# icyradio-main.net
KiCad netlist of a schematic drawn in EAGLE
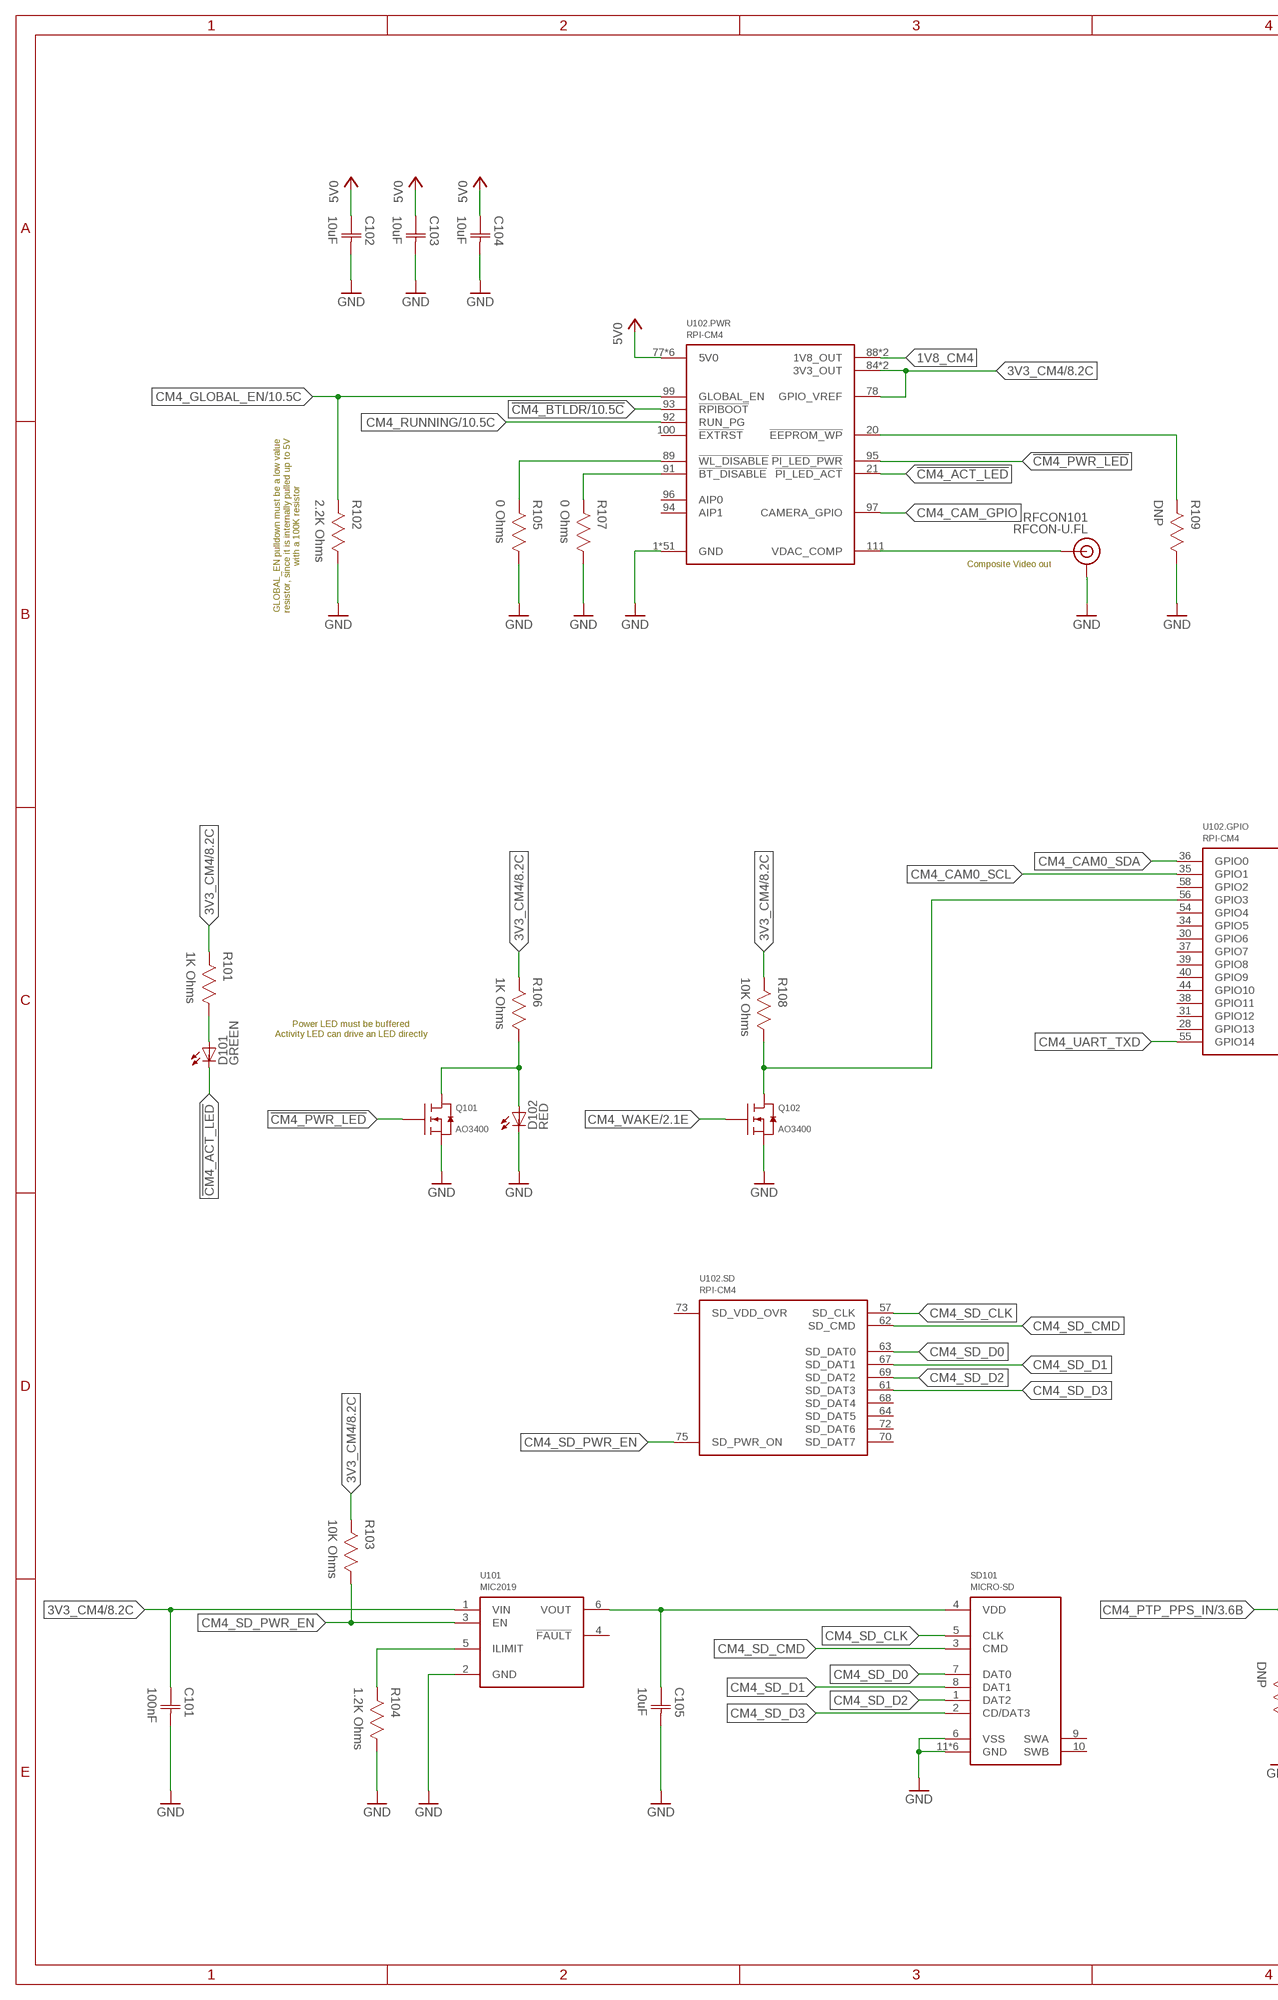
[diagram p0: schematic, sheet 1, part 1 of 2]
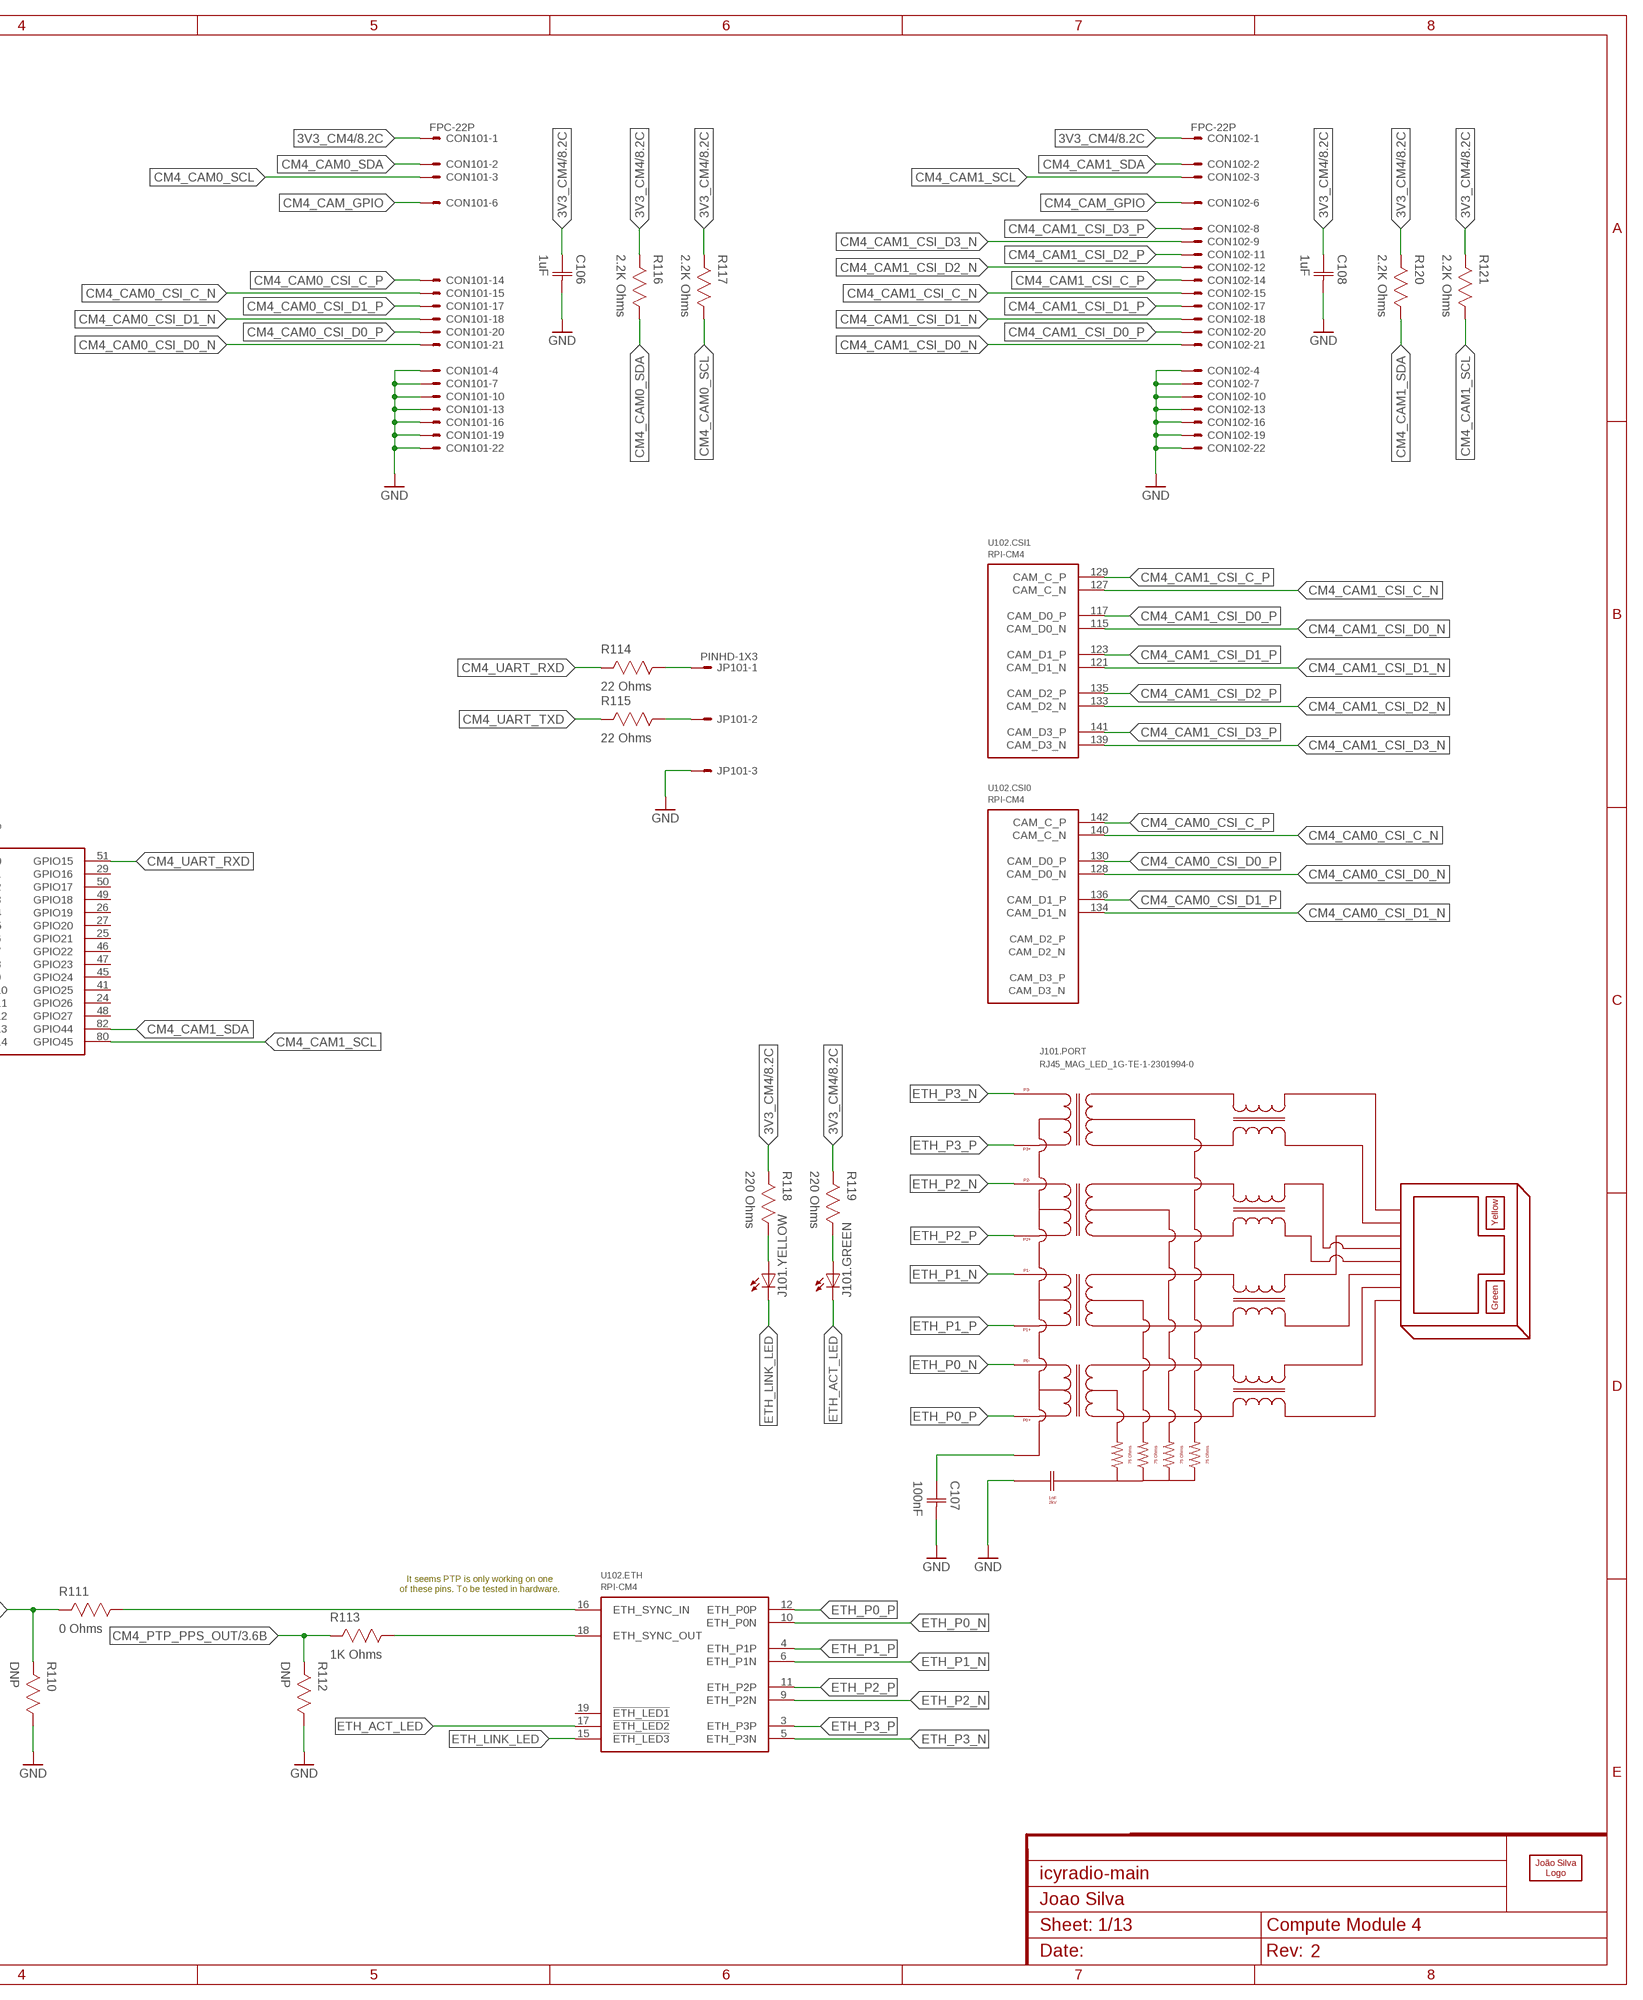
[diagram p1: schematic, sheet 1, part 2 of 2]
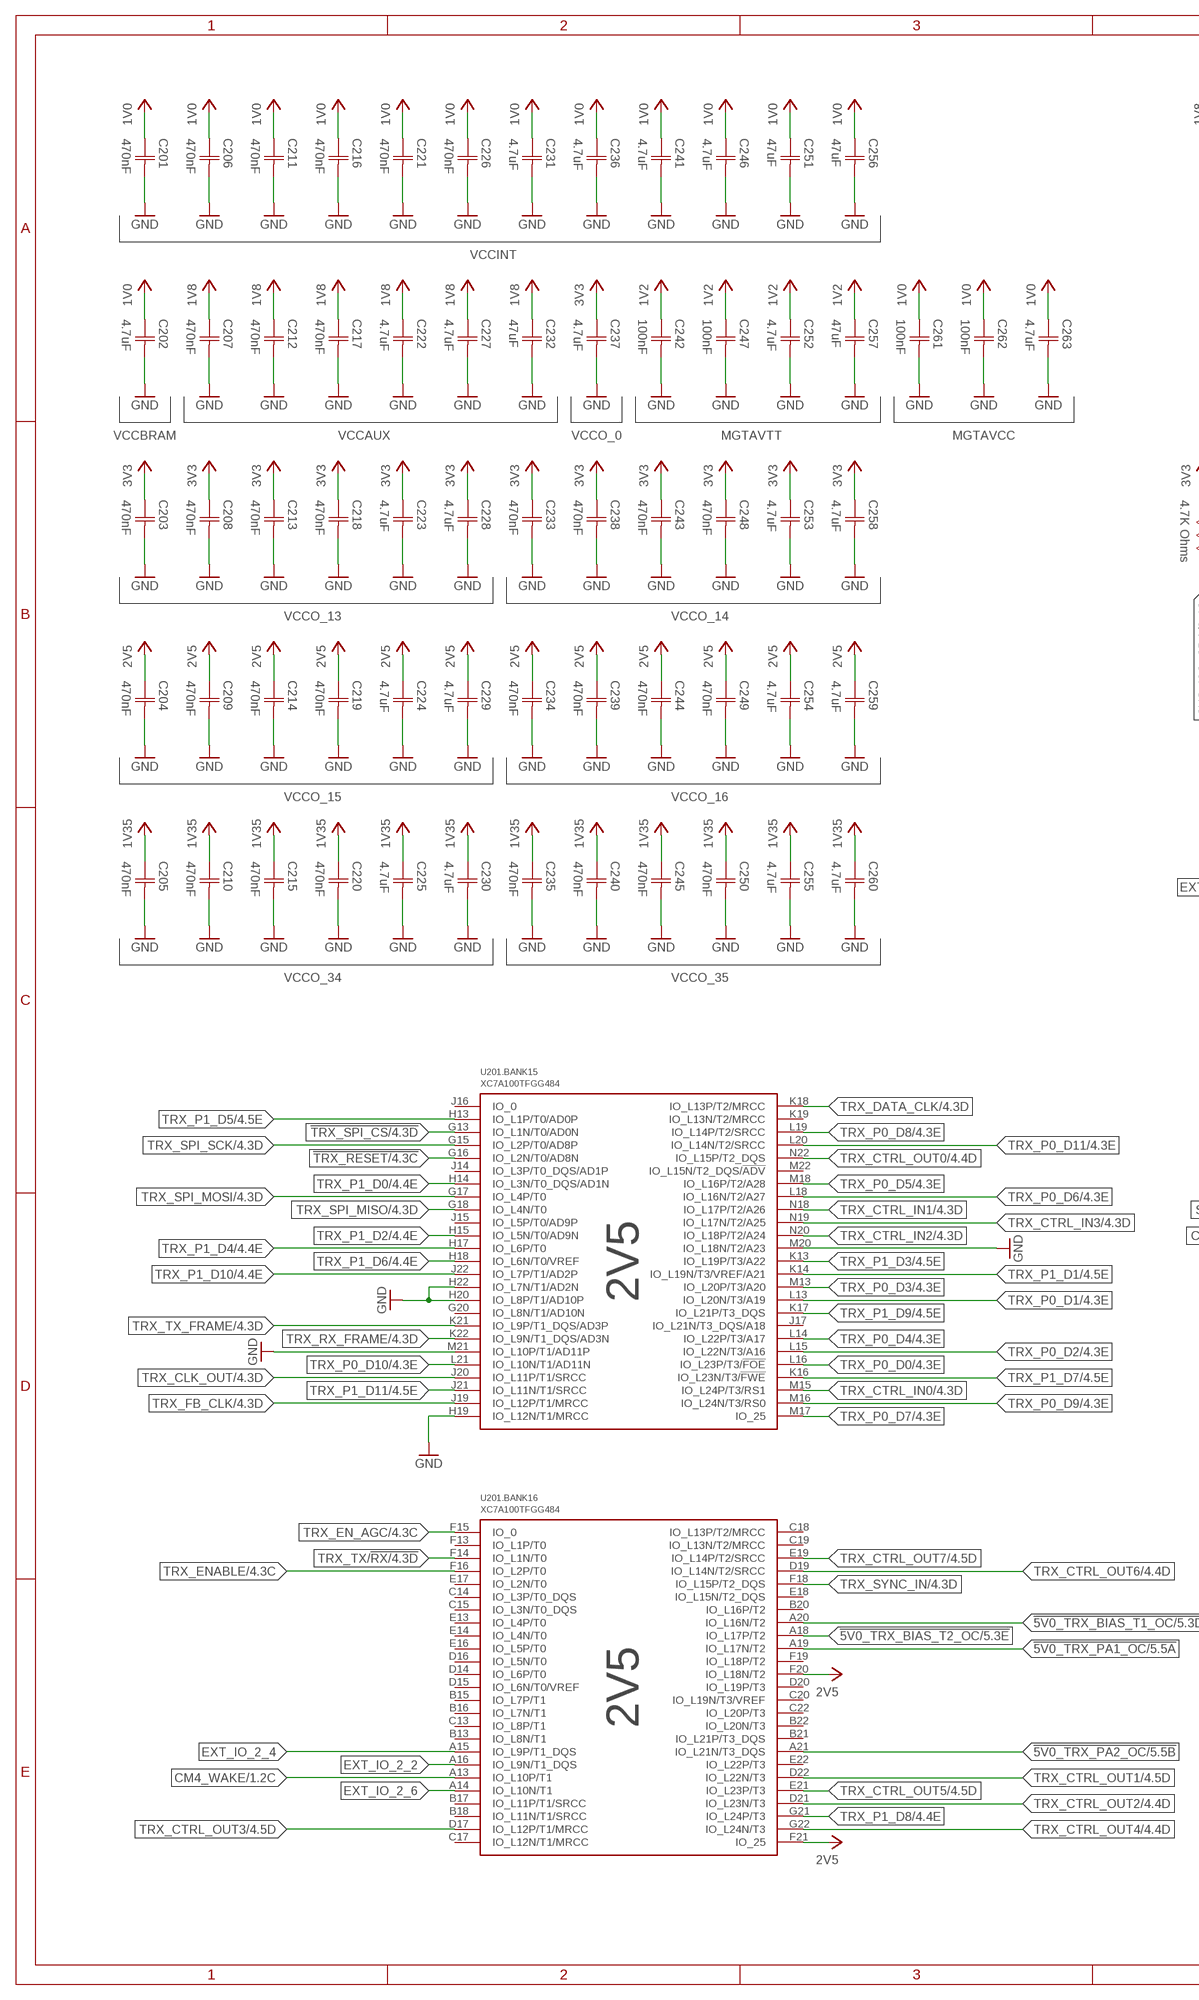
[diagram p2: schematic, sheet 2, part 1 of 2]
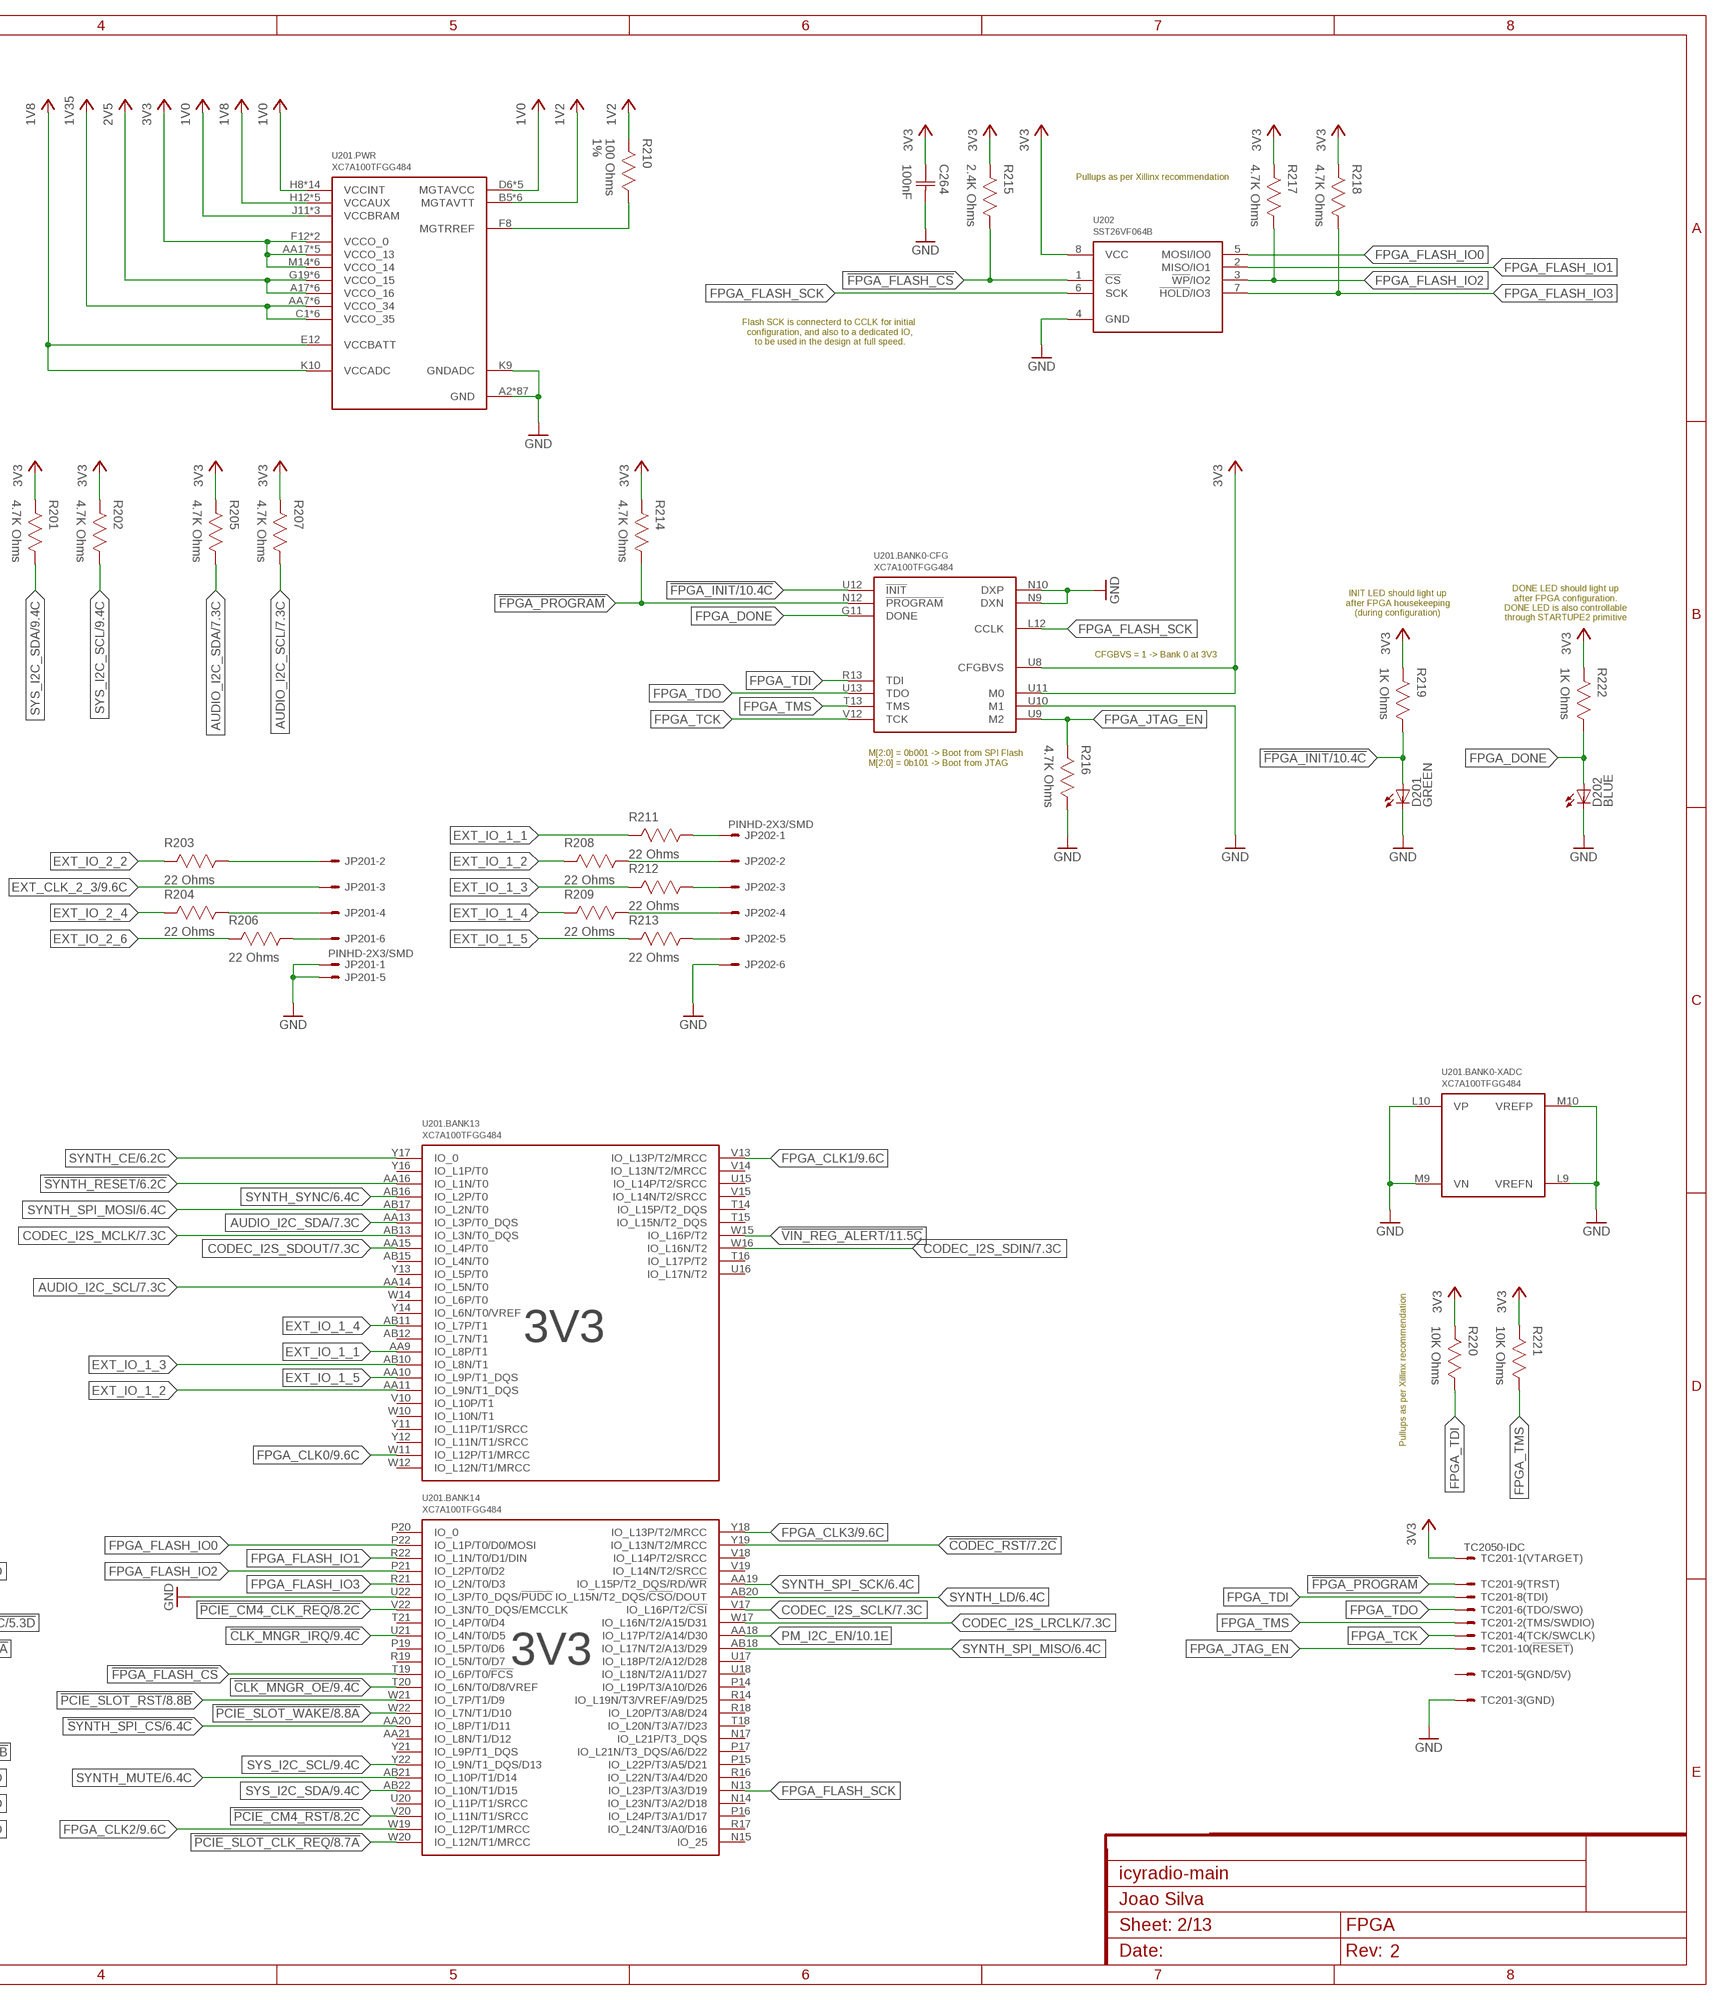
[diagram p3: schematic, sheet 2, part 2 of 2]
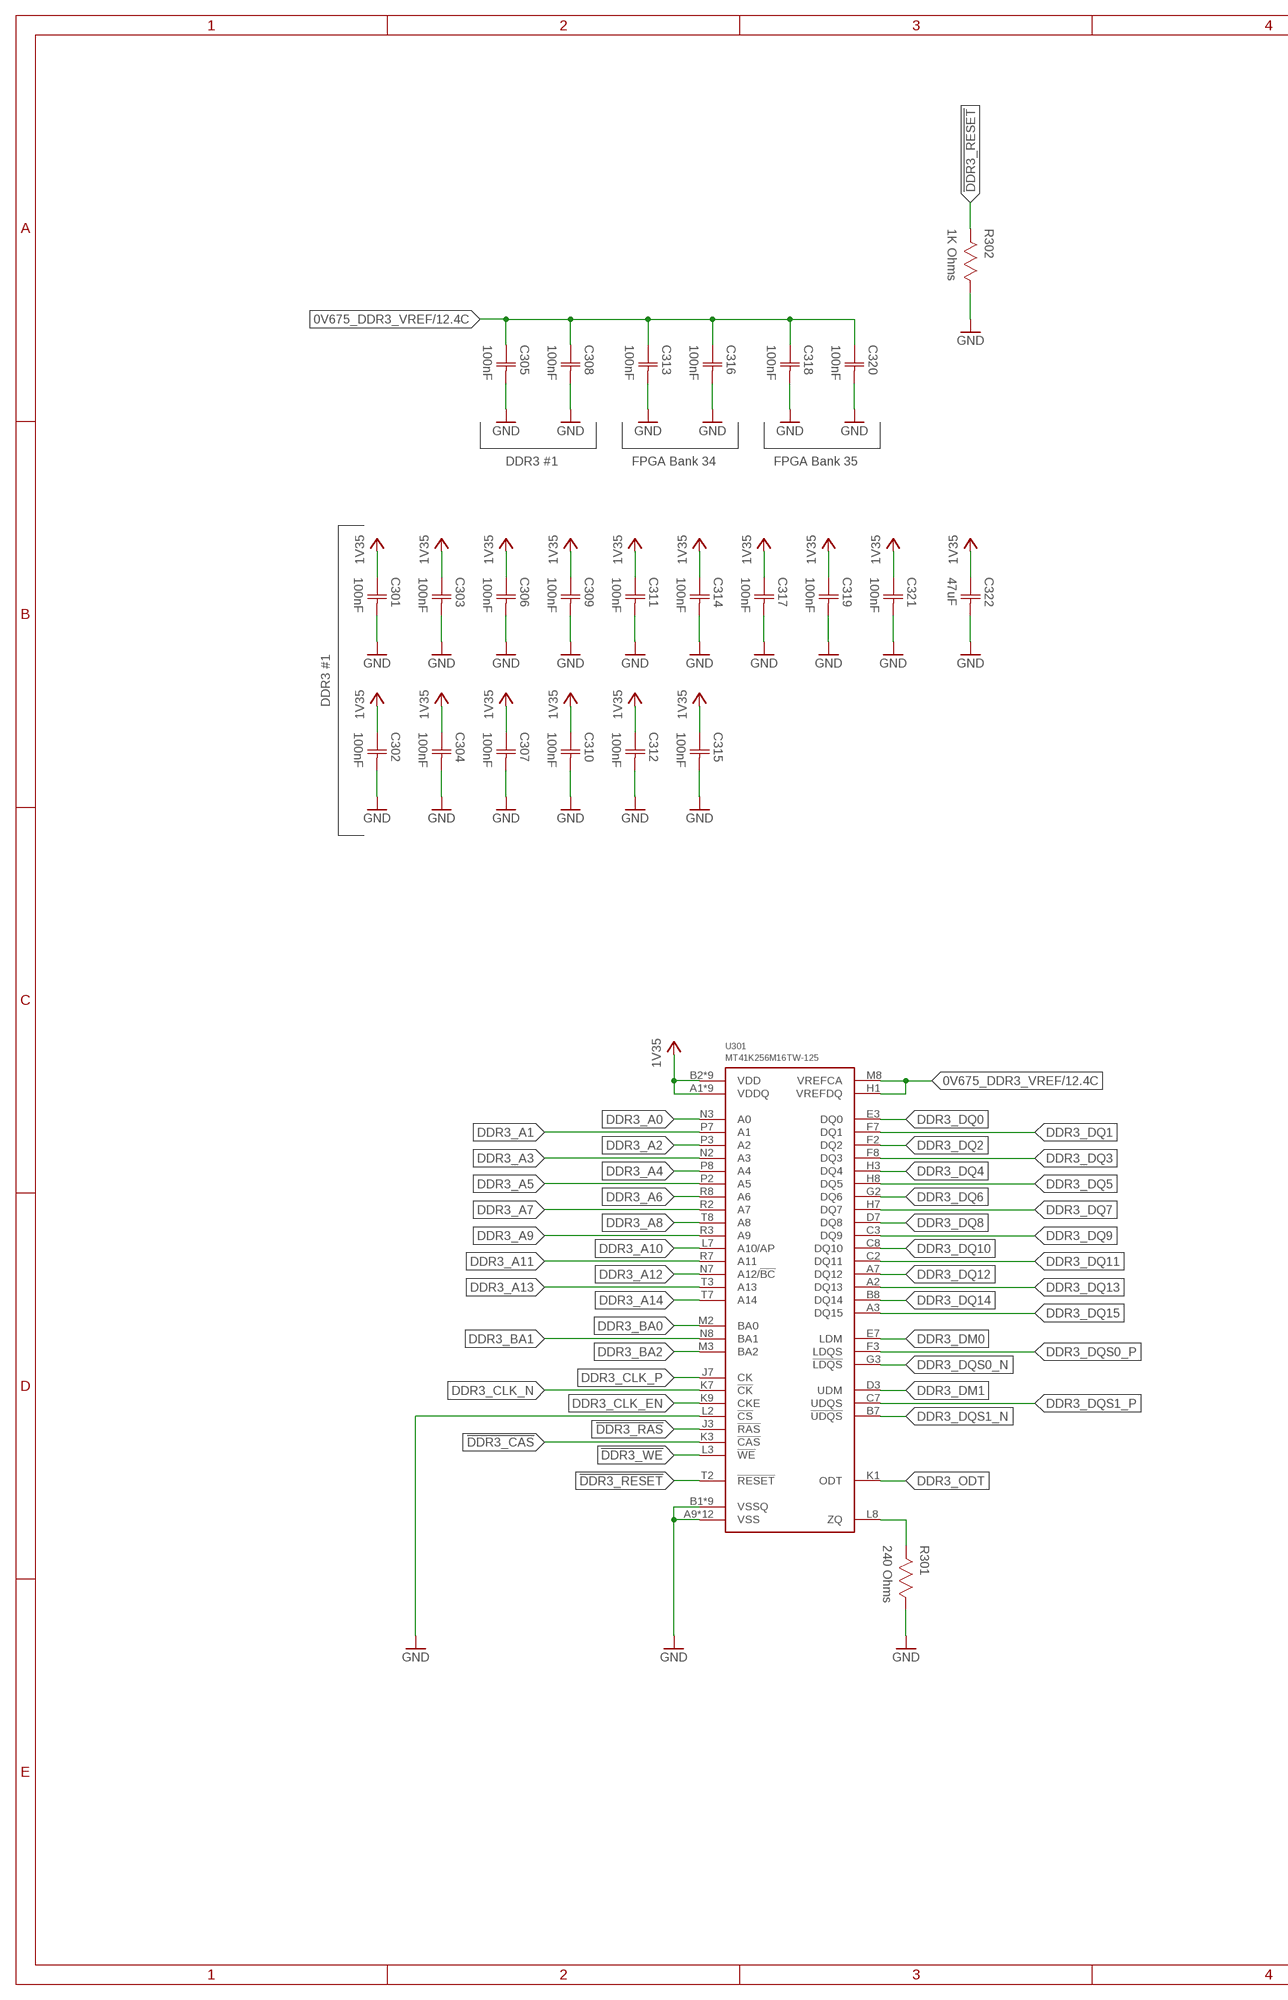
[diagram p4: schematic, sheet 3, part 1 of 2]
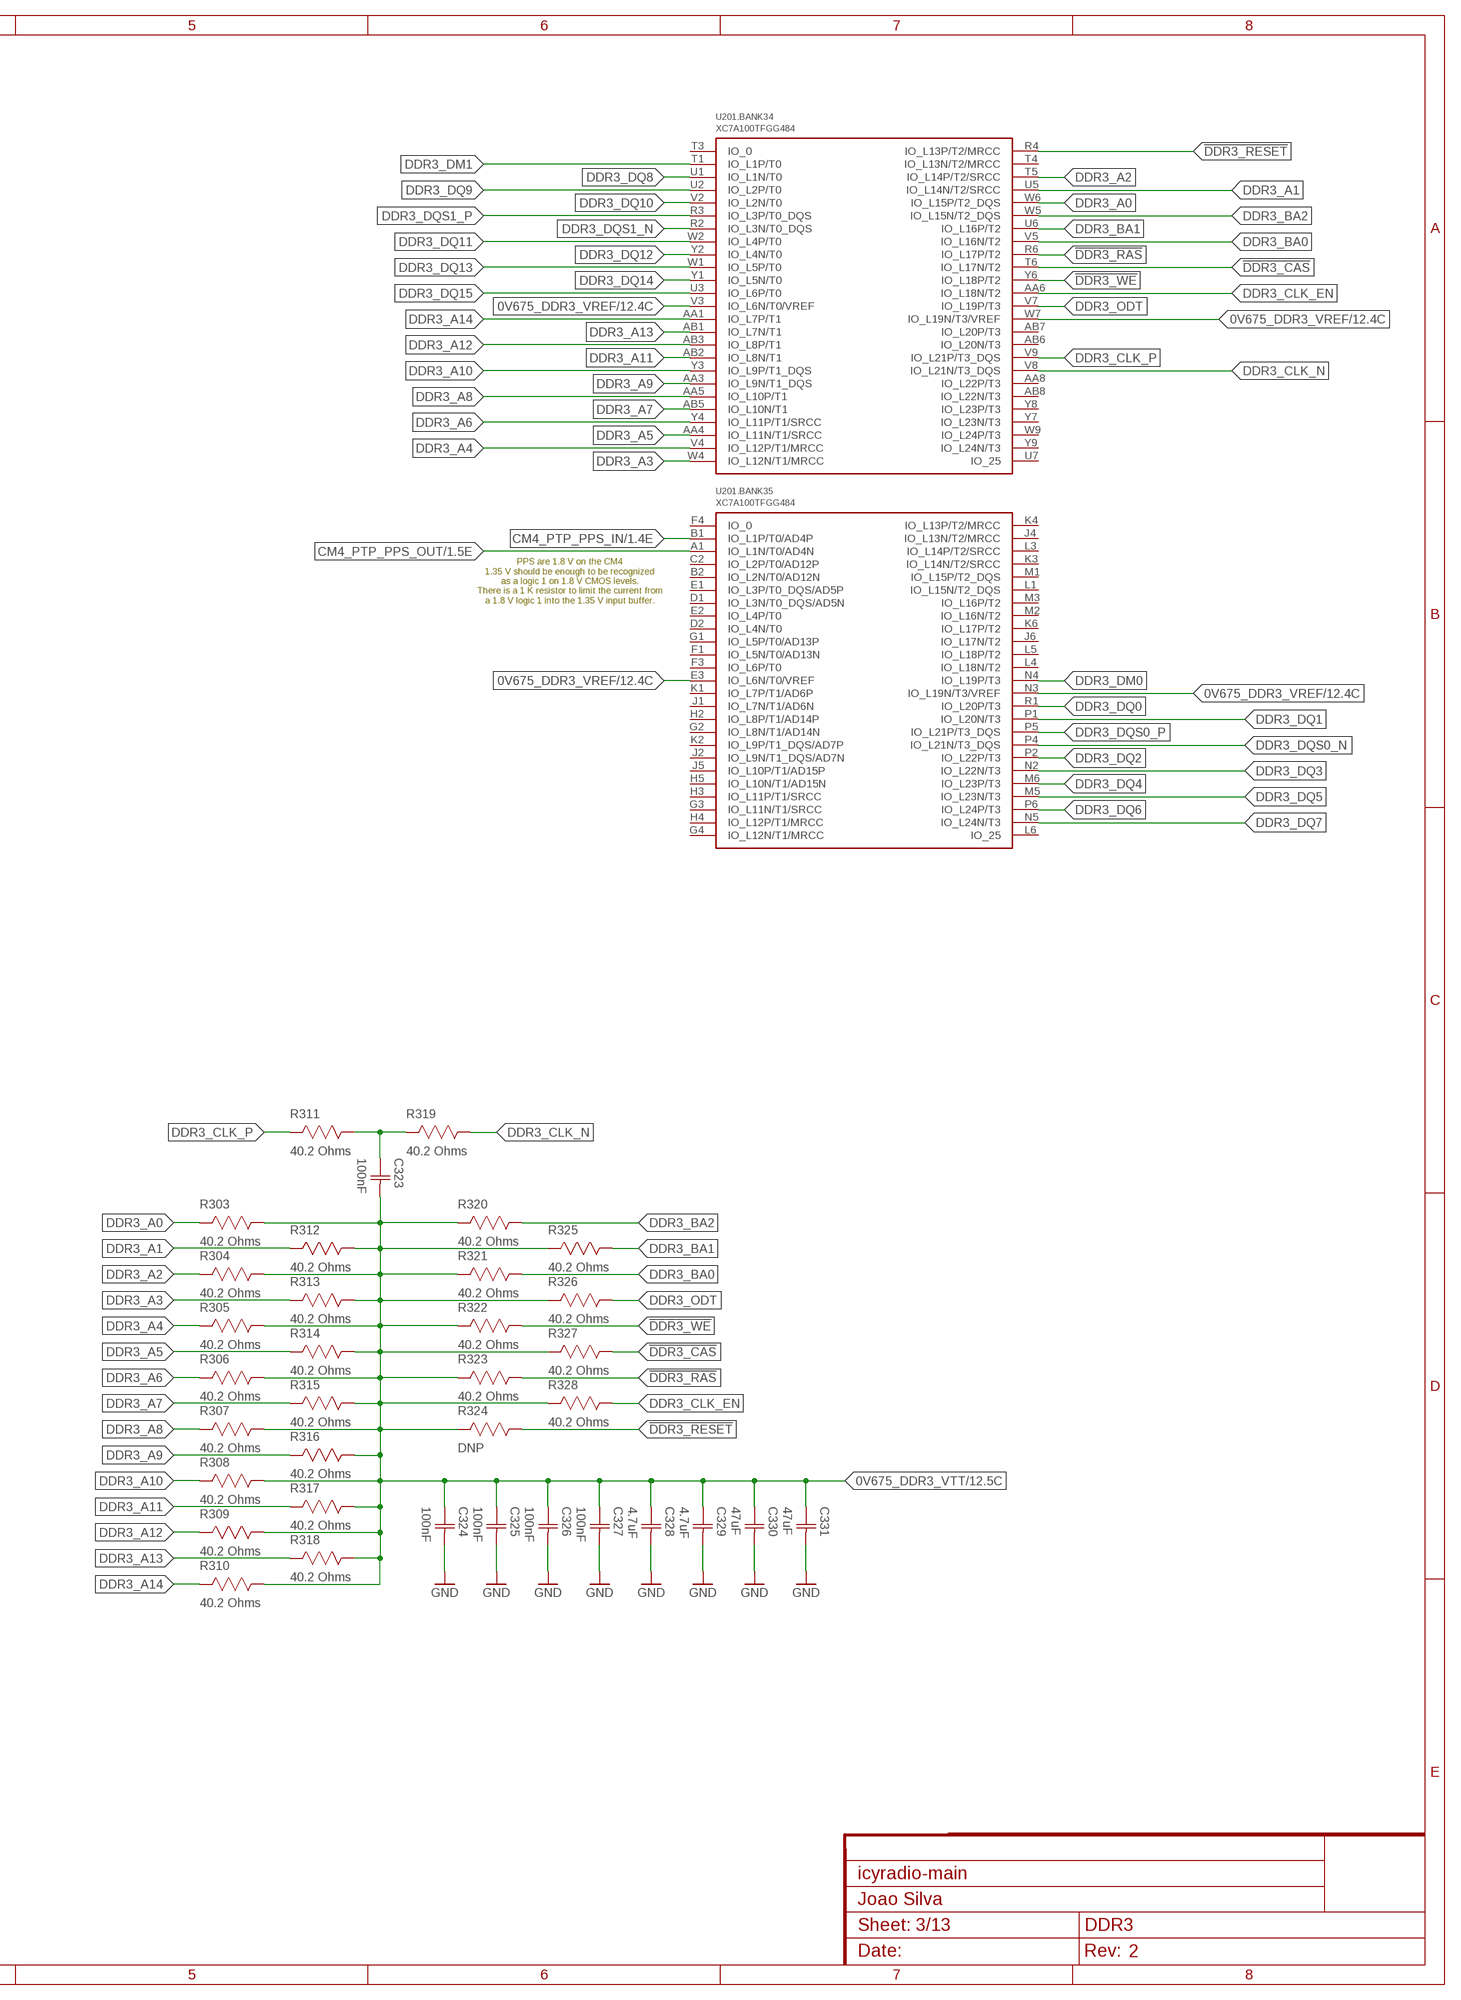
[diagram p5: schematic, sheet 3, part 2 of 2]
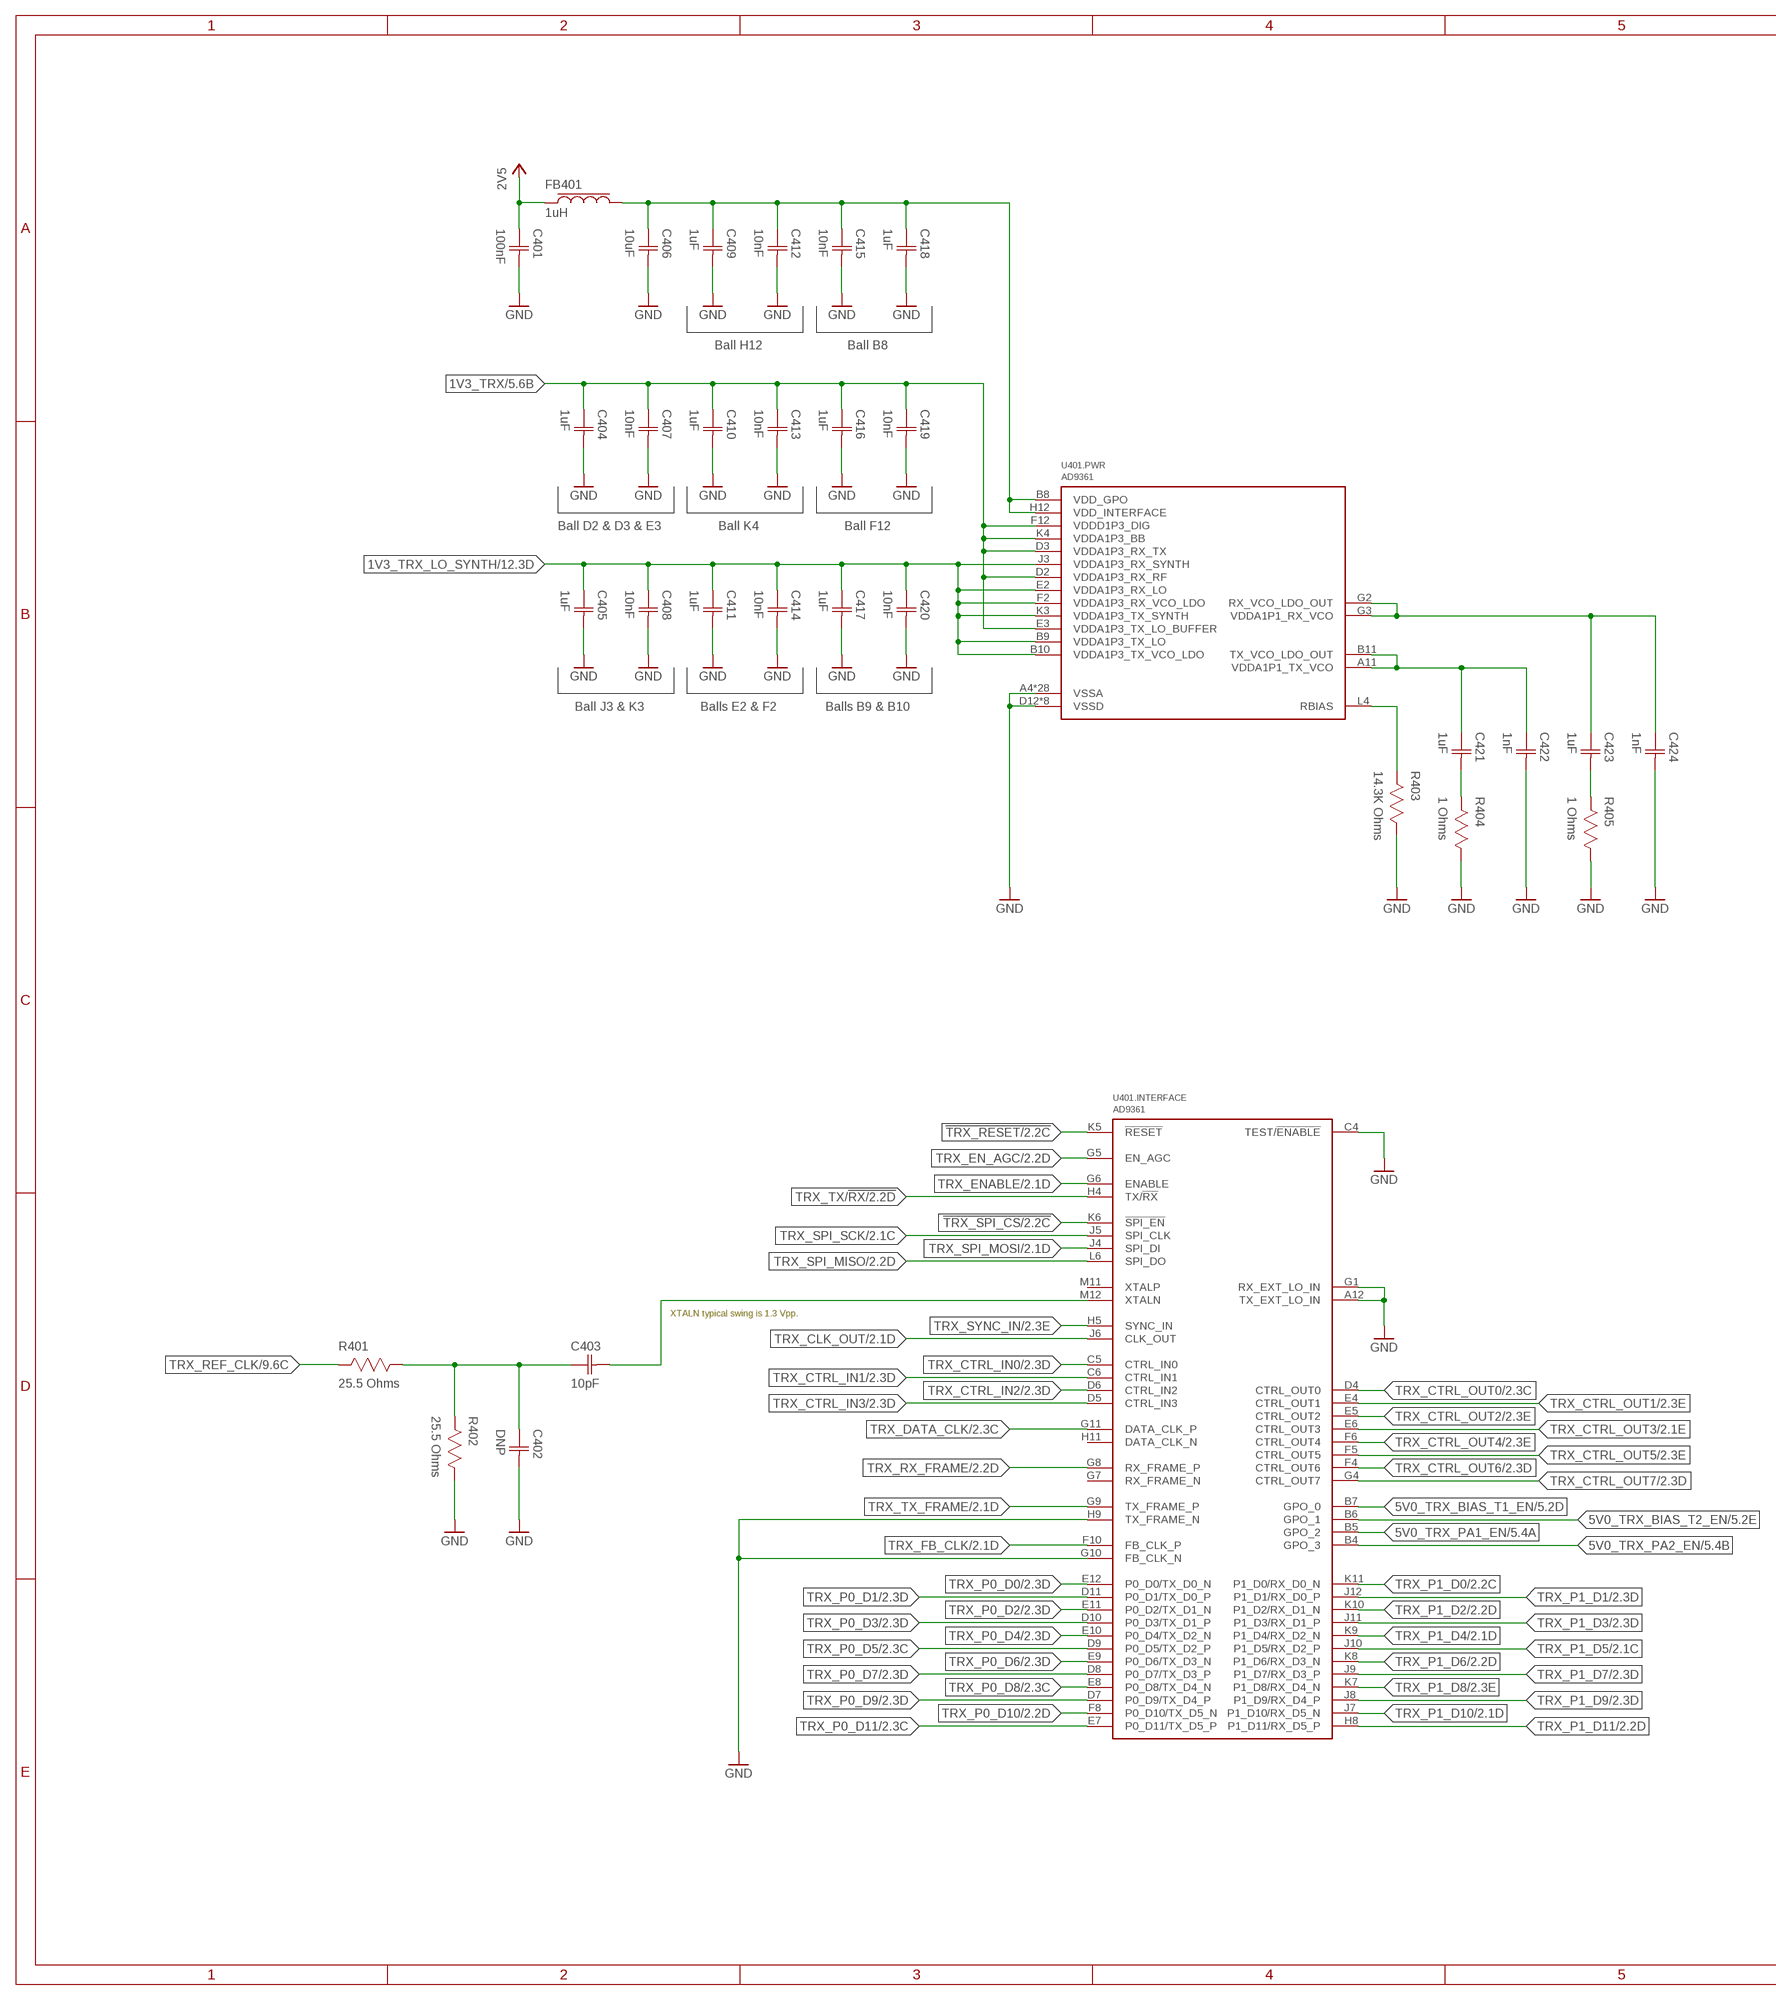
[diagram p6: schematic, sheet 4, part 1 of 2]
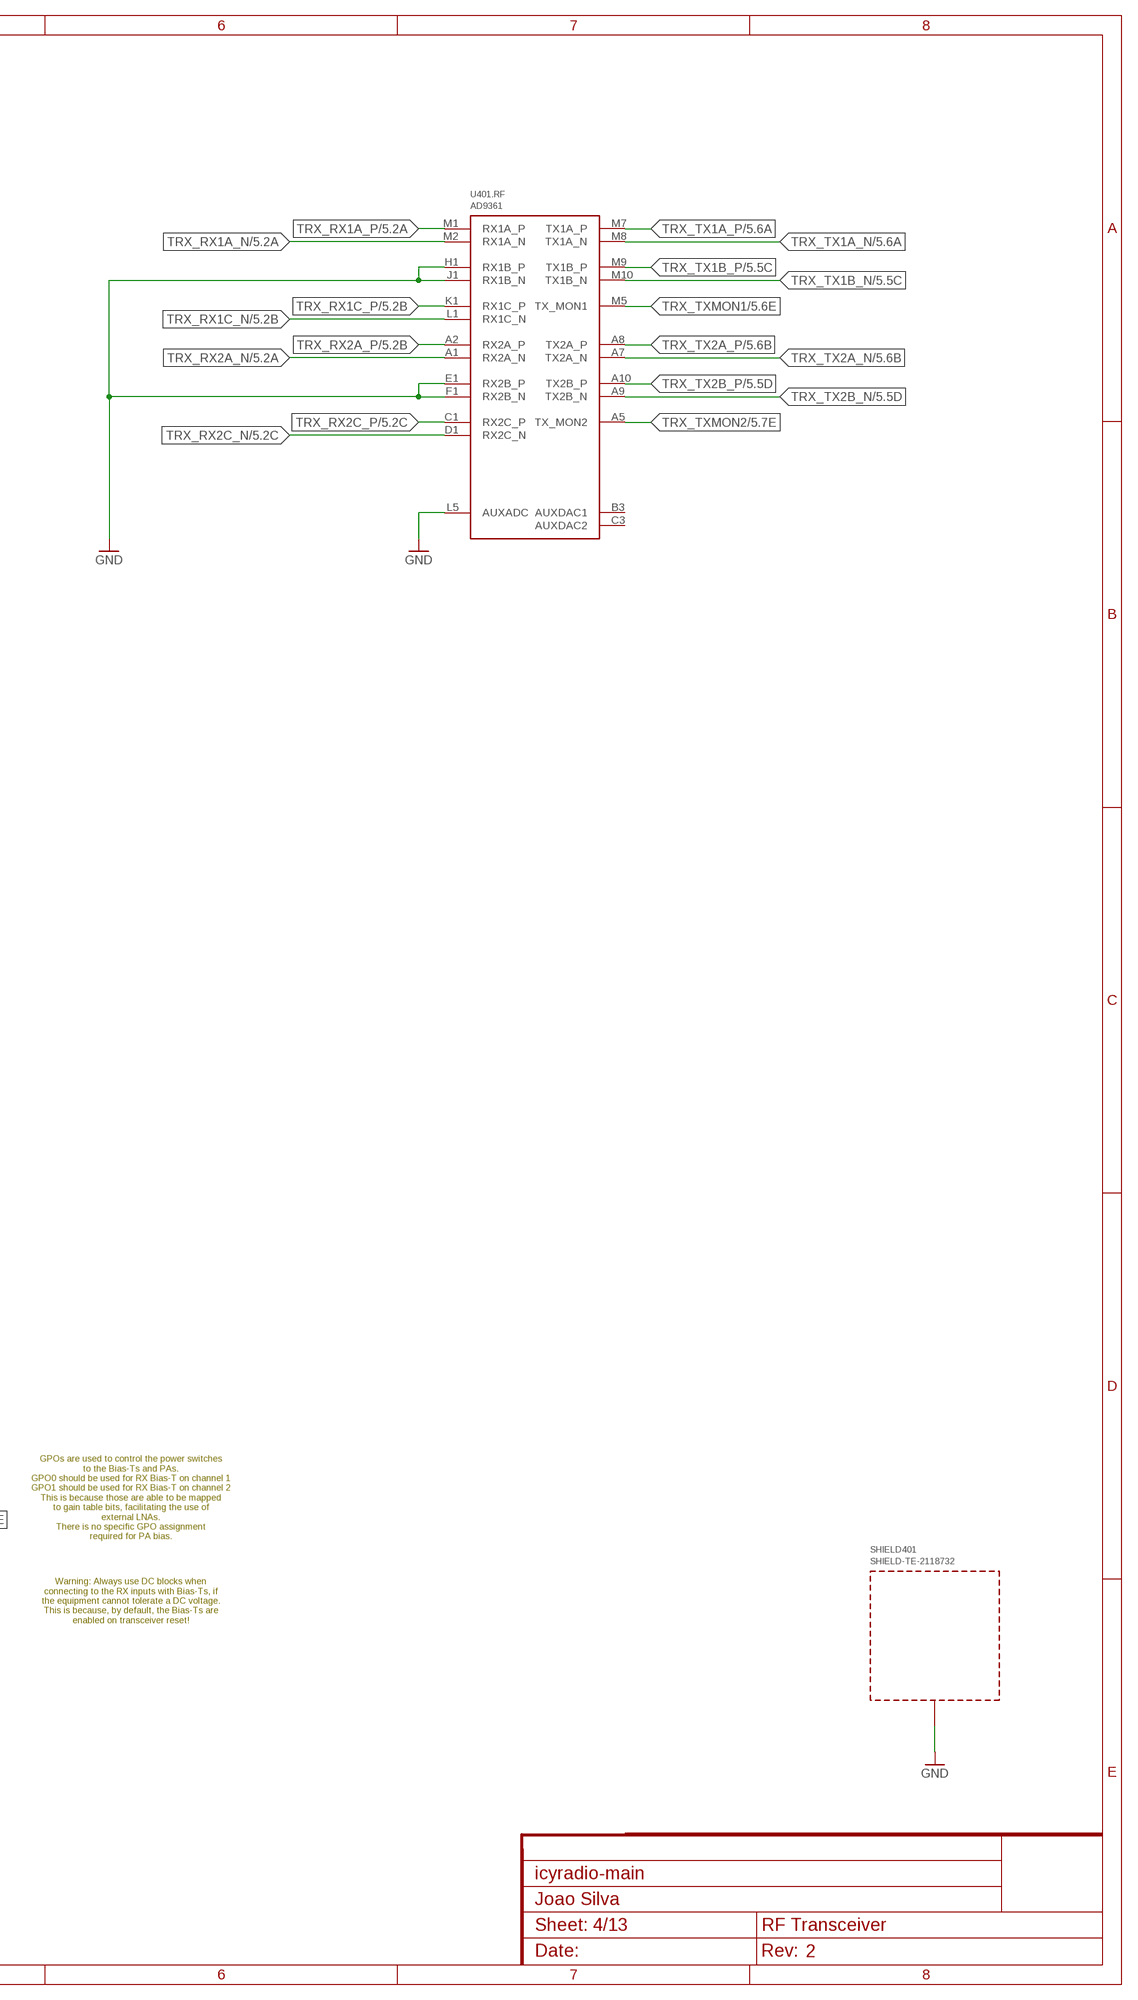
[diagram p7: schematic, sheet 4, part 2 of 2]
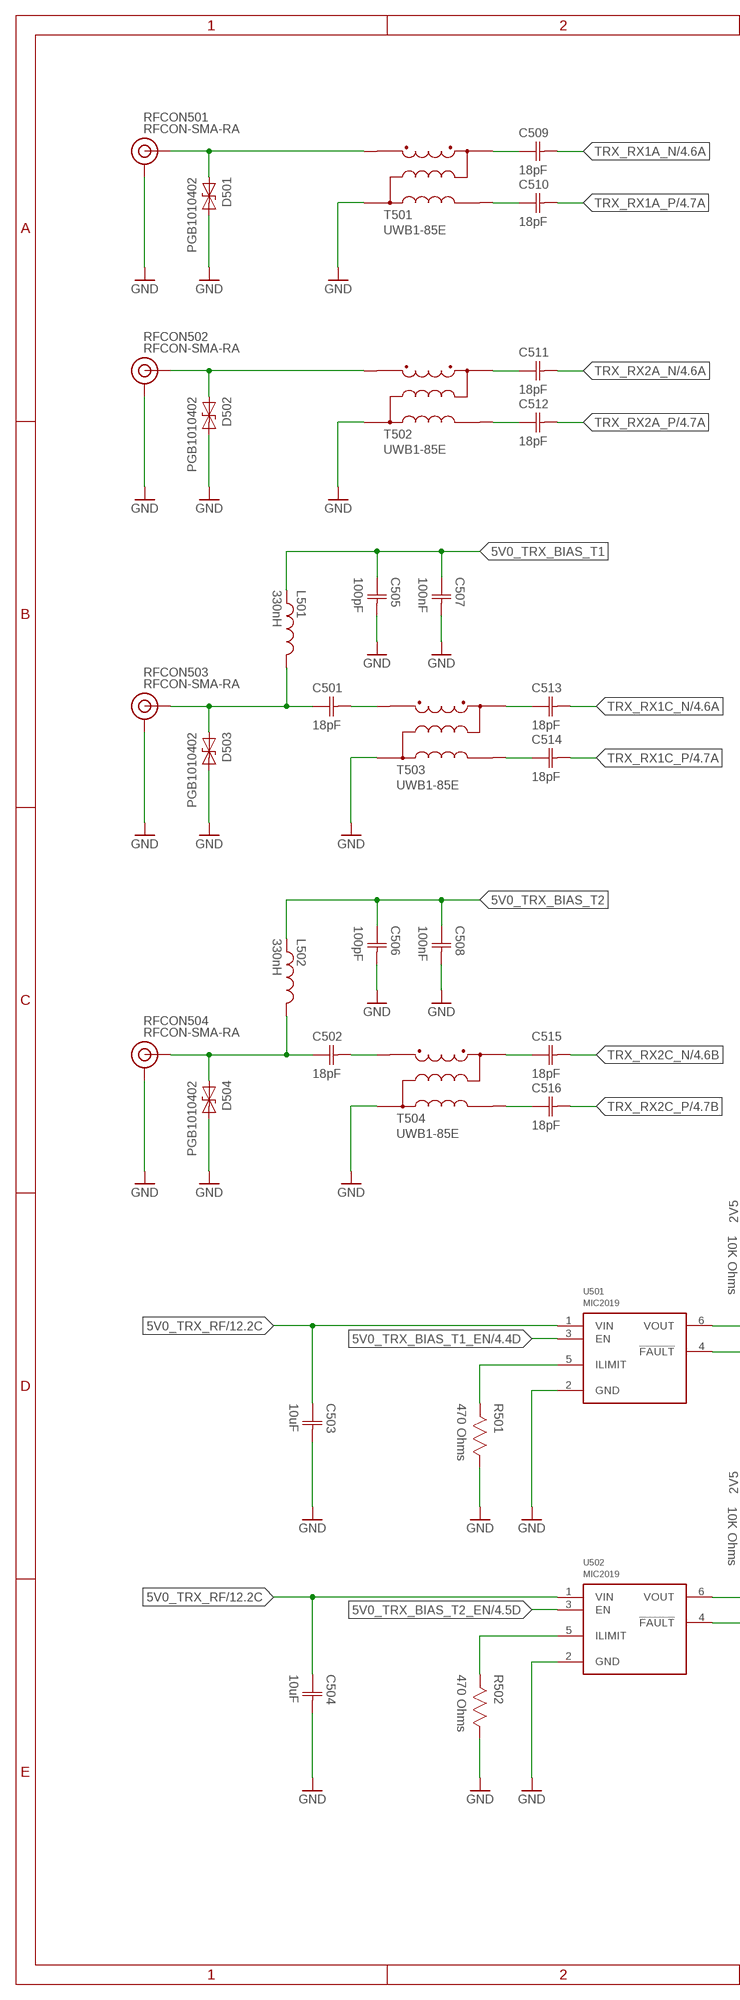
[diagram p8: schematic, sheet 5, part 1 of 2]
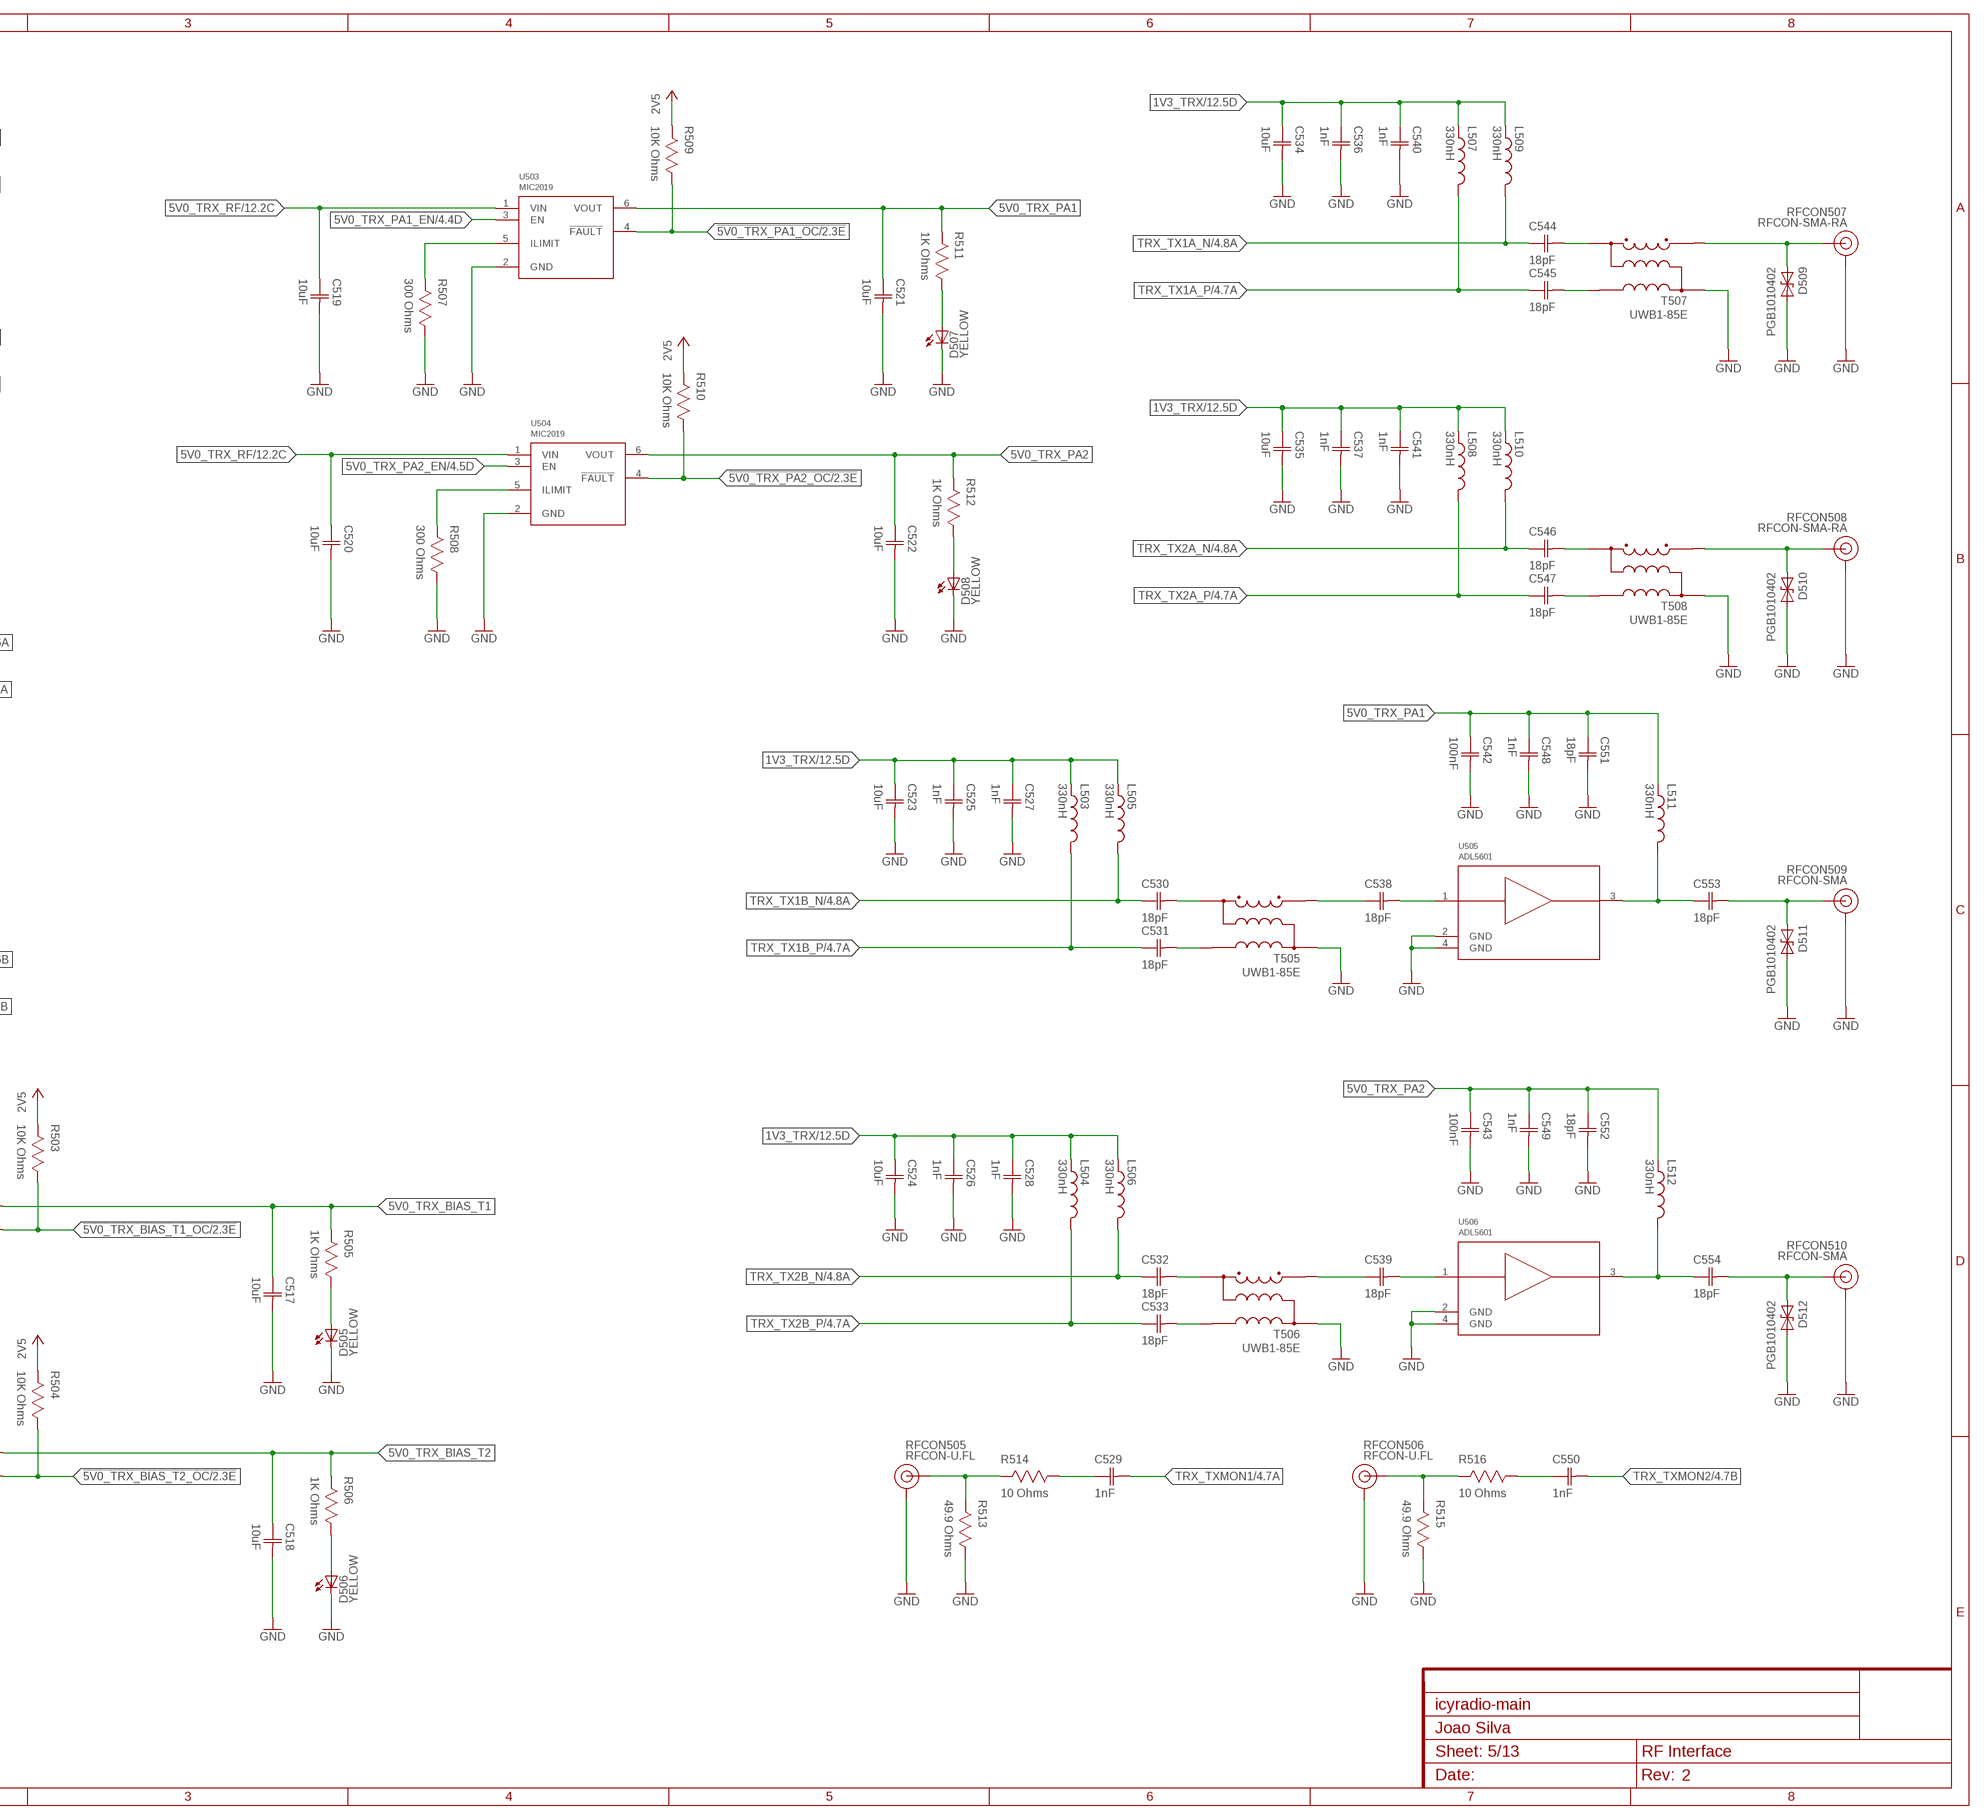
[diagram p9: schematic, sheet 5, part 2 of 2]
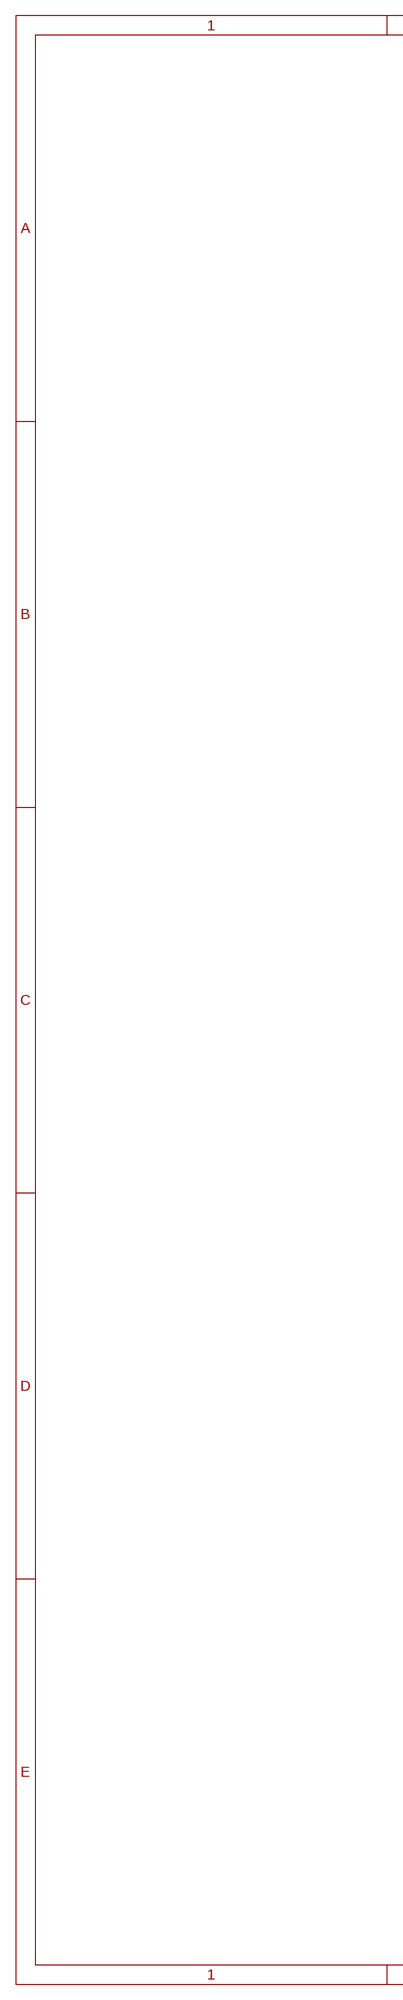
[diagram p10: schematic, sheet 6, part 1 of 2]
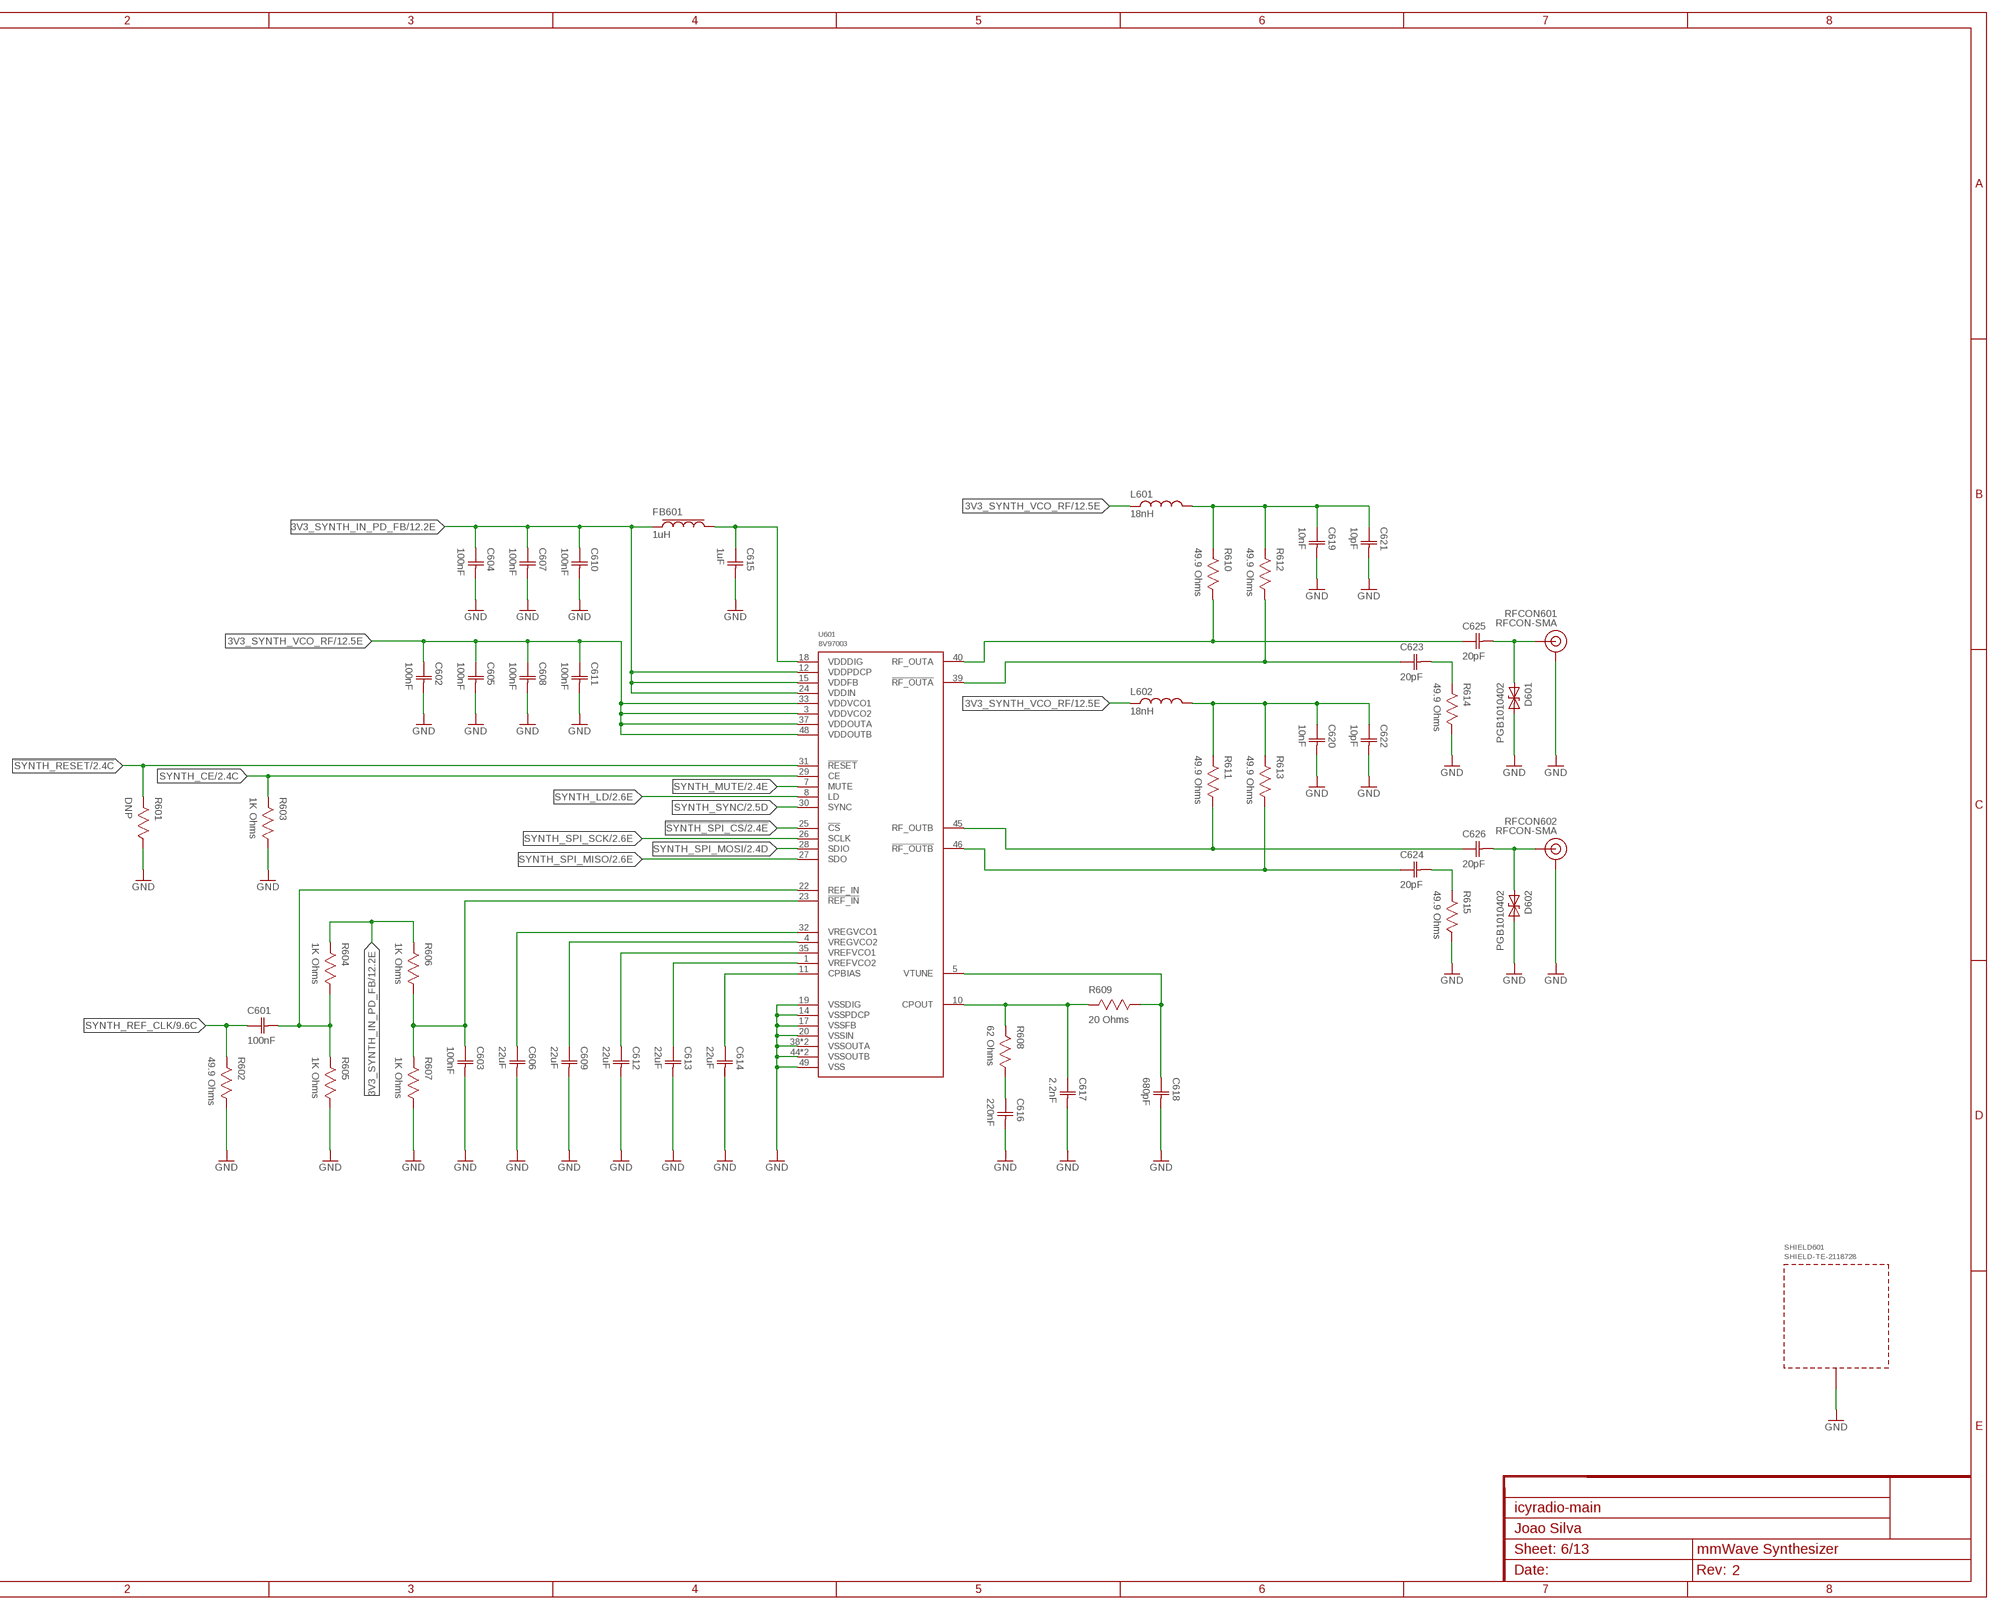
[diagram p11: schematic, sheet 6, part 2 of 2]
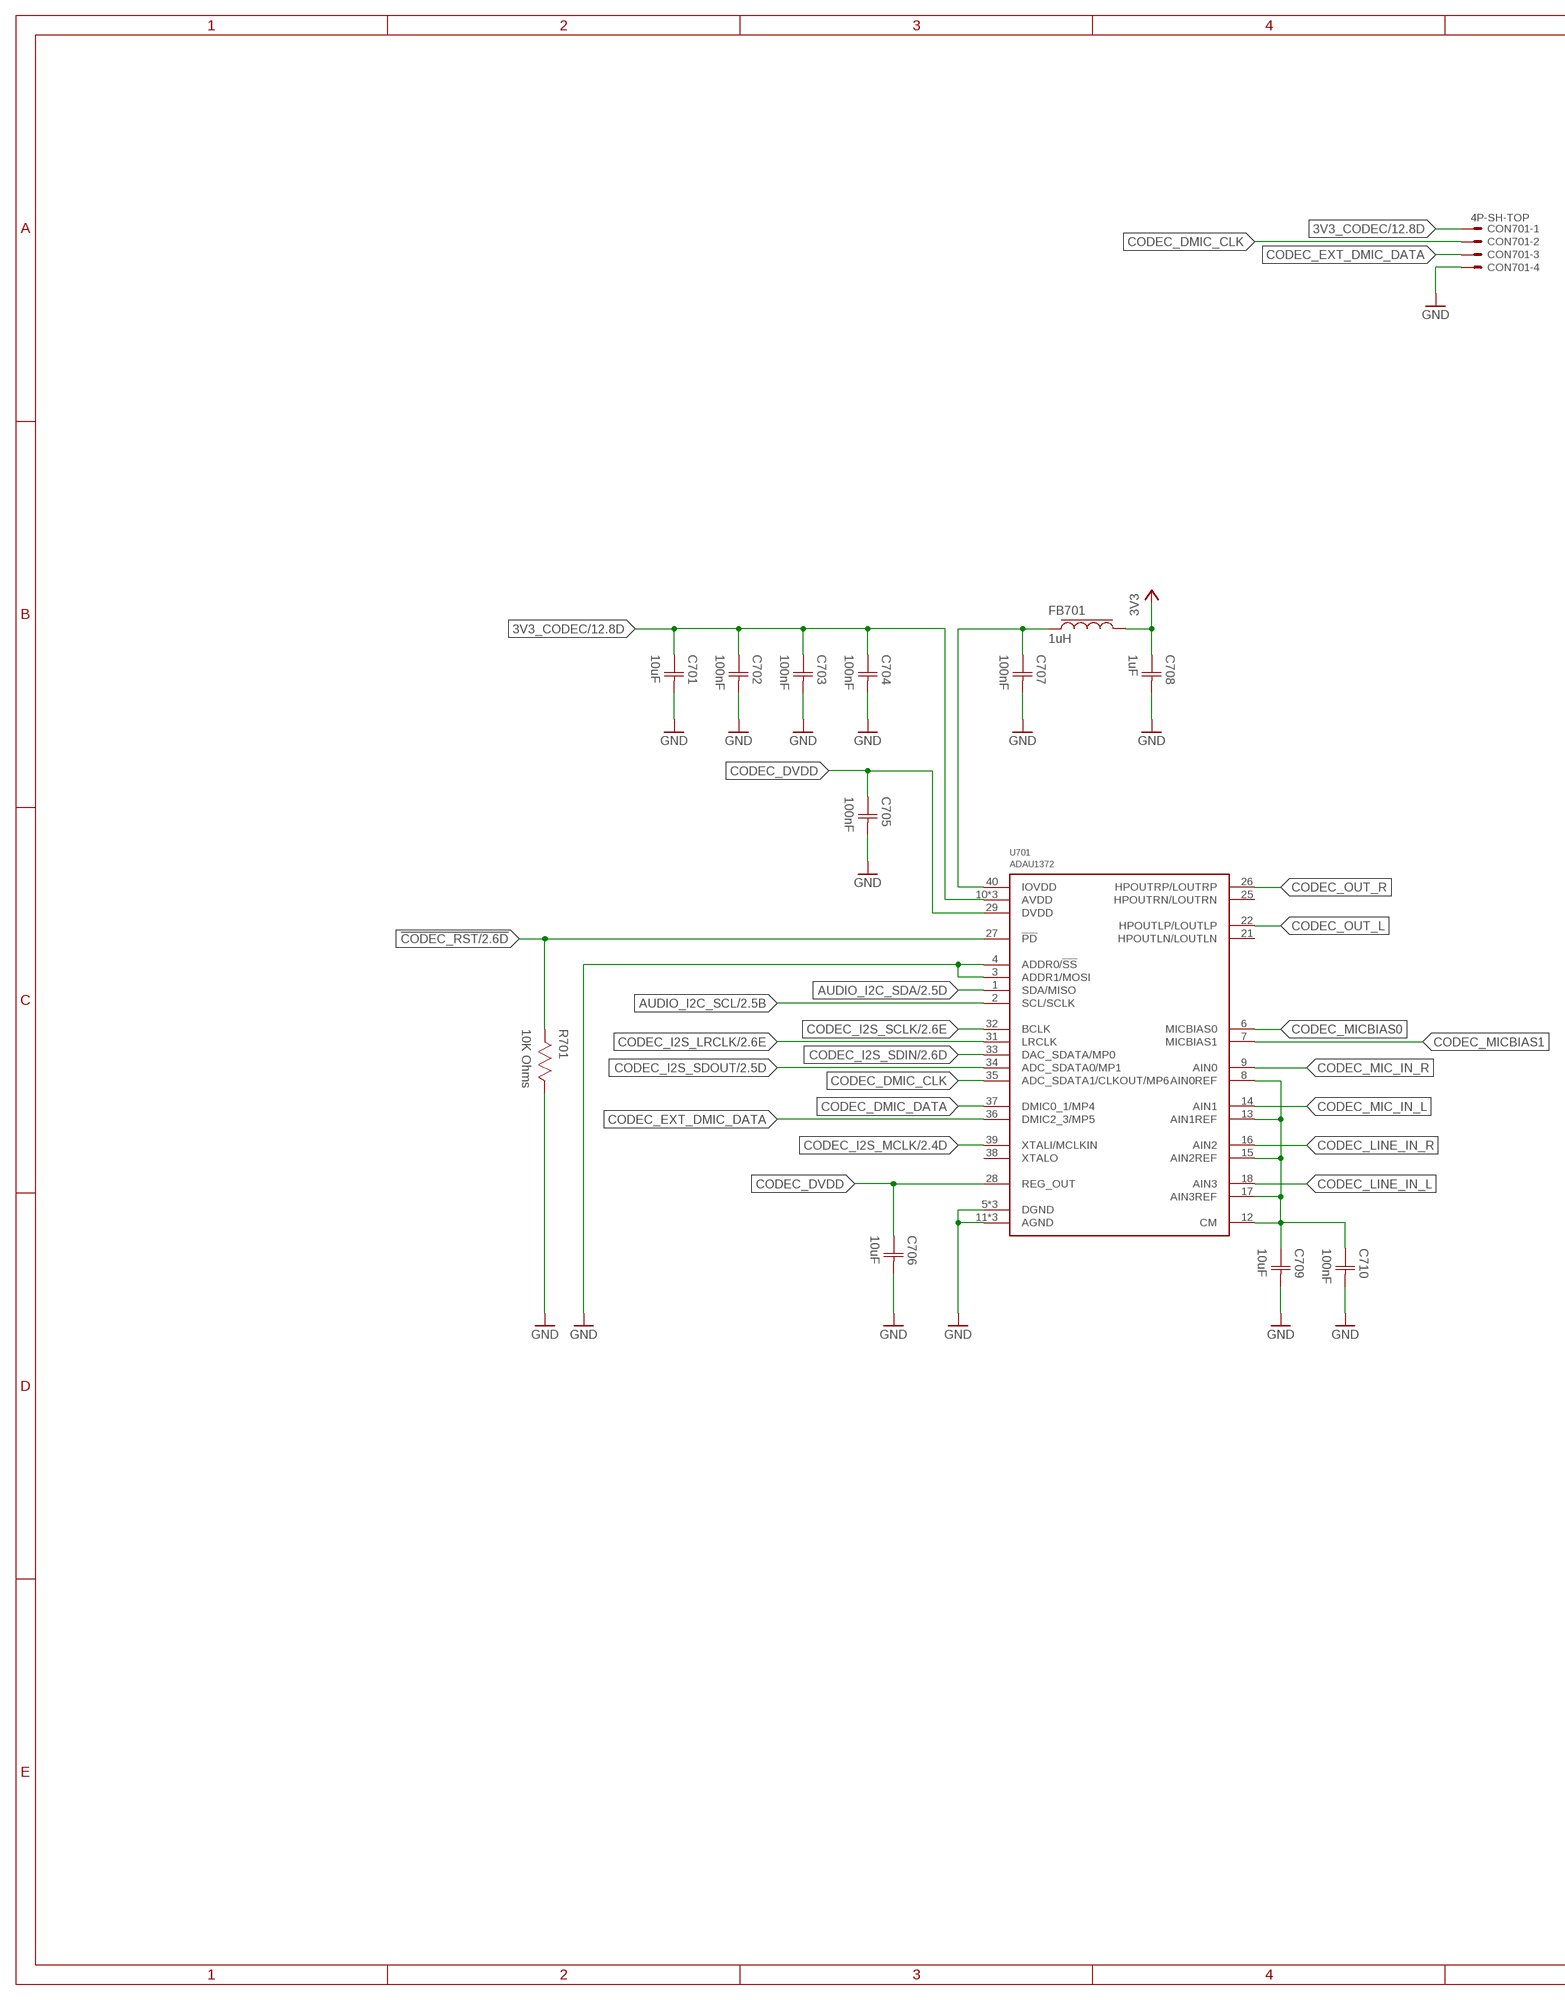
[diagram p12: schematic, sheet 7, part 1 of 2]
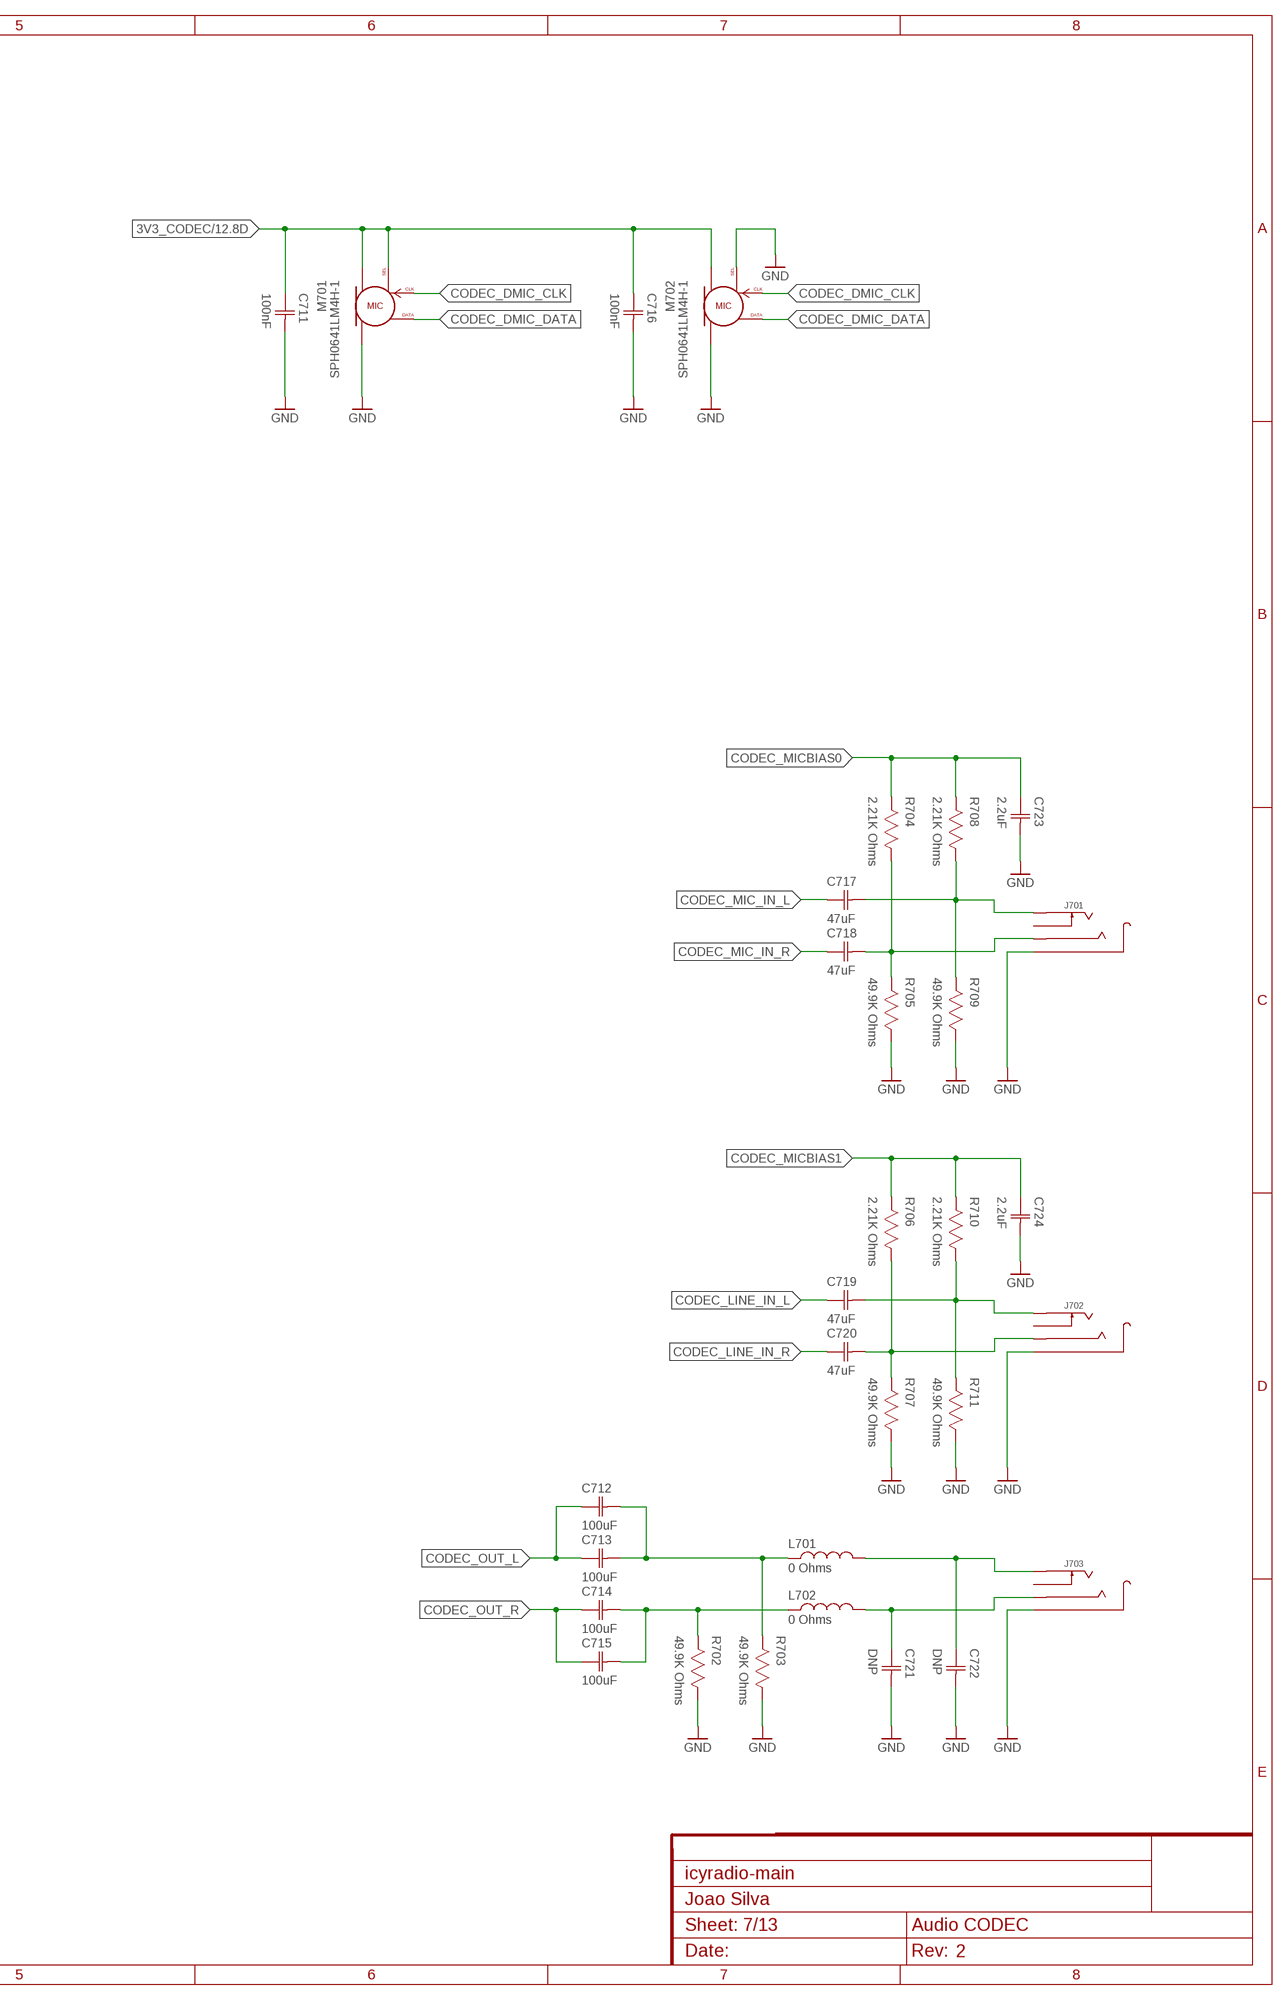
[diagram p13: schematic, sheet 7, part 2 of 2]
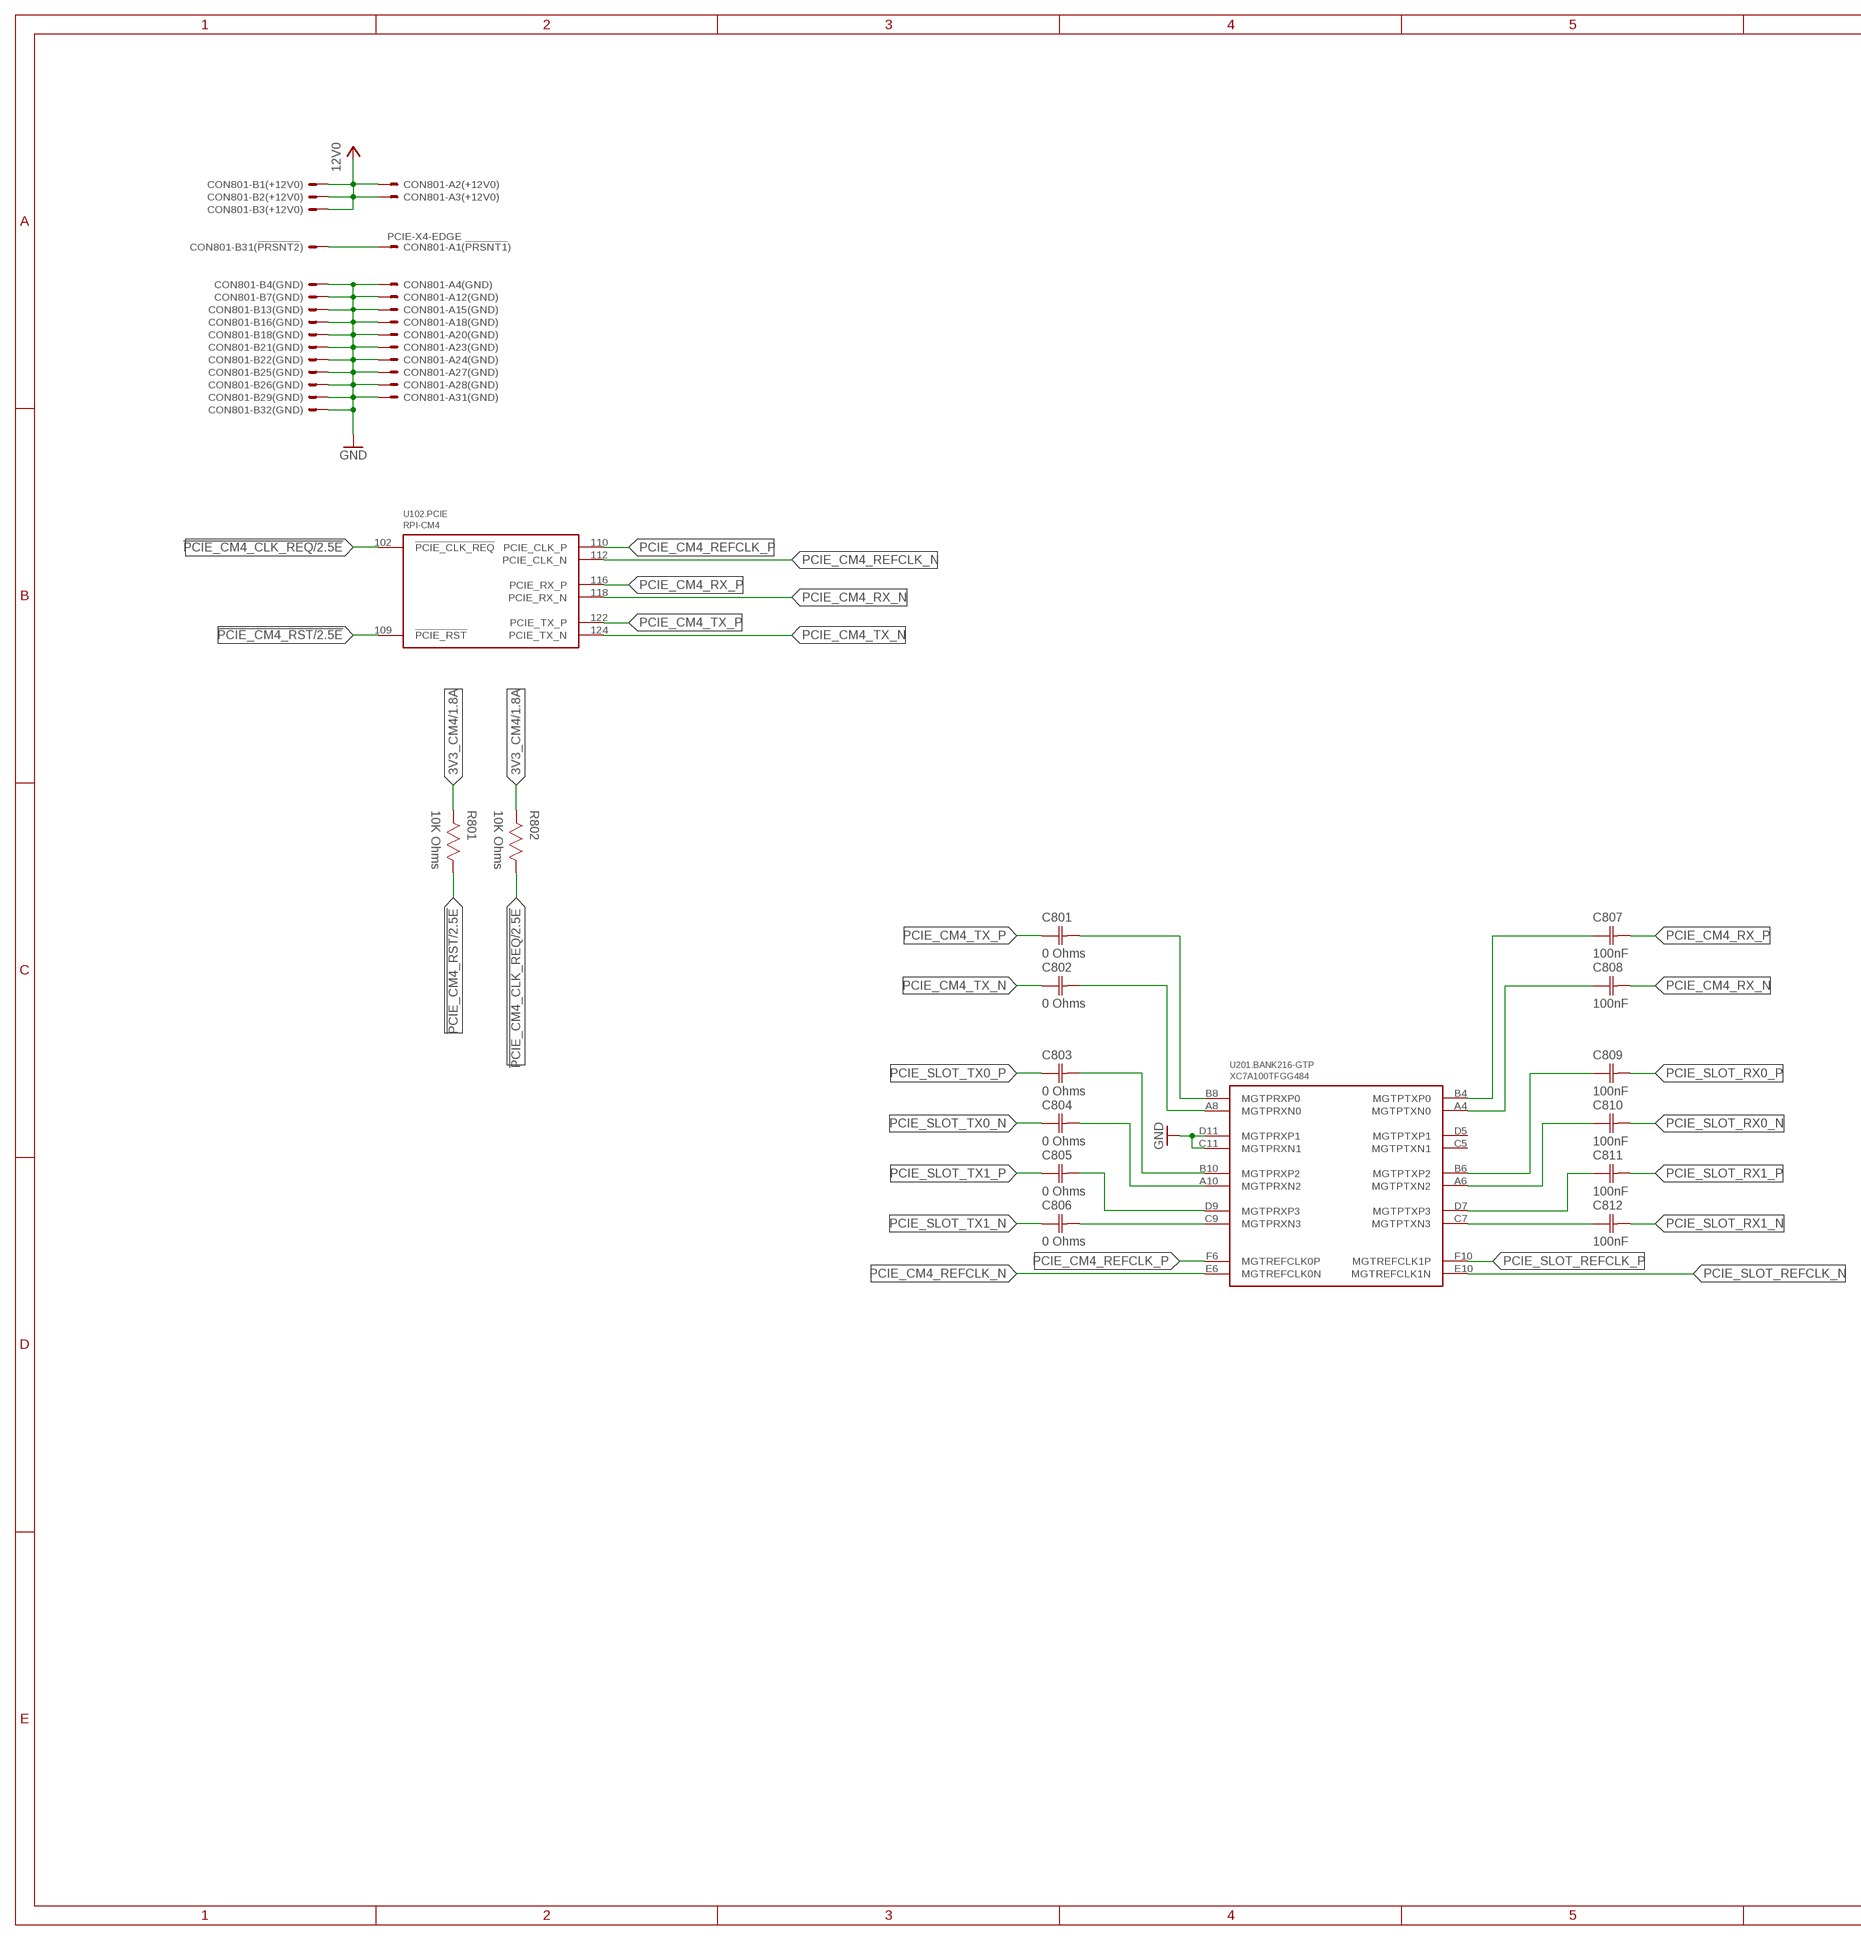
[diagram p14: schematic, sheet 8, part 1 of 2]
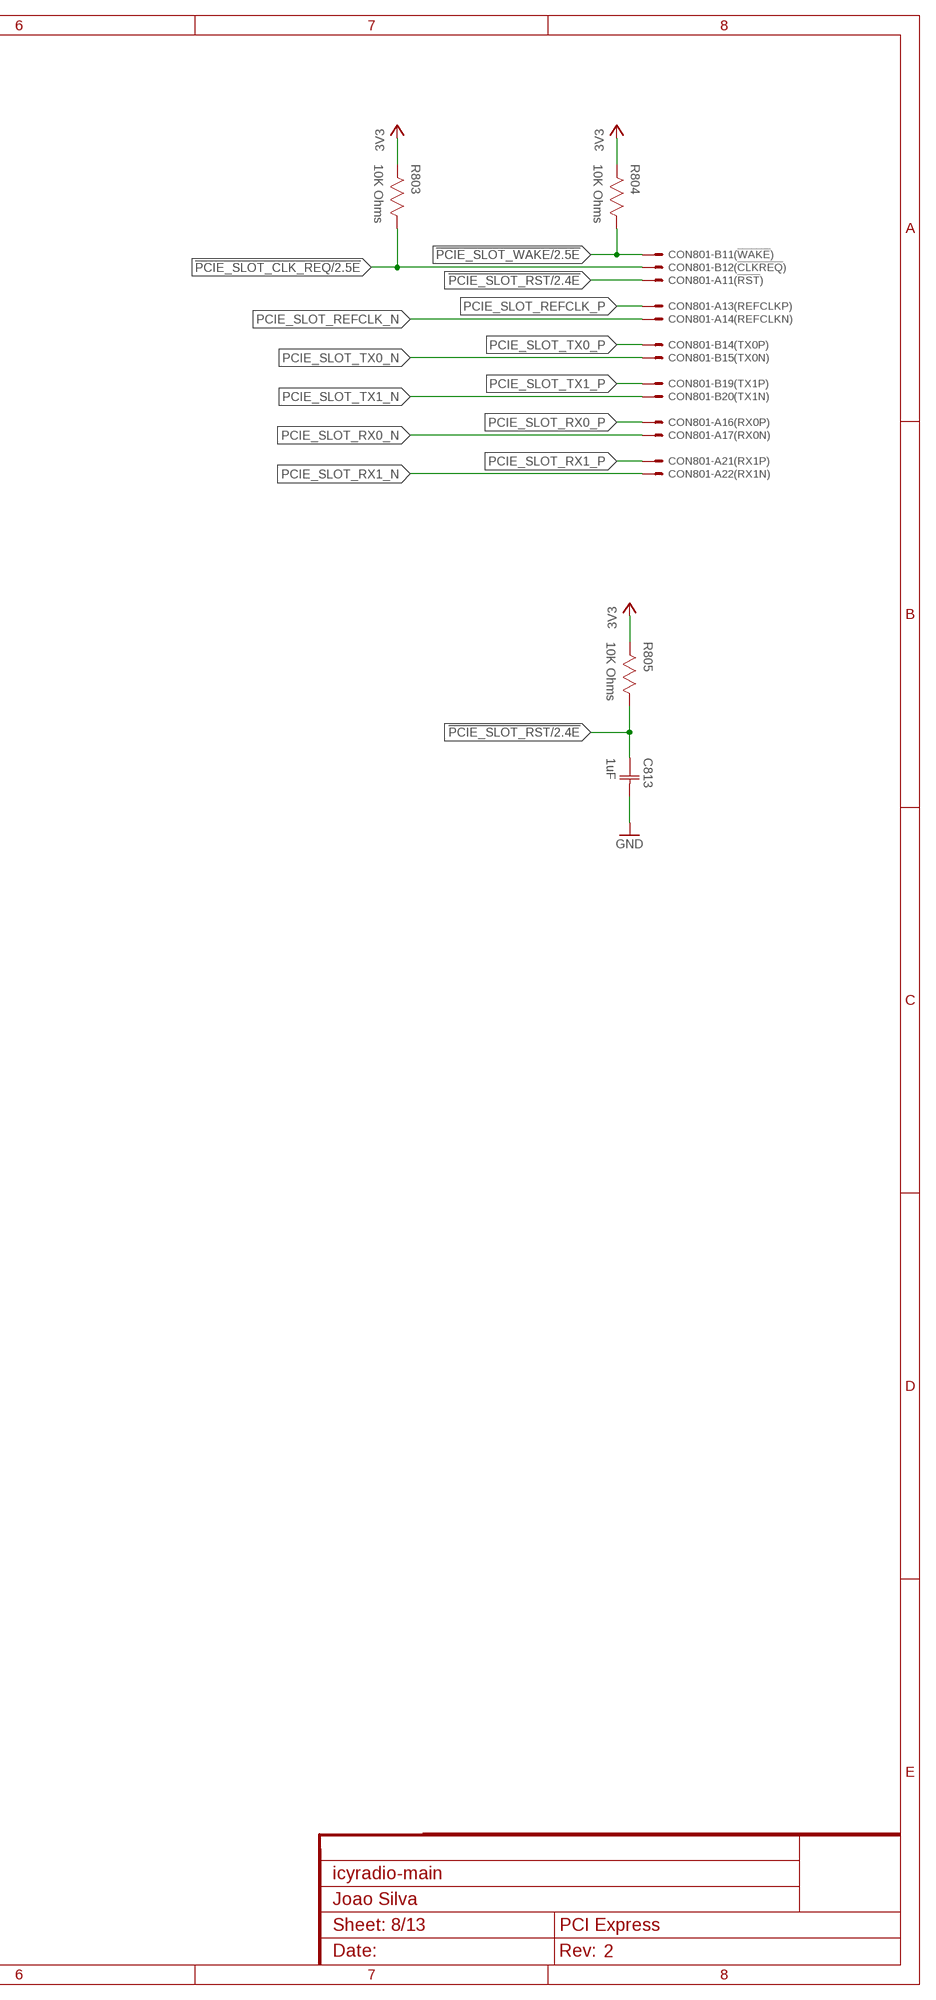
[diagram p15: schematic, sheet 8, part 2 of 2]
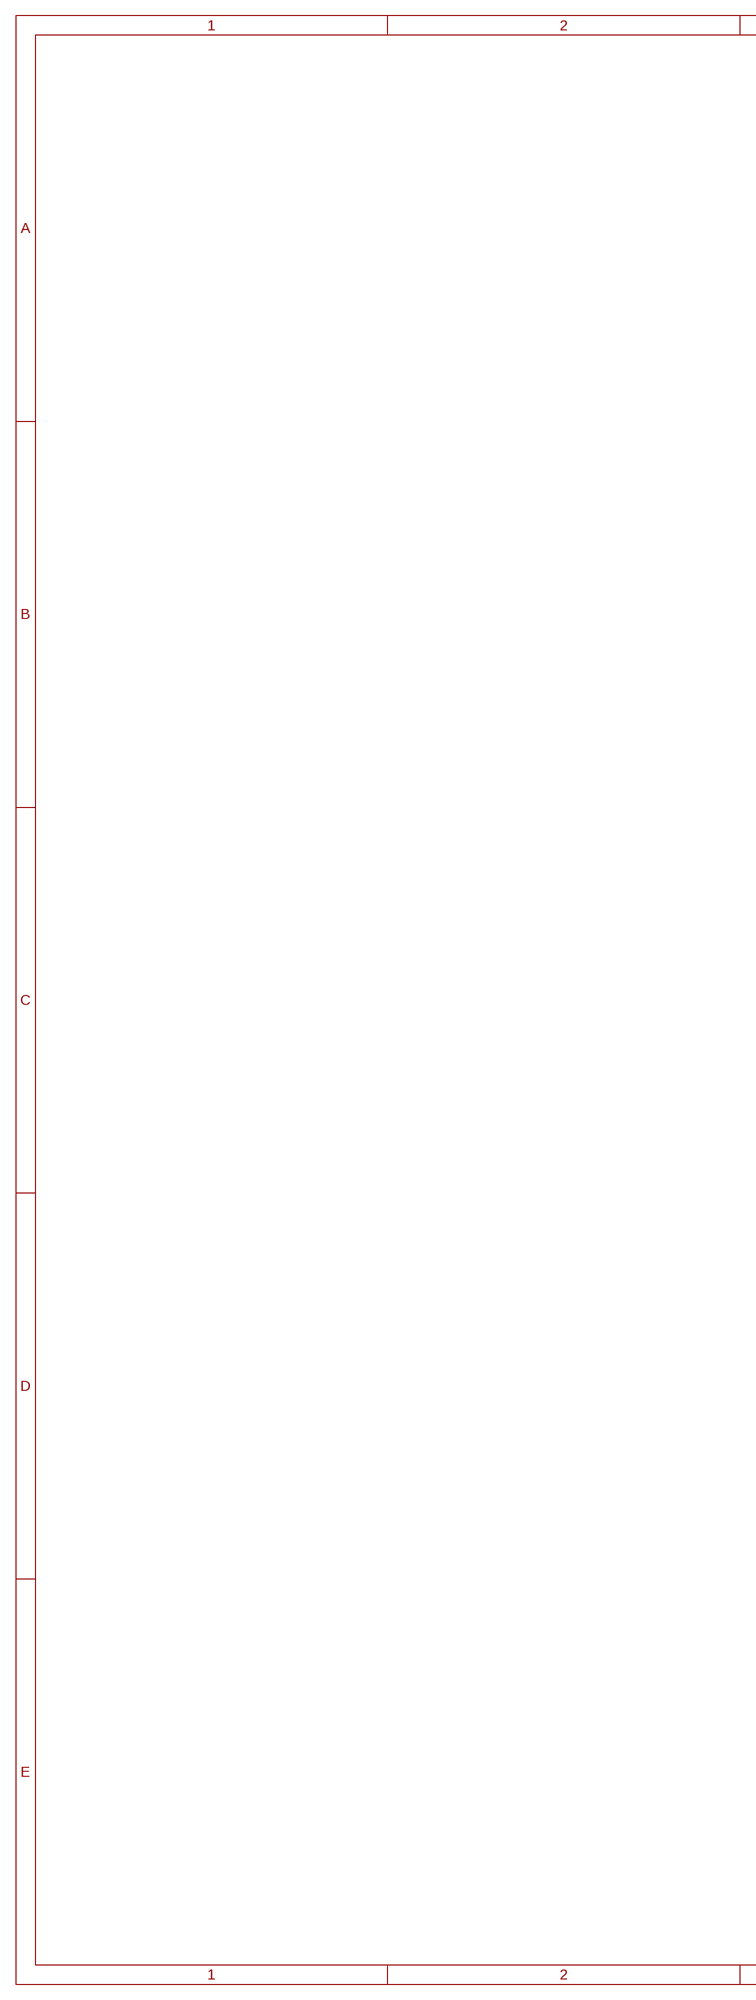
[diagram p16: schematic, sheet 9, part 1 of 2]
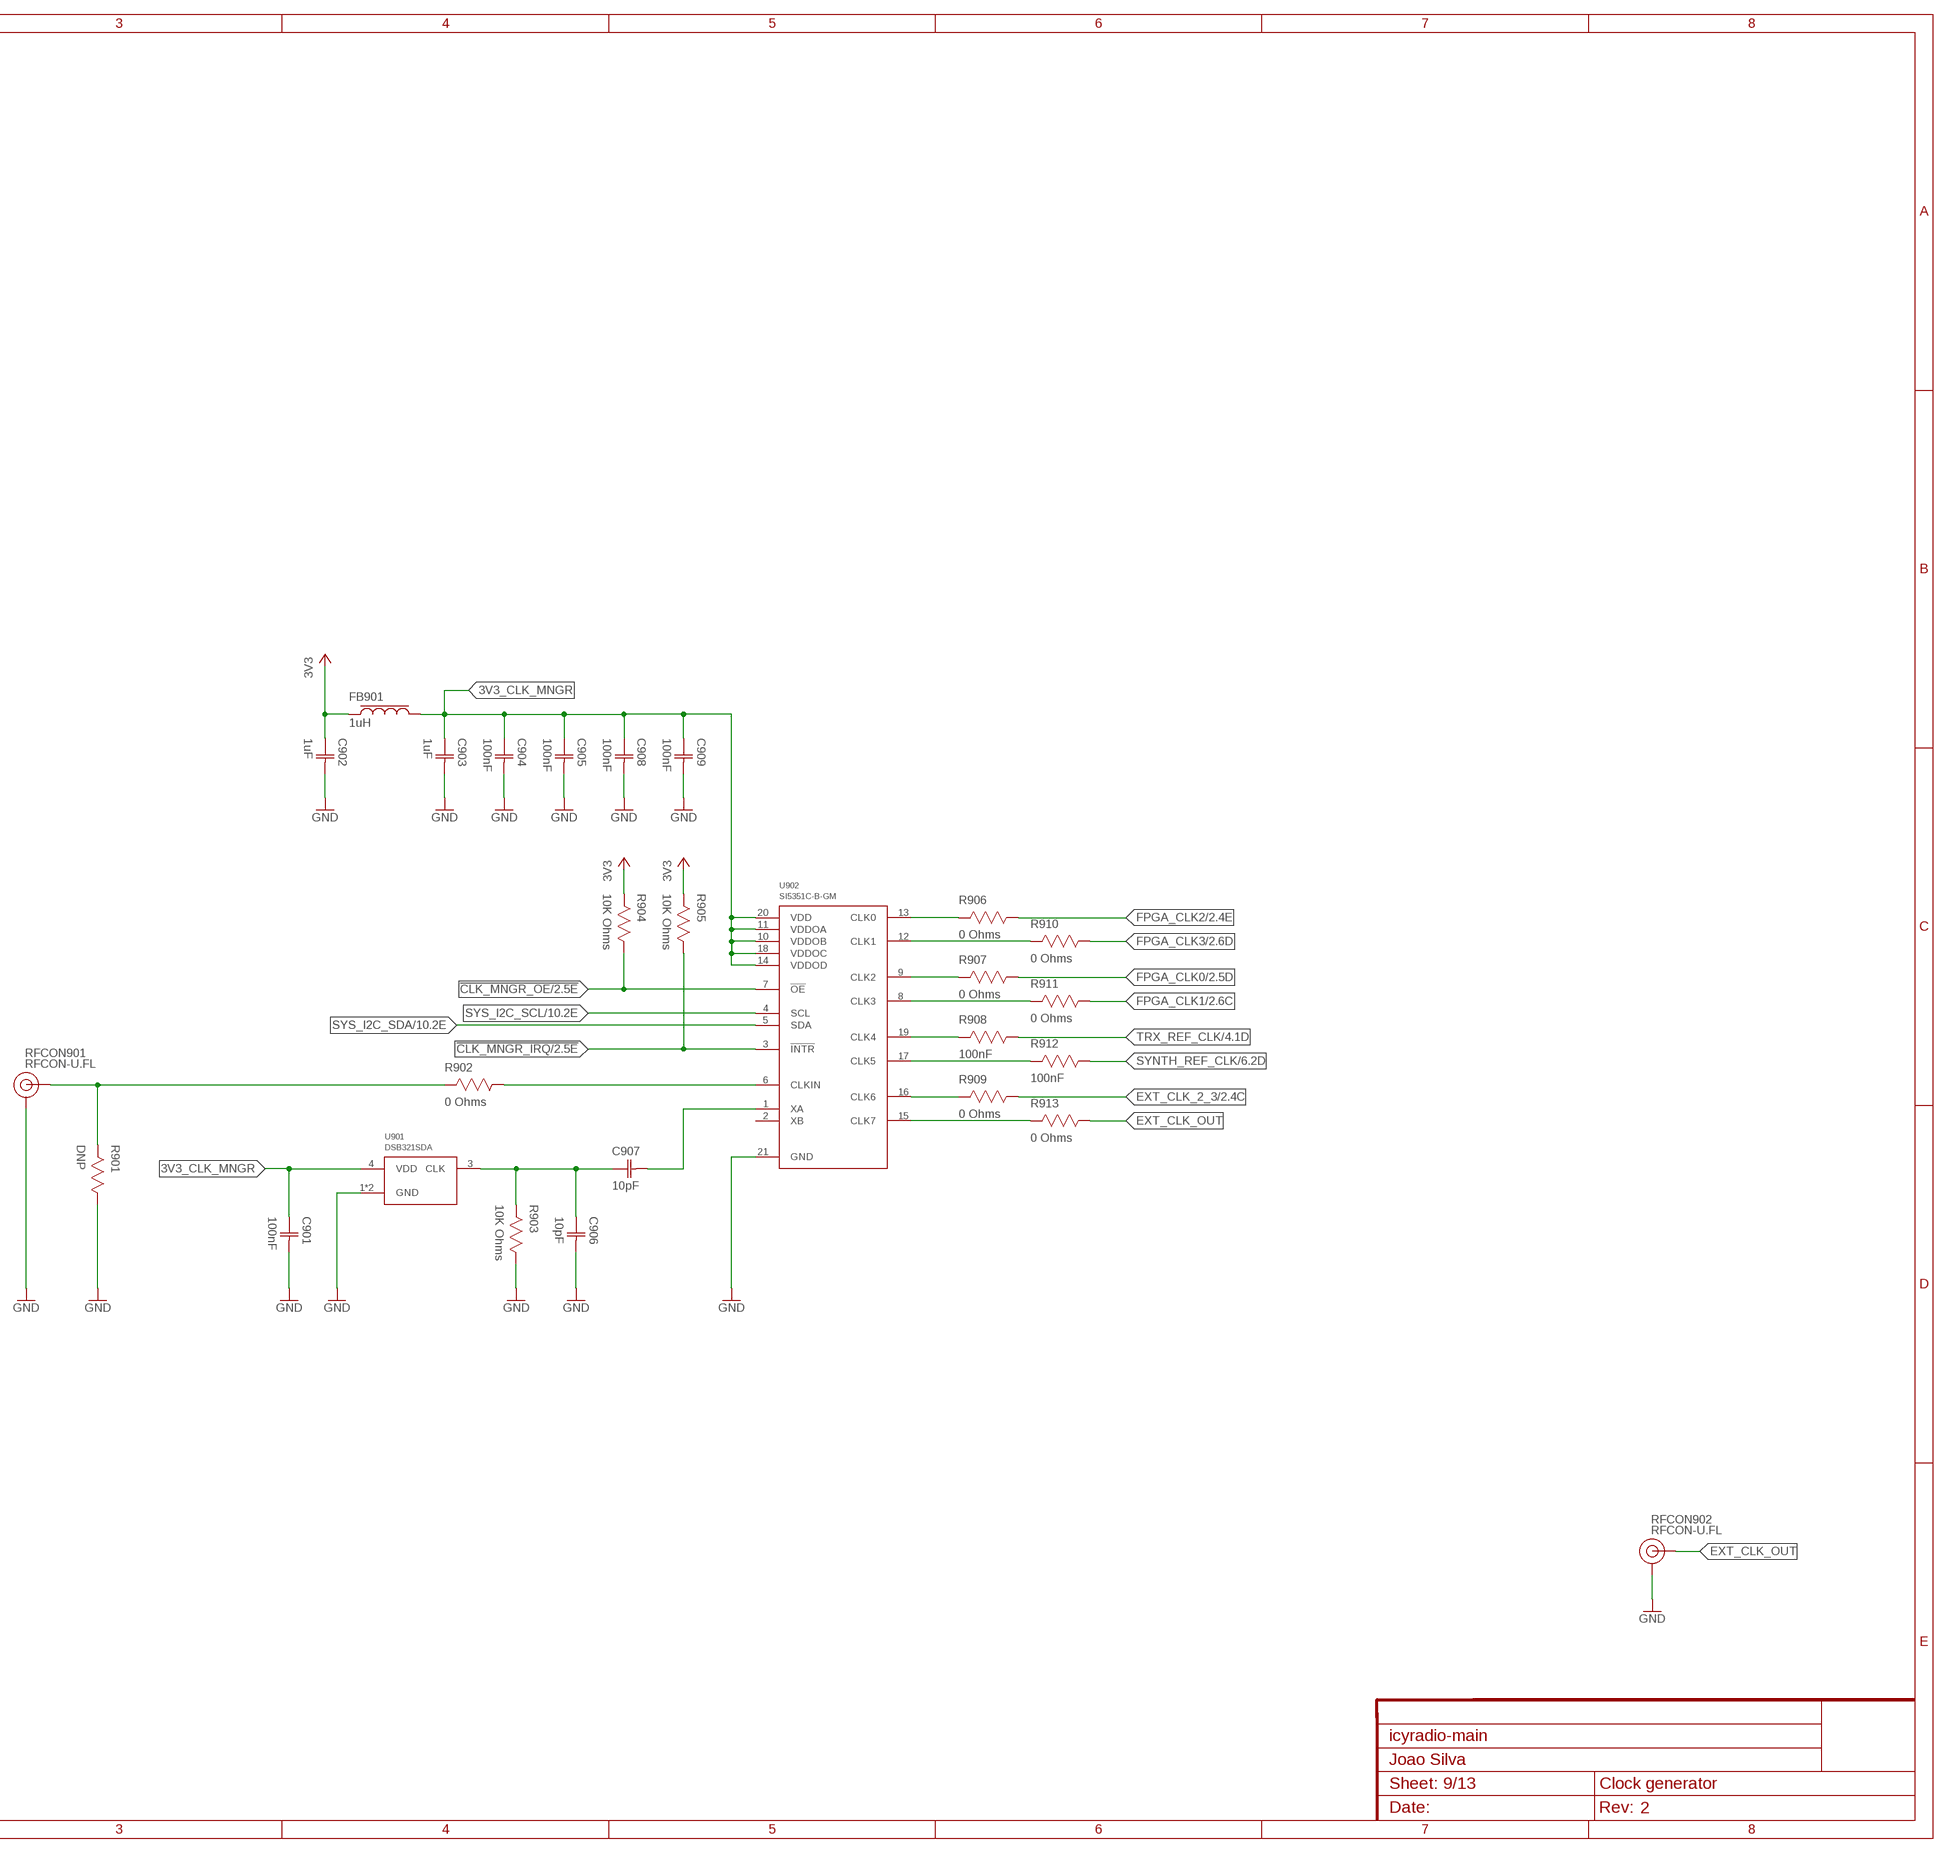
[diagram p17: schematic, sheet 9, part 2 of 2]
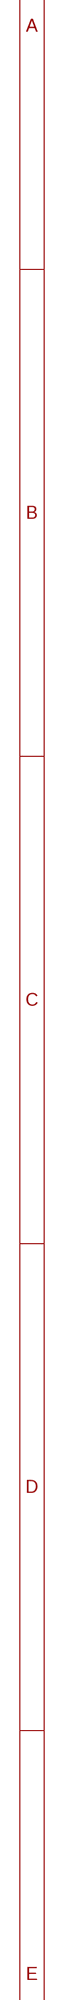
[diagram p18: schematic, sheet 10, part 1 of 2]
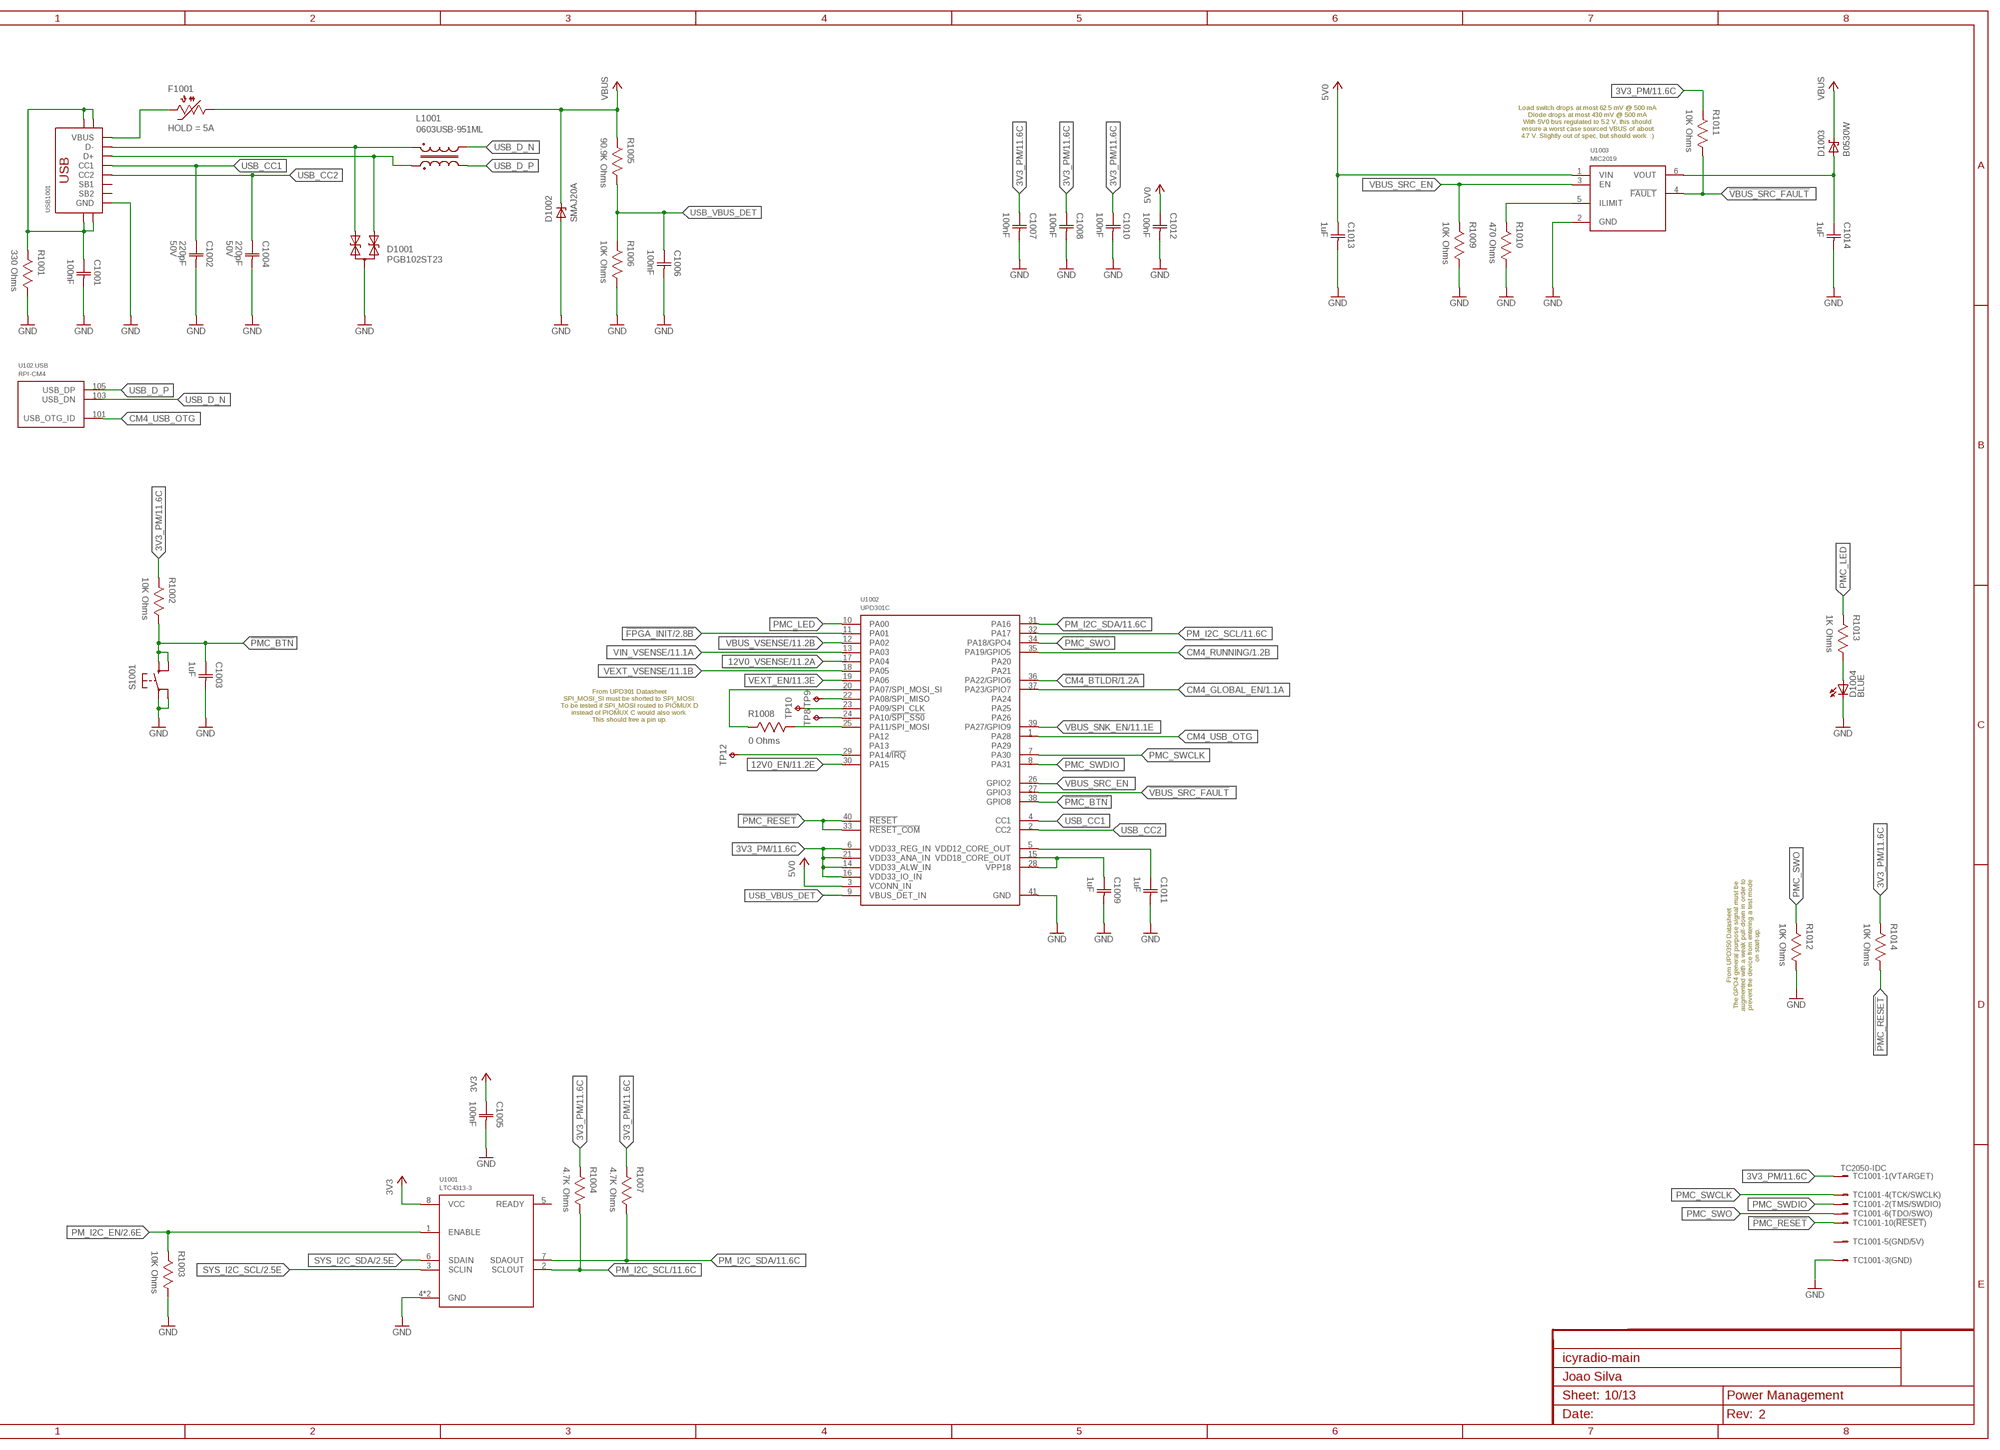
[diagram p19: schematic, sheet 10, part 2 of 2]
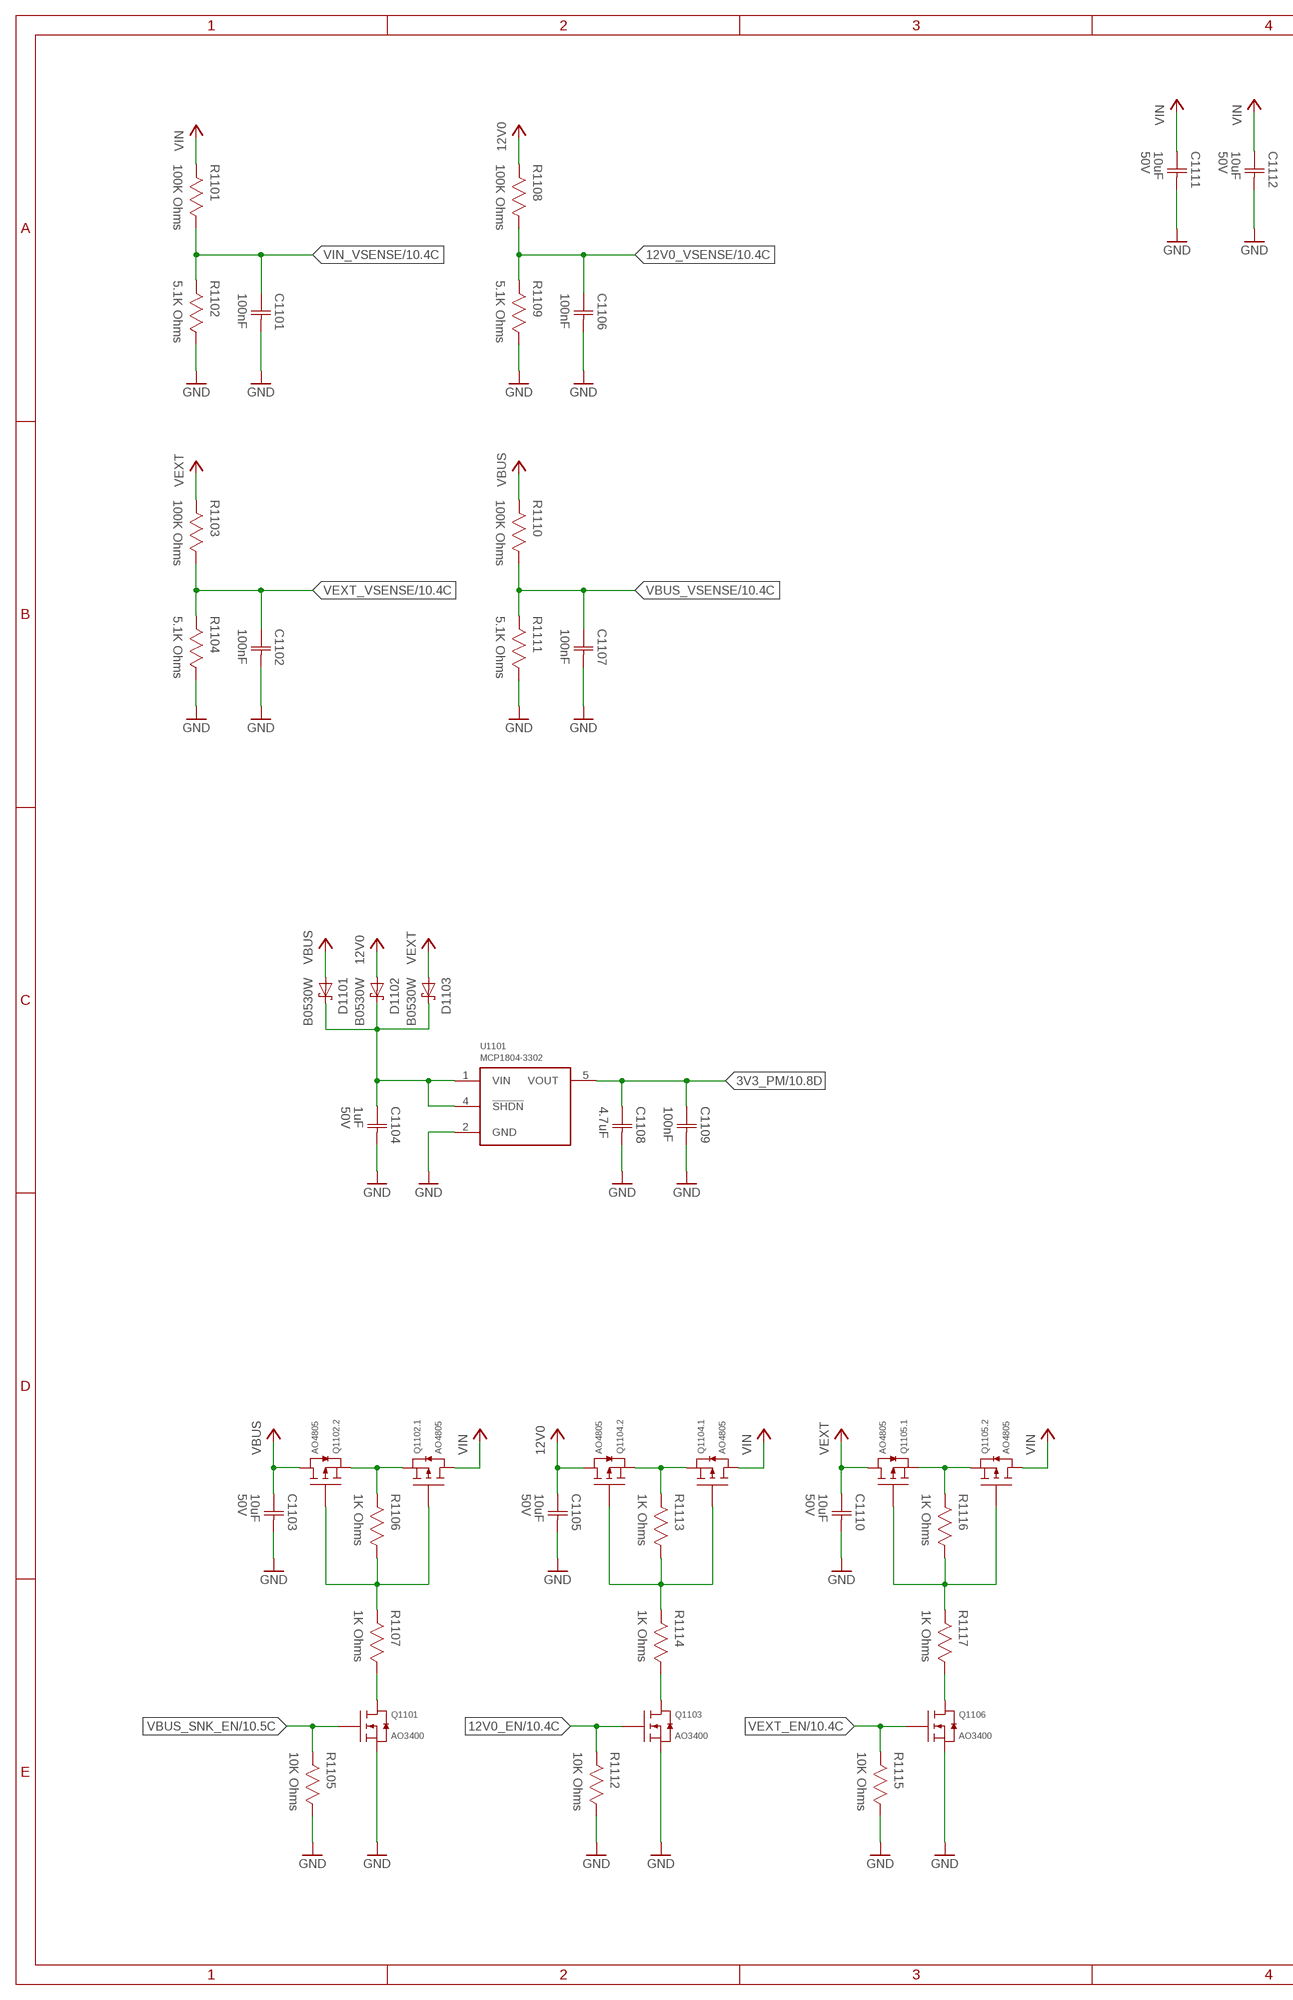
[diagram p20: schematic, sheet 11, part 1 of 2]
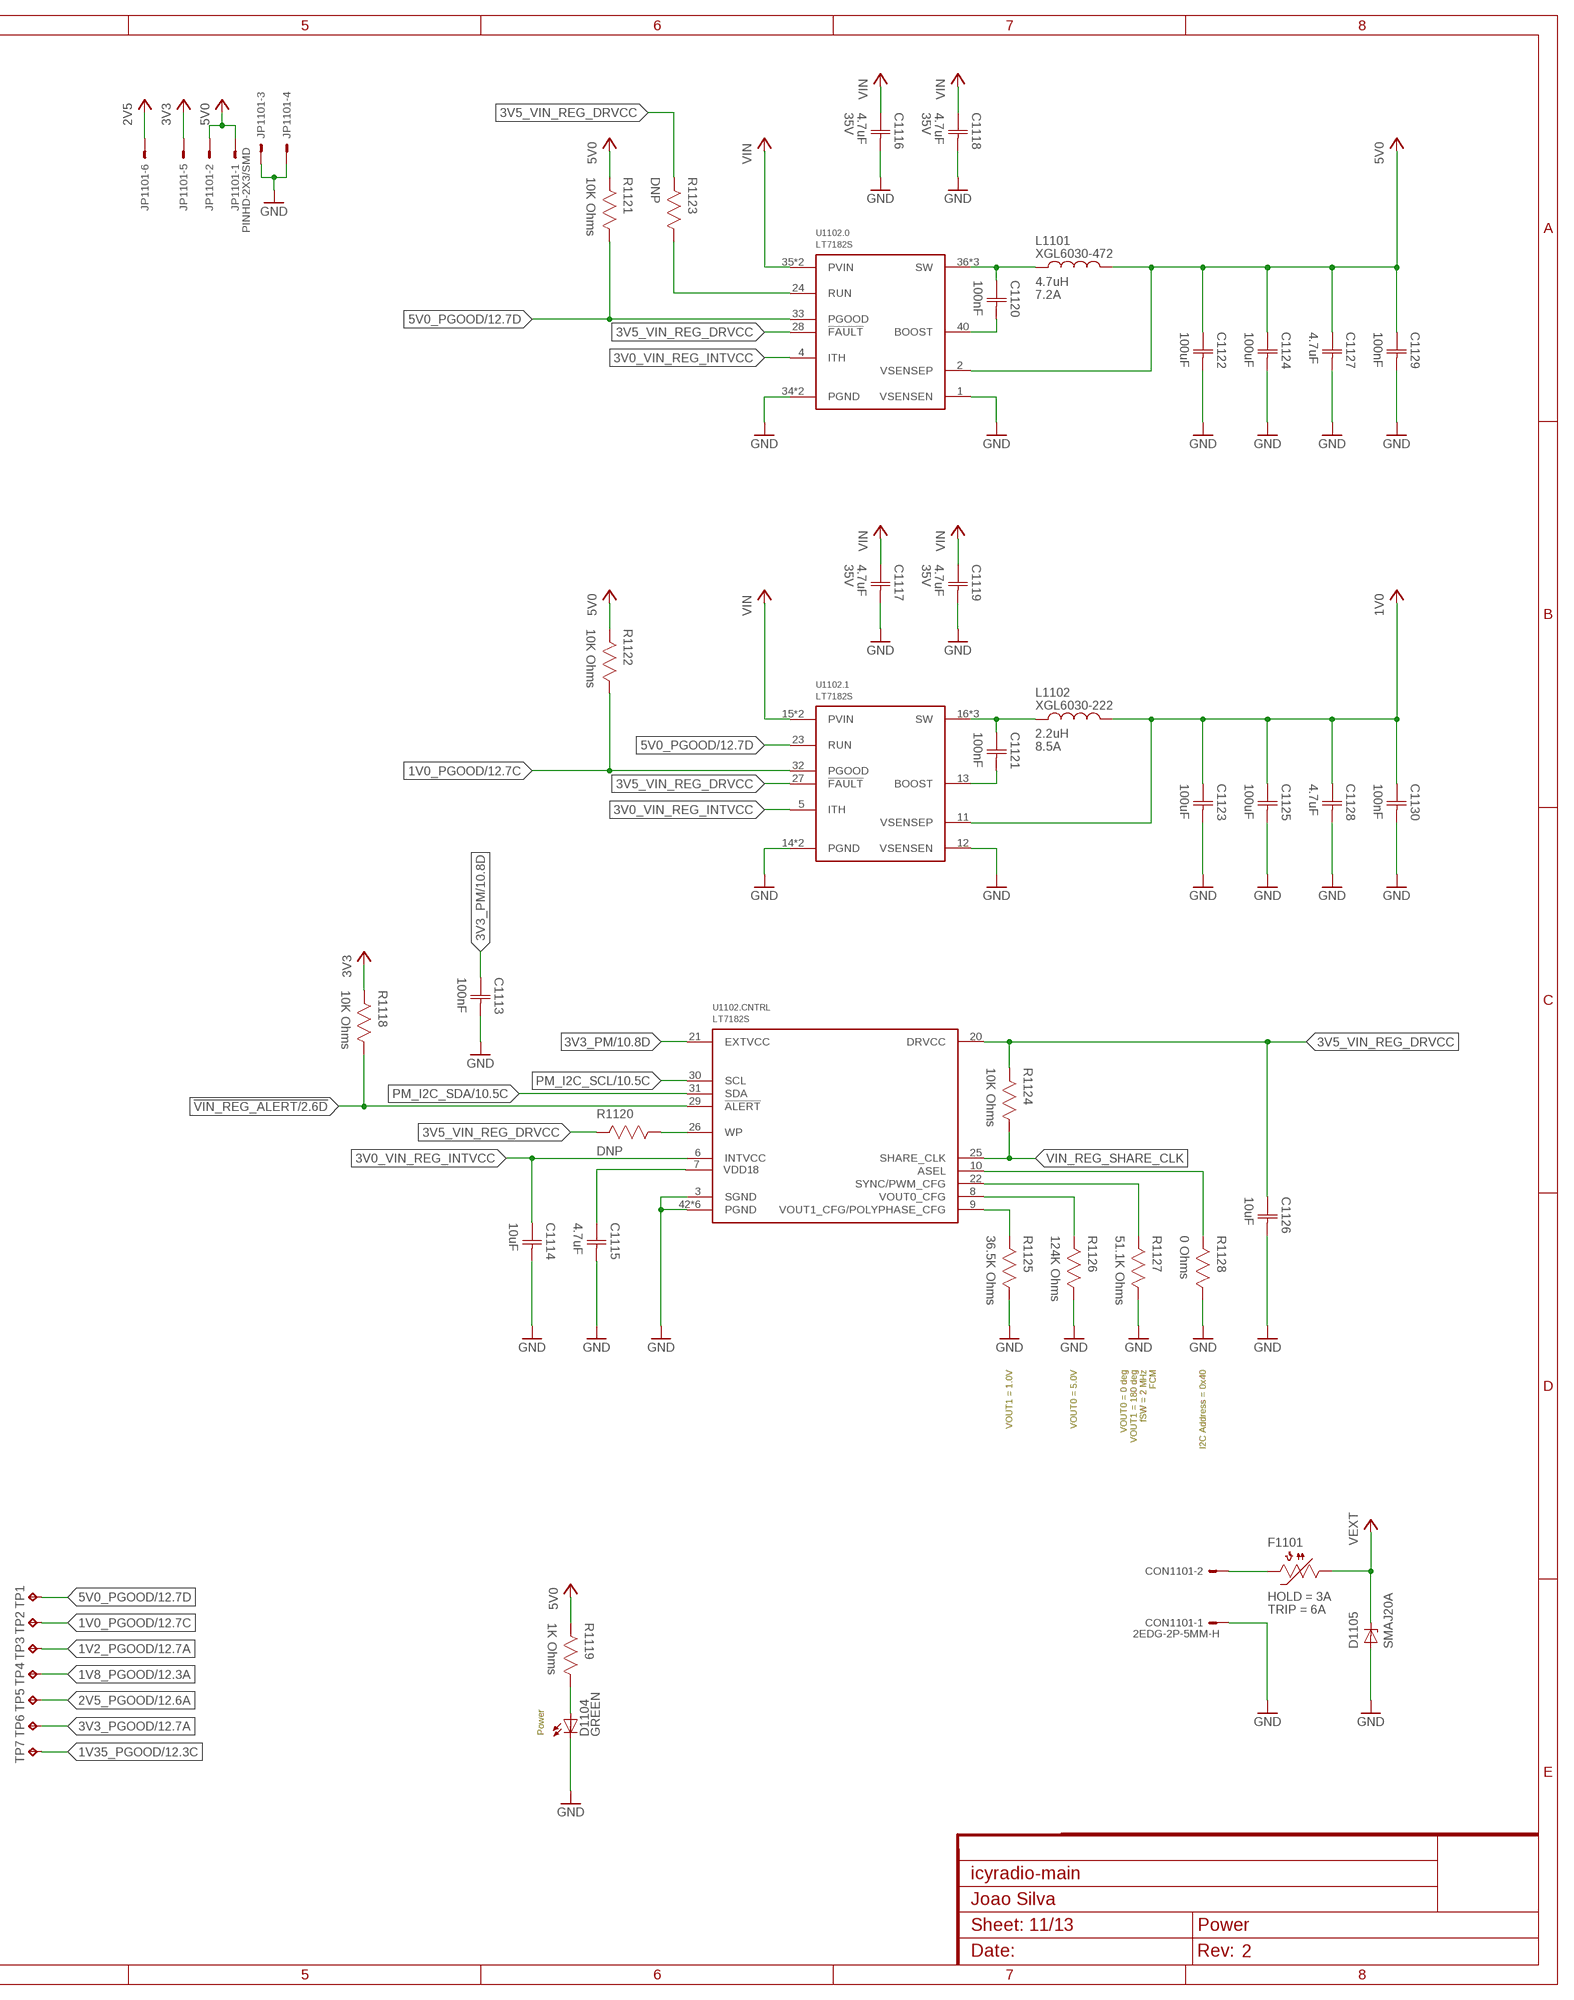
[diagram p21: schematic, sheet 11, part 2 of 2]
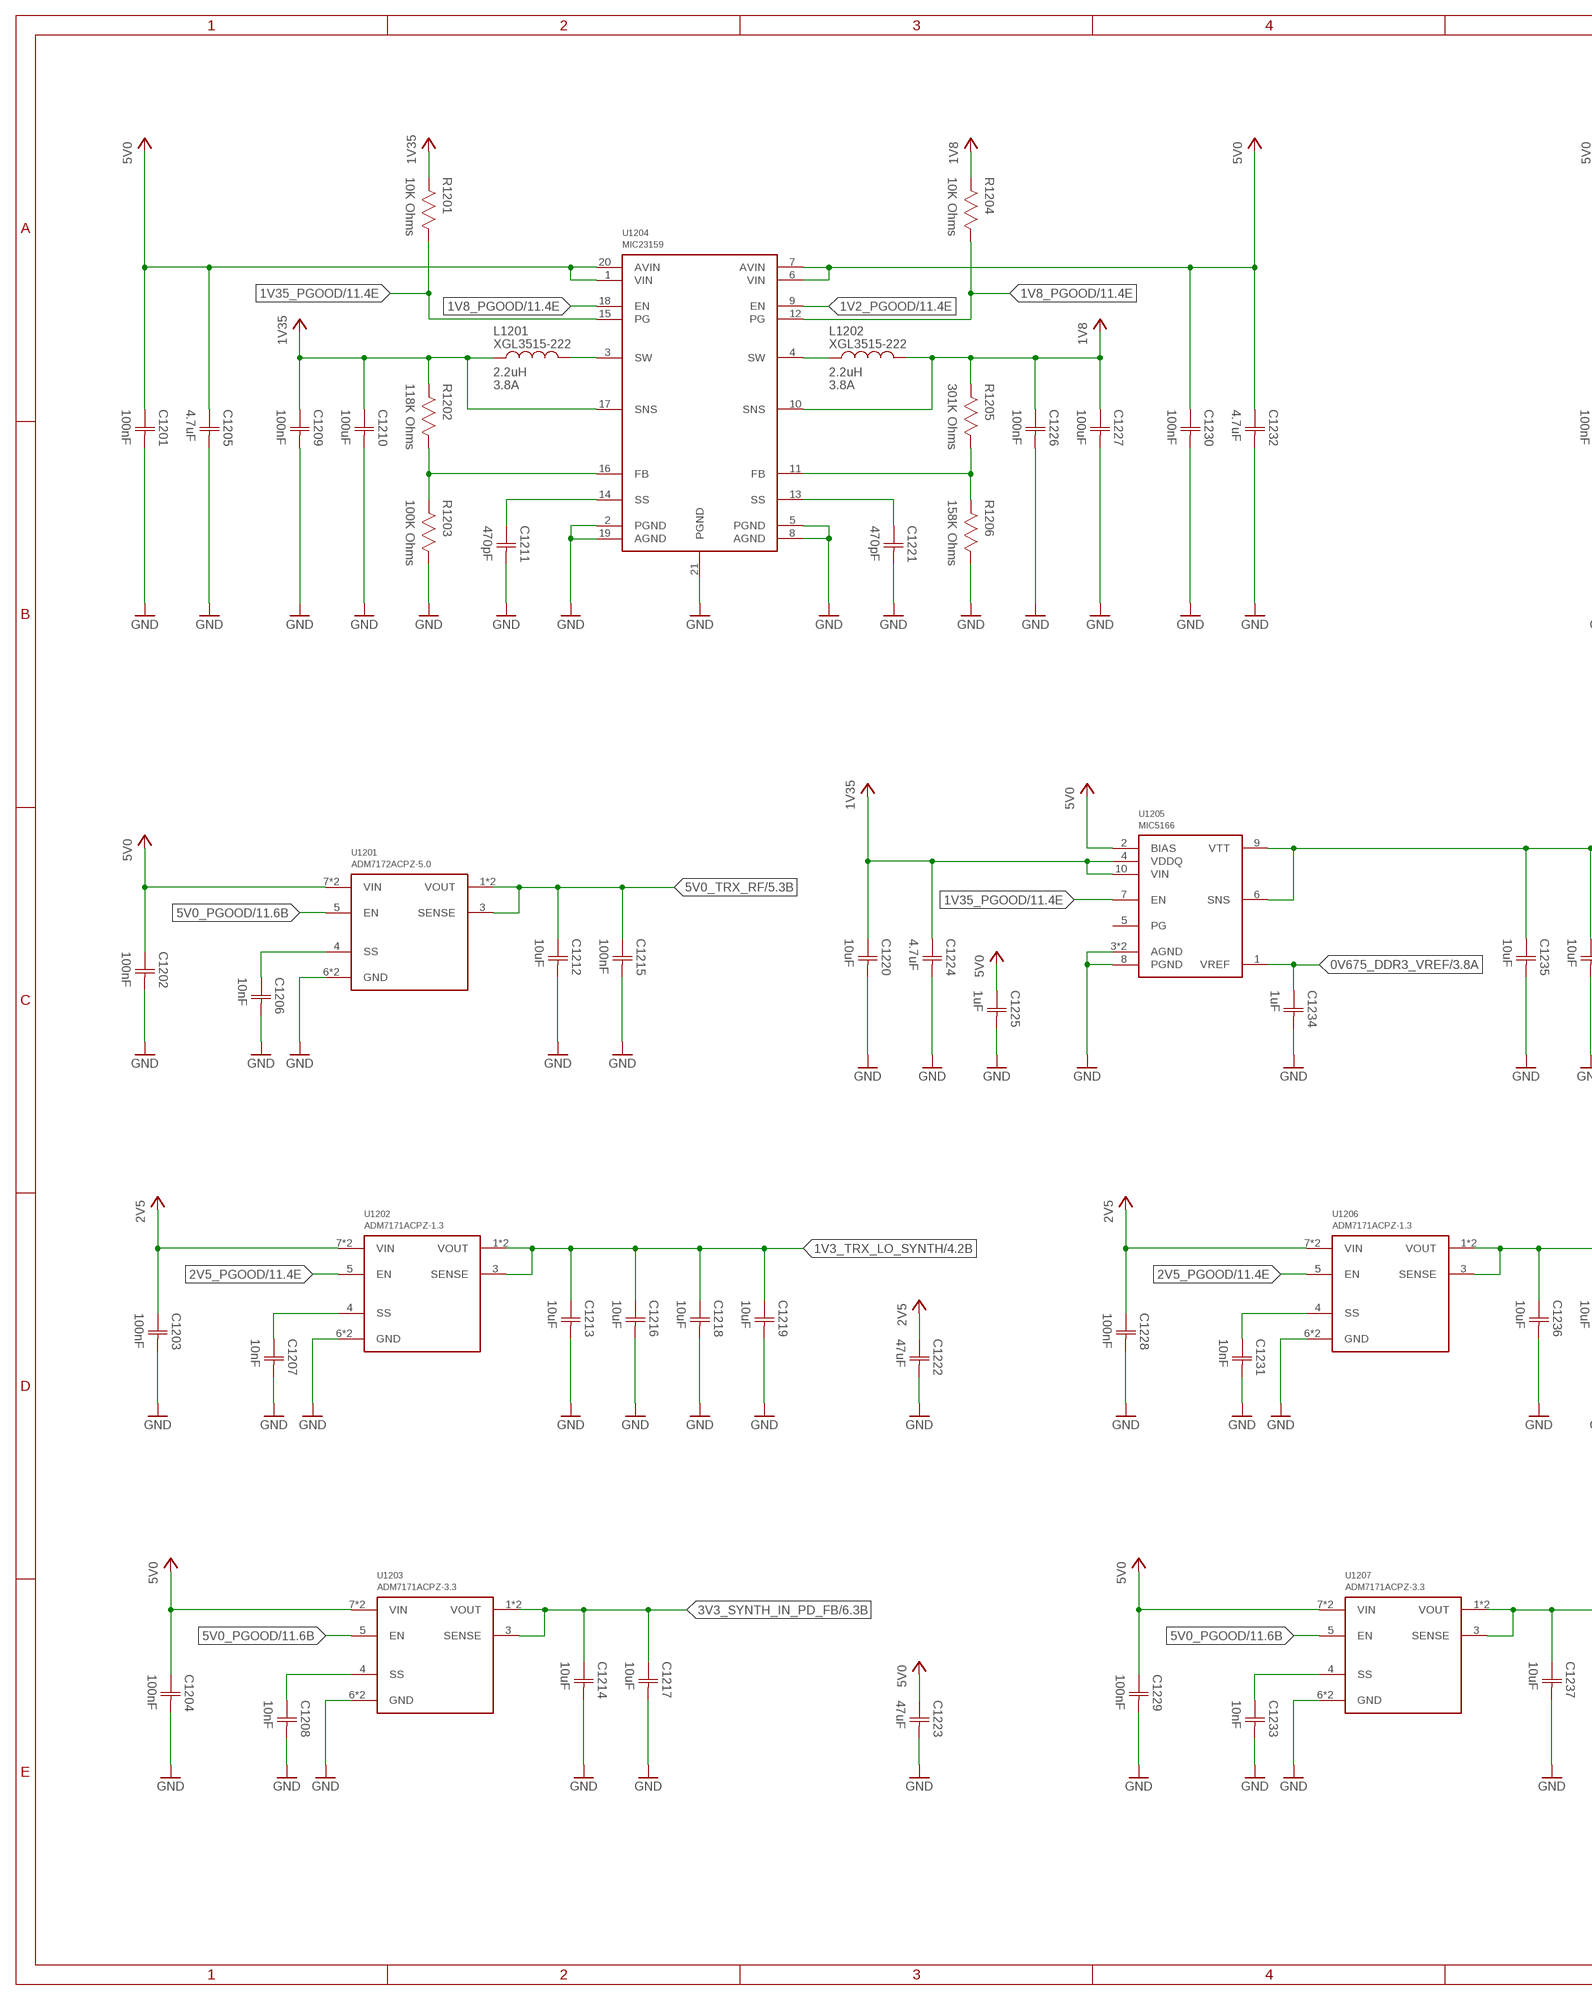
[diagram p22: schematic, sheet 12, part 1 of 2]
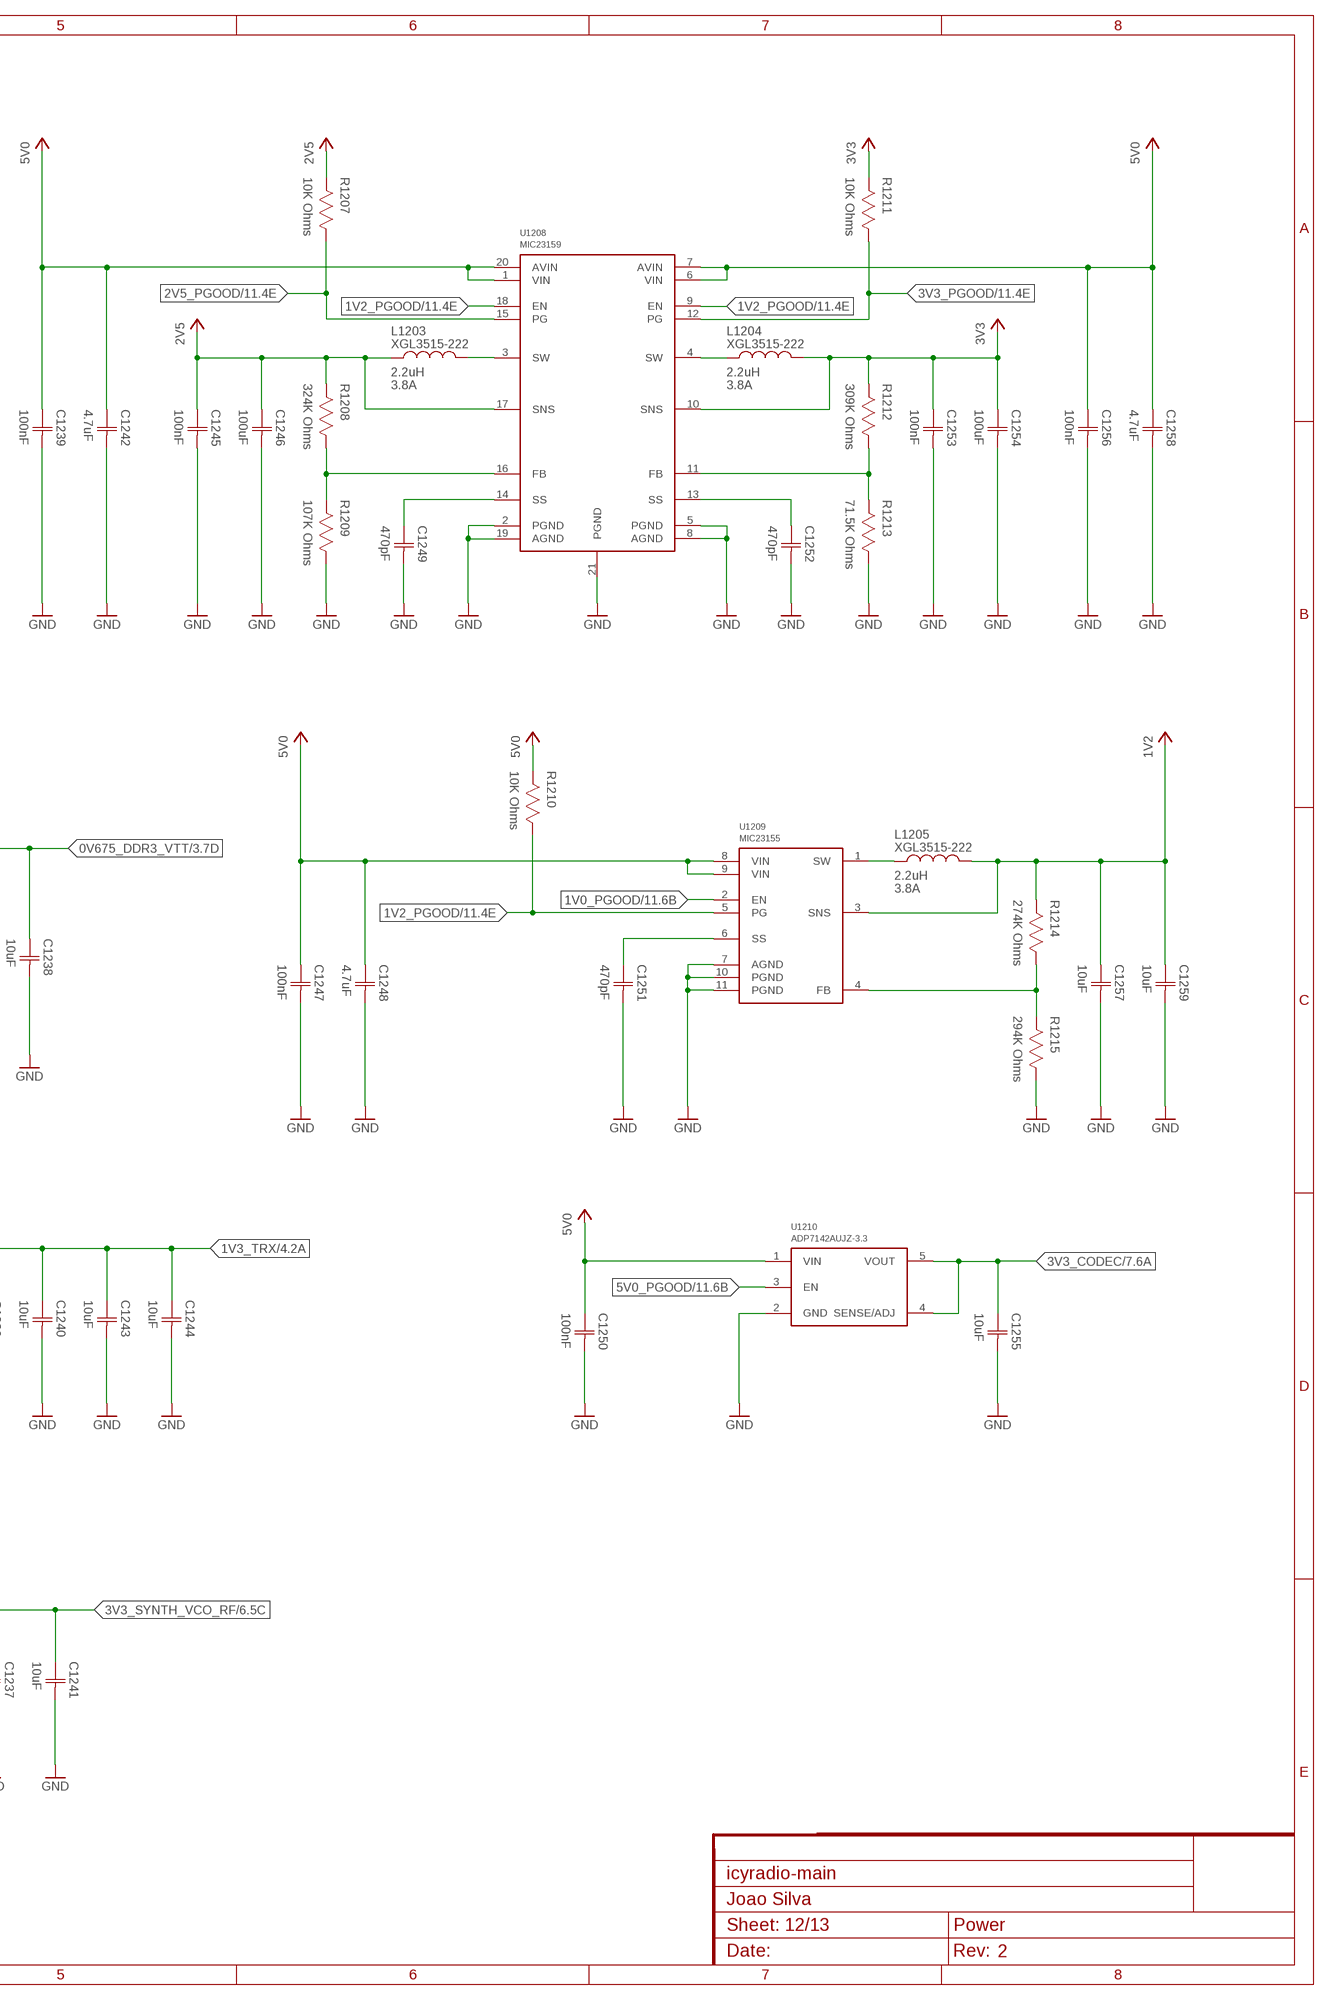
[diagram p23: schematic, sheet 12, part 2 of 2]
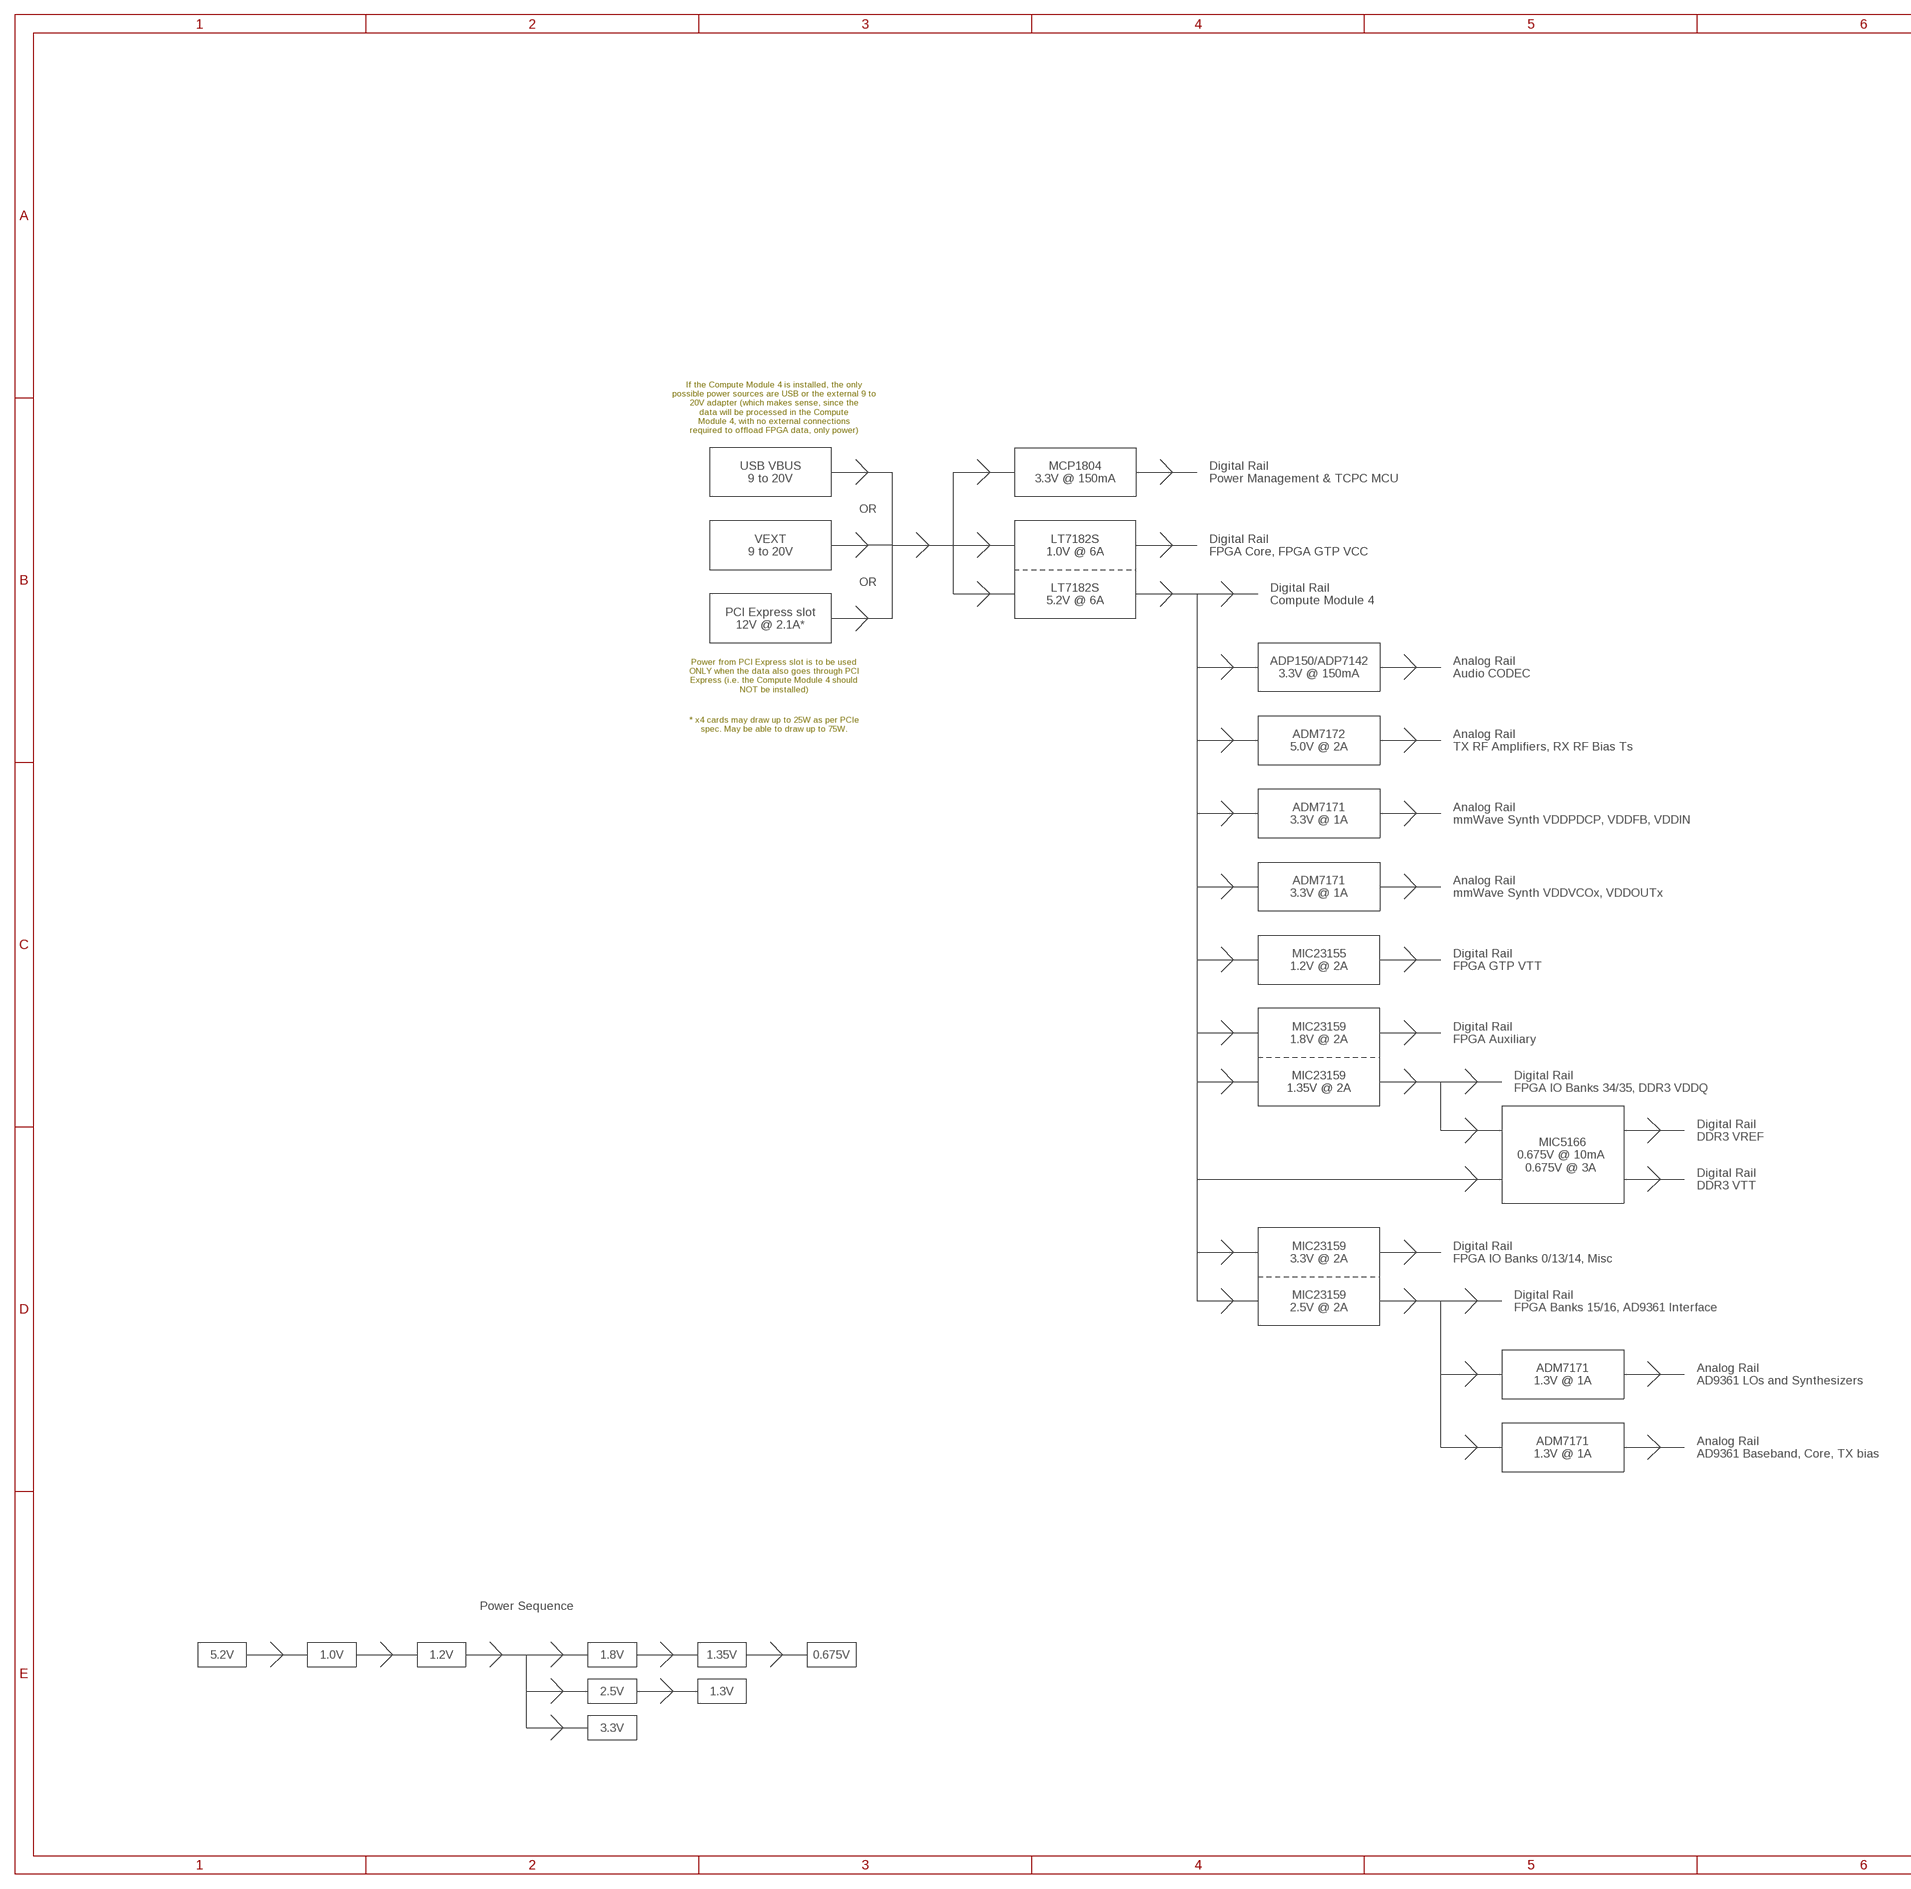
[diagram p24: schematic, sheet 13, part 1 of 2]
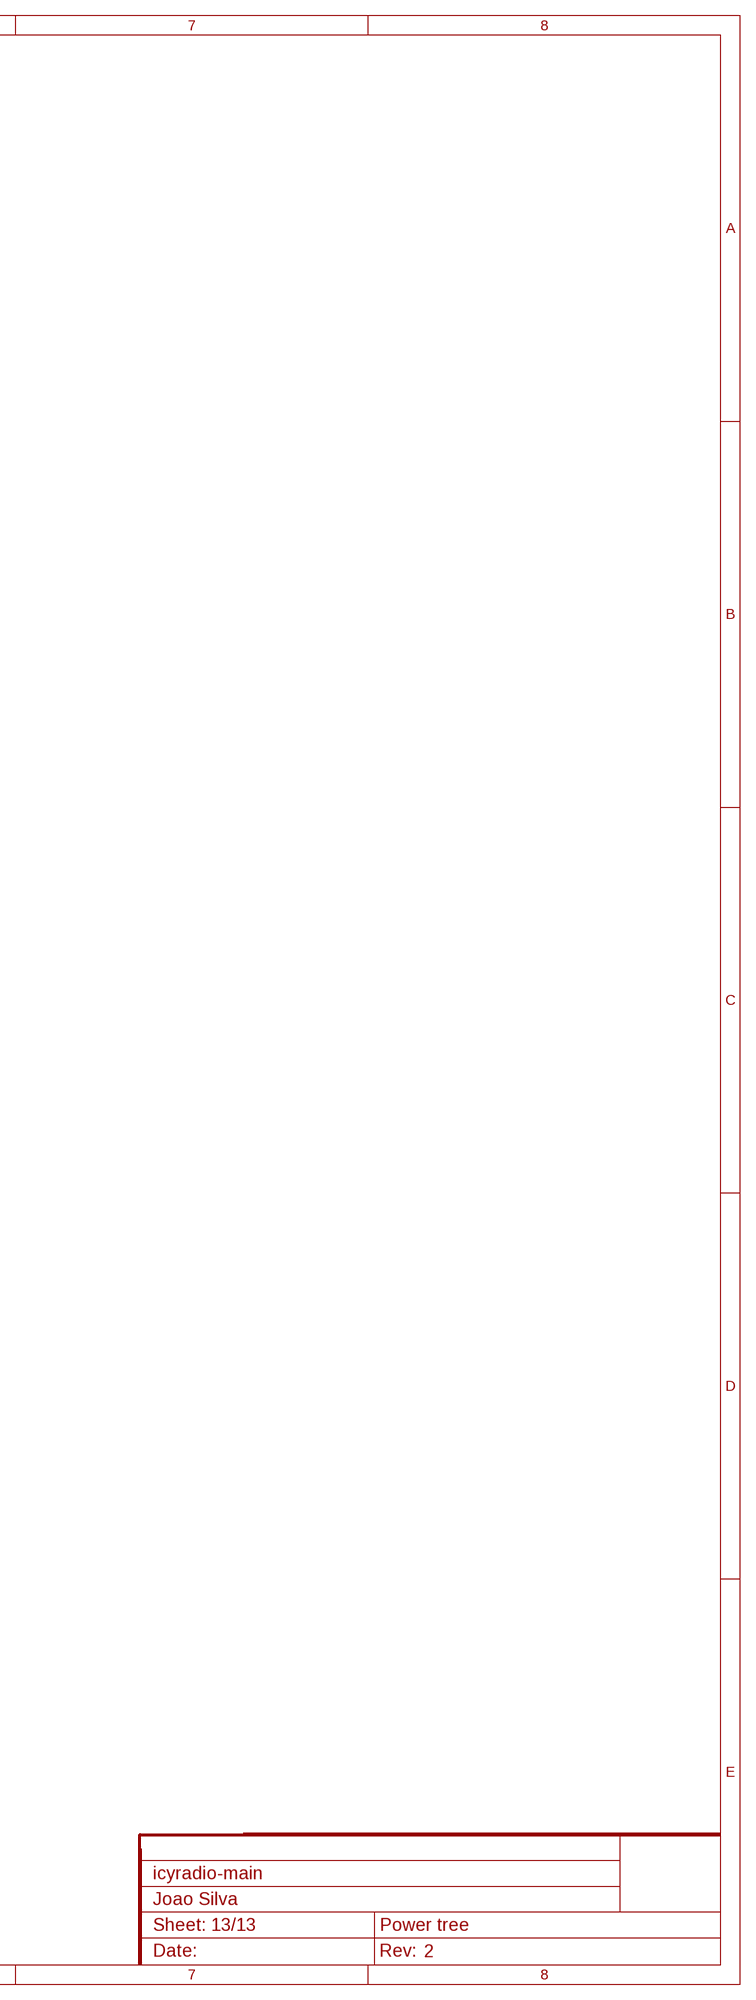
[diagram p25: schematic, sheet 13, part 2 of 2]

(export (version "E")
  (design (tool "Eeschema 10.0.6"))
  (components
    (comp (ref "C401")
      (value "100nF")
      (footprint "eagle-import:CAP0402")
      (libsource (lib "eagle-import") (part "CAPACITOR-0402"))
    )
    (comp (ref "C402")
      (value "DNP")
      (footprint "eagle-import:CAP0402")
      (libsource (lib "eagle-import") (part "CAPACITOR-0402"))
    )
    (comp (ref "C403")
      (value "10pF")
      (footprint "eagle-import:CAP0402")
      (libsource (lib "eagle-import") (part "CAPACITOR-0402"))
    )
    (comp (ref "C404")
      (value "1uF")
      (footprint "eagle-import:CAP0402")
      (libsource (lib "eagle-import") (part "CAPACITOR-0402"))
    )
    (comp (ref "C405")
      (value "1uF")
      (footprint "eagle-import:CAP0402")
      (libsource (lib "eagle-import") (part "CAPACITOR-0402"))
    )
    (comp (ref "C406")
      (value "10uF")
      (footprint "eagle-import:CAP0402")
      (libsource (lib "eagle-import") (part "CAPACITOR-0402"))
    )
    (comp (ref "C407")
      (value "10nF")
      (footprint "eagle-import:CAP0402")
      (libsource (lib "eagle-import") (part "CAPACITOR-0402"))
    )
    (comp (ref "C408")
      (value "10nF")
      (footprint "eagle-import:CAP0402")
      (libsource (lib "eagle-import") (part "CAPACITOR-0402"))
    )
    (comp (ref "C409")
      (value "1uF")
      (footprint "eagle-import:CAP0402")
      (libsource (lib "eagle-import") (part "CAPACITOR-0402"))
    )
    (comp (ref "C410")
      (value "1uF")
      (footprint "eagle-import:CAP0402")
      (libsource (lib "eagle-import") (part "CAPACITOR-0402"))
    )
    (comp (ref "C411")
      (value "1uF")
      (footprint "eagle-import:CAP0402")
      (libsource (lib "eagle-import") (part "CAPACITOR-0402"))
    )
    (comp (ref "C412")
      (value "10nF")
      (footprint "eagle-import:CAP0402")
      (libsource (lib "eagle-import") (part "CAPACITOR-0402"))
    )
    (comp (ref "C413")
      (value "10nF")
      (footprint "eagle-import:CAP0402")
      (libsource (lib "eagle-import") (part "CAPACITOR-0402"))
    )
    (comp (ref "C414")
      (value "10nF")
      (footprint "eagle-import:CAP0402")
      (libsource (lib "eagle-import") (part "CAPACITOR-0402"))
    )
    (comp (ref "C415")
      (value "10nF")
      (footprint "eagle-import:CAP0402")
      (libsource (lib "eagle-import") (part "CAPACITOR-0402"))
    )
    (comp (ref "C416")
      (value "1uF")
      (footprint "eagle-import:CAP0402")
      (libsource (lib "eagle-import") (part "CAPACITOR-0402"))
    )
    (comp (ref "C417")
      (value "1uF")
      (footprint "eagle-import:CAP0402")
      (libsource (lib "eagle-import") (part "CAPACITOR-0402"))
    )
    (comp (ref "C418")
      (value "1uF")
      (footprint "eagle-import:CAP0402")
      (libsource (lib "eagle-import") (part "CAPACITOR-0402"))
    )
    (comp (ref "C419")
      (value "10nF")
      (footprint "eagle-import:CAP0402")
      (libsource (lib "eagle-import") (part "CAPACITOR-0402"))
    )
    (comp (ref "C420")
      (value "10nF")
      (footprint "eagle-import:CAP0402")
      (libsource (lib "eagle-import") (part "CAPACITOR-0402"))
    )
    (comp (ref "C421")
      (value "1uF")
      (footprint "eagle-import:CAP0402")
      (libsource (lib "eagle-import") (part "CAPACITOR-0402"))
    )
    (comp (ref "C422")
      (value "1nF")
      (footprint "eagle-import:CAP0402")
      (libsource (lib "eagle-import") (part "CAPACITOR-0402"))
    )
    (comp (ref "C423")
      (value "1uF")
      (footprint "eagle-import:CAP0402")
      (libsource (lib "eagle-import") (part "CAPACITOR-0402"))
    )
    (comp (ref "C424")
      (value "1nF")
      (footprint "eagle-import:CAP0402")
      (libsource (lib "eagle-import") (part "CAPACITOR-0402"))
    )
    (comp (ref "FB401")
      (value "1uH")
      (footprint "eagle-import:IND0603")
      (libsource (lib "eagle-import") (part "FERRITE-0603"))
    )
    (comp (ref "R401")
      (value "25.5 Ohms")
      (footprint "eagle-import:RES0402")
      (libsource (lib "eagle-import") (part "RESISTOR-0402"))
    )
    (comp (ref "R402")
      (value "25.5 Ohms")
      (footprint "eagle-import:RES0402")
      (libsource (lib "eagle-import") (part "RESISTOR-0402"))
    )
    (comp (ref "R403")
      (value "14.3K Ohms")
      (footprint "eagle-import:RES0402")
      (libsource (lib "eagle-import") (part "RESISTOR-0402"))
    )
    (comp (ref "R404")
      (value "1 Ohms")
      (footprint "eagle-import:RES0402")
      (libsource (lib "eagle-import") (part "RESISTOR-0402"))
    )
    (comp (ref "R405")
      (value "1 Ohms")
      (footprint "eagle-import:RES0402")
      (libsource (lib "eagle-import") (part "RESISTOR-0402"))
    )
    (comp (ref "SHIELD401")
      (value "SHIELD-TE-2118732")
      (footprint "eagle-import:2118732")
      (libsource (lib "eagle-import") (part "SHIELD-TE-2118732"))
    )
    (comp (ref "U401")
      (value "AD9361")
      (footprint "eagle-import:BGA144")
      (libsource (lib "eagle-import") (part "AD9361"))
    )
    (comp (ref "C1001")
      (value "100nF")
      (footprint "eagle-import:CAP0402")
      (libsource (lib "eagle-import") (part "CAPACITOR-0402"))
    )
    (comp (ref "C1002")
      (value "220pF")
      (footprint "eagle-import:CAP0402")
      (fields (field (name "VOLTAGE") "50V"))
      (libsource (lib "eagle-import") (part "CAPACITOR-0402"))
    )
    (comp (ref "C1003")
      (value "1uF")
      (footprint "eagle-import:CAP0402")
      (libsource (lib "eagle-import") (part "CAPACITOR-0402"))
    )
    (comp (ref "C1004")
      (value "220pF")
      (footprint "eagle-import:CAP0402")
      (fields (field (name "VOLTAGE") "50V"))
      (libsource (lib "eagle-import") (part "CAPACITOR-0402"))
    )
    (comp (ref "C1005")
      (value "100nF")
      (footprint "eagle-import:CAP0402")
      (libsource (lib "eagle-import") (part "CAPACITOR-0402"))
    )
    (comp (ref "C1006")
      (value "100nF")
      (footprint "eagle-import:CAP0402")
      (libsource (lib "eagle-import") (part "CAPACITOR-0402"))
    )
    (comp (ref "C1007")
      (value "100nF")
      (footprint "eagle-import:CAP0402")
      (libsource (lib "eagle-import") (part "CAPACITOR-0402"))
    )
    (comp (ref "C1008")
      (value "100nF")
      (footprint "eagle-import:CAP0402")
      (libsource (lib "eagle-import") (part "CAPACITOR-0402"))
    )
    (comp (ref "C1009")
      (value "1uF")
      (footprint "eagle-import:CAP0402")
      (libsource (lib "eagle-import") (part "CAPACITOR-0402"))
    )
    (comp (ref "C1010")
      (value "100nF")
      (footprint "eagle-import:CAP0402")
      (libsource (lib "eagle-import") (part "CAPACITOR-0402"))
    )
    (comp (ref "C1011")
      (value "1uF")
      (footprint "eagle-import:CAP0402")
      (libsource (lib "eagle-import") (part "CAPACITOR-0402"))
    )
    (comp (ref "C1012")
      (value "100nF")
      (footprint "eagle-import:CAP0402")
      (libsource (lib "eagle-import") (part "CAPACITOR-0402"))
    )
    (comp (ref "C1013")
      (value "1uF")
      (footprint "eagle-import:CAP0402")
      (libsource (lib "eagle-import") (part "CAPACITOR-0402"))
    )
    (comp (ref "C1014")
      (value "1uF")
      (footprint "eagle-import:CAP0402")
      (libsource (lib "eagle-import") (part "CAPACITOR-0402"))
    )
    (comp (ref "D1001")
      (value "PGB102ST23")
      (footprint "eagle-import:SOT23")
      (libsource (lib "eagle-import") (part "PGB102ST23"))
    )
    (comp (ref "D1002")
      (value "SMAJ20A")
      (footprint "eagle-import:DO214AC")
      (fields (field (name "MF") "Littelfuse"))
      (libsource (lib "eagle-import") (part "SMAJA20"))
    )
    (comp (ref "D1003")
      (value "B0530W")
      (footprint "eagle-import:SOD-123")
      (libsource (lib "eagle-import") (part "B0530W"))
    )
    (comp (ref "D1004")
      (value "LED0603")
      (footprint "eagle-import:0603")
      (fields (field (name "COLOR") "BLUE"))
      (libsource (lib "eagle-import") (part "LED0603"))
    )
    (comp (ref "F1001")
      (value "PTC1206")
      (footprint "eagle-import:1206")
      (fields (field (name "HOLD") "5A") (field (name "TRIP") "6A"))
      (libsource (lib "eagle-import") (part "PTC Fuses_PTC1206"))
    )
    (comp (ref "L1001")
      (value "0603USB-951ML")
      (footprint "eagle-import:0603USB")
      (libsource (lib "eagle-import") (part "0603USB-951ML"))
    )
    (comp (ref "R1001")
      (value "330 Ohms")
      (footprint "eagle-import:RES0402")
      (libsource (lib "eagle-import") (part "RESISTOR-0402"))
    )
    (comp (ref "R1002")
      (value "10K Ohms")
      (footprint "eagle-import:RES0402")
      (libsource (lib "eagle-import") (part "RESISTOR-0402"))
    )
    (comp (ref "R1003")
      (value "10K Ohms")
      (footprint "eagle-import:RES0402")
      (libsource (lib "eagle-import") (part "RESISTOR-0402"))
    )
    (comp (ref "R1004")
      (value "4.7K Ohms")
      (footprint "eagle-import:RES0402")
      (libsource (lib "eagle-import") (part "RESISTOR-0402"))
    )
    (comp (ref "R1005")
      (value "90.9K Ohms")
      (footprint "eagle-import:RES0402")
      (libsource (lib "eagle-import") (part "RESISTOR-0402"))
    )
    (comp (ref "R1006")
      (value "10K Ohms")
      (footprint "eagle-import:RES0402")
      (libsource (lib "eagle-import") (part "RESISTOR-0402"))
    )
    (comp (ref "R1007")
      (value "4.7K Ohms")
      (footprint "eagle-import:RES0402")
      (libsource (lib "eagle-import") (part "RESISTOR-0402"))
    )
    (comp (ref "R1008")
      (value "0 Ohms")
      (footprint "eagle-import:RES0402")
      (libsource (lib "eagle-import") (part "RESISTOR-0402"))
    )
    (comp (ref "R1009")
      (value "10K Ohms")
      (footprint "eagle-import:RES0402")
      (libsource (lib "eagle-import") (part "RESISTOR-0402"))
    )
    (comp (ref "R1010")
      (value "470 Ohms")
      (footprint "eagle-import:RES0402")
      (libsource (lib "eagle-import") (part "RESISTOR-0402"))
    )
    (comp (ref "R1011")
      (value "10K Ohms")
      (footprint "eagle-import:RES0402")
      (libsource (lib "eagle-import") (part "RESISTOR-0402"))
    )
    (comp (ref "R1012")
      (value "10K Ohms")
      (footprint "eagle-import:RES0402")
      (libsource (lib "eagle-import") (part "RESISTOR-0402"))
    )
    (comp (ref "R1013")
      (value "1K Ohms")
      (footprint "eagle-import:RES0402")
      (libsource (lib "eagle-import") (part "RESISTOR-0402"))
    )
    (comp (ref "R1014")
      (value "10K Ohms")
      (footprint "eagle-import:RES0402")
      (libsource (lib "eagle-import") (part "RESISTOR-0402"))
    )
    (comp (ref "S1001")
      (value "TAC_SWITCHSMD_4.5X4.5")
      (footprint "eagle-import:TAC_SW_SMD_4.5X4.5")
      (libsource (lib "eagle-import") (part "TAC_SWITCHSMD_4.5X4.5"))
    )
    (comp (ref "TC1001")
      (value "TC2050-IDC")
      (footprint "eagle-import:TC2050-IDC")
      (libsource (lib "eagle-import") (part "TC2050-IDC"))
    )
    (comp (ref "TP8")
      (value "TESTPOINT-0.7MM")
      (footprint "eagle-import:PAD0.7MM")
      (libsource (lib "eagle-import") (part "TESTPOINT-0.7MM"))
    )
    (comp (ref "TP9")
      (value "TESTPOINT-0.7MM")
      (footprint "eagle-import:PAD0.7MM")
      (libsource (lib "eagle-import") (part "TESTPOINT-0.7MM"))
    )
    (comp (ref "TP10")
      (value "TESTPOINT-0.7MM")
      (footprint "eagle-import:PAD0.7MM")
      (libsource (lib "eagle-import") (part "TESTPOINT-0.7MM"))
    )
    (comp (ref "TP12")
      (value "TESTPOINT-0.7MM")
      (footprint "eagle-import:PAD0.7MM")
      (libsource (lib "eagle-import") (part "TESTPOINT-0.7MM"))
    )
    (comp (ref "U102")
      (value "RPI-CM4")
      (footprint "eagle-import:RPI-CM4")
      (libsource (lib "eagle-import") (part "RPI-CM4"))
    )
    (comp (ref "U1001")
      (value "LTC4313-3")
      (footprint "eagle-import:DFN8")
      (libsource (lib "eagle-import") (part "LTC4313-3"))
    )
    (comp (ref "U1002")
      (value "UPD301C")
      (footprint "eagle-import:VQFN40")
      (libsource (lib "eagle-import") (part "UPD301C"))
    )
    (comp (ref "U1003")
      (value "MIC2019")
      (footprint "eagle-import:SOT23-6")
      (libsource (lib "eagle-import") (part "MIC2091"))
    )
    (comp (ref "USB1001")
      (value "USB-C-16P-SMD-FLAT-SIDE-TYPE-2")
      (footprint "eagle-import:USB-C-16P-SMD-FLAT-SIDE-TYPE-2")
      (libsource (lib "eagle-import") (part "USB-C-16P-SMD-FLAT-SIDE-TYPE-2"))
    )
    (comp (ref "C801")
      (value "0 Ohms")
      (footprint "eagle-import:CAP0402")
      (libsource (lib "eagle-import") (part "CAPACITOR-0402"))
    )
    (comp (ref "C802")
      (value "0 Ohms")
      (footprint "eagle-import:CAP0402")
      (libsource (lib "eagle-import") (part "CAPACITOR-0402"))
    )
    (comp (ref "C803")
      (value "0 Ohms")
      (footprint "eagle-import:CAP0402")
      (libsource (lib "eagle-import") (part "CAPACITOR-0402"))
    )
    (comp (ref "C804")
      (value "0 Ohms")
      (footprint "eagle-import:CAP0402")
      (libsource (lib "eagle-import") (part "CAPACITOR-0402"))
    )
    (comp (ref "C805")
      (value "0 Ohms")
      (footprint "eagle-import:CAP0402")
      (libsource (lib "eagle-import") (part "CAPACITOR-0402"))
    )
    (comp (ref "C806")
      (value "0 Ohms")
      (footprint "eagle-import:CAP0402")
      (libsource (lib "eagle-import") (part "CAPACITOR-0402"))
    )
    (comp (ref "C807")
      (value "100nF")
      (footprint "eagle-import:CAP0402")
      (libsource (lib "eagle-import") (part "CAPACITOR-0402"))
    )
    (comp (ref "C808")
      (value "100nF")
      (footprint "eagle-import:CAP0402")
      (libsource (lib "eagle-import") (part "CAPACITOR-0402"))
    )
    (comp (ref "C809")
      (value "100nF")
      (footprint "eagle-import:CAP0402")
      (libsource (lib "eagle-import") (part "CAPACITOR-0402"))
    )
    (comp (ref "C810")
      (value "100nF")
      (footprint "eagle-import:CAP0402")
      (libsource (lib "eagle-import") (part "CAPACITOR-0402"))
    )
    (comp (ref "C811")
      (value "100nF")
      (footprint "eagle-import:CAP0402")
      (libsource (lib "eagle-import") (part "CAPACITOR-0402"))
    )
    (comp (ref "C812")
      (value "100nF")
      (footprint "eagle-import:CAP0402")
      (libsource (lib "eagle-import") (part "CAPACITOR-0402"))
    )
    (comp (ref "C813")
      (value "1uF")
      (footprint "eagle-import:CAP0402")
      (libsource (lib "eagle-import") (part "CAPACITOR-0402"))
    )
    (comp (ref "CON801")
      (value "PCIE-X4-EDGE")
      (footprint "eagle-import:PCIE-X4-EDGE")
      (libsource (lib "eagle-import") (part "PCIE-X4-EDGE"))
    )
    (comp (ref "R801")
      (value "10K Ohms")
      (footprint "eagle-import:RES0402")
      (libsource (lib "eagle-import") (part "RESISTOR-0402"))
    )
    (comp (ref "R802")
      (value "10K Ohms")
      (footprint "eagle-import:RES0402")
      (libsource (lib "eagle-import") (part "RESISTOR-0402"))
    )
    (comp (ref "R803")
      (value "10K Ohms")
      (footprint "eagle-import:RES0402")
      (libsource (lib "eagle-import") (part "RESISTOR-0402"))
    )
    (comp (ref "R804")
      (value "10K Ohms")
      (footprint "eagle-import:RES0402")
      (libsource (lib "eagle-import") (part "RESISTOR-0402"))
    )
    (comp (ref "R805")
      (value "10K Ohms")
      (footprint "eagle-import:RES0402")
      (libsource (lib "eagle-import") (part "RESISTOR-0402"))
    )
    (comp (ref "U201")
      (value "XC7A100TFGG484")
      (footprint "eagle-import:FGG484")
      (libsource (lib "eagle-import") (part "XC7A100TFGG484"))
    )
    (comp (ref "C701")
      (value "10uF")
      (footprint "eagle-import:CAP0402")
      (libsource (lib "eagle-import") (part "CAPACITOR-0402"))
    )
    (comp (ref "C702")
      (value "100nF")
      (footprint "eagle-import:CAP0402")
      (libsource (lib "eagle-import") (part "CAPACITOR-0402"))
    )
    (comp (ref "C703")
      (value "100nF")
      (footprint "eagle-import:CAP0402")
      (libsource (lib "eagle-import") (part "CAPACITOR-0402"))
    )
    (comp (ref "C704")
      (value "100nF")
      (footprint "eagle-import:CAP0402")
      (libsource (lib "eagle-import") (part "CAPACITOR-0402"))
    )
    (comp (ref "C705")
      (value "100nF")
      (footprint "eagle-import:CAP0402")
      (libsource (lib "eagle-import") (part "CAPACITOR-0402"))
    )
    (comp (ref "C706")
      (value "10uF")
      (footprint "eagle-import:CAP0402")
      (libsource (lib "eagle-import") (part "CAPACITOR-0402"))
    )
    (comp (ref "C707")
      (value "100nF")
      (footprint "eagle-import:CAP0402")
      (libsource (lib "eagle-import") (part "CAPACITOR-0402"))
    )
    (comp (ref "C708")
      (value "1uF")
      (footprint "eagle-import:CAP0402")
      (libsource (lib "eagle-import") (part "CAPACITOR-0402"))
    )
    (comp (ref "C709")
      (value "10uF")
      (footprint "eagle-import:CAP0402")
      (libsource (lib "eagle-import") (part "CAPACITOR-0402"))
    )
    (comp (ref "C710")
      (value "100nF")
      (footprint "eagle-import:CAP0402")
      (libsource (lib "eagle-import") (part "CAPACITOR-0402"))
    )
    (comp (ref "C711")
      (value "100nF")
      (footprint "eagle-import:CAP0402")
      (libsource (lib "eagle-import") (part "CAPACITOR-0402"))
    )
    (comp (ref "C712")
      (value "100uF")
      (footprint "eagle-import:CAP0805")
      (libsource (lib "eagle-import") (part "CAPACITOR-0805"))
    )
    (comp (ref "C713")
      (value "100uF")
      (footprint "eagle-import:CAP0805")
      (libsource (lib "eagle-import") (part "CAPACITOR-0805"))
    )
    (comp (ref "C714")
      (value "100uF")
      (footprint "eagle-import:CAP0805")
      (libsource (lib "eagle-import") (part "CAPACITOR-0805"))
    )
    (comp (ref "C715")
      (value "100uF")
      (footprint "eagle-import:CAP0805")
      (libsource (lib "eagle-import") (part "CAPACITOR-0805"))
    )
    (comp (ref "C716")
      (value "100nF")
      (footprint "eagle-import:CAP0402")
      (libsource (lib "eagle-import") (part "CAPACITOR-0402"))
    )
    (comp (ref "C717")
      (value "47uF")
      (footprint "eagle-import:CAP0603")
      (libsource (lib "eagle-import") (part "CAPACITOR-0603"))
    )
    (comp (ref "C718")
      (value "47uF")
      (footprint "eagle-import:CAP0603")
      (libsource (lib "eagle-import") (part "CAPACITOR-0603"))
    )
    (comp (ref "C719")
      (value "47uF")
      (footprint "eagle-import:CAP0603")
      (libsource (lib "eagle-import") (part "CAPACITOR-0603"))
    )
    (comp (ref "C720")
      (value "47uF")
      (footprint "eagle-import:CAP0603")
      (libsource (lib "eagle-import") (part "CAPACITOR-0603"))
    )
    (comp (ref "C721")
      (value "DNP")
      (footprint "eagle-import:CAP0402")
      (libsource (lib "eagle-import") (part "CAPACITOR-0402"))
    )
    (comp (ref "C722")
      (value "DNP")
      (footprint "eagle-import:CAP0402")
      (libsource (lib "eagle-import") (part "CAPACITOR-0402"))
    )
    (comp (ref "C723")
      (value "2.2uF")
      (footprint "eagle-import:CAP0402")
      (libsource (lib "eagle-import") (part "CAPACITOR-0402"))
    )
    (comp (ref "C724")
      (value "2.2uF")
      (footprint "eagle-import:CAP0402")
      (libsource (lib "eagle-import") (part "CAPACITOR-0402"))
    )
    (comp (ref "CON701")
      (value "4P-SH-TOP")
      (footprint "eagle-import:SH-04-TOP")
      (libsource (lib "eagle-import") (part "4P-SH-TOP"))
    )
    (comp (ref "FB701")
      (value "1uH")
      (footprint "eagle-import:IND0603")
      (libsource (lib "eagle-import") (part "FERRITE-0603"))
    )
    (comp (ref "J701")
      (value "TRSJACK")
      (footprint "eagle-import:3.5TRSJACK")
      (libsource (lib "eagle-import") (part "TRSJACK"))
    )
    (comp (ref "J702")
      (value "TRSJACK")
      (footprint "eagle-import:3.5TRSJACK")
      (libsource (lib "eagle-import") (part "TRSJACK"))
    )
    (comp (ref "J703")
      (value "TRSJACK")
      (footprint "eagle-import:3.5TRSJACK")
      (libsource (lib "eagle-import") (part "TRSJACK"))
    )
    (comp (ref "L701")
      (value "0 Ohms")
      (footprint "eagle-import:IND0603")
      (libsource (lib "eagle-import") (part "INDUCTOR-0603"))
    )
    (comp (ref "L702")
      (value "0 Ohms")
      (footprint "eagle-import:IND0603")
      (libsource (lib "eagle-import") (part "INDUCTOR-0603"))
    )
    (comp (ref "M701")
      (value "SPH0641LM4H-1")
      (footprint "eagle-import:SPH0641LM4H-1")
      (libsource (lib "eagle-import") (part "SPH0641LM4H-1"))
    )
    (comp (ref "M702")
      (value "SPH0641LM4H-1")
      (footprint "eagle-import:SPH0641LM4H-1")
      (libsource (lib "eagle-import") (part "SPH0641LM4H-1"))
    )
    (comp (ref "R701")
      (value "10K Ohms")
      (footprint "eagle-import:RES0402")
      (libsource (lib "eagle-import") (part "RESISTOR-0402"))
    )
    (comp (ref "R702")
      (value "49.9K Ohms")
      (footprint "eagle-import:RES0402")
      (libsource (lib "eagle-import") (part "RESISTOR-0402"))
    )
    (comp (ref "R703")
      (value "49.9K Ohms")
      (footprint "eagle-import:RES0402")
      (libsource (lib "eagle-import") (part "RESISTOR-0402"))
    )
    (comp (ref "R704")
      (value "2.21K Ohms")
      (footprint "eagle-import:RES0402")
      (libsource (lib "eagle-import") (part "RESISTOR-0402"))
    )
    (comp (ref "R705")
      (value "49.9K Ohms")
      (footprint "eagle-import:RES0402")
      (libsource (lib "eagle-import") (part "RESISTOR-0402"))
    )
    (comp (ref "R706")
      (value "2.21K Ohms")
      (footprint "eagle-import:RES0402")
      (libsource (lib "eagle-import") (part "RESISTOR-0402"))
    )
    (comp (ref "R707")
      (value "49.9K Ohms")
      (footprint "eagle-import:RES0402")
      (libsource (lib "eagle-import") (part "RESISTOR-0402"))
    )
    (comp (ref "R708")
      (value "2.21K Ohms")
      (footprint "eagle-import:RES0402")
      (libsource (lib "eagle-import") (part "RESISTOR-0402"))
    )
    (comp (ref "R709")
      (value "49.9K Ohms")
      (footprint "eagle-import:RES0402")
      (libsource (lib "eagle-import") (part "RESISTOR-0402"))
    )
    (comp (ref "R710")
      (value "2.21K Ohms")
      (footprint "eagle-import:RES0402")
      (libsource (lib "eagle-import") (part "RESISTOR-0402"))
    )
    (comp (ref "R711")
      (value "49.9K Ohms")
      (footprint "eagle-import:RES0402")
      (libsource (lib "eagle-import") (part "RESISTOR-0402"))
    )
    (comp (ref "U701")
      (value "ADAU1372")
      (footprint "eagle-import:QFN40")
      (libsource (lib "eagle-import") (part "ADAU1372"))
    )
    (comp (ref "C901")
      (value "100nF")
      (footprint "eagle-import:CAP0402")
      (libsource (lib "eagle-import") (part "CAPACITOR-0402"))
    )
    (comp (ref "C902")
      (value "1uF")
      (footprint "eagle-import:CAP0402")
      (libsource (lib "eagle-import") (part "CAPACITOR-0402"))
    )
    (comp (ref "C903")
      (value "1uF")
      (footprint "eagle-import:CAP0402")
      (libsource (lib "eagle-import") (part "CAPACITOR-0402"))
    )
    (comp (ref "C904")
      (value "100nF")
      (footprint "eagle-import:CAP0402")
      (libsource (lib "eagle-import") (part "CAPACITOR-0402"))
    )
    (comp (ref "C905")
      (value "100nF")
      (footprint "eagle-import:CAP0402")
      (libsource (lib "eagle-import") (part "CAPACITOR-0402"))
    )
    (comp (ref "C906")
      (value "10pF")
      (footprint "eagle-import:CAP0402")
      (libsource (lib "eagle-import") (part "CAPACITOR-0402"))
    )
    (comp (ref "C907")
      (value "10pF")
      (footprint "eagle-import:CAP0402")
      (libsource (lib "eagle-import") (part "CAPACITOR-0402"))
    )
    (comp (ref "C908")
      (value "100nF")
      (footprint "eagle-import:CAP0402")
      (libsource (lib "eagle-import") (part "CAPACITOR-0402"))
    )
    (comp (ref "C909")
      (value "100nF")
      (footprint "eagle-import:CAP0402")
      (libsource (lib "eagle-import") (part "CAPACITOR-0402"))
    )
    (comp (ref "FB901")
      (value "1uH")
      (footprint "eagle-import:IND0603")
      (libsource (lib "eagle-import") (part "FERRITE-0603"))
    )
    (comp (ref "R901")
      (value "DNP")
      (footprint "eagle-import:RES0402")
      (libsource (lib "eagle-import") (part "RESISTOR-0402"))
    )
    (comp (ref "R902")
      (value "0 Ohms")
      (footprint "eagle-import:RES0402")
      (libsource (lib "eagle-import") (part "RESISTOR-0402"))
    )
    (comp (ref "R903")
      (value "10K Ohms")
      (footprint "eagle-import:RES0402")
      (libsource (lib "eagle-import") (part "RESISTOR-0402"))
    )
    (comp (ref "R904")
      (value "10K Ohms")
      (footprint "eagle-import:RES0402")
      (libsource (lib "eagle-import") (part "RESISTOR-0402"))
    )
    (comp (ref "R905")
      (value "10K Ohms")
      (footprint "eagle-import:RES0402")
      (libsource (lib "eagle-import") (part "RESISTOR-0402"))
    )
    (comp (ref "R906")
      (value "0 Ohms")
      (footprint "eagle-import:RES0402")
      (libsource (lib "eagle-import") (part "RESISTOR-0402"))
    )
    (comp (ref "R907")
      (value "0 Ohms")
      (footprint "eagle-import:RES0402")
      (libsource (lib "eagle-import") (part "RESISTOR-0402"))
    )
    (comp (ref "R908")
      (value "100nF")
      (footprint "eagle-import:RES0402")
      (libsource (lib "eagle-import") (part "RESISTOR-0402"))
    )
    (comp (ref "R909")
      (value "0 Ohms")
      (footprint "eagle-import:RES0402")
      (libsource (lib "eagle-import") (part "RESISTOR-0402"))
    )
    (comp (ref "R910")
      (value "0 Ohms")
      (footprint "eagle-import:RES0402")
      (libsource (lib "eagle-import") (part "RESISTOR-0402"))
    )
    (comp (ref "R911")
      (value "0 Ohms")
      (footprint "eagle-import:RES0402")
      (libsource (lib "eagle-import") (part "RESISTOR-0402"))
    )
    (comp (ref "R912")
      (value "100nF")
      (footprint "eagle-import:RES0402")
      (libsource (lib "eagle-import") (part "RESISTOR-0402"))
    )
    (comp (ref "R913")
      (value "0 Ohms")
      (footprint "eagle-import:RES0402")
      (libsource (lib "eagle-import") (part "RESISTOR-0402"))
    )
    (comp (ref "RFCON901")
      (value "RFCON-U.FL")
      (footprint "eagle-import:U.FL")
      (libsource (lib "eagle-import") (part "RFCON-U.FL"))
    )
    (comp (ref "RFCON902")
      (value "RFCON-U.FL")
      (footprint "eagle-import:U.FL")
      (libsource (lib "eagle-import") (part "RFCON-U.FL"))
    )
    (comp (ref "U901")
      (value "DSB321SDA")
      (footprint "eagle-import:TCXO-3225")
      (libsource (lib "eagle-import") (part "DSB321SDA"))
    )
    (comp (ref "U902")
      (value "SI5351C-B-GM")
      (footprint "eagle-import:QFN20")
      (libsource (lib "eagle-import") (part "SI5351C-B-GM"))
    )
    (comp (ref "C1101")
      (value "100nF")
      (footprint "eagle-import:CAP0402")
      (libsource (lib "eagle-import") (part "CAPACITOR-0402"))
    )
    (comp (ref "C1102")
      (value "100nF")
      (footprint "eagle-import:CAP0402")
      (libsource (lib "eagle-import") (part "CAPACITOR-0402"))
    )
    (comp (ref "C1103")
      (value "10uF")
      (footprint "eagle-import:CAP1206")
      (fields (field (name "VOLTAGE") "50V"))
      (libsource (lib "eagle-import") (part "CAPACITOR-1206"))
    )
    (comp (ref "C1104")
      (value "1uF")
      (footprint "eagle-import:CAP0603")
      (fields (field (name "VOLTAGE") "50V"))
      (libsource (lib "eagle-import") (part "CAPACITOR-0603"))
    )
    (comp (ref "C1105")
      (value "10uF")
      (footprint "eagle-import:CAP1206")
      (fields (field (name "VOLTAGE") "50V"))
      (libsource (lib "eagle-import") (part "CAPACITOR-1206"))
    )
    (comp (ref "C1106")
      (value "100nF")
      (footprint "eagle-import:CAP0402")
      (libsource (lib "eagle-import") (part "CAPACITOR-0402"))
    )
    (comp (ref "C1107")
      (value "100nF")
      (footprint "eagle-import:CAP0402")
      (libsource (lib "eagle-import") (part "CAPACITOR-0402"))
    )
    (comp (ref "C1108")
      (value "4.7uF")
      (footprint "eagle-import:CAP0402")
      (libsource (lib "eagle-import") (part "CAPACITOR-0402"))
    )
    (comp (ref "C1109")
      (value "100nF")
      (footprint "eagle-import:CAP0402")
      (libsource (lib "eagle-import") (part "CAPACITOR-0402"))
    )
    (comp (ref "C1110")
      (value "10uF")
      (footprint "eagle-import:CAP1206")
      (fields (field (name "VOLTAGE") "50V"))
      (libsource (lib "eagle-import") (part "CAPACITOR-1206"))
    )
    (comp (ref "C1111")
      (value "10uF")
      (footprint "eagle-import:CAP1206")
      (fields (field (name "VOLTAGE") "50V"))
      (libsource (lib "eagle-import") (part "CAPACITOR-1206"))
    )
    (comp (ref "C1112")
      (value "10uF")
      (footprint "eagle-import:CAP1206")
      (fields (field (name "VOLTAGE") "50V"))
      (libsource (lib "eagle-import") (part "CAPACITOR-1206"))
    )
    (comp (ref "C1113")
      (value "100nF")
      (footprint "eagle-import:CAP0402")
      (libsource (lib "eagle-import") (part "CAPACITOR-0402"))
    )
    (comp (ref "C1114")
      (value "10uF")
      (footprint "eagle-import:CAP0402")
      (libsource (lib "eagle-import") (part "CAPACITOR-0402"))
    )
    (comp (ref "C1115")
      (value "4.7uF")
      (footprint "eagle-import:CAP0402")
      (libsource (lib "eagle-import") (part "CAPACITOR-0402"))
    )
    (comp (ref "C1116")
      (value "4.7uF")
      (footprint "eagle-import:CAP0603")
      (fields (field (name "VOLTAGE") "35V"))
      (libsource (lib "eagle-import") (part "CAPACITOR-0603"))
    )
    (comp (ref "C1117")
      (value "4.7uF")
      (footprint "eagle-import:CAP0603")
      (fields (field (name "VOLTAGE") "35V"))
      (libsource (lib "eagle-import") (part "CAPACITOR-0603"))
    )
    (comp (ref "C1118")
      (value "4.7uF")
      (footprint "eagle-import:CAP0603")
      (fields (field (name "VOLTAGE") "35V"))
      (libsource (lib "eagle-import") (part "CAPACITOR-0603"))
    )
    (comp (ref "C1119")
      (value "4.7uF")
      (footprint "eagle-import:CAP0603")
      (fields (field (name "VOLTAGE") "35V"))
      (libsource (lib "eagle-import") (part "CAPACITOR-0603"))
    )
    (comp (ref "C1120")
      (value "100nF")
      (footprint "eagle-import:CAP0402")
      (libsource (lib "eagle-import") (part "CAPACITOR-0402"))
    )
    (comp (ref "C1121")
      (value "100nF")
      (footprint "eagle-import:CAP0402")
      (libsource (lib "eagle-import") (part "CAPACITOR-0402"))
    )
    (comp (ref "C1122")
      (value "100uF")
      (footprint "eagle-import:CAP1206")
      (libsource (lib "eagle-import") (part "CAPACITOR-1206"))
    )
    (comp (ref "C1123")
      (value "100uF")
      (footprint "eagle-import:CAP1206")
      (libsource (lib "eagle-import") (part "CAPACITOR-1206"))
    )
    (comp (ref "C1124")
      (value "100uF")
      (footprint "eagle-import:CAP1206")
      (libsource (lib "eagle-import") (part "CAPACITOR-1206"))
    )
    (comp (ref "C1125")
      (value "100uF")
      (footprint "eagle-import:CAP1206")
      (libsource (lib "eagle-import") (part "CAPACITOR-1206"))
    )
    (comp (ref "C1126")
      (value "10uF")
      (footprint "eagle-import:CAP0402")
      (libsource (lib "eagle-import") (part "CAPACITOR-0402"))
    )
    (comp (ref "C1127")
      (value "4.7uF")
      (footprint "eagle-import:CAP0603")
      (libsource (lib "eagle-import") (part "CAPACITOR-0603"))
    )
    (comp (ref "C1128")
      (value "4.7uF")
      (footprint "eagle-import:CAP0402")
      (libsource (lib "eagle-import") (part "CAPACITOR-0402"))
    )
    (comp (ref "C1129")
      (value "100nF")
      (footprint "eagle-import:CAP0402")
      (libsource (lib "eagle-import") (part "CAPACITOR-0402"))
    )
    (comp (ref "C1130")
      (value "100nF")
      (footprint "eagle-import:CAP0402")
      (libsource (lib "eagle-import") (part "CAPACITOR-0402"))
    )
    (comp (ref "CON1101")
      (value "2EDG-2P-5MM-H")
      (footprint "eagle-import:2EDG-2P-5MM-H")
      (libsource (lib "eagle-import") (part "2EDG-2P-5MM-H"))
    )
    (comp (ref "D1101")
      (value "B0530W")
      (footprint "eagle-import:SOD-123")
      (libsource (lib "eagle-import") (part "B0530W"))
    )
    (comp (ref "D1102")
      (value "B0530W")
      (footprint "eagle-import:SOD-123")
      (libsource (lib "eagle-import") (part "B0530W"))
    )
    (comp (ref "D1103")
      (value "B0530W")
      (footprint "eagle-import:SOD-123")
      (libsource (lib "eagle-import") (part "B0530W"))
    )
    (comp (ref "D1104")
      (value "LED0603")
      (footprint "eagle-import:0603")
      (fields (field (name "COLOR") "GREEN"))
      (libsource (lib "eagle-import") (part "LED0603"))
    )
    (comp (ref "D1105")
      (value "SMAJ20A")
      (footprint "eagle-import:DO214AC")
      (fields (field (name "MF") "Littelfuse"))
      (libsource (lib "eagle-import") (part "SMAJA20"))
    )
    (comp (ref "F1101")
      (value "2.6A Hold")
      (footprint "eagle-import:1206")
      (fields (field (name "HOLD") "3A") (field (name "TRIP") "6A"))
      (libsource (lib "eagle-import") (part "PTC1206"))
    )
    (comp (ref "JP1101")
      (value "PINHD-2X3/SMD")
      (footprint "eagle-import:2X03_SMD")
      (fields (field (name "OCLCSC") "C5160777"))
      (libsource (lib "eagle-import") (part "PINHD-2X3/SMD"))
    )
    (comp (ref "L1101")
      (value "4.7uH")
      (footprint "eagle-import:XGL6030")
      (fields (field (name "CURRENT") "7.2A") (field (name "REF") "XGL6030-472"))
      (libsource (lib "eagle-import") (part "XGL6030-472"))
    )
    (comp (ref "L1102")
      (value "2.2uH")
      (footprint "eagle-import:XGL6030")
      (fields (field (name "CURRENT") "8.5A") (field (name "REF") "XGL6030-222"))
      (libsource (lib "eagle-import") (part "XGL6030-222"))
    )
    (comp (ref "Q1101")
      (value "AO3400")
      (footprint "eagle-import:SOT23")
      (libsource (lib "eagle-import") (part "AO3400"))
    )
    (comp (ref "Q1102")
      (value "AO4805")
      (footprint "eagle-import:SOIC8")
      (libsource (lib "eagle-import") (part "AO4805"))
    )
    (comp (ref "Q1103")
      (value "AO3400")
      (footprint "eagle-import:SOT23")
      (libsource (lib "eagle-import") (part "AO3400"))
    )
    (comp (ref "Q1104")
      (value "AO4805")
      (footprint "eagle-import:SOIC8")
      (libsource (lib "eagle-import") (part "AO4805"))
    )
    (comp (ref "Q1105")
      (value "AO4805")
      (footprint "eagle-import:SOIC8")
      (libsource (lib "eagle-import") (part "AO4805"))
    )
    (comp (ref "Q1106")
      (value "AO3400")
      (footprint "eagle-import:SOT23")
      (libsource (lib "eagle-import") (part "AO3400"))
    )
    (comp (ref "R1101")
      (value "100K Ohms")
      (footprint "eagle-import:RES0402")
      (libsource (lib "eagle-import") (part "RESISTOR-0402"))
    )
    (comp (ref "R1102")
      (value "5.1K Ohms")
      (footprint "eagle-import:RES0402")
      (libsource (lib "eagle-import") (part "RESISTOR-0402"))
    )
    (comp (ref "R1103")
      (value "100K Ohms")
      (footprint "eagle-import:RES0402")
      (libsource (lib "eagle-import") (part "RESISTOR-0402"))
    )
    (comp (ref "R1104")
      (value "5.1K Ohms")
      (footprint "eagle-import:RES0402")
      (libsource (lib "eagle-import") (part "RESISTOR-0402"))
    )
    (comp (ref "R1105")
      (value "10K Ohms")
      (footprint "eagle-import:RES0402")
      (libsource (lib "eagle-import") (part "RESISTOR-0402"))
    )
    (comp (ref "R1106")
      (value "1K Ohms")
      (footprint "eagle-import:RES0402")
      (libsource (lib "eagle-import") (part "RESISTOR-0402"))
    )
    (comp (ref "R1107")
      (value "1K Ohms")
      (footprint "eagle-import:RES0402")
      (libsource (lib "eagle-import") (part "RESISTOR-0402"))
    )
    (comp (ref "R1108")
      (value "100K Ohms")
      (footprint "eagle-import:RES0402")
      (libsource (lib "eagle-import") (part "RESISTOR-0402"))
    )
    (comp (ref "R1109")
      (value "5.1K Ohms")
      (footprint "eagle-import:RES0402")
      (libsource (lib "eagle-import") (part "RESISTOR-0402"))
    )
    (comp (ref "R1110")
      (value "100K Ohms")
      (footprint "eagle-import:RES0402")
      (libsource (lib "eagle-import") (part "RESISTOR-0402"))
    )
    (comp (ref "R1111")
      (value "5.1K Ohms")
      (footprint "eagle-import:RES0402")
      (libsource (lib "eagle-import") (part "RESISTOR-0402"))
    )
    (comp (ref "R1112")
      (value "10K Ohms")
      (footprint "eagle-import:RES0402")
      (libsource (lib "eagle-import") (part "RESISTOR-0402"))
    )
    (comp (ref "R1113")
      (value "1K Ohms")
      (footprint "eagle-import:RES0402")
      (libsource (lib "eagle-import") (part "RESISTOR-0402"))
    )
    (comp (ref "R1114")
      (value "1K Ohms")
      (footprint "eagle-import:RES0402")
      (libsource (lib "eagle-import") (part "RESISTOR-0402"))
    )
    (comp (ref "R1115")
      (value "10K Ohms")
      (footprint "eagle-import:RES0402")
      (libsource (lib "eagle-import") (part "RESISTOR-0402"))
    )
    (comp (ref "R1116")
      (value "1K Ohms")
      (footprint "eagle-import:RES0402")
      (libsource (lib "eagle-import") (part "RESISTOR-0402"))
    )
    (comp (ref "R1117")
      (value "1K Ohms")
      (footprint "eagle-import:RES0402")
      (libsource (lib "eagle-import") (part "RESISTOR-0402"))
    )
    (comp (ref "R1118")
      (value "10K Ohms")
      (footprint "eagle-import:RES0402")
      (libsource (lib "eagle-import") (part "RESISTOR-0402"))
    )
    (comp (ref "R1119")
      (value "1K Ohms")
      (footprint "eagle-import:RES0402")
      (libsource (lib "eagle-import") (part "RESISTOR-0402"))
    )
    (comp (ref "R1120")
      (value "DNP")
      (footprint "eagle-import:RES0402")
      (libsource (lib "eagle-import") (part "RESISTOR-0402"))
    )
    (comp (ref "R1121")
      (value "10K Ohms")
      (footprint "eagle-import:RES0402")
      (libsource (lib "eagle-import") (part "RESISTOR-0402"))
    )
    (comp (ref "R1122")
      (value "10K Ohms")
      (footprint "eagle-import:RES0402")
      (libsource (lib "eagle-import") (part "RESISTOR-0402"))
    )
    (comp (ref "R1123")
      (value "DNP")
      (footprint "eagle-import:RES0402")
      (libsource (lib "eagle-import") (part "RESISTOR-0402"))
    )
    (comp (ref "R1124")
      (value "10K Ohms")
      (footprint "eagle-import:RES0402")
      (libsource (lib "eagle-import") (part "RESISTOR-0402"))
    )
    (comp (ref "R1125")
      (value "36.5K Ohms")
      (footprint "eagle-import:RES0402")
      (libsource (lib "eagle-import") (part "RESISTOR-0402"))
    )
    (comp (ref "R1126")
      (value "124K Ohms")
      (footprint "eagle-import:RES0402")
      (libsource (lib "eagle-import") (part "RESISTOR-0402"))
    )
    (comp (ref "R1127")
      (value "51.1K Ohms")
      (footprint "eagle-import:RES0402")
      (libsource (lib "eagle-import") (part "RESISTOR-0402"))
    )
    (comp (ref "R1128")
      (value "0 Ohms")
      (footprint "eagle-import:RES0402")
      (libsource (lib "eagle-import") (part "RESISTOR-0402"))
    )
    (comp (ref "TP1")
      (value "TESTPOINT-0.7MM")
      (footprint "eagle-import:PAD0.7MM")
      (libsource (lib "eagle-import") (part "TESTPOINT-0.7MM"))
    )
    (comp (ref "TP2")
      (value "TESTPOINT-0.7MM")
      (footprint "eagle-import:PAD0.7MM")
      (libsource (lib "eagle-import") (part "TESTPOINT-0.7MM"))
    )
    (comp (ref "TP3")
      (value "TESTPOINT-0.7MM")
      (footprint "eagle-import:PAD0.7MM")
      (libsource (lib "eagle-import") (part "TESTPOINT-0.7MM"))
    )
    (comp (ref "TP4")
      (value "TESTPOINT-0.7MM")
      (footprint "eagle-import:PAD0.7MM")
      (libsource (lib "eagle-import") (part "TESTPOINT-0.7MM"))
    )
    (comp (ref "TP5")
      (value "TESTPOINT-0.7MM")
      (footprint "eagle-import:PAD0.7MM")
      (libsource (lib "eagle-import") (part "TESTPOINT-0.7MM"))
    )
    (comp (ref "TP6")
      (value "TESTPOINT-0.7MM")
      (footprint "eagle-import:PAD0.7MM")
      (libsource (lib "eagle-import") (part "TESTPOINT-0.7MM"))
    )
    (comp (ref "TP7")
      (value "TESTPOINT-0.7MM")
      (footprint "eagle-import:PAD0.7MM")
      (libsource (lib "eagle-import") (part "TESTPOINT-0.7MM"))
    )
    (comp (ref "U1101")
      (value "MCP1804-3302")
      (footprint "eagle-import:SOT23-5")
      (libsource (lib "eagle-import") (part "MCP1804-3302"))
    )
    (comp (ref "U1102")
      (value "LT7182S")
      (footprint "eagle-import:LQFN40_ASYM_CORNER")
      (libsource (lib "eagle-import") (part "LT7182S"))
    )
    (comp (ref "C301")
      (value "100nF")
      (footprint "eagle-import:CAP0402")
      (libsource (lib "eagle-import") (part "CAPACITOR-0402"))
    )
    (comp (ref "C302")
      (value "100nF")
      (footprint "eagle-import:CAP0402")
      (libsource (lib "eagle-import") (part "CAPACITOR-0402"))
    )
    (comp (ref "C303")
      (value "100nF")
      (footprint "eagle-import:CAP0402")
      (libsource (lib "eagle-import") (part "CAPACITOR-0402"))
    )
    (comp (ref "C304")
      (value "100nF")
      (footprint "eagle-import:CAP0402")
      (libsource (lib "eagle-import") (part "CAPACITOR-0402"))
    )
    (comp (ref "C305")
      (value "100nF")
      (footprint "eagle-import:CAP0402")
      (libsource (lib "eagle-import") (part "CAPACITOR-0402"))
    )
    (comp (ref "C306")
      (value "100nF")
      (footprint "eagle-import:CAP0402")
      (libsource (lib "eagle-import") (part "CAPACITOR-0402"))
    )
    (comp (ref "C307")
      (value "100nF")
      (footprint "eagle-import:CAP0402")
      (libsource (lib "eagle-import") (part "CAPACITOR-0402"))
    )
    (comp (ref "C308")
      (value "100nF")
      (footprint "eagle-import:CAP0402")
      (libsource (lib "eagle-import") (part "CAPACITOR-0402"))
    )
    (comp (ref "C309")
      (value "100nF")
      (footprint "eagle-import:CAP0402")
      (libsource (lib "eagle-import") (part "CAPACITOR-0402"))
    )
    (comp (ref "C310")
      (value "100nF")
      (footprint "eagle-import:CAP0402")
      (libsource (lib "eagle-import") (part "CAPACITOR-0402"))
    )
    (comp (ref "C311")
      (value "100nF")
      (footprint "eagle-import:CAP0402")
      (libsource (lib "eagle-import") (part "CAPACITOR-0402"))
    )
    (comp (ref "C312")
      (value "100nF")
      (footprint "eagle-import:CAP0402")
      (libsource (lib "eagle-import") (part "CAPACITOR-0402"))
    )
    (comp (ref "C313")
      (value "100nF")
      (footprint "eagle-import:CAP0402")
      (libsource (lib "eagle-import") (part "CAPACITOR-0402"))
    )
    (comp (ref "C314")
      (value "100nF")
      (footprint "eagle-import:CAP0402")
      (libsource (lib "eagle-import") (part "CAPACITOR-0402"))
    )
    (comp (ref "C315")
      (value "100nF")
      (footprint "eagle-import:CAP0402")
      (libsource (lib "eagle-import") (part "CAPACITOR-0402"))
    )
    (comp (ref "C316")
      (value "100nF")
      (footprint "eagle-import:CAP0402")
      (libsource (lib "eagle-import") (part "CAPACITOR-0402"))
    )
    (comp (ref "C317")
      (value "100nF")
      (footprint "eagle-import:CAP0402")
      (libsource (lib "eagle-import") (part "CAPACITOR-0402"))
    )
    (comp (ref "C318")
      (value "100nF")
      (footprint "eagle-import:CAP0402")
      (libsource (lib "eagle-import") (part "CAPACITOR-0402"))
    )
    (comp (ref "C319")
      (value "100nF")
      (footprint "eagle-import:CAP0402")
      (libsource (lib "eagle-import") (part "CAPACITOR-0402"))
    )
    (comp (ref "C320")
      (value "100nF")
      (footprint "eagle-import:CAP0402")
      (libsource (lib "eagle-import") (part "CAPACITOR-0402"))
    )
    (comp (ref "C321")
      (value "100nF")
      (footprint "eagle-import:CAP0402")
      (libsource (lib "eagle-import") (part "CAPACITOR-0402"))
    )
    (comp (ref "C322")
      (value "47uF")
      (footprint "eagle-import:CAP0603")
      (libsource (lib "eagle-import") (part "CAPACITOR-0603"))
    )
    (comp (ref "C323")
      (value "100nF")
      (footprint "eagle-import:CAP0402")
      (libsource (lib "eagle-import") (part "CAPACITOR-0402"))
    )
    (comp (ref "C324")
      (value "100nF")
      (footprint "eagle-import:CAP0402")
      (libsource (lib "eagle-import") (part "CAPACITOR-0402"))
    )
    (comp (ref "C325")
      (value "100nF")
      (footprint "eagle-import:CAP0402")
      (libsource (lib "eagle-import") (part "CAPACITOR-0402"))
    )
    (comp (ref "C326")
      (value "100nF")
      (footprint "eagle-import:CAP0402")
      (libsource (lib "eagle-import") (part "CAPACITOR-0402"))
    )
    (comp (ref "C327")
      (value "100nF")
      (footprint "eagle-import:CAP0402")
      (libsource (lib "eagle-import") (part "CAPACITOR-0402"))
    )
    (comp (ref "C328")
      (value "4.7uF")
      (footprint "eagle-import:CAP0402")
      (libsource (lib "eagle-import") (part "CAPACITOR-0402"))
    )
    (comp (ref "C329")
      (value "4.7uF")
      (footprint "eagle-import:CAP0402")
      (libsource (lib "eagle-import") (part "CAPACITOR-0402"))
    )
    (comp (ref "C330")
      (value "47uF")
      (footprint "eagle-import:CAP0603")
      (libsource (lib "eagle-import") (part "CAPACITOR-0603"))
    )
    (comp (ref "C331")
      (value "47uF")
      (footprint "eagle-import:CAP0603")
      (libsource (lib "eagle-import") (part "CAPACITOR-0603"))
    )
    (comp (ref "R301")
      (value "240 Ohms")
      (footprint "eagle-import:RES0402")
      (libsource (lib "eagle-import") (part "RESISTOR-0402"))
    )
    (comp (ref "R302")
      (value "1K Ohms")
      (footprint "eagle-import:RES0402")
      (libsource (lib "eagle-import") (part "RESISTOR-0402"))
    )
    (comp (ref "R303")
      (value "40.2 Ohms")
      (footprint "eagle-import:RES0402")
      (libsource (lib "eagle-import") (part "RESISTOR-0402"))
    )
    (comp (ref "R304")
      (value "40.2 Ohms")
      (footprint "eagle-import:RES0402")
      (libsource (lib "eagle-import") (part "RESISTOR-0402"))
    )
    (comp (ref "R305")
      (value "40.2 Ohms")
      (footprint "eagle-import:RES0402")
      (libsource (lib "eagle-import") (part "RESISTOR-0402"))
    )
    (comp (ref "R306")
      (value "40.2 Ohms")
      (footprint "eagle-import:RES0402")
      (libsource (lib "eagle-import") (part "RESISTOR-0402"))
    )
    (comp (ref "R307")
      (value "40.2 Ohms")
      (footprint "eagle-import:RES0402")
      (libsource (lib "eagle-import") (part "RESISTOR-0402"))
    )
    (comp (ref "R308")
      (value "40.2 Ohms")
      (footprint "eagle-import:RES0402")
      (libsource (lib "eagle-import") (part "RESISTOR-0402"))
    )
    (comp (ref "R309")
      (value "40.2 Ohms")
      (footprint "eagle-import:RES0402")
      (libsource (lib "eagle-import") (part "RESISTOR-0402"))
    )
    (comp (ref "R310")
      (value "40.2 Ohms")
      (footprint "eagle-import:RES0402")
      (libsource (lib "eagle-import") (part "RESISTOR-0402"))
    )
    (comp (ref "R311")
      (value "40.2 Ohms")
      (footprint "eagle-import:RES0402")
      (libsource (lib "eagle-import") (part "RESISTOR-0402"))
    )
    (comp (ref "R312")
      (value "40.2 Ohms")
      (footprint "eagle-import:RES0402")
      (libsource (lib "eagle-import") (part "RESISTOR-0402"))
    )
    (comp (ref "R313")
      (value "40.2 Ohms")
      (footprint "eagle-import:RES0402")
      (libsource (lib "eagle-import") (part "RESISTOR-0402"))
    )
    (comp (ref "R314")
      (value "40.2 Ohms")
      (footprint "eagle-import:RES0402")
      (libsource (lib "eagle-import") (part "RESISTOR-0402"))
    )
    (comp (ref "R315")
      (value "40.2 Ohms")
      (footprint "eagle-import:RES0402")
      (libsource (lib "eagle-import") (part "RESISTOR-0402"))
    )
    (comp (ref "R316")
      (value "40.2 Ohms")
      (footprint "eagle-import:RES0402")
      (libsource (lib "eagle-import") (part "RESISTOR-0402"))
    )
    (comp (ref "R317")
      (value "40.2 Ohms")
      (footprint "eagle-import:RES0402")
      (libsource (lib "eagle-import") (part "RESISTOR-0402"))
    )
    (comp (ref "R318")
      (value "40.2 Ohms")
      (footprint "eagle-import:RES0402")
      (libsource (lib "eagle-import") (part "RESISTOR-0402"))
    )
    (comp (ref "R319")
      (value "40.2 Ohms")
      (footprint "eagle-import:RES0402")
      (libsource (lib "eagle-import") (part "RESISTOR-0402"))
    )
    (comp (ref "R320")
      (value "40.2 Ohms")
      (footprint "eagle-import:RES0402")
      (libsource (lib "eagle-import") (part "RESISTOR-0402"))
    )
    (comp (ref "R321")
      (value "40.2 Ohms")
      (footprint "eagle-import:RES0402")
      (libsource (lib "eagle-import") (part "RESISTOR-0402"))
    )
    (comp (ref "R322")
      (value "40.2 Ohms")
      (footprint "eagle-import:RES0402")
      (libsource (lib "eagle-import") (part "RESISTOR-0402"))
    )
    (comp (ref "R323")
      (value "40.2 Ohms")
      (footprint "eagle-import:RES0402")
      (libsource (lib "eagle-import") (part "RESISTOR-0402"))
    )
    (comp (ref "R324")
      (value "DNP")
      (footprint "eagle-import:RES0402")
      (libsource (lib "eagle-import") (part "RESISTOR-0402"))
    )
    (comp (ref "R325")
      (value "40.2 Ohms")
      (footprint "eagle-import:RES0402")
      (libsource (lib "eagle-import") (part "RESISTOR-0402"))
    )
    (comp (ref "R326")
      (value "40.2 Ohms")
      (footprint "eagle-import:RES0402")
      (libsource (lib "eagle-import") (part "RESISTOR-0402"))
    )
    (comp (ref "R327")
      (value "40.2 Ohms")
      (footprint "eagle-import:RES0402")
      (libsource (lib "eagle-import") (part "RESISTOR-0402"))
    )
    (comp (ref "R328")
      (value "40.2 Ohms")
      (footprint "eagle-import:RES0402")
      (libsource (lib "eagle-import") (part "RESISTOR-0402"))
    )
    (comp (ref "U301")
      (value "MT41K256M16TW-125")
      (footprint "eagle-import:FBGA96_14X8")
      (libsource (lib "eagle-import") (part "MT41K256M16?TW-125"))
    )
    (comp (ref "C201")
      (value "470nF")
      (footprint "eagle-import:CAP0402")
      (libsource (lib "eagle-import") (part "CAPACITOR-0402"))
    )
    (comp (ref "C202")
      (value "4.7uF")
      (footprint "eagle-import:CAP0402")
      (libsource (lib "eagle-import") (part "CAPACITOR-0402"))
    )
    (comp (ref "C203")
      (value "470nF")
      (footprint "eagle-import:CAP0402")
      (libsource (lib "eagle-import") (part "CAPACITOR-0402"))
    )
    (comp (ref "C204")
      (value "470nF")
      (footprint "eagle-import:CAP0402")
      (libsource (lib "eagle-import") (part "CAPACITOR-0402"))
    )
    (comp (ref "C205")
      (value "470nF")
      (footprint "eagle-import:CAP0402")
      (libsource (lib "eagle-import") (part "CAPACITOR-0402"))
    )
    (comp (ref "C206")
      (value "470nF")
      (footprint "eagle-import:CAP0402")
      (libsource (lib "eagle-import") (part "CAPACITOR-0402"))
    )
    (comp (ref "C207")
      (value "470nF")
      (footprint "eagle-import:CAP0402")
      (libsource (lib "eagle-import") (part "CAPACITOR-0402"))
    )
    (comp (ref "C208")
      (value "470nF")
      (footprint "eagle-import:CAP0402")
      (libsource (lib "eagle-import") (part "CAPACITOR-0402"))
    )
    (comp (ref "C209")
      (value "470nF")
      (footprint "eagle-import:CAP0402")
      (libsource (lib "eagle-import") (part "CAPACITOR-0402"))
    )
    (comp (ref "C210")
      (value "470nF")
      (footprint "eagle-import:CAP0402")
      (libsource (lib "eagle-import") (part "CAPACITOR-0402"))
    )
    (comp (ref "C211")
      (value "470nF")
      (footprint "eagle-import:CAP0402")
      (libsource (lib "eagle-import") (part "CAPACITOR-0402"))
    )
    (comp (ref "C212")
      (value "470nF")
      (footprint "eagle-import:CAP0402")
      (libsource (lib "eagle-import") (part "CAPACITOR-0402"))
    )
    (comp (ref "C213")
      (value "470nF")
      (footprint "eagle-import:CAP0402")
      (libsource (lib "eagle-import") (part "CAPACITOR-0402"))
    )
    (comp (ref "C214")
      (value "470nF")
      (footprint "eagle-import:CAP0402")
      (libsource (lib "eagle-import") (part "CAPACITOR-0402"))
    )
    (comp (ref "C215")
      (value "470nF")
      (footprint "eagle-import:CAP0402")
      (libsource (lib "eagle-import") (part "CAPACITOR-0402"))
    )
    (comp (ref "C216")
      (value "470nF")
      (footprint "eagle-import:CAP0402")
      (libsource (lib "eagle-import") (part "CAPACITOR-0402"))
    )
    (comp (ref "C217")
      (value "470nF")
      (footprint "eagle-import:CAP0402")
      (libsource (lib "eagle-import") (part "CAPACITOR-0402"))
    )
    (comp (ref "C218")
      (value "470nF")
      (footprint "eagle-import:CAP0402")
      (libsource (lib "eagle-import") (part "CAPACITOR-0402"))
    )
    (comp (ref "C219")
      (value "470nF")
      (footprint "eagle-import:CAP0402")
      (libsource (lib "eagle-import") (part "CAPACITOR-0402"))
    )
    (comp (ref "C220")
      (value "470nF")
      (footprint "eagle-import:CAP0402")
      (libsource (lib "eagle-import") (part "CAPACITOR-0402"))
    )
    (comp (ref "C221")
      (value "470nF")
      (footprint "eagle-import:CAP0402")
      (libsource (lib "eagle-import") (part "CAPACITOR-0402"))
    )
    (comp (ref "C222")
      (value "4.7uF")
      (footprint "eagle-import:CAP0402")
      (libsource (lib "eagle-import") (part "CAPACITOR-0402"))
    )
    (comp (ref "C223")
      (value "4.7uF")
      (footprint "eagle-import:CAP0402")
      (libsource (lib "eagle-import") (part "CAPACITOR-0402"))
    )
    (comp (ref "C224")
      (value "4.7uF")
      (footprint "eagle-import:CAP0402")
      (libsource (lib "eagle-import") (part "CAPACITOR-0402"))
    )
    (comp (ref "C225")
      (value "4.7uF")
      (footprint "eagle-import:CAP0402")
      (libsource (lib "eagle-import") (part "CAPACITOR-0402"))
    )
    (comp (ref "C226")
      (value "470nF")
      (footprint "eagle-import:CAP0402")
      (libsource (lib "eagle-import") (part "CAPACITOR-0402"))
    )
    (comp (ref "C227")
      (value "4.7uF")
      (footprint "eagle-import:CAP0402")
      (libsource (lib "eagle-import") (part "CAPACITOR-0402"))
    )
    (comp (ref "C228")
      (value "4.7uF")
      (footprint "eagle-import:CAP0402")
      (libsource (lib "eagle-import") (part "CAPACITOR-0402"))
    )
    (comp (ref "C229")
      (value "4.7uF")
      (footprint "eagle-import:CAP0402")
      (libsource (lib "eagle-import") (part "CAPACITOR-0402"))
    )
    (comp (ref "C230")
      (value "4.7uF")
      (footprint "eagle-import:CAP0402")
      (libsource (lib "eagle-import") (part "CAPACITOR-0402"))
    )
    (comp (ref "C231")
      (value "4.7uF")
      (footprint "eagle-import:CAP0402")
      (libsource (lib "eagle-import") (part "CAPACITOR-0402"))
    )
    (comp (ref "C232")
      (value "47uF")
      (footprint "eagle-import:CAP0603")
      (libsource (lib "eagle-import") (part "CAPACITOR-0603"))
    )
    (comp (ref "C233")
      (value "470nF")
      (footprint "eagle-import:CAP0402")
      (libsource (lib "eagle-import") (part "CAPACITOR-0402"))
    )
    (comp (ref "C234")
      (value "470nF")
      (footprint "eagle-import:CAP0402")
      (libsource (lib "eagle-import") (part "CAPACITOR-0402"))
    )
    (comp (ref "C235")
      (value "470nF")
      (footprint "eagle-import:CAP0402")
      (libsource (lib "eagle-import") (part "CAPACITOR-0402"))
    )
    (comp (ref "C236")
      (value "4.7uF")
      (footprint "eagle-import:CAP0402")
      (libsource (lib "eagle-import") (part "CAPACITOR-0402"))
    )
    (comp (ref "C237")
      (value "4.7uF")
      (footprint "eagle-import:CAP0402")
      (libsource (lib "eagle-import") (part "CAPACITOR-0402"))
    )
    (comp (ref "C238")
      (value "470nF")
      (footprint "eagle-import:CAP0402")
      (libsource (lib "eagle-import") (part "CAPACITOR-0402"))
    )
    (comp (ref "C239")
      (value "470nF")
      (footprint "eagle-import:CAP0402")
      (libsource (lib "eagle-import") (part "CAPACITOR-0402"))
    )
    (comp (ref "C240")
      (value "470nF")
      (footprint "eagle-import:CAP0402")
      (libsource (lib "eagle-import") (part "CAPACITOR-0402"))
    )
    (comp (ref "C241")
      (value "4.7uF")
      (footprint "eagle-import:CAP0402")
      (libsource (lib "eagle-import") (part "CAPACITOR-0402"))
    )
    (comp (ref "C242")
      (value "100nF")
      (footprint "eagle-import:CAP0402")
      (libsource (lib "eagle-import") (part "CAPACITOR-0402"))
    )
    (comp (ref "C243")
      (value "470nF")
      (footprint "eagle-import:CAP0402")
      (libsource (lib "eagle-import") (part "CAPACITOR-0402"))
    )
    (comp (ref "C244")
      (value "470nF")
      (footprint "eagle-import:CAP0402")
      (libsource (lib "eagle-import") (part "CAPACITOR-0402"))
    )
    (comp (ref "C245")
      (value "470nF")
      (footprint "eagle-import:CAP0402")
      (libsource (lib "eagle-import") (part "CAPACITOR-0402"))
    )
    (comp (ref "C246")
      (value "4.7uF")
      (footprint "eagle-import:CAP0402")
      (libsource (lib "eagle-import") (part "CAPACITOR-0402"))
    )
    (comp (ref "C247")
      (value "100nF")
      (footprint "eagle-import:CAP0402")
      (libsource (lib "eagle-import") (part "CAPACITOR-0402"))
    )
    (comp (ref "C248")
      (value "470nF")
      (footprint "eagle-import:CAP0402")
      (libsource (lib "eagle-import") (part "CAPACITOR-0402"))
    )
    (comp (ref "C249")
      (value "470nF")
      (footprint "eagle-import:CAP0402")
      (libsource (lib "eagle-import") (part "CAPACITOR-0402"))
    )
    (comp (ref "C250")
      (value "470nF")
      (footprint "eagle-import:CAP0402")
      (libsource (lib "eagle-import") (part "CAPACITOR-0402"))
    )
    (comp (ref "C251")
      (value "47uF")
      (footprint "eagle-import:CAP0603")
      (libsource (lib "eagle-import") (part "CAPACITOR-0603"))
    )
    (comp (ref "C252")
      (value "4.7uF")
      (footprint "eagle-import:CAP0402")
      (libsource (lib "eagle-import") (part "CAPACITOR-0402"))
    )
    (comp (ref "C253")
      (value "4.7uF")
      (footprint "eagle-import:CAP0402")
      (libsource (lib "eagle-import") (part "CAPACITOR-0402"))
    )
    (comp (ref "C254")
      (value "4.7uF")
      (footprint "eagle-import:CAP0402")
      (libsource (lib "eagle-import") (part "CAPACITOR-0402"))
    )
    (comp (ref "C255")
      (value "4.7uF")
      (footprint "eagle-import:CAP0402")
      (libsource (lib "eagle-import") (part "CAPACITOR-0402"))
    )
    (comp (ref "C256")
      (value "47uF")
      (footprint "eagle-import:CAP0603")
      (libsource (lib "eagle-import") (part "CAPACITOR-0603"))
    )
    (comp (ref "C257")
      (value "47uF")
      (footprint "eagle-import:CAP0603")
      (libsource (lib "eagle-import") (part "CAPACITOR-0603"))
    )
    (comp (ref "C258")
      (value "4.7uF")
      (footprint "eagle-import:CAP0402")
      (libsource (lib "eagle-import") (part "CAPACITOR-0402"))
    )
    (comp (ref "C259")
      (value "4.7uF")
      (footprint "eagle-import:CAP0402")
      (libsource (lib "eagle-import") (part "CAPACITOR-0402"))
    )
    (comp (ref "C260")
      (value "4.7uF")
      (footprint "eagle-import:CAP0402")
      (libsource (lib "eagle-import") (part "CAPACITOR-0402"))
    )
    (comp (ref "C261")
      (value "100nF")
      (footprint "eagle-import:CAP0402")
      (libsource (lib "eagle-import") (part "CAPACITOR-0402"))
    )
    (comp (ref "C262")
      (value "100nF")
      (footprint "eagle-import:CAP0402")
      (libsource (lib "eagle-import") (part "CAPACITOR-0402"))
    )
    (comp (ref "C263")
      (value "4.7uF")
      (footprint "eagle-import:CAP0402")
      (libsource (lib "eagle-import") (part "CAPACITOR-0402"))
    )
    (comp (ref "C264")
      (value "100nF")
      (footprint "eagle-import:CAP0402")
      (libsource (lib "eagle-import") (part "CAPACITOR-0402"))
    )
    (comp (ref "D201")
      (value "LED0603")
      (footprint "eagle-import:0603")
      (fields (field (name "COLOR") "GREEN"))
      (libsource (lib "eagle-import") (part "LED0603"))
    )
    (comp (ref "D202")
      (value "LED0603")
      (footprint "eagle-import:0603")
      (fields (field (name "COLOR") "BLUE"))
      (libsource (lib "eagle-import") (part "LED0603"))
    )
    (comp (ref "JP201")
      (value "PINHD-2X3/SMD")
      (footprint "eagle-import:2X03_SMD")
      (fields (field (name "OCLCSC") "C5160777"))
      (libsource (lib "eagle-import") (part "PINHD-2X3/SMD"))
    )
    (comp (ref "JP202")
      (value "PINHD-2X3/SMD")
      (footprint "eagle-import:2X03_SMD")
      (fields (field (name "OCLCSC") "C5160777"))
      (libsource (lib "eagle-import") (part "PINHD-2X3/SMD"))
    )
    (comp (ref "R201")
      (value "4.7K Ohms")
      (footprint "eagle-import:RES0402")
      (libsource (lib "eagle-import") (part "RESISTOR-0402"))
    )
    (comp (ref "R202")
      (value "4.7K Ohms")
      (footprint "eagle-import:RES0402")
      (libsource (lib "eagle-import") (part "RESISTOR-0402"))
    )
    (comp (ref "R203")
      (value "22 Ohms")
      (footprint "eagle-import:RES0402")
      (libsource (lib "eagle-import") (part "RESISTOR-0402"))
    )
    (comp (ref "R204")
      (value "22 Ohms")
      (footprint "eagle-import:RES0402")
      (libsource (lib "eagle-import") (part "RESISTOR-0402"))
    )
    (comp (ref "R205")
      (value "4.7K Ohms")
      (footprint "eagle-import:RES0402")
      (libsource (lib "eagle-import") (part "RESISTOR-0402"))
    )
    (comp (ref "R206")
      (value "22 Ohms")
      (footprint "eagle-import:RES0402")
      (libsource (lib "eagle-import") (part "RESISTOR-0402"))
    )
    (comp (ref "R207")
      (value "4.7K Ohms")
      (footprint "eagle-import:RES0402")
      (libsource (lib "eagle-import") (part "RESISTOR-0402"))
    )
    (comp (ref "R208")
      (value "22 Ohms")
      (footprint "eagle-import:RES0402")
      (libsource (lib "eagle-import") (part "RESISTOR-0402"))
    )
    (comp (ref "R209")
      (value "22 Ohms")
      (footprint "eagle-import:RES0402")
      (libsource (lib "eagle-import") (part "RESISTOR-0402"))
    )
    (comp (ref "R210")
      (value "100 Ohms")
      (footprint "eagle-import:RES0402")
      (fields (field (name "TOLERANCE") "1%"))
      (libsource (lib "eagle-import") (part "RESISTOR-0402"))
    )
    (comp (ref "R211")
      (value "22 Ohms")
      (footprint "eagle-import:RES0402")
      (libsource (lib "eagle-import") (part "RESISTOR-0402"))
    )
    (comp (ref "R212")
      (value "22 Ohms")
      (footprint "eagle-import:RES0402")
      (libsource (lib "eagle-import") (part "RESISTOR-0402"))
    )
    (comp (ref "R213")
      (value "22 Ohms")
      (footprint "eagle-import:RES0402")
      (libsource (lib "eagle-import") (part "RESISTOR-0402"))
    )
    (comp (ref "R214")
      (value "4.7K Ohms")
      (footprint "eagle-import:RES0402")
      (libsource (lib "eagle-import") (part "RESISTOR-0402"))
    )
    (comp (ref "R215")
      (value "2.4K Ohms")
      (footprint "eagle-import:RES0402")
      (libsource (lib "eagle-import") (part "RESISTOR-0402"))
    )
    (comp (ref "R216")
      (value "4.7K Ohms")
      (footprint "eagle-import:RES0402")
      (libsource (lib "eagle-import") (part "RESISTOR-0402"))
    )
    (comp (ref "R217")
      (value "4.7K Ohms")
      (footprint "eagle-import:RES0402")
      (libsource (lib "eagle-import") (part "RESISTOR-0402"))
    )
    (comp (ref "R218")
      (value "4.7K Ohms")
      (footprint "eagle-import:RES0402")
      (libsource (lib "eagle-import") (part "RESISTOR-0402"))
    )
    (comp (ref "R219")
      (value "1K Ohms")
      (footprint "eagle-import:RES0402")
      (libsource (lib "eagle-import") (part "RESISTOR-0402"))
    )
    (comp (ref "R220")
      (value "10K Ohms")
      (footprint "eagle-import:RES0402")
      (libsource (lib "eagle-import") (part "RESISTOR-0402"))
    )
    (comp (ref "R221")
      (value "10K Ohms")
      (footprint "eagle-import:RES0402")
      (libsource (lib "eagle-import") (part "RESISTOR-0402"))
    )
    (comp (ref "R222")
      (value "1K Ohms")
      (footprint "eagle-import:RES0402")
      (libsource (lib "eagle-import") (part "RESISTOR-0402"))
    )
    (comp (ref "TC201")
      (value "TC2050-IDC")
      (footprint "eagle-import:TC2050-IDC")
      (libsource (lib "eagle-import") (part "TC2050-IDC"))
    )
    (comp (ref "U202")
      (value "SST26VF064B")
      (footprint "eagle-import:WSOIC8")
      (libsource (lib "eagle-import") (part "SST26VF064B"))
    )
    (comp (ref "C1201")
      (value "100nF")
      (footprint "eagle-import:CAP0402")
      (libsource (lib "eagle-import") (part "CAPACITOR-0402"))
    )
    (comp (ref "C1202")
      (value "100nF")
      (footprint "eagle-import:CAP0402")
      (libsource (lib "eagle-import") (part "CAPACITOR-0402"))
    )
    (comp (ref "C1203")
      (value "100nF")
      (footprint "eagle-import:CAP0402")
      (libsource (lib "eagle-import") (part "CAPACITOR-0402"))
    )
    (comp (ref "C1204")
      (value "100nF")
      (footprint "eagle-import:CAP0402")
      (libsource (lib "eagle-import") (part "CAPACITOR-0402"))
    )
    (comp (ref "C1205")
      (value "4.7uF")
      (footprint "eagle-import:CAP0603")
      (libsource (lib "eagle-import") (part "CAPACITOR-0603"))
    )
    (comp (ref "C1206")
      (value "10nF")
      (footprint "eagle-import:CAP0402")
      (libsource (lib "eagle-import") (part "CAPACITOR-0402"))
    )
    (comp (ref "C1207")
      (value "10nF")
      (footprint "eagle-import:CAP0402")
      (libsource (lib "eagle-import") (part "CAPACITOR-0402"))
    )
    (comp (ref "C1208")
      (value "10nF")
      (footprint "eagle-import:CAP0402")
      (libsource (lib "eagle-import") (part "CAPACITOR-0402"))
    )
    (comp (ref "C1209")
      (value "100nF")
      (footprint "eagle-import:CAP0402")
      (libsource (lib "eagle-import") (part "CAPACITOR-0402"))
    )
    (comp (ref "C1210")
      (value "100uF")
      (footprint "eagle-import:CAP1206")
      (libsource (lib "eagle-import") (part "CAPACITOR-1206"))
    )
    (comp (ref "C1211")
      (value "470pF")
      (footprint "eagle-import:CAP0402")
      (libsource (lib "eagle-import") (part "CAPACITOR-0402"))
    )
    (comp (ref "C1212")
      (value "10uF")
      (footprint "eagle-import:CAP0603")
      (libsource (lib "eagle-import") (part "CAPACITOR-0603"))
    )
    (comp (ref "C1213")
      (value "10uF")
      (footprint "eagle-import:CAP0402")
      (libsource (lib "eagle-import") (part "CAPACITOR-0402"))
    )
    (comp (ref "C1214")
      (value "10uF")
      (footprint "eagle-import:CAP0402")
      (libsource (lib "eagle-import") (part "CAPACITOR-0402"))
    )
    (comp (ref "C1215")
      (value "100nF")
      (footprint "eagle-import:CAP0402")
      (libsource (lib "eagle-import") (part "CAPACITOR-0402"))
    )
    (comp (ref "C1216")
      (value "10uF")
      (footprint "eagle-import:CAP0402")
      (libsource (lib "eagle-import") (part "CAPACITOR-0402"))
    )
    (comp (ref "C1217")
      (value "10uF")
      (footprint "eagle-import:CAP0402")
      (libsource (lib "eagle-import") (part "CAPACITOR-0402"))
    )
    (comp (ref "C1218")
      (value "10uF")
      (footprint "eagle-import:CAP0402")
      (libsource (lib "eagle-import") (part "CAPACITOR-0402"))
    )
    (comp (ref "C1219")
      (value "10uF")
      (footprint "eagle-import:CAP0402")
      (libsource (lib "eagle-import") (part "CAPACITOR-0402"))
    )
    (comp (ref "C1220")
      (value "10uF")
      (footprint "eagle-import:CAP0402")
      (libsource (lib "eagle-import") (part "CAPACITOR-0402"))
    )
    (comp (ref "C1221")
      (value "470pF")
      (footprint "eagle-import:CAP0402")
      (libsource (lib "eagle-import") (part "CAPACITOR-0402"))
    )
    (comp (ref "C1222")
      (value "47uF")
      (footprint "eagle-import:CAP0603")
      (libsource (lib "eagle-import") (part "CAPACITOR-0603"))
    )
    (comp (ref "C1223")
      (value "47uF")
      (footprint "eagle-import:CAP0603")
      (libsource (lib "eagle-import") (part "CAPACITOR-0603"))
    )
    (comp (ref "C1224")
      (value "4.7uF")
      (footprint "eagle-import:CAP0402")
      (libsource (lib "eagle-import") (part "CAPACITOR-0402"))
    )
    (comp (ref "C1225")
      (value "1uF")
      (footprint "eagle-import:CAP0402")
      (libsource (lib "eagle-import") (part "CAPACITOR-0402"))
    )
    (comp (ref "C1226")
      (value "100nF")
      (footprint "eagle-import:CAP0402")
      (libsource (lib "eagle-import") (part "CAPACITOR-0402"))
    )
    (comp (ref "C1227")
      (value "100uF")
      (footprint "eagle-import:CAP1206")
      (libsource (lib "eagle-import") (part "CAPACITOR-1206"))
    )
    (comp (ref "C1228")
      (value "100nF")
      (footprint "eagle-import:CAP0402")
      (libsource (lib "eagle-import") (part "CAPACITOR-0402"))
    )
    (comp (ref "C1229")
      (value "100nF")
      (footprint "eagle-import:CAP0402")
      (libsource (lib "eagle-import") (part "CAPACITOR-0402"))
    )
    (comp (ref "C1230")
      (value "100nF")
      (footprint "eagle-import:CAP0402")
      (libsource (lib "eagle-import") (part "CAPACITOR-0402"))
    )
    (comp (ref "C1231")
      (value "10nF")
      (footprint "eagle-import:CAP0402")
      (libsource (lib "eagle-import") (part "CAPACITOR-0402"))
    )
    (comp (ref "C1232")
      (value "4.7uF")
      (footprint "eagle-import:CAP0603")
      (libsource (lib "eagle-import") (part "CAPACITOR-0603"))
    )
    (comp (ref "C1233")
      (value "10nF")
      (footprint "eagle-import:CAP0402")
      (libsource (lib "eagle-import") (part "CAPACITOR-0402"))
    )
    (comp (ref "C1234")
      (value "1uF")
      (footprint "eagle-import:CAP0402")
      (libsource (lib "eagle-import") (part "CAPACITOR-0402"))
    )
    (comp (ref "C1235")
      (value "10uF")
      (footprint "eagle-import:CAP0402")
      (libsource (lib "eagle-import") (part "CAPACITOR-0402"))
    )
    (comp (ref "C1236")
      (value "10uF")
      (footprint "eagle-import:CAP0402")
      (libsource (lib "eagle-import") (part "CAPACITOR-0402"))
    )
    (comp (ref "C1237")
      (value "10uF")
      (footprint "eagle-import:CAP0402")
      (libsource (lib "eagle-import") (part "CAPACITOR-0402"))
    )
    (comp (ref "C1238")
      (value "10uF")
      (footprint "eagle-import:CAP0402")
      (libsource (lib "eagle-import") (part "CAPACITOR-0402"))
    )
    (comp (ref "C1239")
      (value "100nF")
      (footprint "eagle-import:CAP0402")
      (libsource (lib "eagle-import") (part "CAPACITOR-0402"))
    )
    (comp (ref "C1240")
      (value "10uF")
      (footprint "eagle-import:CAP0402")
      (libsource (lib "eagle-import") (part "CAPACITOR-0402"))
    )
    (comp (ref "C1241")
      (value "10uF")
      (footprint "eagle-import:CAP0402")
      (libsource (lib "eagle-import") (part "CAPACITOR-0402"))
    )
    (comp (ref "C1242")
      (value "4.7uF")
      (footprint "eagle-import:CAP0603")
      (libsource (lib "eagle-import") (part "CAPACITOR-0603"))
    )
    (comp (ref "C1243")
      (value "10uF")
      (footprint "eagle-import:CAP0402")
      (libsource (lib "eagle-import") (part "CAPACITOR-0402"))
    )
    (comp (ref "C1244")
      (value "10uF")
      (footprint "eagle-import:CAP0402")
      (libsource (lib "eagle-import") (part "CAPACITOR-0402"))
    )
    (comp (ref "C1245")
      (value "100nF")
      (footprint "eagle-import:CAP0402")
      (libsource (lib "eagle-import") (part "CAPACITOR-0402"))
    )
    (comp (ref "C1246")
      (value "100uF")
      (footprint "eagle-import:CAP1206")
      (libsource (lib "eagle-import") (part "CAPACITOR-1206"))
    )
    (comp (ref "C1247")
      (value "100nF")
      (footprint "eagle-import:CAP0402")
      (libsource (lib "eagle-import") (part "CAPACITOR-0402"))
    )
    (comp (ref "C1248")
      (value "4.7uF")
      (footprint "eagle-import:CAP0603")
      (libsource (lib "eagle-import") (part "CAPACITOR-0603"))
    )
    (comp (ref "C1249")
      (value "470pF")
      (footprint "eagle-import:CAP0402")
      (libsource (lib "eagle-import") (part "CAPACITOR-0402"))
    )
    (comp (ref "C1250")
      (value "100nF")
      (footprint "eagle-import:CAP0402")
      (libsource (lib "eagle-import") (part "CAPACITOR-0402"))
    )
    (comp (ref "C1251")
      (value "470pF")
      (footprint "eagle-import:CAP0402")
      (libsource (lib "eagle-import") (part "CAPACITOR-0402"))
    )
    (comp (ref "C1252")
      (value "470pF")
      (footprint "eagle-import:CAP0402")
      (libsource (lib "eagle-import") (part "CAPACITOR-0402"))
    )
    (comp (ref "C1253")
      (value "100nF")
      (footprint "eagle-import:CAP0402")
      (libsource (lib "eagle-import") (part "CAPACITOR-0402"))
    )
    (comp (ref "C1254")
      (value "100uF")
      (footprint "eagle-import:CAP1206")
      (libsource (lib "eagle-import") (part "CAPACITOR-1206"))
    )
    (comp (ref "C1255")
      (value "10uF")
      (footprint "eagle-import:CAP0402")
      (libsource (lib "eagle-import") (part "CAPACITOR-0402"))
    )
    (comp (ref "C1256")
      (value "100nF")
      (footprint "eagle-import:CAP0402")
      (libsource (lib "eagle-import") (part "CAPACITOR-0402"))
    )
    (comp (ref "C1257")
      (value "10uF")
      (footprint "eagle-import:CAP0402")
      (libsource (lib "eagle-import") (part "CAPACITOR-0402"))
    )
    (comp (ref "C1258")
      (value "4.7uF")
      (footprint "eagle-import:CAP0603")
      (libsource (lib "eagle-import") (part "CAPACITOR-0603"))
    )
    (comp (ref "C1259")
      (value "10uF")
      (footprint "eagle-import:CAP0402")
      (libsource (lib "eagle-import") (part "CAPACITOR-0402"))
    )
    (comp (ref "L1201")
      (value "2.2uH")
      (footprint "eagle-import:XGL351X")
      (fields
        (field (name "CURRENT") "3.8A")
        (field (name "REF") "XGL3515-222")
        (field (name "CURRENT_1") "3.8A")
      )
      (libsource (lib "eagle-import") (part "XGL3515-222"))
    )
    (comp (ref "L1202")
      (value "2.2uH")
      (footprint "eagle-import:XGL351X")
      (fields
        (field (name "CURRENT") "3.8A")
        (field (name "REF") "XGL3515-222")
        (field (name "CURRENT_1") "3.8A")
      )
      (libsource (lib "eagle-import") (part "XGL3515-222"))
    )
    (comp (ref "L1203")
      (value "2.2uH")
      (footprint "eagle-import:XGL351X")
      (fields
        (field (name "CURRENT") "3.8A")
        (field (name "REF") "XGL3515-222")
        (field (name "CURRENT_1") "3.8A")
      )
      (libsource (lib "eagle-import") (part "XGL3515-222"))
    )
    (comp (ref "L1204")
      (value "2.2uH")
      (footprint "eagle-import:XGL351X")
      (fields
        (field (name "CURRENT") "3.8A")
        (field (name "REF") "XGL3515-222")
        (field (name "CURRENT_1") "3.8A")
      )
      (libsource (lib "eagle-import") (part "XGL3515-222"))
    )
    (comp (ref "L1205")
      (value "2.2uH")
      (footprint "eagle-import:XGL351X")
      (fields
        (field (name "CURRENT") "3.8A")
        (field (name "REF") "XGL3515-222")
        (field (name "CURRENT_1") "3.8A")
      )
      (libsource (lib "eagle-import") (part "XGL3515-222"))
    )
    (comp (ref "R1201")
      (value "10K Ohms")
      (footprint "eagle-import:RES0402")
      (libsource (lib "eagle-import") (part "RESISTOR-0402"))
    )
    (comp (ref "R1202")
      (value "118K Ohms")
      (footprint "eagle-import:RES0402")
      (libsource (lib "eagle-import") (part "RESISTOR-0402"))
    )
    (comp (ref "R1203")
      (value "100K Ohms")
      (footprint "eagle-import:RES0402")
      (libsource (lib "eagle-import") (part "RESISTOR-0402"))
    )
    (comp (ref "R1204")
      (value "10K Ohms")
      (footprint "eagle-import:RES0402")
      (libsource (lib "eagle-import") (part "RESISTOR-0402"))
    )
    (comp (ref "R1205")
      (value "301K Ohms")
      (footprint "eagle-import:RES0402")
      (libsource (lib "eagle-import") (part "RESISTOR-0402"))
    )
    (comp (ref "R1206")
      (value "158K Ohms")
      (footprint "eagle-import:RES0402")
      (libsource (lib "eagle-import") (part "RESISTOR-0402"))
    )
    (comp (ref "R1207")
      (value "10K Ohms")
      (footprint "eagle-import:RES0402")
      (libsource (lib "eagle-import") (part "RESISTOR-0402"))
    )
    (comp (ref "R1208")
      (value "324K Ohms")
      (footprint "eagle-import:RES0402")
      (libsource (lib "eagle-import") (part "RESISTOR-0402"))
    )
    (comp (ref "R1209")
      (value "107K Ohms")
      (footprint "eagle-import:RES0402")
      (libsource (lib "eagle-import") (part "RESISTOR-0402"))
    )
    (comp (ref "R1210")
      (value "10K Ohms")
      (footprint "eagle-import:RES0402")
      (libsource (lib "eagle-import") (part "RESISTOR-0402"))
    )
    (comp (ref "R1211")
      (value "10K Ohms")
      (footprint "eagle-import:RES0402")
      (libsource (lib "eagle-import") (part "RESISTOR-0402"))
    )
    (comp (ref "R1212")
      (value "309K Ohms")
      (footprint "eagle-import:RES0402")
      (libsource (lib "eagle-import") (part "RESISTOR-0402"))
    )
    (comp (ref "R1213")
      (value "71.5K Ohms")
      (footprint "eagle-import:RES0402")
      (libsource (lib "eagle-import") (part "RESISTOR-0402"))
    )
    (comp (ref "R1214")
      (value "274K Ohms")
      (footprint "eagle-import:RES0402")
      (libsource (lib "eagle-import") (part "RESISTOR-0402"))
    )
    (comp (ref "R1215")
      (value "294K Ohms")
      (footprint "eagle-import:RES0402")
      (libsource (lib "eagle-import") (part "RESISTOR-0402"))
    )
    (comp (ref "U1201")
      (value "ADM7172ACPZ-5.0")
      (footprint "eagle-import:LFCSP8_3X3")
      (libsource (lib "eagle-import") (part "ADM7172ACPZ-5.0"))
    )
    (comp (ref "U1202")
      (value "ADM7171ACPZ-1.3")
      (footprint "eagle-import:LFCSP8_3X3")
      (libsource (lib "eagle-import") (part "ADM7171ACPZ-1.3"))
    )
    (comp (ref "U1203")
      (value "ADM7171ACPZ-3.3")
      (footprint "eagle-import:LFCSP8_3X3")
      (libsource (lib "eagle-import") (part "ADM7171ACPZ-3.3"))
    )
    (comp (ref "U1204")
      (value "MIC23159")
      (footprint "eagle-import:VQFN20")
      (libsource (lib "eagle-import") (part "MIC23159"))
    )
    (comp (ref "U1205")
      (value "MIC5166")
      (footprint "eagle-import:DFN10")
      (libsource (lib "eagle-import") (part "MIC5166"))
    )
    (comp (ref "U1206")
      (value "ADM7171ACPZ-1.3")
      (footprint "eagle-import:LFCSP8_3X3")
      (libsource (lib "eagle-import") (part "ADM7171ACPZ-1.3"))
    )
    (comp (ref "U1207")
      (value "ADM7171ACPZ-3.3")
      (footprint "eagle-import:LFCSP8_3X3")
      (libsource (lib "eagle-import") (part "ADM7171ACPZ-3.3"))
    )
    (comp (ref "U1208")
      (value "MIC23159")
      (footprint "eagle-import:VQFN20")
      (libsource (lib "eagle-import") (part "MIC23159"))
    )
    (comp (ref "U1209")
      (value "MIC23155")
      (footprint "eagle-import:DFN10_0.65P")
      (libsource (lib "eagle-import") (part "MIC23155"))
    )
    (comp (ref "U1210")
      (value "ADP7142AUJZ-3.3")
      (footprint "eagle-import:SOT23-5")
      (libsource (lib "eagle-import") (part "ADP7142AUJZ-3.3"))
    )
    (comp (ref "C501")
      (value "18pF")
      (footprint "eagle-import:CAP0402")
      (libsource (lib "eagle-import") (part "CAPACITOR-0402"))
    )
    (comp (ref "C502")
      (value "18pF")
      (footprint "eagle-import:CAP0402")
      (libsource (lib "eagle-import") (part "CAPACITOR-0402"))
    )
    (comp (ref "C503")
      (value "10uF")
      (footprint "eagle-import:CAP0603")
      (libsource (lib "eagle-import") (part "CAPACITOR-0603"))
    )
    (comp (ref "C504")
      (value "10uF")
      (footprint "eagle-import:CAP0603")
      (libsource (lib "eagle-import") (part "CAPACITOR-0603"))
    )
    (comp (ref "C505")
      (value "100pF")
      (footprint "eagle-import:CAP0402")
      (libsource (lib "eagle-import") (part "CAPACITOR-0402"))
    )
    (comp (ref "C506")
      (value "100pF")
      (footprint "eagle-import:CAP0402")
      (libsource (lib "eagle-import") (part "CAPACITOR-0402"))
    )
    (comp (ref "C507")
      (value "100nF")
      (footprint "eagle-import:CAP0402")
      (libsource (lib "eagle-import") (part "CAPACITOR-0402"))
    )
    (comp (ref "C508")
      (value "100nF")
      (footprint "eagle-import:CAP0402")
      (libsource (lib "eagle-import") (part "CAPACITOR-0402"))
    )
    (comp (ref "C509")
      (value "18pF")
      (footprint "eagle-import:CAP0402")
      (libsource (lib "eagle-import") (part "CAPACITOR-0402"))
    )
    (comp (ref "C510")
      (value "18pF")
      (footprint "eagle-import:CAP0402")
      (libsource (lib "eagle-import") (part "CAPACITOR-0402"))
    )
    (comp (ref "C511")
      (value "18pF")
      (footprint "eagle-import:CAP0402")
      (libsource (lib "eagle-import") (part "CAPACITOR-0402"))
    )
    (comp (ref "C512")
      (value "18pF")
      (footprint "eagle-import:CAP0402")
      (libsource (lib "eagle-import") (part "CAPACITOR-0402"))
    )
    (comp (ref "C513")
      (value "18pF")
      (footprint "eagle-import:CAP0402")
      (libsource (lib "eagle-import") (part "CAPACITOR-0402"))
    )
    (comp (ref "C514")
      (value "18pF")
      (footprint "eagle-import:CAP0402")
      (libsource (lib "eagle-import") (part "CAPACITOR-0402"))
    )
    (comp (ref "C515")
      (value "18pF")
      (footprint "eagle-import:CAP0402")
      (libsource (lib "eagle-import") (part "CAPACITOR-0402"))
    )
    (comp (ref "C516")
      (value "18pF")
      (footprint "eagle-import:CAP0402")
      (libsource (lib "eagle-import") (part "CAPACITOR-0402"))
    )
    (comp (ref "C517")
      (value "10uF")
      (footprint "eagle-import:CAP0603")
      (libsource (lib "eagle-import") (part "CAPACITOR-0603"))
    )
    (comp (ref "C518")
      (value "10uF")
      (footprint "eagle-import:CAP0603")
      (libsource (lib "eagle-import") (part "CAPACITOR-0603"))
    )
    (comp (ref "C519")
      (value "10uF")
      (footprint "eagle-import:CAP0603")
      (libsource (lib "eagle-import") (part "CAPACITOR-0603"))
    )
    (comp (ref "C520")
      (value "10uF")
      (footprint "eagle-import:CAP0603")
      (libsource (lib "eagle-import") (part "CAPACITOR-0603"))
    )
    (comp (ref "C521")
      (value "10uF")
      (footprint "eagle-import:CAP0603")
      (libsource (lib "eagle-import") (part "CAPACITOR-0603"))
    )
    (comp (ref "C522")
      (value "10uF")
      (footprint "eagle-import:CAP0603")
      (libsource (lib "eagle-import") (part "CAPACITOR-0603"))
    )
    (comp (ref "C523")
      (value "10uF")
      (footprint "eagle-import:CAP0402")
      (libsource (lib "eagle-import") (part "CAPACITOR-0402"))
    )
    (comp (ref "C524")
      (value "10uF")
      (footprint "eagle-import:CAP0402")
      (libsource (lib "eagle-import") (part "CAPACITOR-0402"))
    )
    (comp (ref "C525")
      (value "1nF")
      (footprint "eagle-import:CAP0402")
      (libsource (lib "eagle-import") (part "CAPACITOR-0402"))
    )
    (comp (ref "C526")
      (value "1nF")
      (footprint "eagle-import:CAP0402")
      (libsource (lib "eagle-import") (part "CAPACITOR-0402"))
    )
    (comp (ref "C527")
      (value "1nF")
      (footprint "eagle-import:CAP0402")
      (libsource (lib "eagle-import") (part "CAPACITOR-0402"))
    )
    (comp (ref "C528")
      (value "1nF")
      (footprint "eagle-import:CAP0402")
      (libsource (lib "eagle-import") (part "CAPACITOR-0402"))
    )
    (comp (ref "C529")
      (value "1nF")
      (footprint "eagle-import:CAP0402")
      (libsource (lib "eagle-import") (part "CAPACITOR-0402"))
    )
    (comp (ref "C530")
      (value "18pF")
      (footprint "eagle-import:CAP0402")
      (libsource (lib "eagle-import") (part "CAPACITOR-0402"))
    )
    (comp (ref "C531")
      (value "18pF")
      (footprint "eagle-import:CAP0402")
      (libsource (lib "eagle-import") (part "CAPACITOR-0402"))
    )
    (comp (ref "C532")
      (value "18pF")
      (footprint "eagle-import:CAP0402")
      (libsource (lib "eagle-import") (part "CAPACITOR-0402"))
    )
    (comp (ref "C533")
      (value "18pF")
      (footprint "eagle-import:CAP0402")
      (libsource (lib "eagle-import") (part "CAPACITOR-0402"))
    )
    (comp (ref "C534")
      (value "10uF")
      (footprint "eagle-import:CAP0402")
      (libsource (lib "eagle-import") (part "CAPACITOR-0402"))
    )
    (comp (ref "C535")
      (value "10uF")
      (footprint "eagle-import:CAP0402")
      (libsource (lib "eagle-import") (part "CAPACITOR-0402"))
    )
    (comp (ref "C536")
      (value "1nF")
      (footprint "eagle-import:CAP0402")
      (libsource (lib "eagle-import") (part "CAPACITOR-0402"))
    )
    (comp (ref "C537")
      (value "1nF")
      (footprint "eagle-import:CAP0402")
      (libsource (lib "eagle-import") (part "CAPACITOR-0402"))
    )
    (comp (ref "C538")
      (value "18pF")
      (footprint "eagle-import:CAP0402")
      (libsource (lib "eagle-import") (part "CAPACITOR-0402"))
    )
    (comp (ref "C539")
      (value "18pF")
      (footprint "eagle-import:CAP0402")
      (libsource (lib "eagle-import") (part "CAPACITOR-0402"))
    )
    (comp (ref "C540")
      (value "1nF")
      (footprint "eagle-import:CAP0402")
      (libsource (lib "eagle-import") (part "CAPACITOR-0402"))
    )
    (comp (ref "C541")
      (value "1nF")
      (footprint "eagle-import:CAP0402")
      (libsource (lib "eagle-import") (part "CAPACITOR-0402"))
    )
    (comp (ref "C542")
      (value "100nF")
      (footprint "eagle-import:CAP0402")
      (libsource (lib "eagle-import") (part "CAPACITOR-0402"))
    )
    (comp (ref "C543")
      (value "100nF")
      (footprint "eagle-import:CAP0402")
      (libsource (lib "eagle-import") (part "CAPACITOR-0402"))
    )
    (comp (ref "C544")
      (value "18pF")
      (footprint "eagle-import:CAP0402")
      (libsource (lib "eagle-import") (part "CAPACITOR-0402"))
    )
    (comp (ref "C545")
      (value "18pF")
      (footprint "eagle-import:CAP0402")
      (libsource (lib "eagle-import") (part "CAPACITOR-0402"))
    )
    (comp (ref "C546")
      (value "18pF")
      (footprint "eagle-import:CAP0402")
      (libsource (lib "eagle-import") (part "CAPACITOR-0402"))
    )
    (comp (ref "C547")
      (value "18pF")
      (footprint "eagle-import:CAP0402")
      (libsource (lib "eagle-import") (part "CAPACITOR-0402"))
    )
    (comp (ref "C548")
      (value "1nF")
      (footprint "eagle-import:CAP0402")
      (libsource (lib "eagle-import") (part "CAPACITOR-0402"))
    )
    (comp (ref "C549")
      (value "1nF")
      (footprint "eagle-import:CAP0402")
      (libsource (lib "eagle-import") (part "CAPACITOR-0402"))
    )
    (comp (ref "C550")
      (value "1nF")
      (footprint "eagle-import:CAP0402")
      (libsource (lib "eagle-import") (part "CAPACITOR-0402"))
    )
    (comp (ref "C551")
      (value "18pF")
      (footprint "eagle-import:CAP0402")
      (libsource (lib "eagle-import") (part "CAPACITOR-0402"))
    )
    (comp (ref "C552")
      (value "18pF")
      (footprint "eagle-import:CAP0402")
      (libsource (lib "eagle-import") (part "CAPACITOR-0402"))
    )
    (comp (ref "C553")
      (value "18pF")
      (footprint "eagle-import:CAP0402")
      (libsource (lib "eagle-import") (part "CAPACITOR-0402"))
    )
    (comp (ref "C554")
      (value "18pF")
      (footprint "eagle-import:CAP0402")
      (libsource (lib "eagle-import") (part "CAPACITOR-0402"))
    )
    (comp (ref "D501")
      (value "PGB1010402")
      (footprint "eagle-import:TVS0402")
      (libsource (lib "eagle-import") (part "PGB1010402"))
    )
    (comp (ref "D502")
      (value "PGB1010402")
      (footprint "eagle-import:TVS0402")
      (libsource (lib "eagle-import") (part "PGB1010402"))
    )
    (comp (ref "D503")
      (value "PGB1010402")
      (footprint "eagle-import:TVS0402")
      (libsource (lib "eagle-import") (part "PGB1010402"))
    )
    (comp (ref "D504")
      (value "PGB1010402")
      (footprint "eagle-import:TVS0402")
      (libsource (lib "eagle-import") (part "PGB1010402"))
    )
    (comp (ref "D505")
      (value "LED0603")
      (footprint "eagle-import:0603")
      (fields (field (name "COLOR") "YELLOW"))
      (libsource (lib "eagle-import") (part "LED0603"))
    )
    (comp (ref "D506")
      (value "LED0603")
      (footprint "eagle-import:0603")
      (fields (field (name "COLOR") "YELLOW"))
      (libsource (lib "eagle-import") (part "LED0603"))
    )
    (comp (ref "D507")
      (value "LED0603")
      (footprint "eagle-import:0603")
      (fields (field (name "COLOR") "YELLOW"))
      (libsource (lib "eagle-import") (part "LED0603"))
    )
    (comp (ref "D508")
      (value "LED0603")
      (footprint "eagle-import:0603")
      (fields (field (name "COLOR") "YELLOW"))
      (libsource (lib "eagle-import") (part "LED0603"))
    )
    (comp (ref "D509")
      (value "PGB1010402")
      (footprint "eagle-import:TVS0402")
      (libsource (lib "eagle-import") (part "PGB1010402"))
    )
    (comp (ref "D510")
      (value "PGB1010402")
      (footprint "eagle-import:TVS0402")
      (libsource (lib "eagle-import") (part "PGB1010402"))
    )
    (comp (ref "D511")
      (value "PGB1010402")
      (footprint "eagle-import:TVS0402")
      (libsource (lib "eagle-import") (part "PGB1010402"))
    )
    (comp (ref "D512")
      (value "PGB1010402")
      (footprint "eagle-import:TVS0402")
      (libsource (lib "eagle-import") (part "PGB1010402"))
    )
    (comp (ref "L501")
      (value "330nH")
      (footprint "eagle-import:IND0805")
      (libsource (lib "eagle-import") (part "INDUCTOR-0805"))
    )
    (comp (ref "L502")
      (value "330nH")
      (footprint "eagle-import:IND0805")
      (libsource (lib "eagle-import") (part "INDUCTOR-0805"))
    )
    (comp (ref "L503")
      (value "330nH")
      (footprint "eagle-import:IND0603")
      (libsource (lib "eagle-import") (part "INDUCTOR-0603"))
    )
    (comp (ref "L504")
      (value "330nH")
      (footprint "eagle-import:IND0603")
      (libsource (lib "eagle-import") (part "INDUCTOR-0603"))
    )
    (comp (ref "L505")
      (value "330nH")
      (footprint "eagle-import:IND0603")
      (libsource (lib "eagle-import") (part "INDUCTOR-0603"))
    )
    (comp (ref "L506")
      (value "330nH")
      (footprint "eagle-import:IND0603")
      (libsource (lib "eagle-import") (part "INDUCTOR-0603"))
    )
    (comp (ref "L507")
      (value "330nH")
      (footprint "eagle-import:IND0603")
      (libsource (lib "eagle-import") (part "INDUCTOR-0603"))
    )
    (comp (ref "L508")
      (value "330nH")
      (footprint "eagle-import:IND0603")
      (libsource (lib "eagle-import") (part "INDUCTOR-0603"))
    )
    (comp (ref "L509")
      (value "330nH")
      (footprint "eagle-import:IND0603")
      (libsource (lib "eagle-import") (part "INDUCTOR-0603"))
    )
    (comp (ref "L510")
      (value "330nH")
      (footprint "eagle-import:IND0603")
      (libsource (lib "eagle-import") (part "INDUCTOR-0603"))
    )
    (comp (ref "L511")
      (value "330nH")
      (footprint "eagle-import:IND0603")
      (libsource (lib "eagle-import") (part "INDUCTOR-0603"))
    )
    (comp (ref "L512")
      (value "330nH")
      (footprint "eagle-import:IND0603")
      (libsource (lib "eagle-import") (part "INDUCTOR-0603"))
    )
    (comp (ref "R501")
      (value "470 Ohms")
      (footprint "eagle-import:RES0402")
      (libsource (lib "eagle-import") (part "RESISTOR-0402"))
    )
    (comp (ref "R502")
      (value "470 Ohms")
      (footprint "eagle-import:RES0402")
      (libsource (lib "eagle-import") (part "RESISTOR-0402"))
    )
    (comp (ref "R503")
      (value "10K Ohms")
      (footprint "eagle-import:RES0402")
      (libsource (lib "eagle-import") (part "RESISTOR-0402"))
    )
    (comp (ref "R504")
      (value "10K Ohms")
      (footprint "eagle-import:RES0402")
      (libsource (lib "eagle-import") (part "RESISTOR-0402"))
    )
    (comp (ref "R505")
      (value "1K Ohms")
      (footprint "eagle-import:RES0402")
      (libsource (lib "eagle-import") (part "RESISTOR-0402"))
    )
    (comp (ref "R506")
      (value "1K Ohms")
      (footprint "eagle-import:RES0402")
      (libsource (lib "eagle-import") (part "RESISTOR-0402"))
    )
    (comp (ref "R507")
      (value "300 Ohms")
      (footprint "eagle-import:RES0402")
      (libsource (lib "eagle-import") (part "RESISTOR-0402"))
    )
    (comp (ref "R508")
      (value "300 Ohms")
      (footprint "eagle-import:RES0402")
      (libsource (lib "eagle-import") (part "RESISTOR-0402"))
    )
    (comp (ref "R509")
      (value "10K Ohms")
      (footprint "eagle-import:RES0402")
      (libsource (lib "eagle-import") (part "RESISTOR-0402"))
    )
    (comp (ref "R510")
      (value "10K Ohms")
      (footprint "eagle-import:RES0402")
      (libsource (lib "eagle-import") (part "RESISTOR-0402"))
    )
    (comp (ref "R511")
      (value "1K Ohms")
      (footprint "eagle-import:RES0402")
      (libsource (lib "eagle-import") (part "RESISTOR-0402"))
    )
    (comp (ref "R512")
      (value "1K Ohms")
      (footprint "eagle-import:RES0402")
      (libsource (lib "eagle-import") (part "RESISTOR-0402"))
    )
    (comp (ref "R513")
      (value "49.9 Ohms")
      (footprint "eagle-import:RES0402")
      (libsource (lib "eagle-import") (part "RESISTOR-0402"))
    )
    (comp (ref "R514")
      (value "10 Ohms")
      (footprint "eagle-import:RES0402")
      (libsource (lib "eagle-import") (part "RESISTOR-0402"))
    )
    (comp (ref "R515")
      (value "49.9 Ohms")
      (footprint "eagle-import:RES0402")
      (libsource (lib "eagle-import") (part "RESISTOR-0402"))
    )
    (comp (ref "R516")
      (value "10 Ohms")
      (footprint "eagle-import:RES0402")
      (libsource (lib "eagle-import") (part "RESISTOR-0402"))
    )
    (comp (ref "RFCON501")
      (value "RFCON-SMA-RA")
      (footprint "eagle-import:SMA-RA")
      (libsource (lib "eagle-import") (part "RFCON-SMA-RA"))
    )
    (comp (ref "RFCON502")
      (value "RFCON-SMA-RA")
      (footprint "eagle-import:SMA-RA")
      (libsource (lib "eagle-import") (part "RFCON-SMA-RA"))
    )
    (comp (ref "RFCON503")
      (value "RFCON-SMA-RA")
      (footprint "eagle-import:SMA-RA")
      (libsource (lib "eagle-import") (part "RFCON-SMA-RA"))
    )
    (comp (ref "RFCON504")
      (value "RFCON-SMA-RA")
      (footprint "eagle-import:SMA-RA")
      (libsource (lib "eagle-import") (part "RFCON-SMA-RA"))
    )
    (comp (ref "RFCON505")
      (value "RFCON-U.FL")
      (footprint "eagle-import:U.FL")
      (libsource (lib "eagle-import") (part "RFCON-U.FL"))
    )
    (comp (ref "RFCON506")
      (value "RFCON-U.FL")
      (footprint "eagle-import:U.FL")
      (libsource (lib "eagle-import") (part "RFCON-U.FL"))
    )
    (comp (ref "RFCON507")
      (value "RFCON-SMA-RA")
      (footprint "eagle-import:SMA-RA")
      (libsource (lib "eagle-import") (part "RFCON-SMA-RA"))
    )
    (comp (ref "RFCON508")
      (value "RFCON-SMA-RA")
      (footprint "eagle-import:SMA-RA")
      (libsource (lib "eagle-import") (part "RFCON-SMA-RA"))
    )
    (comp (ref "RFCON509")
      (value "RFCON-SMA")
      (footprint "eagle-import:SMA")
      (libsource (lib "eagle-import") (part "RFCON-SMA"))
    )
    (comp (ref "RFCON510")
      (value "RFCON-SMA")
      (footprint "eagle-import:SMA")
      (libsource (lib "eagle-import") (part "RFCON-SMA"))
    )
    (comp (ref "T501")
      (value "UWB1-85E")
      (footprint "eagle-import:UWB1")
      (libsource (lib "eagle-import") (part "UWB1-85E"))
    )
    (comp (ref "T502")
      (value "UWB1-85E")
      (footprint "eagle-import:UWB1")
      (libsource (lib "eagle-import") (part "UWB1-85E"))
    )
    (comp (ref "T503")
      (value "UWB1-85E")
      (footprint "eagle-import:UWB1")
      (libsource (lib "eagle-import") (part "UWB1-85E"))
    )
    (comp (ref "T504")
      (value "UWB1-85E")
      (footprint "eagle-import:UWB1")
      (libsource (lib "eagle-import") (part "UWB1-85E"))
    )
    (comp (ref "T505")
      (value "UWB1-85E")
      (footprint "eagle-import:UWB1")
      (libsource (lib "eagle-import") (part "UWB1-85E"))
    )
    (comp (ref "T506")
      (value "UWB1-85E")
      (footprint "eagle-import:UWB1")
      (libsource (lib "eagle-import") (part "UWB1-85E"))
    )
    (comp (ref "T507")
      (value "UWB1-85E")
      (footprint "eagle-import:UWB1")
      (libsource (lib "eagle-import") (part "UWB1-85E"))
    )
    (comp (ref "T508")
      (value "UWB1-85E")
      (footprint "eagle-import:UWB1")
      (libsource (lib "eagle-import") (part "UWB1-85E"))
    )
    (comp (ref "U501")
      (value "MIC2019")
      (footprint "eagle-import:SOT23-6")
      (libsource (lib "eagle-import") (part "MIC2091"))
    )
    (comp (ref "U502")
      (value "MIC2019")
      (footprint "eagle-import:SOT23-6")
      (libsource (lib "eagle-import") (part "MIC2091"))
    )
    (comp (ref "U503")
      (value "MIC2019")
      (footprint "eagle-import:SOT23-6")
      (libsource (lib "eagle-import") (part "MIC2091"))
    )
    (comp (ref "U504")
      (value "MIC2019")
      (footprint "eagle-import:SOT23-6")
      (libsource (lib "eagle-import") (part "MIC2091"))
    )
    (comp (ref "U505")
      (value "ADL5601")
      (footprint "eagle-import:SOT89")
      (libsource (lib "eagle-import") (part "ADL5?601"))
    )
    (comp (ref "U506")
      (value "ADL5601")
      (footprint "eagle-import:SOT89")
      (libsource (lib "eagle-import") (part "ADL5?601"))
    )
    (comp (ref "C101")
      (value "100nF")
      (footprint "eagle-import:CAP0402")
      (libsource (lib "eagle-import") (part "CAPACITOR-0402"))
    )
    (comp (ref "C102")
      (value "10uF")
      (footprint "eagle-import:CAP0603")
      (libsource (lib "eagle-import") (part "CAPACITOR-0603"))
    )
    (comp (ref "C103")
      (value "10uF")
      (footprint "eagle-import:CAP0603")
      (libsource (lib "eagle-import") (part "CAPACITOR-0603"))
    )
    (comp (ref "C104")
      (value "10uF")
      (footprint "eagle-import:CAP0603")
      (libsource (lib "eagle-import") (part "CAPACITOR-0603"))
    )
    (comp (ref "C105")
      (value "10uF")
      (footprint "eagle-import:CAP0402")
      (libsource (lib "eagle-import") (part "CAPACITOR-0402"))
    )
    (comp (ref "C106")
      (value "1uF")
      (footprint "eagle-import:CAP0402")
      (libsource (lib "eagle-import") (part "CAPACITOR-0402"))
    )
    (comp (ref "C107")
      (value "100nF")
      (footprint "eagle-import:CAP0402")
      (libsource (lib "eagle-import") (part "CAPACITOR-0402"))
    )
    (comp (ref "C108")
      (value "1uF")
      (footprint "eagle-import:CAP0402")
      (libsource (lib "eagle-import") (part "CAPACITOR-0402"))
    )
    (comp (ref "CON101")
      (value "FPC-22P")
      (footprint "eagle-import:FPC-22P")
      (libsource (lib "eagle-import") (part "FPC-22P"))
    )
    (comp (ref "CON102")
      (value "FPC-22P")
      (footprint "eagle-import:FPC-22P")
      (libsource (lib "eagle-import") (part "FPC-22P"))
    )
    (comp (ref "D101")
      (value "LED0603")
      (footprint "eagle-import:0603")
      (fields (field (name "COLOR") "GREEN"))
      (libsource (lib "eagle-import") (part "LED0603"))
    )
    (comp (ref "D102")
      (value "LED0603")
      (footprint "eagle-import:0603")
      (fields (field (name "COLOR") "RED"))
      (libsource (lib "eagle-import") (part "LED0603"))
    )
    (comp (ref "J101")
      (value "RJ45_MAG_LED_1G-TE-1-2301994-0")
      (footprint "eagle-import:TE-1-2301994-0")
      (libsource (lib "eagle-import") (part "RJ45_MAG_LED_1G-TE-1-2301994-0"))
    )
    (comp (ref "JP101")
      (value "PINHD-1X3")
      (footprint "eagle-import:1X03")
      (libsource (lib "eagle-import") (part "PINHD-1X3"))
    )
    (comp (ref "LOGO101")
      (value "JS-10MM")
      (footprint "eagle-import:JS_10MM")
      (libsource (lib "eagle-import") (part "JS-10MM"))
    )
    (comp (ref "Q101")
      (value "AO3400")
      (footprint "eagle-import:SOT23")
      (libsource (lib "eagle-import") (part "AO3400"))
    )
    (comp (ref "Q102")
      (value "AO3400")
      (footprint "eagle-import:SOT23")
      (libsource (lib "eagle-import") (part "AO3400"))
    )
    (comp (ref "R101")
      (value "1K Ohms")
      (footprint "eagle-import:RES0402")
      (libsource (lib "eagle-import") (part "RESISTOR-0402"))
    )
    (comp (ref "R102")
      (value "2.2K Ohms")
      (footprint "eagle-import:RES0402")
      (libsource (lib "eagle-import") (part "RESISTOR-0402"))
    )
    (comp (ref "R103")
      (value "10K Ohms")
      (footprint "eagle-import:RES0402")
      (libsource (lib "eagle-import") (part "RESISTOR-0402"))
    )
    (comp (ref "R104")
      (value "1.2K Ohms")
      (footprint "eagle-import:RES0402")
      (libsource (lib "eagle-import") (part "RESISTOR-0402"))
    )
    (comp (ref "R105")
      (value "0 Ohms")
      (footprint "eagle-import:RES0402")
      (libsource (lib "eagle-import") (part "RESISTOR-0402"))
    )
    (comp (ref "R106")
      (value "1K Ohms")
      (footprint "eagle-import:RES0402")
      (libsource (lib "eagle-import") (part "RESISTOR-0402"))
    )
    (comp (ref "R107")
      (value "0 Ohms")
      (footprint "eagle-import:RES0402")
      (libsource (lib "eagle-import") (part "RESISTOR-0402"))
    )
    (comp (ref "R108")
      (value "10K Ohms")
      (footprint "eagle-import:RES0402")
      (libsource (lib "eagle-import") (part "RESISTOR-0402"))
    )
    (comp (ref "R109")
      (value "DNP")
      (footprint "eagle-import:RES0402")
      (libsource (lib "eagle-import") (part "RESISTOR-0402"))
    )
    (comp (ref "R110")
      (value "DNP")
      (footprint "eagle-import:RES0402")
      (libsource (lib "eagle-import") (part "RESISTOR-0402"))
    )
    (comp (ref "R111")
      (value "0 Ohms")
      (footprint "eagle-import:RES0402")
      (libsource (lib "eagle-import") (part "RESISTOR-0402"))
    )
    (comp (ref "R112")
      (value "DNP")
      (footprint "eagle-import:RES0402")
      (libsource (lib "eagle-import") (part "RESISTOR-0402"))
    )
    (comp (ref "R113")
      (value "1K Ohms")
      (footprint "eagle-import:RES0402")
      (libsource (lib "eagle-import") (part "RESISTOR-0402"))
    )
    (comp (ref "R114")
      (value "22 Ohms")
      (footprint "eagle-import:RES0402")
      (libsource (lib "eagle-import") (part "RESISTOR-0402"))
    )
    (comp (ref "R115")
      (value "22 Ohms")
      (footprint "eagle-import:RES0402")
      (libsource (lib "eagle-import") (part "RESISTOR-0402"))
    )
    (comp (ref "R116")
      (value "2.2K Ohms")
      (footprint "eagle-import:RES0402")
      (libsource (lib "eagle-import") (part "RESISTOR-0402"))
    )
    (comp (ref "R117")
      (value "2.2K Ohms")
      (footprint "eagle-import:RES0402")
      (libsource (lib "eagle-import") (part "RESISTOR-0402"))
    )
    (comp (ref "R118")
      (value "220 Ohms")
      (footprint "eagle-import:RES0402")
      (libsource (lib "eagle-import") (part "RESISTOR-0402"))
    )
    (comp (ref "R119")
      (value "220 Ohms")
      (footprint "eagle-import:RES0402")
      (libsource (lib "eagle-import") (part "RESISTOR-0402"))
    )
    (comp (ref "R120")
      (value "2.2K Ohms")
      (footprint "eagle-import:RES0402")
      (libsource (lib "eagle-import") (part "RESISTOR-0402"))
    )
    (comp (ref "R121")
      (value "2.2K Ohms")
      (footprint "eagle-import:RES0402")
      (libsource (lib "eagle-import") (part "RESISTOR-0402"))
    )
    (comp (ref "RFCON101")
      (value "RFCON-U.FL")
      (footprint "eagle-import:U.FL")
      (libsource (lib "eagle-import") (part "RFCON-U.FL"))
    )
    (comp (ref "SD101")
      (value "MICRO-SD")
      (footprint "eagle-import:TE-2201778-1")
      (fields (field (name "MANUFACTURER") "TE Connectivity"))
      (libsource (lib "eagle-import") (part "MICRO-SD"))
    )
    (comp (ref "U101")
      (value "MIC2019")
      (footprint "eagle-import:SOT23-6")
      (libsource (lib "eagle-import") (part "MIC2091"))
    )
    (comp (ref "C601")
      (value "100nF")
      (footprint "eagle-import:CAP0402")
      (libsource (lib "eagle-import") (part "CAPACITOR-0402"))
    )
    (comp (ref "C602")
      (value "100nF")
      (footprint "eagle-import:CAP0402")
      (libsource (lib "eagle-import") (part "CAPACITOR-0402"))
    )
    (comp (ref "C603")
      (value "100nF")
      (footprint "eagle-import:CAP0402")
      (libsource (lib "eagle-import") (part "CAPACITOR-0402"))
    )
    (comp (ref "C604")
      (value "100nF")
      (footprint "eagle-import:CAP0402")
      (libsource (lib "eagle-import") (part "CAPACITOR-0402"))
    )
    (comp (ref "C605")
      (value "100nF")
      (footprint "eagle-import:CAP0402")
      (libsource (lib "eagle-import") (part "CAPACITOR-0402"))
    )
    (comp (ref "C606")
      (value "22uF")
      (footprint "eagle-import:CAP0402")
      (libsource (lib "eagle-import") (part "CAPACITOR-0402"))
    )
    (comp (ref "C607")
      (value "100nF")
      (footprint "eagle-import:CAP0402")
      (libsource (lib "eagle-import") (part "CAPACITOR-0402"))
    )
    (comp (ref "C608")
      (value "100nF")
      (footprint "eagle-import:CAP0402")
      (libsource (lib "eagle-import") (part "CAPACITOR-0402"))
    )
    (comp (ref "C609")
      (value "22uF")
      (footprint "eagle-import:CAP0402")
      (libsource (lib "eagle-import") (part "CAPACITOR-0402"))
    )
    (comp (ref "C610")
      (value "100nF")
      (footprint "eagle-import:CAP0402")
      (libsource (lib "eagle-import") (part "CAPACITOR-0402"))
    )
    (comp (ref "C611")
      (value "100nF")
      (footprint "eagle-import:CAP0402")
      (libsource (lib "eagle-import") (part "CAPACITOR-0402"))
    )
    (comp (ref "C612")
      (value "22uF")
      (footprint "eagle-import:CAP0402")
      (libsource (lib "eagle-import") (part "CAPACITOR-0402"))
    )
    (comp (ref "C613")
      (value "22uF")
      (footprint "eagle-import:CAP0402")
      (libsource (lib "eagle-import") (part "CAPACITOR-0402"))
    )
    (comp (ref "C614")
      (value "22uF")
      (footprint "eagle-import:CAP0402")
      (libsource (lib "eagle-import") (part "CAPACITOR-0402"))
    )
    (comp (ref "C615")
      (value "1uF")
      (footprint "eagle-import:CAP0402")
      (libsource (lib "eagle-import") (part "CAPACITOR-0402"))
    )
    (comp (ref "C616")
      (value "220nF")
      (footprint "eagle-import:CAP0402")
      (libsource (lib "eagle-import") (part "CAPACITOR-0402"))
    )
    (comp (ref "C617")
      (value "2.2nF")
      (footprint "eagle-import:CAP0402")
      (libsource (lib "eagle-import") (part "CAPACITOR-0402"))
    )
    (comp (ref "C618")
      (value "680pF")
      (footprint "eagle-import:CAP0402")
      (libsource (lib "eagle-import") (part "CAPACITOR-0402"))
    )
    (comp (ref "C619")
      (value "10nF")
      (footprint "eagle-import:CAP0402")
      (libsource (lib "eagle-import") (part "CAPACITOR-0402"))
    )
    (comp (ref "C620")
      (value "10nF")
      (footprint "eagle-import:CAP0402")
      (libsource (lib "eagle-import") (part "CAPACITOR-0402"))
    )
    (comp (ref "C621")
      (value "10pF")
      (footprint "eagle-import:CAP0402")
      (libsource (lib "eagle-import") (part "CAPACITOR-0402"))
    )
    (comp (ref "C622")
      (value "10pF")
      (footprint "eagle-import:CAP0402")
      (libsource (lib "eagle-import") (part "CAPACITOR-0402"))
    )
    (comp (ref "C623")
      (value "20pF")
      (footprint "eagle-import:CAP0402")
      (libsource (lib "eagle-import") (part "CAPACITOR-0402"))
    )
    (comp (ref "C624")
      (value "20pF")
      (footprint "eagle-import:CAP0402")
      (libsource (lib "eagle-import") (part "CAPACITOR-0402"))
    )
    (comp (ref "C625")
      (value "20pF")
      (footprint "eagle-import:CAP0402")
      (libsource (lib "eagle-import") (part "CAPACITOR-0402"))
    )
    (comp (ref "C626")
      (value "20pF")
      (footprint "eagle-import:CAP0402")
      (libsource (lib "eagle-import") (part "CAPACITOR-0402"))
    )
    (comp (ref "D601")
      (value "PGB1010402")
      (footprint "eagle-import:TVS0402")
      (libsource (lib "eagle-import") (part "PGB1010402"))
    )
    (comp (ref "D602")
      (value "PGB1010402")
      (footprint "eagle-import:TVS0402")
      (libsource (lib "eagle-import") (part "PGB1010402"))
    )
    (comp (ref "FB601")
      (value "1uH")
      (footprint "eagle-import:IND0603")
      (libsource (lib "eagle-import") (part "FERRITE-0603"))
    )
    (comp (ref "L601")
      (value "18nH")
      (footprint "eagle-import:IND0402")
      (libsource (lib "eagle-import") (part "INDUCTOR-0402"))
    )
    (comp (ref "L602")
      (value "18nH")
      (footprint "eagle-import:IND0402")
      (libsource (lib "eagle-import") (part "INDUCTOR-0402"))
    )
    (comp (ref "R601")
      (value "DNP")
      (footprint "eagle-import:RES0402")
      (libsource (lib "eagle-import") (part "RESISTOR-0402"))
    )
    (comp (ref "R602")
      (value "49.9 Ohms")
      (footprint "eagle-import:RES0402")
      (libsource (lib "eagle-import") (part "RESISTOR-0402"))
    )
    (comp (ref "R603")
      (value "1K Ohms")
      (footprint "eagle-import:RES0402")
      (libsource (lib "eagle-import") (part "RESISTOR-0402"))
    )
    (comp (ref "R604")
      (value "1K Ohms")
      (footprint "eagle-import:RES0402")
      (libsource (lib "eagle-import") (part "RESISTOR-0402"))
    )
    (comp (ref "R605")
      (value "1K Ohms")
      (footprint "eagle-import:RES0402")
      (libsource (lib "eagle-import") (part "RESISTOR-0402"))
    )
    (comp (ref "R606")
      (value "1K Ohms")
      (footprint "eagle-import:RES0402")
      (libsource (lib "eagle-import") (part "RESISTOR-0402"))
    )
    (comp (ref "R607")
      (value "1K Ohms")
      (footprint "eagle-import:RES0402")
      (libsource (lib "eagle-import") (part "RESISTOR-0402"))
    )
    (comp (ref "R608")
      (value "62 Ohms")
      (footprint "eagle-import:RES0402")
      (libsource (lib "eagle-import") (part "RESISTOR-0402"))
    )
    (comp (ref "R609")
      (value "20 Ohms")
      (footprint "eagle-import:RES0402")
      (libsource (lib "eagle-import") (part "RESISTOR-0402"))
    )
    (comp (ref "R610")
      (value "49.9 Ohms")
      (footprint "eagle-import:RES0402")
      (libsource (lib "eagle-import") (part "RESISTOR-0402"))
    )
    (comp (ref "R611")
      (value "49.9 Ohms")
      (footprint "eagle-import:RES0402")
      (libsource (lib "eagle-import") (part "RESISTOR-0402"))
    )
    (comp (ref "R612")
      (value "49.9 Ohms")
      (footprint "eagle-import:RES0402")
      (libsource (lib "eagle-import") (part "RESISTOR-0402"))
    )
    (comp (ref "R613")
      (value "49.9 Ohms")
      (footprint "eagle-import:RES0402")
      (libsource (lib "eagle-import") (part "RESISTOR-0402"))
    )
    (comp (ref "R614")
      (value "49.9 Ohms")
      (footprint "eagle-import:RES0402")
      (libsource (lib "eagle-import") (part "RESISTOR-0402"))
    )
    (comp (ref "R615")
      (value "49.9 Ohms")
      (footprint "eagle-import:RES0402")
      (libsource (lib "eagle-import") (part "RESISTOR-0402"))
    )
    (comp (ref "RFCON601")
      (value "RFCON-SMA")
      (footprint "eagle-import:SMA")
      (libsource (lib "eagle-import") (part "RFCON-SMA"))
    )
    (comp (ref "RFCON602")
      (value "RFCON-SMA")
      (footprint "eagle-import:SMA")
      (libsource (lib "eagle-import") (part "RFCON-SMA"))
    )
    (comp (ref "SHIELD601")
      (value "SHIELD-TE-2118728")
      (footprint "eagle-import:2118728")
      (libsource (lib "eagle-import") (part "SHIELD-TE-2118728"))
    )
    (comp (ref "U601")
      (value "8V97003")
      (footprint "eagle-import:VFQFPN48")
      (libsource (lib "eagle-import") (part "8V97003"))
    )
  )
  (nets
    (net (code "1") (name "0V675_DDR3_VREF") (class "Default")
      (node (ref "C1234") (pin "1") (pinfunction "C1_1") (pintype "passive"))
      (node (ref "C305") (pin "1") (pinfunction "C1_1") (pintype "passive"))
      (node (ref "C308") (pin "1") (pinfunction "C1_1") (pintype "passive"))
      (node (ref "C313") (pin "1") (pinfunction "C1_1") (pintype "passive"))
      (node (ref "C316") (pin "1") (pinfunction "C1_1") (pintype "passive"))
      (node (ref "C318") (pin "1") (pinfunction "C1_1") (pintype "passive"))
      (node (ref "C320") (pin "1") (pinfunction "C1_1") (pintype "passive"))
      (node (ref "U1205") (pin "1") (pinfunction "VREF_1") (pintype "bidirectional"))
      (node (ref "U201") (pin "E3") (pinfunction "IO_L6N/T0/VREF_E3") (pintype "bidirectional"))
      (node (ref "U201") (pin "N3") (pinfunction "IO_L19N/T3/VREF_N3") (pintype "bidirectional"))
      (node (ref "U201") (pin "V3") (pinfunction "IO_L6N/T0/VREF_V3") (pintype "bidirectional"))
      (node (ref "U201") (pin "W7") (pinfunction "IO_L19N/T3/VREF_W7") (pintype "bidirectional"))
      (node (ref "U301") (pin "H1") (pinfunction "VREFDQ_H1") (pintype "bidirectional"))
      (node (ref "U301") (pin "M8") (pinfunction "VREFCA_M8") (pintype "bidirectional"))
    )
    (net (code "2") (name "0V675_DDR3_VTT") (class "Default")
      (node (ref "C1235") (pin "1") (pinfunction "C1_1") (pintype "passive"))
      (node (ref "C1238") (pin "1") (pinfunction "C1_1") (pintype "passive"))
      (node (ref "C323") (pin "2") (pinfunction "C2_2") (pintype "passive"))
      (node (ref "C324") (pin "1") (pinfunction "C1_1") (pintype "passive"))
      (node (ref "C325") (pin "1") (pinfunction "C1_1") (pintype "passive"))
      (node (ref "C326") (pin "1") (pinfunction "C1_1") (pintype "passive"))
      (node (ref "C327") (pin "1") (pinfunction "C1_1") (pintype "passive"))
      (node (ref "C328") (pin "1") (pinfunction "C1_1") (pintype "passive"))
      (node (ref "C329") (pin "1") (pinfunction "C1_1") (pintype "passive"))
      (node (ref "C330") (pin "1") (pinfunction "C1_1") (pintype "passive"))
      (node (ref "C331") (pin "1") (pinfunction "C1_1") (pintype "passive"))
      (node (ref "R303") (pin "1") (pinfunction "1_1") (pintype "passive"))
      (node (ref "R304") (pin "1") (pinfunction "1_1") (pintype "passive"))
      (node (ref "R305") (pin "1") (pinfunction "1_1") (pintype "passive"))
      (node (ref "R306") (pin "1") (pinfunction "1_1") (pintype "passive"))
      (node (ref "R307") (pin "1") (pinfunction "1_1") (pintype "passive"))
      (node (ref "R308") (pin "1") (pinfunction "1_1") (pintype "passive"))
      (node (ref "R309") (pin "1") (pinfunction "1_1") (pintype "passive"))
      (node (ref "R310") (pin "1") (pinfunction "1_1") (pintype "passive"))
      (node (ref "R312") (pin "1") (pinfunction "1_1") (pintype "passive"))
      (node (ref "R313") (pin "1") (pinfunction "1_1") (pintype "passive"))
      (node (ref "R314") (pin "1") (pinfunction "1_1") (pintype "passive"))
      (node (ref "R315") (pin "1") (pinfunction "1_1") (pintype "passive"))
      (node (ref "R316") (pin "1") (pinfunction "1_1") (pintype "passive"))
      (node (ref "R317") (pin "1") (pinfunction "1_1") (pintype "passive"))
      (node (ref "R318") (pin "1") (pinfunction "1_1") (pintype "passive"))
      (node (ref "R320") (pin "2") (pinfunction "2_2") (pintype "passive"))
      (node (ref "R321") (pin "2") (pinfunction "2_2") (pintype "passive"))
      (node (ref "R322") (pin "2") (pinfunction "2_2") (pintype "passive"))
      (node (ref "R323") (pin "2") (pinfunction "2_2") (pintype "passive"))
      (node (ref "R324") (pin "2") (pinfunction "2_2") (pintype "passive"))
      (node (ref "R325") (pin "2") (pinfunction "2_2") (pintype "passive"))
      (node (ref "R326") (pin "2") (pinfunction "2_2") (pintype "passive"))
      (node (ref "R327") (pin "2") (pinfunction "2_2") (pintype "passive"))
      (node (ref "R328") (pin "2") (pinfunction "2_2") (pintype "passive"))
      (node (ref "U1205") (pin "6") (pinfunction "SNS_6") (pintype "bidirectional"))
      (node (ref "U1205") (pin "9") (pinfunction "VTT_9") (pintype "bidirectional"))
    )
    (net (code "3") (name "1V0") (class "Default")
      (node (ref "C1123") (pin "1") (pinfunction "C1_1") (pintype "passive"))
      (node (ref "C1125") (pin "1") (pinfunction "C1_1") (pintype "passive"))
      (node (ref "C1128") (pin "1") (pinfunction "C1_1") (pintype "passive"))
      (node (ref "C1130") (pin "1") (pinfunction "C1_1") (pintype "passive"))
      (node (ref "C201") (pin "1") (pinfunction "C1_1") (pintype "passive"))
      (node (ref "C202") (pin "1") (pinfunction "C1_1") (pintype "passive"))
      (node (ref "C206") (pin "1") (pinfunction "C1_1") (pintype "passive"))
      (node (ref "C211") (pin "1") (pinfunction "C1_1") (pintype "passive"))
      (node (ref "C216") (pin "1") (pinfunction "C1_1") (pintype "passive"))
      (node (ref "C221") (pin "1") (pinfunction "C1_1") (pintype "passive"))
      (node (ref "C226") (pin "1") (pinfunction "C1_1") (pintype "passive"))
      (node (ref "C231") (pin "1") (pinfunction "C1_1") (pintype "passive"))
      (node (ref "C236") (pin "1") (pinfunction "C1_1") (pintype "passive"))
      (node (ref "C241") (pin "1") (pinfunction "C1_1") (pintype "passive"))
      (node (ref "C246") (pin "1") (pinfunction "C1_1") (pintype "passive"))
      (node (ref "C251") (pin "1") (pinfunction "C1_1") (pintype "passive"))
      (node (ref "C256") (pin "1") (pinfunction "C1_1") (pintype "passive"))
      (node (ref "C261") (pin "1") (pinfunction "C1_1") (pintype "passive"))
      (node (ref "C262") (pin "1") (pinfunction "C1_1") (pintype "passive"))
      (node (ref "C263") (pin "1") (pinfunction "C1_1") (pintype "passive"))
      (node (ref "L1102") (pin "2") (pinfunction "2_2") (pintype "passive"))
      (node (ref "U1102") (pin "11") (pinfunction "VSENSEP_11") (pintype "bidirectional"))
      (node (ref "U201") (pin "D10") (pinfunction "MGTAVCC_D10") (pintype "bidirectional"))
      (node (ref "U201") (pin "D6") (pinfunction "MGTAVCC_D6") (pintype "bidirectional"))
      (node (ref "U201") (pin "E8") (pinfunction "MGTAVCC_E8") (pintype "bidirectional"))
      (node (ref "U201") (pin "F7") (pinfunction "MGTAVCC_F7") (pintype "bidirectional"))
      (node (ref "U201") (pin "F9") (pinfunction "MGTAVCC_F9") (pintype "bidirectional"))
      (node (ref "U201") (pin "H10") (pinfunction "VCCINT_H10") (pintype "bidirectional"))
      (node (ref "U201") (pin "H8") (pinfunction "VCCINT_H8") (pintype "bidirectional"))
      (node (ref "U201") (pin "J11") (pinfunction "VCCBRAM_J11") (pintype "bidirectional"))
      (node (ref "U201") (pin "J7") (pinfunction "VCCINT_J7") (pintype "bidirectional"))
      (node (ref "U201") (pin "J9") (pinfunction "VCCINT_J9") (pintype "bidirectional"))
      (node (ref "U201") (pin "K8") (pinfunction "VCCINT_K8") (pintype "bidirectional"))
      (node (ref "U201") (pin "L11") (pinfunction "VCCBRAM_L11") (pintype "bidirectional"))
      (node (ref "U201") (pin "L7") (pinfunction "VCCINT_L7") (pintype "bidirectional"))
      (node (ref "U201") (pin "M8") (pinfunction "VCCINT_M8") (pintype "bidirectional"))
      (node (ref "U201") (pin "N11") (pinfunction "VCCBRAM_N11") (pintype "bidirectional"))
      (node (ref "U201") (pin "N7") (pinfunction "VCCINT_N7") (pintype "bidirectional"))
      (node (ref "U201") (pin "P10") (pinfunction "VCCINT_P10") (pintype "bidirectional"))
      (node (ref "U201") (pin "P8") (pinfunction "VCCINT_P8") (pintype "bidirectional"))
      (node (ref "U201") (pin "R7") (pinfunction "VCCINT_R7") (pintype "bidirectional"))
      (node (ref "U201") (pin "R9") (pinfunction "VCCINT_R9") (pintype "bidirectional"))
      (node (ref "U201") (pin "T10") (pinfunction "VCCINT_T10") (pintype "bidirectional"))
      (node (ref "U201") (pin "T8") (pinfunction "VCCINT_T8") (pintype "bidirectional"))
    )
    (net (code "4") (name "1V0_PGOOD") (class "Default")
      (node (ref "R1122") (pin "1") (pinfunction "1_1") (pintype "passive"))
      (node (ref "TP2") (pin "TP") (pinfunction "TP_TP") (pintype "input"))
      (node (ref "U1102") (pin "32") (pinfunction "PGOOD_32") (pintype "bidirectional"))
      (node (ref "U1209") (pin "2") (pinfunction "EN_2") (pintype "bidirectional"))
    )
    (net (code "5") (name "1V2") (class "Default")
      (node (ref "C1257") (pin "1") (pinfunction "C1_1") (pintype "passive"))
      (node (ref "C1259") (pin "1") (pinfunction "C1_1") (pintype "passive"))
      (node (ref "C242") (pin "1") (pinfunction "C1_1") (pintype "passive"))
      (node (ref "C247") (pin "1") (pinfunction "C1_1") (pintype "passive"))
      (node (ref "C252") (pin "1") (pinfunction "C1_1") (pintype "passive"))
      (node (ref "C257") (pin "1") (pinfunction "C1_1") (pintype "passive"))
      (node (ref "L1205") (pin "2") (pinfunction "2_2") (pintype "passive"))
      (node (ref "R1214") (pin "2") (pinfunction "2_2") (pintype "passive"))
      (node (ref "R210") (pin "2") (pinfunction "2_2") (pintype "passive"))
      (node (ref "U1209") (pin "3") (pinfunction "SNS_3") (pintype "bidirectional"))
      (node (ref "U201") (pin "B11") (pinfunction "MGTAVTT_B11") (pintype "bidirectional"))
      (node (ref "U201") (pin "B5") (pinfunction "MGTAVTT_B5") (pintype "bidirectional"))
      (node (ref "U201") (pin "B7") (pinfunction "MGTAVTT_B7") (pintype "bidirectional"))
      (node (ref "U201") (pin "B9") (pinfunction "MGTAVTT_B9") (pintype "bidirectional"))
      (node (ref "U201") (pin "C4") (pinfunction "MGTAVTT_C4") (pintype "bidirectional"))
      (node (ref "U201") (pin "C8") (pinfunction "MGTAVTT_C8") (pintype "bidirectional"))
    )
    (net (code "6") (name "1V2_PGOOD") (class "Default")
      (node (ref "R1210") (pin "1") (pinfunction "1_1") (pintype "passive"))
      (node (ref "TP3") (pin "TP") (pinfunction "TP_TP") (pintype "input"))
      (node (ref "U1204") (pin "9") (pinfunction "EN_9") (pintype "bidirectional"))
      (node (ref "U1208") (pin "18") (pinfunction "EN_18") (pintype "bidirectional"))
      (node (ref "U1208") (pin "9") (pinfunction "EN_9") (pintype "bidirectional"))
      (node (ref "U1209") (pin "5") (pinfunction "PG_5") (pintype "bidirectional"))
    )
    (net (code "7") (name "1V3_TRX") (class "Default")
      (node (ref "C1236") (pin "1") (pinfunction "C1_1") (pintype "passive"))
      (node (ref "C1240") (pin "1") (pinfunction "C1_1") (pintype "passive"))
      (node (ref "C1243") (pin "1") (pinfunction "C1_1") (pintype "passive"))
      (node (ref "C1244") (pin "1") (pinfunction "C1_1") (pintype "passive"))
      (node (ref "C404") (pin "1") (pinfunction "C1_1") (pintype "passive"))
      (node (ref "C407") (pin "1") (pinfunction "C1_1") (pintype "passive"))
      (node (ref "C410") (pin "1") (pinfunction "C1_1") (pintype "passive"))
      (node (ref "C413") (pin "1") (pinfunction "C1_1") (pintype "passive"))
      (node (ref "C416") (pin "1") (pinfunction "C1_1") (pintype "passive"))
      (node (ref "C419") (pin "1") (pinfunction "C1_1") (pintype "passive"))
      (node (ref "C523") (pin "1") (pinfunction "C1_1") (pintype "passive"))
      (node (ref "C524") (pin "1") (pinfunction "C1_1") (pintype "passive"))
      (node (ref "C525") (pin "1") (pinfunction "C1_1") (pintype "passive"))
      (node (ref "C526") (pin "1") (pinfunction "C1_1") (pintype "passive"))
      (node (ref "C527") (pin "1") (pinfunction "C1_1") (pintype "passive"))
      (node (ref "C528") (pin "1") (pinfunction "C1_1") (pintype "passive"))
      (node (ref "C534") (pin "1") (pinfunction "C1_1") (pintype "passive"))
      (node (ref "C535") (pin "1") (pinfunction "C1_1") (pintype "passive"))
      (node (ref "C536") (pin "1") (pinfunction "C1_1") (pintype "passive"))
      (node (ref "C537") (pin "1") (pinfunction "C1_1") (pintype "passive"))
      (node (ref "C540") (pin "1") (pinfunction "C1_1") (pintype "passive"))
      (node (ref "C541") (pin "1") (pinfunction "C1_1") (pintype "passive"))
      (node (ref "L503") (pin "1") (pinfunction "1_1") (pintype "passive"))
      (node (ref "L504") (pin "1") (pinfunction "1_1") (pintype "passive"))
      (node (ref "L505") (pin "1") (pinfunction "1_1") (pintype "passive"))
      (node (ref "L506") (pin "1") (pinfunction "1_1") (pintype "passive"))
      (node (ref "L507") (pin "1") (pinfunction "1_1") (pintype "passive"))
      (node (ref "L508") (pin "1") (pinfunction "1_1") (pintype "passive"))
      (node (ref "L509") (pin "1") (pinfunction "1_1") (pintype "passive"))
      (node (ref "L510") (pin "1") (pinfunction "1_1") (pintype "passive"))
      (node (ref "U1206") (pin "1") (pinfunction "VOUT_1") (pintype "bidirectional"))
      (node (ref "U1206") (pin "2") (pinfunction "VOUT_2") (pintype "bidirectional"))
      (node (ref "U1206") (pin "3") (pinfunction "SENSE_3") (pintype "bidirectional"))
      (node (ref "U401") (pin "D2") (pinfunction "VDDA1P3_RX_RF_D2") (pintype "bidirectional"))
      (node (ref "U401") (pin "D3") (pinfunction "VDDA1P3_RX_TX_D3") (pintype "bidirectional"))
      (node (ref "U401") (pin "E3") (pinfunction "VDDA1P3_TX_LO_BUFFER_E3") (pintype "bidirectional"))
      (node (ref "U401") (pin "F12") (pinfunction "VDDD1P3_DIG_F12") (pintype "bidirectional"))
      (node (ref "U401") (pin "K4") (pinfunction "VDDA1P3_BB_K4") (pintype "bidirectional"))
    )
    (net (code "8") (name "1V3_TRX_LO_SYNTH") (class "Default")
      (node (ref "C1213") (pin "1") (pinfunction "C1_1") (pintype "passive"))
      (node (ref "C1216") (pin "1") (pinfunction "C1_1") (pintype "passive"))
      (node (ref "C1218") (pin "1") (pinfunction "C1_1") (pintype "passive"))
      (node (ref "C1219") (pin "1") (pinfunction "C1_1") (pintype "passive"))
      (node (ref "C405") (pin "1") (pinfunction "C1_1") (pintype "passive"))
      (node (ref "C408") (pin "1") (pinfunction "C1_1") (pintype "passive"))
      (node (ref "C411") (pin "1") (pinfunction "C1_1") (pintype "passive"))
      (node (ref "C414") (pin "1") (pinfunction "C1_1") (pintype "passive"))
      (node (ref "C417") (pin "1") (pinfunction "C1_1") (pintype "passive"))
      (node (ref "C420") (pin "1") (pinfunction "C1_1") (pintype "passive"))
      (node (ref "U1202") (pin "1") (pinfunction "VOUT_1") (pintype "bidirectional"))
      (node (ref "U1202") (pin "2") (pinfunction "VOUT_2") (pintype "bidirectional"))
      (node (ref "U1202") (pin "3") (pinfunction "SENSE_3") (pintype "bidirectional"))
      (node (ref "U401") (pin "B10") (pinfunction "VDDA1P3_TX_VCO_LDO_B10") (pintype "bidirectional"))
      (node (ref "U401") (pin "B9") (pinfunction "VDDA1P3_TX_LO_B9") (pintype "bidirectional"))
      (node (ref "U401") (pin "E2") (pinfunction "VDDA1P3_RX_LO_E2") (pintype "bidirectional"))
      (node (ref "U401") (pin "F2") (pinfunction "VDDA1P3_RX_VCO_LDO_F2") (pintype "bidirectional"))
      (node (ref "U401") (pin "J3") (pinfunction "VDDA1P3_RX_SYNTH_J3") (pintype "bidirectional"))
      (node (ref "U401") (pin "K3") (pinfunction "VDDA1P3_TX_SYNTH_K3") (pintype "bidirectional"))
    )
    (net (code "9") (name "1V8") (class "Default")
      (node (ref "C1226") (pin "1") (pinfunction "C1_1") (pintype "passive"))
      (node (ref "C1227") (pin "1") (pinfunction "C1_1") (pintype "passive"))
      (node (ref "C207") (pin "1") (pinfunction "C1_1") (pintype "passive"))
      (node (ref "C212") (pin "1") (pinfunction "C1_1") (pintype "passive"))
      (node (ref "C217") (pin "1") (pinfunction "C1_1") (pintype "passive"))
      (node (ref "C222") (pin "1") (pinfunction "C1_1") (pintype "passive"))
      (node (ref "C227") (pin "1") (pinfunction "C1_1") (pintype "passive"))
      (node (ref "C232") (pin "1") (pinfunction "C1_1") (pintype "passive"))
      (node (ref "L1202") (pin "2") (pinfunction "2_2") (pintype "passive"))
      (node (ref "R1204") (pin "2") (pinfunction "2_2") (pintype "passive"))
      (node (ref "R1205") (pin "2") (pinfunction "2_2") (pintype "passive"))
      (node (ref "U1204") (pin "10") (pinfunction "SNS_10") (pintype "bidirectional"))
      (node (ref "U201") (pin "E12") (pinfunction "VCCBATT_E12") (pintype "bidirectional"))
      (node (ref "U201") (pin "H12") (pinfunction "VCCAUX_H12") (pintype "bidirectional"))
      (node (ref "U201") (pin "K10") (pinfunction "VCCADC_K10") (pintype "bidirectional"))
      (node (ref "U201") (pin "K12") (pinfunction "VCCAUX_K12") (pintype "bidirectional"))
      (node (ref "U201") (pin "M12") (pinfunction "VCCAUX_M12") (pintype "bidirectional"))
      (node (ref "U201") (pin "P12") (pinfunction "VCCAUX_P12") (pintype "bidirectional"))
      (node (ref "U201") (pin "R11") (pinfunction "VCCAUX_R11") (pintype "bidirectional"))
    )
    (net (code "10") (name "1V8_CM4") (class "Default")
      (node (ref "U102") (pin "88") (pinfunction "1V8_OUT_88") (pintype "bidirectional"))
      (node (ref "U102") (pin "90") (pinfunction "1V8_OUT_90") (pintype "bidirectional"))
    )
    (net (code "11") (name "1V8_PGOOD") (class "Default")
      (node (ref "R1204") (pin "1") (pinfunction "1_1") (pintype "passive"))
      (node (ref "TP4") (pin "TP") (pinfunction "TP_TP") (pintype "input"))
      (node (ref "U1204") (pin "12") (pinfunction "PG_12") (pintype "bidirectional"))
      (node (ref "U1204") (pin "18") (pinfunction "EN_18") (pintype "bidirectional"))
    )
    (net (code "12") (name "1V35") (class "Default")
      (node (ref "C1209") (pin "1") (pinfunction "C1_1") (pintype "passive"))
      (node (ref "C1210") (pin "1") (pinfunction "C1_1") (pintype "passive"))
      (node (ref "C1220") (pin "1") (pinfunction "C1_1") (pintype "passive"))
      (node (ref "C1224") (pin "1") (pinfunction "C1_1") (pintype "passive"))
      (node (ref "C205") (pin "1") (pinfunction "C1_1") (pintype "passive"))
      (node (ref "C210") (pin "1") (pinfunction "C1_1") (pintype "passive"))
      (node (ref "C215") (pin "1") (pinfunction "C1_1") (pintype "passive"))
      (node (ref "C220") (pin "1") (pinfunction "C1_1") (pintype "passive"))
      (node (ref "C225") (pin "1") (pinfunction "C1_1") (pintype "passive"))
      (node (ref "C230") (pin "1") (pinfunction "C1_1") (pintype "passive"))
      (node (ref "C235") (pin "1") (pinfunction "C1_1") (pintype "passive"))
      (node (ref "C240") (pin "1") (pinfunction "C1_1") (pintype "passive"))
      (node (ref "C245") (pin "1") (pinfunction "C1_1") (pintype "passive"))
      (node (ref "C250") (pin "1") (pinfunction "C1_1") (pintype "passive"))
      (node (ref "C255") (pin "1") (pinfunction "C1_1") (pintype "passive"))
      (node (ref "C260") (pin "1") (pinfunction "C1_1") (pintype "passive"))
      (node (ref "C301") (pin "1") (pinfunction "C1_1") (pintype "passive"))
      (node (ref "C302") (pin "1") (pinfunction "C1_1") (pintype "passive"))
      (node (ref "C303") (pin "1") (pinfunction "C1_1") (pintype "passive"))
      (node (ref "C304") (pin "1") (pinfunction "C1_1") (pintype "passive"))
      (node (ref "C306") (pin "1") (pinfunction "C1_1") (pintype "passive"))
      (node (ref "C307") (pin "1") (pinfunction "C1_1") (pintype "passive"))
      (node (ref "C309") (pin "1") (pinfunction "C1_1") (pintype "passive"))
      (node (ref "C310") (pin "1") (pinfunction "C1_1") (pintype "passive"))
      (node (ref "C311") (pin "1") (pinfunction "C1_1") (pintype "passive"))
      (node (ref "C312") (pin "1") (pinfunction "C1_1") (pintype "passive"))
      (node (ref "C314") (pin "1") (pinfunction "C1_1") (pintype "passive"))
      (node (ref "C315") (pin "1") (pinfunction "C1_1") (pintype "passive"))
      (node (ref "C317") (pin "1") (pinfunction "C1_1") (pintype "passive"))
      (node (ref "C319") (pin "1") (pinfunction "C1_1") (pintype "passive"))
      (node (ref "C321") (pin "1") (pinfunction "C1_1") (pintype "passive"))
      (node (ref "C322") (pin "1") (pinfunction "C1_1") (pintype "passive"))
      (node (ref "L1201") (pin "1") (pinfunction "1_1") (pintype "passive"))
      (node (ref "R1201") (pin "2") (pinfunction "2_2") (pintype "passive"))
      (node (ref "R1202") (pin "2") (pinfunction "2_2") (pintype "passive"))
      (node (ref "U1204") (pin "17") (pinfunction "SNS_17") (pintype "bidirectional"))
      (node (ref "U1205") (pin "10") (pinfunction "VIN_10") (pintype "bidirectional"))
      (node (ref "U1205") (pin "4") (pinfunction "VDDQ_4") (pintype "bidirectional"))
      (node (ref "U201") (pin "AA7") (pinfunction "VCCO_34_AA7") (pintype "bidirectional"))
      (node (ref "U201") (pin "AB4") (pinfunction "VCCO_34_AB4") (pintype "bidirectional"))
      (node (ref "U201") (pin "C1") (pinfunction "VCCO_35_C1") (pintype "bidirectional"))
      (node (ref "U201") (pin "F2") (pinfunction "VCCO_35_F2") (pintype "bidirectional"))
      (node (ref "U201") (pin "H6") (pinfunction "VCCO_35_H6") (pintype "bidirectional"))
      (node (ref "U201") (pin "J3") (pinfunction "VCCO_35_J3") (pintype "bidirectional"))
      (node (ref "U201") (pin "M4") (pinfunction "VCCO_35_M4") (pintype "bidirectional"))
      (node (ref "U201") (pin "N1") (pinfunction "VCCO_35_N1") (pintype "bidirectional"))
      (node (ref "U201") (pin "R5") (pinfunction "VCCO_34_R5") (pintype "bidirectional"))
      (node (ref "U201") (pin "T2") (pinfunction "VCCO_34_T2") (pintype "bidirectional"))
      (node (ref "U201") (pin "V6") (pinfunction "VCCO_34_V6") (pintype "bidirectional"))
      (node (ref "U201") (pin "W3") (pinfunction "VCCO_34_W3") (pintype "bidirectional"))
      (node (ref "U301") (pin "A1") (pinfunction "VDDQ_A1") (pintype "bidirectional"))
      (node (ref "U301") (pin "A8") (pinfunction "VDDQ_A8") (pintype "bidirectional"))
      (node (ref "U301") (pin "B2") (pinfunction "VDD_B2") (pintype "bidirectional"))
      (node (ref "U301") (pin "C1") (pinfunction "VDDQ_C1") (pintype "bidirectional"))
      (node (ref "U301") (pin "C9") (pinfunction "VDDQ_C9") (pintype "bidirectional"))
      (node (ref "U301") (pin "D2") (pinfunction "VDDQ_D2") (pintype "bidirectional"))
      (node (ref "U301") (pin "D9") (pinfunction "VDD_D9") (pintype "bidirectional"))
      (node (ref "U301") (pin "E9") (pinfunction "VDDQ_E9") (pintype "bidirectional"))
      (node (ref "U301") (pin "F1") (pinfunction "VDDQ_F1") (pintype "bidirectional"))
      (node (ref "U301") (pin "G7") (pinfunction "VDD_G7") (pintype "bidirectional"))
      (node (ref "U301") (pin "H2") (pinfunction "VDDQ_H2") (pintype "bidirectional"))
      (node (ref "U301") (pin "H9") (pinfunction "VDDQ_H9") (pintype "bidirectional"))
      (node (ref "U301") (pin "K2") (pinfunction "VDD_K2") (pintype "bidirectional"))
      (node (ref "U301") (pin "K8") (pinfunction "VDD_K8") (pintype "bidirectional"))
      (node (ref "U301") (pin "N1") (pinfunction "VDD_N1") (pintype "bidirectional"))
      (node (ref "U301") (pin "N9") (pinfunction "VDD_N9") (pintype "bidirectional"))
      (node (ref "U301") (pin "R1") (pinfunction "VDD_R1") (pintype "bidirectional"))
      (node (ref "U301") (pin "R9") (pinfunction "VDD_R9") (pintype "bidirectional"))
    )
    (net (code "13") (name "1V35_PGOOD") (class "Default")
      (node (ref "R1201") (pin "1") (pinfunction "1_1") (pintype "passive"))
      (node (ref "TP7") (pin "TP") (pinfunction "TP_TP") (pintype "input"))
      (node (ref "U1204") (pin "15") (pinfunction "PG_15") (pintype "bidirectional"))
      (node (ref "U1205") (pin "7") (pinfunction "EN_7") (pintype "bidirectional"))
    )
    (net (code "14") (name "2V5") (class "Default")
      (node (ref "C1203") (pin "1") (pinfunction "C1_1") (pintype "passive"))
      (node (ref "C1222") (pin "1") (pinfunction "C1_1") (pintype "passive"))
      (node (ref "C1228") (pin "1") (pinfunction "C1_1") (pintype "passive"))
      (node (ref "C1245") (pin "1") (pinfunction "C1_1") (pintype "passive"))
      (node (ref "C1246") (pin "1") (pinfunction "C1_1") (pintype "passive"))
      (node (ref "C204") (pin "1") (pinfunction "C1_1") (pintype "passive"))
      (node (ref "C209") (pin "1") (pinfunction "C1_1") (pintype "passive"))
      (node (ref "C214") (pin "1") (pinfunction "C1_1") (pintype "passive"))
      (node (ref "C219") (pin "1") (pinfunction "C1_1") (pintype "passive"))
      (node (ref "C224") (pin "1") (pinfunction "C1_1") (pintype "passive"))
      (node (ref "C229") (pin "1") (pinfunction "C1_1") (pintype "passive"))
      (node (ref "C234") (pin "1") (pinfunction "C1_1") (pintype "passive"))
      (node (ref "C239") (pin "1") (pinfunction "C1_1") (pintype "passive"))
      (node (ref "C244") (pin "1") (pinfunction "C1_1") (pintype "passive"))
      (node (ref "C249") (pin "1") (pinfunction "C1_1") (pintype "passive"))
      (node (ref "C254") (pin "1") (pinfunction "C1_1") (pintype "passive"))
      (node (ref "C259") (pin "1") (pinfunction "C1_1") (pintype "passive"))
      (node (ref "C401") (pin "1") (pinfunction "C1_1") (pintype "passive"))
      (node (ref "FB401") (pin "1") (pinfunction "1_1") (pintype "passive"))
      (node (ref "JP1101") (pin "6") (pinfunction "S_6") (pintype "passive"))
      (node (ref "L1203") (pin "1") (pinfunction "1_1") (pintype "passive"))
      (node (ref "R1207") (pin "2") (pinfunction "2_2") (pintype "passive"))
      (node (ref "R1208") (pin "2") (pinfunction "2_2") (pintype "passive"))
      (node (ref "R503") (pin "2") (pinfunction "2_2") (pintype "passive"))
      (node (ref "R504") (pin "2") (pinfunction "2_2") (pintype "passive"))
      (node (ref "R509") (pin "2") (pinfunction "2_2") (pintype "passive"))
      (node (ref "R510") (pin "2") (pinfunction "2_2") (pintype "passive"))
      (node (ref "U1202") (pin "7") (pinfunction "VIN_7") (pintype "bidirectional"))
      (node (ref "U1202") (pin "8") (pinfunction "VIN_8") (pintype "bidirectional"))
      (node (ref "U1206") (pin "7") (pinfunction "VIN_7") (pintype "bidirectional"))
      (node (ref "U1206") (pin "8") (pinfunction "VIN_8") (pintype "bidirectional"))
      (node (ref "U1208") (pin "17") (pinfunction "SNS_17") (pintype "bidirectional"))
      (node (ref "U201") (pin "A17") (pinfunction "VCCO_16_A17") (pintype "bidirectional"))
      (node (ref "U201") (pin "B14") (pinfunction "VCCO_16_B14") (pintype "bidirectional"))
      (node (ref "U201") (pin "C21") (pinfunction "VCCO_16_C21") (pintype "bidirectional"))
      (node (ref "U201") (pin "D18") (pinfunction "VCCO_16_D18") (pintype "bidirectional"))
      (node (ref "U201") (pin "E15") (pinfunction "VCCO_16_E15") (pintype "bidirectional"))
      (node (ref "U201") (pin "F20") (pinfunction "IO_L18N/T2_F20") (pintype "bidirectional"))
      (node (ref "U201") (pin "F21") (pinfunction "IO_25_F21") (pintype "bidirectional"))
      (node (ref "U201") (pin "F22") (pinfunction "VCCO_16_F22") (pintype "bidirectional"))
      (node (ref "U201") (pin "G19") (pinfunction "VCCO_15_G19") (pintype "bidirectional"))
      (node (ref "U201") (pin "H16") (pinfunction "VCCO_15_H16") (pintype "bidirectional"))
      (node (ref "U201") (pin "J13") (pinfunction "VCCO_15_J13") (pintype "bidirectional"))
      (node (ref "U201") (pin "K20") (pinfunction "VCCO_15_K20") (pintype "bidirectional"))
      (node (ref "U201") (pin "L17") (pinfunction "VCCO_15_L17") (pintype "bidirectional"))
      (node (ref "U201") (pin "N21") (pinfunction "VCCO_15_N21") (pintype "bidirectional"))
    )
    (net (code "15") (name "2V5_PGOOD") (class "Default")
      (node (ref "R1207") (pin "1") (pinfunction "1_1") (pintype "passive"))
      (node (ref "TP5") (pin "TP") (pinfunction "TP_TP") (pintype "input"))
      (node (ref "U1202") (pin "5") (pinfunction "EN_5") (pintype "bidirectional"))
      (node (ref "U1206") (pin "5") (pinfunction "EN_5") (pintype "bidirectional"))
      (node (ref "U1208") (pin "15") (pinfunction "PG_15") (pintype "bidirectional"))
    )
    (net (code "16") (name "3V0_VIN_REG_INTVCC") (class "Default")
      (node (ref "C1114") (pin "1") (pinfunction "C1_1") (pintype "passive"))
      (node (ref "U1102") (pin "4") (pinfunction "ITH_4") (pintype "bidirectional"))
      (node (ref "U1102") (pin "5") (pinfunction "ITH_5") (pintype "bidirectional"))
      (node (ref "U1102") (pin "6") (pinfunction "INTVCC_6") (pintype "bidirectional"))
    )
    (net (code "17") (name "3V3") (class "Default")
      (node (ref "C1005") (pin "1") (pinfunction "C1_1") (pintype "passive"))
      (node (ref "C1253") (pin "1") (pinfunction "C1_1") (pintype "passive"))
      (node (ref "C1254") (pin "1") (pinfunction "C1_1") (pintype "passive"))
      (node (ref "C203") (pin "1") (pinfunction "C1_1") (pintype "passive"))
      (node (ref "C208") (pin "1") (pinfunction "C1_1") (pintype "passive"))
      (node (ref "C213") (pin "1") (pinfunction "C1_1") (pintype "passive"))
      (node (ref "C218") (pin "1") (pinfunction "C1_1") (pintype "passive"))
      (node (ref "C223") (pin "1") (pinfunction "C1_1") (pintype "passive"))
      (node (ref "C228") (pin "1") (pinfunction "C1_1") (pintype "passive"))
      (node (ref "C233") (pin "1") (pinfunction "C1_1") (pintype "passive"))
      (node (ref "C237") (pin "1") (pinfunction "C1_1") (pintype "passive"))
      (node (ref "C238") (pin "1") (pinfunction "C1_1") (pintype "passive"))
      (node (ref "C243") (pin "1") (pinfunction "C1_1") (pintype "passive"))
      (node (ref "C248") (pin "1") (pinfunction "C1_1") (pintype "passive"))
      (node (ref "C253") (pin "1") (pinfunction "C1_1") (pintype "passive"))
      (node (ref "C258") (pin "1") (pinfunction "C1_1") (pintype "passive"))
      (node (ref "C264") (pin "1") (pinfunction "C1_1") (pintype "passive"))
      (node (ref "C708") (pin "1") (pinfunction "C1_1") (pintype "passive"))
      (node (ref "C902") (pin "1") (pinfunction "C1_1") (pintype "passive"))
      (node (ref "FB701") (pin "2") (pinfunction "2_2") (pintype "passive"))
      (node (ref "FB901") (pin "1") (pinfunction "1_1") (pintype "passive"))
      (node (ref "JP1101") (pin "5") (pinfunction "S_5") (pintype "passive"))
      (node (ref "L1204") (pin "2") (pinfunction "2_2") (pintype "passive"))
      (node (ref "R1118") (pin "2") (pinfunction "2_2") (pintype "passive"))
      (node (ref "R1211") (pin "2") (pinfunction "2_2") (pintype "passive"))
      (node (ref "R1212") (pin "2") (pinfunction "2_2") (pintype "passive"))
      (node (ref "R201") (pin "2") (pinfunction "2_2") (pintype "passive"))
      (node (ref "R202") (pin "2") (pinfunction "2_2") (pintype "passive"))
      (node (ref "R205") (pin "2") (pinfunction "2_2") (pintype "passive"))
      (node (ref "R207") (pin "2") (pinfunction "2_2") (pintype "passive"))
      (node (ref "R214") (pin "2") (pinfunction "2_2") (pintype "passive"))
      (node (ref "R215") (pin "2") (pinfunction "2_2") (pintype "passive"))
      (node (ref "R217") (pin "2") (pinfunction "2_2") (pintype "passive"))
      (node (ref "R218") (pin "2") (pinfunction "2_2") (pintype "passive"))
      (node (ref "R219") (pin "2") (pinfunction "2_2") (pintype "passive"))
      (node (ref "R220") (pin "2") (pinfunction "2_2") (pintype "passive"))
      (node (ref "R221") (pin "2") (pinfunction "2_2") (pintype "passive"))
      (node (ref "R222") (pin "2") (pinfunction "2_2") (pintype "passive"))
      (node (ref "R803") (pin "2") (pinfunction "2_2") (pintype "passive"))
      (node (ref "R804") (pin "2") (pinfunction "2_2") (pintype "passive"))
      (node (ref "R805") (pin "2") (pinfunction "2_2") (pintype "passive"))
      (node (ref "R904") (pin "2") (pinfunction "2_2") (pintype "passive"))
      (node (ref "R905") (pin "2") (pinfunction "2_2") (pintype "passive"))
      (node (ref "TC201") (pin "1") (pinfunction "S_1") (pintype "passive"))
      (node (ref "U1001") (pin "8") (pinfunction "VCC_8") (pintype "bidirectional"))
      (node (ref "U1208") (pin "10") (pinfunction "SNS_10") (pintype "bidirectional"))
      (node (ref "U201") (pin "AA17") (pinfunction "VCCO_13_AA17") (pintype "bidirectional"))
      (node (ref "U201") (pin "AB14") (pinfunction "VCCO_13_AB14") (pintype "bidirectional"))
      (node (ref "U201") (pin "F12") (pinfunction "VCCO_0_F12") (pintype "bidirectional"))
      (node (ref "U201") (pin "M14") (pinfunction "VCCO_14_M14") (pintype "bidirectional"))
      (node (ref "U201") (pin "P18") (pinfunction "VCCO_14_P18") (pintype "bidirectional"))
      (node (ref "U201") (pin "R15") (pinfunction "VCCO_14_R15") (pintype "bidirectional"))
      (node (ref "U201") (pin "T12") (pinfunction "VCCO_0_T12") (pintype "bidirectional"))
      (node (ref "U201") (pin "T22") (pinfunction "VCCO_14_T22") (pintype "bidirectional"))
      (node (ref "U201") (pin "U11") (pinfunction "M0_U11") (pintype "bidirectional"))
      (node (ref "U201") (pin "U19") (pinfunction "VCCO_14_U19") (pintype "bidirectional"))
      (node (ref "U201") (pin "U8") (pinfunction "CFGBVS_U8") (pintype "bidirectional"))
      (node (ref "U201") (pin "V16") (pinfunction "VCCO_13_V16") (pintype "bidirectional"))
      (node (ref "U201") (pin "W13") (pinfunction "VCCO_13_W13") (pintype "bidirectional"))
      (node (ref "U201") (pin "Y10") (pinfunction "VCCO_13_Y10") (pintype "bidirectional"))
      (node (ref "U201") (pin "Y20") (pinfunction "VCCO_14_Y20") (pintype "bidirectional"))
      (node (ref "U202") (pin "8") (pinfunction "VCC_8") (pintype "power_in"))
    )
    (net (code "18") (name "3V3_CLK_MNGR") (class "Default")
      (node (ref "C901") (pin "1") (pinfunction "C1_1") (pintype "passive"))
      (node (ref "C903") (pin "1") (pinfunction "C1_1") (pintype "passive"))
      (node (ref "C904") (pin "1") (pinfunction "C1_1") (pintype "passive"))
      (node (ref "C905") (pin "1") (pinfunction "C1_1") (pintype "passive"))
      (node (ref "C908") (pin "1") (pinfunction "C1_1") (pintype "passive"))
      (node (ref "C909") (pin "1") (pinfunction "C1_1") (pintype "passive"))
      (node (ref "FB901") (pin "2") (pinfunction "2_2") (pintype "passive"))
      (node (ref "U901") (pin "4") (pinfunction "VDD_4") (pintype "power_in"))
      (node (ref "U902") (pin "10") (pinfunction "VDDOB_10") (pintype "bidirectional"))
      (node (ref "U902") (pin "11") (pinfunction "VDDOA_11") (pintype "bidirectional"))
      (node (ref "U902") (pin "14") (pinfunction "VDDOD_14") (pintype "bidirectional"))
      (node (ref "U902") (pin "18") (pinfunction "VDDOC_18") (pintype "bidirectional"))
      (node (ref "U902") (pin "20") (pinfunction "VDD_20") (pintype "bidirectional"))
    )
    (net (code "19") (name "3V3_CM4") (class "Default")
      (node (ref "C101") (pin "1") (pinfunction "C1_1") (pintype "passive"))
      (node (ref "C106") (pin "1") (pinfunction "C1_1") (pintype "passive"))
      (node (ref "C108") (pin "1") (pinfunction "C1_1") (pintype "passive"))
      (node (ref "CON101") (pin "1") (pinfunction "S_1") (pintype "passive"))
      (node (ref "CON102") (pin "1") (pinfunction "S_1") (pintype "passive"))
      (node (ref "R101") (pin "2") (pinfunction "2_2") (pintype "passive"))
      (node (ref "R103") (pin "2") (pinfunction "2_2") (pintype "passive"))
      (node (ref "R106") (pin "2") (pinfunction "2_2") (pintype "passive"))
      (node (ref "R108") (pin "2") (pinfunction "2_2") (pintype "passive"))
      (node (ref "R116") (pin "2") (pinfunction "2_2") (pintype "passive"))
      (node (ref "R117") (pin "2") (pinfunction "2_2") (pintype "passive"))
      (node (ref "R118") (pin "2") (pinfunction "2_2") (pintype "passive"))
      (node (ref "R119") (pin "2") (pinfunction "2_2") (pintype "passive"))
      (node (ref "R120") (pin "2") (pinfunction "2_2") (pintype "passive"))
      (node (ref "R121") (pin "2") (pinfunction "2_2") (pintype "passive"))
      (node (ref "R801") (pin "2") (pinfunction "2_2") (pintype "passive"))
      (node (ref "R802") (pin "2") (pinfunction "2_2") (pintype "passive"))
      (node (ref "U101") (pin "1") (pinfunction "VIN_1") (pintype "bidirectional"))
      (node (ref "U102") (pin "78") (pinfunction "GPIO_VREF_78") (pintype "bidirectional"))
      (node (ref "U102") (pin "84") (pinfunction "3V3_OUT_84") (pintype "bidirectional"))
      (node (ref "U102") (pin "86") (pinfunction "3V3_OUT_86") (pintype "bidirectional"))
    )
    (net (code "20") (name "3V3_CODEC") (class "Default")
      (node (ref "C1255") (pin "1") (pinfunction "C1_1") (pintype "passive"))
      (node (ref "C701") (pin "1") (pinfunction "C1_1") (pintype "passive"))
      (node (ref "C702") (pin "1") (pinfunction "C1_1") (pintype "passive"))
      (node (ref "C703") (pin "1") (pinfunction "C1_1") (pintype "passive"))
      (node (ref "C704") (pin "1") (pinfunction "C1_1") (pintype "passive"))
      (node (ref "C711") (pin "1") (pinfunction "C1_1") (pintype "passive"))
      (node (ref "C716") (pin "1") (pinfunction "C1_1") (pintype "passive"))
      (node (ref "CON701") (pin "1") (pinfunction "S_1") (pintype "passive"))
      (node (ref "M701") (pin "2") (pinfunction "SEL_2") (pintype "passive"))
      (node (ref "M701") (pin "5") (pinfunction "VCC_5") (pintype "passive"))
      (node (ref "M702") (pin "5") (pinfunction "VCC_5") (pintype "passive"))
      (node (ref "U1210") (pin "4") (pinfunction "SENSE/ADJ_4") (pintype "bidirectional"))
      (node (ref "U1210") (pin "5") (pinfunction "VOUT_5") (pintype "bidirectional"))
      (node (ref "U701") (pin "10") (pinfunction "AVDD_10") (pintype "bidirectional"))
      (node (ref "U701") (pin "19") (pinfunction "AVDD_19") (pintype "bidirectional"))
      (node (ref "U701") (pin "24") (pinfunction "AVDD_24") (pintype "bidirectional"))
    )
    (net (code "21") (name "3V3_PGOOD") (class "Default")
      (node (ref "R1211") (pin "1") (pinfunction "1_1") (pintype "passive"))
      (node (ref "TP6") (pin "TP") (pinfunction "TP_TP") (pintype "input"))
      (node (ref "U1208") (pin "12") (pinfunction "PG_12") (pintype "bidirectional"))
    )
    (net (code "22") (name "3V3_PM") (class "Default")
      (node (ref "C1007") (pin "1") (pinfunction "C1_1") (pintype "passive"))
      (node (ref "C1008") (pin "1") (pinfunction "C1_1") (pintype "passive"))
      (node (ref "C1010") (pin "1") (pinfunction "C1_1") (pintype "passive"))
      (node (ref "C1108") (pin "1") (pinfunction "C1_1") (pintype "passive"))
      (node (ref "C1109") (pin "1") (pinfunction "C1_1") (pintype "passive"))
      (node (ref "C1113") (pin "1") (pinfunction "C1_1") (pintype "passive"))
      (node (ref "R1002") (pin "2") (pinfunction "2_2") (pintype "passive"))
      (node (ref "R1004") (pin "2") (pinfunction "2_2") (pintype "passive"))
      (node (ref "R1007") (pin "2") (pinfunction "2_2") (pintype "passive"))
      (node (ref "R1011") (pin "2") (pinfunction "2_2") (pintype "passive"))
      (node (ref "R1014") (pin "2") (pinfunction "2_2") (pintype "passive"))
      (node (ref "TC1001") (pin "1") (pinfunction "S_1") (pintype "passive"))
      (node (ref "U1002") (pin "14") (pinfunction "VDD33_ALW_IN_14") (pintype "bidirectional"))
      (node (ref "U1002") (pin "16") (pinfunction "VDD33_IO_IN_16") (pintype "bidirectional"))
      (node (ref "U1002") (pin "21") (pinfunction "VDD33_ANA_IN_21") (pintype "bidirectional"))
      (node (ref "U1002") (pin "6") (pinfunction "VDD33_REG_IN_6") (pintype "bidirectional"))
      (node (ref "U1101") (pin "5") (pinfunction "VOUT_5") (pintype "bidirectional"))
      (node (ref "U1102") (pin "21") (pinfunction "EXTVCC_21") (pintype "bidirectional"))
    )
    (net (code "23") (name "3V3_SYNTH_IN_PD_FB") (class "Default")
      (node (ref "C1214") (pin "1") (pinfunction "C1_1") (pintype "passive"))
      (node (ref "C1217") (pin "1") (pinfunction "C1_1") (pintype "passive"))
      (node (ref "C604") (pin "1") (pinfunction "C1_1") (pintype "passive"))
      (node (ref "C607") (pin "1") (pinfunction "C1_1") (pintype "passive"))
      (node (ref "C610") (pin "1") (pinfunction "C1_1") (pintype "passive"))
      (node (ref "FB601") (pin "1") (pinfunction "1_1") (pintype "passive"))
      (node (ref "R604") (pin "2") (pinfunction "2_2") (pintype "passive"))
      (node (ref "R606") (pin "2") (pinfunction "2_2") (pintype "passive"))
      (node (ref "U1203") (pin "1") (pinfunction "VOUT_1") (pintype "bidirectional"))
      (node (ref "U1203") (pin "2") (pinfunction "VOUT_2") (pintype "bidirectional"))
      (node (ref "U1203") (pin "3") (pinfunction "SENSE_3") (pintype "bidirectional"))
      (node (ref "U601") (pin "12") (pinfunction "VDDPDCP_12") (pintype "bidirectional"))
      (node (ref "U601") (pin "15") (pinfunction "VDDFB_15") (pintype "bidirectional"))
      (node (ref "U601") (pin "24") (pinfunction "VDDIN_24") (pintype "bidirectional"))
    )
    (net (code "24") (name "3V3_SYNTH_VCO_RF") (class "Default")
      (node (ref "C1237") (pin "1") (pinfunction "C1_1") (pintype "passive"))
      (node (ref "C1241") (pin "1") (pinfunction "C1_1") (pintype "passive"))
      (node (ref "C602") (pin "1") (pinfunction "C1_1") (pintype "passive"))
      (node (ref "C605") (pin "1") (pinfunction "C1_1") (pintype "passive"))
      (node (ref "C608") (pin "1") (pinfunction "C1_1") (pintype "passive"))
      (node (ref "C611") (pin "1") (pinfunction "C1_1") (pintype "passive"))
      (node (ref "L601") (pin "1") (pinfunction "1_1") (pintype "passive"))
      (node (ref "L602") (pin "1") (pinfunction "1_1") (pintype "passive"))
      (node (ref "U1207") (pin "1") (pinfunction "VOUT_1") (pintype "bidirectional"))
      (node (ref "U1207") (pin "2") (pinfunction "VOUT_2") (pintype "bidirectional"))
      (node (ref "U1207") (pin "3") (pinfunction "SENSE_3") (pintype "bidirectional"))
      (node (ref "U601") (pin "3") (pinfunction "VDDVCO2_3") (pintype "bidirectional"))
      (node (ref "U601") (pin "33") (pinfunction "VDDVCO1_33") (pintype "bidirectional"))
      (node (ref "U601") (pin "37") (pinfunction "VDDOUTA_37") (pintype "bidirectional"))
      (node (ref "U601") (pin "48") (pinfunction "VDDOUTB_48") (pintype "bidirectional"))
    )
    (net (code "25") (name "3V5_VIN_REG_DRVCC") (class "Default")
      (node (ref "C1126") (pin "1") (pinfunction "C1_1") (pintype "passive"))
      (node (ref "R1120") (pin "2") (pinfunction "2_2") (pintype "passive"))
      (node (ref "R1123") (pin "2") (pinfunction "2_2") (pintype "passive"))
      (node (ref "R1124") (pin "2") (pinfunction "2_2") (pintype "passive"))
      (node (ref "U1102") (pin "20") (pinfunction "DRVCC_20") (pintype "bidirectional"))
      (node (ref "U1102") (pin "27") (pinfunction "~{FAULT}_27") (pintype "bidirectional"))
      (node (ref "U1102") (pin "28") (pinfunction "~{FAULT}_28") (pintype "bidirectional"))
    )
    (net (code "26") (name "5V0") (class "Default")
      (node (ref "C1012") (pin "1") (pinfunction "C1_1") (pintype "passive"))
      (node (ref "C1013") (pin "1") (pinfunction "C1_1") (pintype "passive"))
      (node (ref "C102") (pin "1") (pinfunction "C1_1") (pintype "passive"))
      (node (ref "C103") (pin "1") (pinfunction "C1_1") (pintype "passive"))
      (node (ref "C104") (pin "1") (pinfunction "C1_1") (pintype "passive"))
      (node (ref "C1122") (pin "1") (pinfunction "C1_1") (pintype "passive"))
      (node (ref "C1124") (pin "1") (pinfunction "C1_1") (pintype "passive"))
      (node (ref "C1127") (pin "1") (pinfunction "C1_1") (pintype "passive"))
      (node (ref "C1129") (pin "1") (pinfunction "C1_1") (pintype "passive"))
      (node (ref "C1201") (pin "1") (pinfunction "C1_1") (pintype "passive"))
      (node (ref "C1202") (pin "1") (pinfunction "C1_1") (pintype "passive"))
      (node (ref "C1204") (pin "1") (pinfunction "C1_1") (pintype "passive"))
      (node (ref "C1205") (pin "1") (pinfunction "C1_1") (pintype "passive"))
      (node (ref "C1223") (pin "1") (pinfunction "C1_1") (pintype "passive"))
      (node (ref "C1225") (pin "1") (pinfunction "C1_1") (pintype "passive"))
      (node (ref "C1229") (pin "1") (pinfunction "C1_1") (pintype "passive"))
      (node (ref "C1230") (pin "1") (pinfunction "C1_1") (pintype "passive"))
      (node (ref "C1232") (pin "1") (pinfunction "C1_1") (pintype "passive"))
      (node (ref "C1239") (pin "1") (pinfunction "C1_1") (pintype "passive"))
      (node (ref "C1242") (pin "1") (pinfunction "C1_1") (pintype "passive"))
      (node (ref "C1247") (pin "1") (pinfunction "C1_1") (pintype "passive"))
      (node (ref "C1248") (pin "1") (pinfunction "C1_1") (pintype "passive"))
      (node (ref "C1250") (pin "1") (pinfunction "C1_1") (pintype "passive"))
      (node (ref "C1256") (pin "1") (pinfunction "C1_1") (pintype "passive"))
      (node (ref "C1258") (pin "1") (pinfunction "C1_1") (pintype "passive"))
      (node (ref "JP1101") (pin "1") (pinfunction "S_1") (pintype "passive"))
      (node (ref "JP1101") (pin "2") (pinfunction "S_2") (pintype "passive"))
      (node (ref "L1101") (pin "2") (pinfunction "2_2") (pintype "passive"))
      (node (ref "R1119") (pin "2") (pinfunction "2_2") (pintype "passive"))
      (node (ref "R1121") (pin "2") (pinfunction "2_2") (pintype "passive"))
      (node (ref "R1122") (pin "2") (pinfunction "2_2") (pintype "passive"))
      (node (ref "R1210") (pin "2") (pinfunction "2_2") (pintype "passive"))
      (node (ref "U1002") (pin "3") (pinfunction "VCONN_IN_3") (pintype "bidirectional"))
      (node (ref "U1003") (pin "1") (pinfunction "VIN_1") (pintype "bidirectional"))
      (node (ref "U102") (pin "77") (pinfunction "5V0_77") (pintype "bidirectional"))
      (node (ref "U102") (pin "79") (pinfunction "5V0_79") (pintype "bidirectional"))
      (node (ref "U102") (pin "81") (pinfunction "5V0_81") (pintype "bidirectional"))
      (node (ref "U102") (pin "83") (pinfunction "5V0_83") (pintype "bidirectional"))
      (node (ref "U102") (pin "85") (pinfunction "5V0_85") (pintype "bidirectional"))
      (node (ref "U102") (pin "87") (pinfunction "5V0_87") (pintype "bidirectional"))
      (node (ref "U1102") (pin "2") (pinfunction "VSENSEP_2") (pintype "bidirectional"))
      (node (ref "U1201") (pin "7") (pinfunction "VIN_7") (pintype "bidirectional"))
      (node (ref "U1201") (pin "8") (pinfunction "VIN_8") (pintype "bidirectional"))
      (node (ref "U1203") (pin "7") (pinfunction "VIN_7") (pintype "bidirectional"))
      (node (ref "U1203") (pin "8") (pinfunction "VIN_8") (pintype "bidirectional"))
      (node (ref "U1204") (pin "1") (pinfunction "VIN_1") (pintype "bidirectional"))
      (node (ref "U1204") (pin "20") (pinfunction "AVIN_20") (pintype "bidirectional"))
      (node (ref "U1204") (pin "6") (pinfunction "VIN_6") (pintype "bidirectional"))
      (node (ref "U1204") (pin "7") (pinfunction "AVIN_7") (pintype "bidirectional"))
      (node (ref "U1205") (pin "2") (pinfunction "BIAS_2") (pintype "bidirectional"))
      (node (ref "U1207") (pin "7") (pinfunction "VIN_7") (pintype "bidirectional"))
      (node (ref "U1207") (pin "8") (pinfunction "VIN_8") (pintype "bidirectional"))
      (node (ref "U1208") (pin "1") (pinfunction "VIN_1") (pintype "bidirectional"))
      (node (ref "U1208") (pin "20") (pinfunction "AVIN_20") (pintype "bidirectional"))
      (node (ref "U1208") (pin "6") (pinfunction "VIN_6") (pintype "bidirectional"))
      (node (ref "U1208") (pin "7") (pinfunction "AVIN_7") (pintype "bidirectional"))
      (node (ref "U1209") (pin "8") (pinfunction "VIN_8") (pintype "bidirectional"))
      (node (ref "U1209") (pin "9") (pinfunction "VIN_9") (pintype "bidirectional"))
      (node (ref "U1210") (pin "1") (pinfunction "VIN_1") (pintype "bidirectional"))
    )
    (net (code "27") (name "5V0_PGOOD") (class "Default")
      (node (ref "R1121") (pin "1") (pinfunction "1_1") (pintype "passive"))
      (node (ref "TP1") (pin "TP") (pinfunction "TP_TP") (pintype "input"))
      (node (ref "U1102") (pin "23") (pinfunction "RUN_23") (pintype "bidirectional"))
      (node (ref "U1102") (pin "33") (pinfunction "PGOOD_33") (pintype "bidirectional"))
      (node (ref "U1201") (pin "5") (pinfunction "EN_5") (pintype "bidirectional"))
      (node (ref "U1203") (pin "5") (pinfunction "EN_5") (pintype "bidirectional"))
      (node (ref "U1207") (pin "5") (pinfunction "EN_5") (pintype "bidirectional"))
      (node (ref "U1210") (pin "3") (pinfunction "EN_3") (pintype "bidirectional"))
    )
    (net (code "28") (name "5V0_TRX_BIAS_T1") (class "Default")
      (node (ref "C505") (pin "1") (pinfunction "C1_1") (pintype "passive"))
      (node (ref "C507") (pin "1") (pinfunction "C1_1") (pintype "passive"))
      (node (ref "C517") (pin "1") (pinfunction "C1_1") (pintype "passive"))
      (node (ref "L501") (pin "1") (pinfunction "1_1") (pintype "passive"))
      (node (ref "R505") (pin "2") (pinfunction "2_2") (pintype "passive"))
      (node (ref "U501") (pin "6") (pinfunction "VOUT_6") (pintype "bidirectional"))
    )
    (net (code "29") (name "5V0_TRX_BIAS_T1_EN") (class "Default")
      (node (ref "U401") (pin "B7") (pinfunction "GPO_0_B7") (pintype "bidirectional"))
      (node (ref "U501") (pin "3") (pinfunction "EN_3") (pintype "bidirectional"))
    )
    (net (code "30") (name "5V0_TRX_BIAS_T2") (class "Default")
      (node (ref "C506") (pin "1") (pinfunction "C1_1") (pintype "passive"))
      (node (ref "C508") (pin "1") (pinfunction "C1_1") (pintype "passive"))
      (node (ref "C518") (pin "1") (pinfunction "C1_1") (pintype "passive"))
      (node (ref "L502") (pin "1") (pinfunction "1_1") (pintype "passive"))
      (node (ref "R506") (pin "2") (pinfunction "2_2") (pintype "passive"))
      (node (ref "U502") (pin "6") (pinfunction "VOUT_6") (pintype "bidirectional"))
    )
    (net (code "31") (name "5V0_TRX_BIAS_T2_EN") (class "Default")
      (node (ref "U401") (pin "B6") (pinfunction "GPO_1_B6") (pintype "bidirectional"))
      (node (ref "U502") (pin "3") (pinfunction "EN_3") (pintype "bidirectional"))
    )
    (net (code "32") (name "5V0_TRX_PA1") (class "Default")
      (node (ref "C521") (pin "1") (pinfunction "C1_1") (pintype "passive"))
      (node (ref "C542") (pin "1") (pinfunction "C1_1") (pintype "passive"))
      (node (ref "C548") (pin "1") (pinfunction "C1_1") (pintype "passive"))
      (node (ref "C551") (pin "1") (pinfunction "C1_1") (pintype "passive"))
      (node (ref "L511") (pin "1") (pinfunction "1_1") (pintype "passive"))
      (node (ref "R511") (pin "2") (pinfunction "2_2") (pintype "passive"))
      (node (ref "U503") (pin "6") (pinfunction "VOUT_6") (pintype "bidirectional"))
    )
    (net (code "33") (name "5V0_TRX_PA1_EN") (class "Default")
      (node (ref "U401") (pin "B5") (pinfunction "GPO_2_B5") (pintype "bidirectional"))
      (node (ref "U503") (pin "3") (pinfunction "EN_3") (pintype "bidirectional"))
    )
    (net (code "34") (name "5V0_TRX_PA2") (class "Default")
      (node (ref "C522") (pin "1") (pinfunction "C1_1") (pintype "passive"))
      (node (ref "C543") (pin "1") (pinfunction "C1_1") (pintype "passive"))
      (node (ref "C549") (pin "1") (pinfunction "C1_1") (pintype "passive"))
      (node (ref "C552") (pin "1") (pinfunction "C1_1") (pintype "passive"))
      (node (ref "L512") (pin "1") (pinfunction "1_1") (pintype "passive"))
      (node (ref "R512") (pin "2") (pinfunction "2_2") (pintype "passive"))
      (node (ref "U504") (pin "6") (pinfunction "VOUT_6") (pintype "bidirectional"))
    )
    (net (code "35") (name "5V0_TRX_PA2_EN") (class "Default")
      (node (ref "U401") (pin "B4") (pinfunction "GPO_3_B4") (pintype "bidirectional"))
      (node (ref "U504") (pin "3") (pinfunction "EN_3") (pintype "bidirectional"))
    )
    (net (code "36") (name "5V0_TRX_RF") (class "Default")
      (node (ref "C1212") (pin "1") (pinfunction "C1_1") (pintype "passive"))
      (node (ref "C1215") (pin "1") (pinfunction "C1_1") (pintype "passive"))
      (node (ref "C503") (pin "1") (pinfunction "C1_1") (pintype "passive"))
      (node (ref "C504") (pin "1") (pinfunction "C1_1") (pintype "passive"))
      (node (ref "C519") (pin "1") (pinfunction "C1_1") (pintype "passive"))
      (node (ref "C520") (pin "1") (pinfunction "C1_1") (pintype "passive"))
      (node (ref "U1201") (pin "1") (pinfunction "VOUT_1") (pintype "bidirectional"))
      (node (ref "U1201") (pin "2") (pinfunction "VOUT_2") (pintype "bidirectional"))
      (node (ref "U1201") (pin "3") (pinfunction "SENSE_3") (pintype "bidirectional"))
      (node (ref "U501") (pin "1") (pinfunction "VIN_1") (pintype "bidirectional"))
      (node (ref "U502") (pin "1") (pinfunction "VIN_1") (pintype "bidirectional"))
      (node (ref "U503") (pin "1") (pinfunction "VIN_1") (pintype "bidirectional"))
      (node (ref "U504") (pin "1") (pinfunction "VIN_1") (pintype "bidirectional"))
    )
    (net (code "37") (name "12V0") (class "Default")
      (node (ref "C1105") (pin "1") (pinfunction "C1_1") (pintype "passive"))
      (node (ref "CON801") (pin "A2") (pinfunction "S_A2") (pintype "passive"))
      (node (ref "CON801") (pin "A3") (pinfunction "S_A3") (pintype "passive"))
      (node (ref "CON801") (pin "B1") (pinfunction "S_B1") (pintype "passive"))
      (node (ref "CON801") (pin "B2") (pinfunction "S_B2") (pintype "passive"))
      (node (ref "CON801") (pin "B3") (pinfunction "S_B3") (pintype "passive"))
      (node (ref "D1102") (pin "A") (pinfunction "A_A") (pintype "passive"))
      (node (ref "Q1104") (pin "5") (pinfunction "D_5") (pintype "passive"))
      (node (ref "Q1104") (pin "6") (pinfunction "D_6") (pintype "passive"))
      (node (ref "R1108") (pin "2") (pinfunction "2_2") (pintype "passive"))
    )
    (net (code "38") (name "12V0_EN") (class "Default")
      (node (ref "Q1103") (pin "1") (pinfunction "G_1") (pintype "passive"))
      (node (ref "R1112") (pin "2") (pinfunction "2_2") (pintype "passive"))
      (node (ref "U1002") (pin "30") (pinfunction "PA15_30") (pintype "bidirectional"))
    )
    (net (code "39") (name "12V0_VSENSE") (class "Default")
      (node (ref "C1106") (pin "1") (pinfunction "C1_1") (pintype "passive"))
      (node (ref "R1108") (pin "1") (pinfunction "1_1") (pintype "passive"))
      (node (ref "R1109") (pin "2") (pinfunction "2_2") (pintype "passive"))
      (node (ref "U1002") (pin "17") (pinfunction "PA04_17") (pintype "bidirectional"))
    )
    (net (code "40") (name "AUDIO_I2C_SCL") (class "Default")
      (node (ref "R207") (pin "1") (pinfunction "1_1") (pintype "passive"))
      (node (ref "U201") (pin "AA14") (pinfunction "IO_L5N/T0_AA14") (pintype "bidirectional"))
      (node (ref "U701") (pin "2") (pinfunction "SCL/SCLK_2") (pintype "bidirectional"))
    )
    (net (code "41") (name "AUDIO_I2C_SDA") (class "Default")
      (node (ref "R205") (pin "1") (pinfunction "1_1") (pintype "passive"))
      (node (ref "U201") (pin "AA13") (pinfunction "IO_L3P/T0_DQS_AA13") (pintype "bidirectional"))
      (node (ref "U701") (pin "1") (pinfunction "SDA/MISO_1") (pintype "bidirectional"))
    )
    (net (code "42") (name "CM4_CAM0_CSI_C_N") (class "Default")
      (node (ref "CON101") (pin "15") (pinfunction "S_15") (pintype "passive"))
      (node (ref "U102") (pin "140") (pinfunction "CAM_C_N_140") (pintype "bidirectional"))
    )
    (net (code "43") (name "CM4_CAM0_CSI_C_P") (class "Default")
      (node (ref "CON101") (pin "14") (pinfunction "S_14") (pintype "passive"))
      (node (ref "U102") (pin "142") (pinfunction "CAM_C_P_142") (pintype "bidirectional"))
    )
    (net (code "44") (name "CM4_CAM0_CSI_D0_N") (class "Default")
      (node (ref "CON101") (pin "21") (pinfunction "S_21") (pintype "passive"))
      (node (ref "U102") (pin "128") (pinfunction "CAM_D0_N_128") (pintype "bidirectional"))
    )
    (net (code "45") (name "CM4_CAM0_CSI_D0_P") (class "Default")
      (node (ref "CON101") (pin "20") (pinfunction "S_20") (pintype "passive"))
      (node (ref "U102") (pin "130") (pinfunction "CAM_D0_P_130") (pintype "bidirectional"))
    )
    (net (code "46") (name "CM4_CAM0_CSI_D1_N") (class "Default")
      (node (ref "CON101") (pin "18") (pinfunction "S_18") (pintype "passive"))
      (node (ref "U102") (pin "134") (pinfunction "CAM_D1_N_134") (pintype "bidirectional"))
    )
    (net (code "47") (name "CM4_CAM0_CSI_D1_P") (class "Default")
      (node (ref "CON101") (pin "17") (pinfunction "S_17") (pintype "passive"))
      (node (ref "U102") (pin "136") (pinfunction "CAM_D1_P_136") (pintype "bidirectional"))
    )
    (net (code "48") (name "CM4_CAM0_SCL") (class "Default")
      (node (ref "CON101") (pin "3") (pinfunction "S_3") (pintype "passive"))
      (node (ref "R117") (pin "1") (pinfunction "1_1") (pintype "passive"))
      (node (ref "U102") (pin "35") (pinfunction "GPIO1_35") (pintype "bidirectional"))
    )
    (net (code "49") (name "CM4_CAM0_SDA") (class "Default")
      (node (ref "CON101") (pin "2") (pinfunction "S_2") (pintype "passive"))
      (node (ref "R116") (pin "1") (pinfunction "1_1") (pintype "passive"))
      (node (ref "U102") (pin "36") (pinfunction "GPIO0_36") (pintype "bidirectional"))
    )
    (net (code "50") (name "CM4_CAM1_CSI_C_N") (class "Default")
      (node (ref "CON102") (pin "15") (pinfunction "S_15") (pintype "passive"))
      (node (ref "U102") (pin "127") (pinfunction "CAM_C_N_127") (pintype "bidirectional"))
    )
    (net (code "51") (name "CM4_CAM1_CSI_C_P") (class "Default")
      (node (ref "CON102") (pin "14") (pinfunction "S_14") (pintype "passive"))
      (node (ref "U102") (pin "129") (pinfunction "CAM_C_P_129") (pintype "bidirectional"))
    )
    (net (code "52") (name "CM4_CAM1_CSI_D0_N") (class "Default")
      (node (ref "CON102") (pin "21") (pinfunction "S_21") (pintype "passive"))
      (node (ref "U102") (pin "115") (pinfunction "CAM_D0_N_115") (pintype "bidirectional"))
    )
    (net (code "53") (name "CM4_CAM1_CSI_D0_P") (class "Default")
      (node (ref "CON102") (pin "20") (pinfunction "S_20") (pintype "passive"))
      (node (ref "U102") (pin "117") (pinfunction "CAM_D0_P_117") (pintype "bidirectional"))
    )
    (net (code "54") (name "CM4_CAM1_CSI_D1_N") (class "Default")
      (node (ref "CON102") (pin "18") (pinfunction "S_18") (pintype "passive"))
      (node (ref "U102") (pin "121") (pinfunction "CAM_D1_N_121") (pintype "bidirectional"))
    )
    (net (code "55") (name "CM4_CAM1_CSI_D1_P") (class "Default")
      (node (ref "CON102") (pin "17") (pinfunction "S_17") (pintype "passive"))
      (node (ref "U102") (pin "123") (pinfunction "CAM_D1_P_123") (pintype "bidirectional"))
    )
    (net (code "56") (name "CM4_CAM1_CSI_D2_N") (class "Default")
      (node (ref "CON102") (pin "12") (pinfunction "S_12") (pintype "passive"))
      (node (ref "U102") (pin "133") (pinfunction "CAM_D2_N_133") (pintype "bidirectional"))
    )
    (net (code "57") (name "CM4_CAM1_CSI_D2_P") (class "Default")
      (node (ref "CON102") (pin "11") (pinfunction "S_11") (pintype "passive"))
      (node (ref "U102") (pin "135") (pinfunction "CAM_D2_P_135") (pintype "bidirectional"))
    )
    (net (code "58") (name "CM4_CAM1_CSI_D3_N") (class "Default")
      (node (ref "CON102") (pin "9") (pinfunction "S_9") (pintype "passive"))
      (node (ref "U102") (pin "139") (pinfunction "CAM_D3_N_139") (pintype "bidirectional"))
    )
    (net (code "59") (name "CM4_CAM1_CSI_D3_P") (class "Default")
      (node (ref "CON102") (pin "8") (pinfunction "S_8") (pintype "passive"))
      (node (ref "U102") (pin "141") (pinfunction "CAM_D3_P_141") (pintype "bidirectional"))
    )
    (net (code "60") (name "CM4_CAM1_SCL") (class "Default")
      (node (ref "CON102") (pin "3") (pinfunction "S_3") (pintype "passive"))
      (node (ref "R121") (pin "1") (pinfunction "1_1") (pintype "passive"))
      (node (ref "U102") (pin "80") (pinfunction "GPIO45_80") (pintype "bidirectional"))
    )
    (net (code "61") (name "CM4_CAM1_SDA") (class "Default")
      (node (ref "CON102") (pin "2") (pinfunction "S_2") (pintype "passive"))
      (node (ref "R120") (pin "1") (pinfunction "1_1") (pintype "passive"))
      (node (ref "U102") (pin "82") (pinfunction "GPIO44_82") (pintype "bidirectional"))
    )
    (net (code "62") (name "CM4_CAM_GPIO") (class "Default")
      (node (ref "CON101") (pin "6") (pinfunction "S_6") (pintype "passive"))
      (node (ref "CON102") (pin "6") (pinfunction "S_6") (pintype "passive"))
      (node (ref "U102") (pin "97") (pinfunction "CAMERA_GPIO_97") (pintype "bidirectional"))
    )
    (net (code "63") (name "CM4_GLOBAL_EN") (class "Default")
      (node (ref "R102") (pin "2") (pinfunction "2_2") (pintype "passive"))
      (node (ref "U1002") (pin "37") (pinfunction "PA23/GPIO7_37") (pintype "bidirectional"))
      (node (ref "U102") (pin "99") (pinfunction "GLOBAL_EN_99") (pintype "bidirectional"))
    )
    (net (code "64") (name "CM4_PTP_PPS_IN") (class "Default")
      (node (ref "R110") (pin "2") (pinfunction "2_2") (pintype "passive"))
      (node (ref "R111") (pin "2") (pinfunction "2_2") (pintype "passive"))
      (node (ref "U201") (pin "B1") (pinfunction "IO_L1P/T0/AD4P_B1") (pintype "bidirectional"))
    )
    (net (code "65") (name "CM4_PTP_PPS_OUT") (class "Default")
      (node (ref "R112") (pin "2") (pinfunction "2_2") (pintype "passive"))
      (node (ref "R113") (pin "2") (pinfunction "2_2") (pintype "passive"))
      (node (ref "U201") (pin "A1") (pinfunction "IO_L1N/T0/AD4N_A1") (pintype "bidirectional"))
    )
    (net (code "66") (name "CM4_RUNNING") (class "Default")
      (node (ref "U1002") (pin "35") (pinfunction "PA19/GPIO5_35") (pintype "bidirectional"))
      (node (ref "U102") (pin "92") (pinfunction "RUN_PG_92") (pintype "bidirectional"))
    )
    (net (code "67") (name "CM4_SD_CLK") (class "Default")
      (node (ref "SD101") (pin "5") (pinfunction "CLK_5") (pintype "input"))
      (node (ref "U102") (pin "57") (pinfunction "SD_CLK_57") (pintype "bidirectional"))
    )
    (net (code "68") (name "CM4_SD_CMD") (class "Default")
      (node (ref "SD101") (pin "3") (pinfunction "CMD_3") (pintype "bidirectional"))
      (node (ref "U102") (pin "62") (pinfunction "SD_CMD_62") (pintype "bidirectional"))
    )
    (net (code "69") (name "CM4_SD_D0") (class "Default")
      (node (ref "SD101") (pin "7") (pinfunction "DAT0_7") (pintype "bidirectional"))
      (node (ref "U102") (pin "63") (pinfunction "SD_DAT0_63") (pintype "bidirectional"))
    )
    (net (code "70") (name "CM4_SD_D1") (class "Default")
      (node (ref "SD101") (pin "8") (pinfunction "DAT1_8") (pintype "bidirectional"))
      (node (ref "U102") (pin "67") (pinfunction "SD_DAT1_67") (pintype "bidirectional"))
    )
    (net (code "71") (name "CM4_SD_D2") (class "Default")
      (node (ref "SD101") (pin "1") (pinfunction "DAT2_1") (pintype "bidirectional"))
      (node (ref "U102") (pin "69") (pinfunction "SD_DAT2_69") (pintype "bidirectional"))
    )
    (net (code "72") (name "CM4_SD_D3") (class "Default")
      (node (ref "SD101") (pin "2") (pinfunction "CD/DAT3_2") (pintype "bidirectional"))
      (node (ref "U102") (pin "61") (pinfunction "SD_DAT3_61") (pintype "bidirectional"))
    )
    (net (code "73") (name "CM4_SD_PWR_EN") (class "Default")
      (node (ref "R103") (pin "1") (pinfunction "1_1") (pintype "passive"))
      (node (ref "U101") (pin "3") (pinfunction "EN_3") (pintype "bidirectional"))
      (node (ref "U102") (pin "75") (pinfunction "SD_PWR_ON_75") (pintype "bidirectional"))
    )
    (net (code "74") (name "CM4_UART_RXD") (class "Default")
      (node (ref "R114") (pin "2") (pinfunction "2_2") (pintype "passive"))
      (node (ref "U102") (pin "51") (pinfunction "GPIO15_51") (pintype "bidirectional"))
    )
    (net (code "75") (name "CM4_UART_TXD") (class "Default")
      (node (ref "R115") (pin "2") (pinfunction "2_2") (pintype "passive"))
      (node (ref "U102") (pin "55") (pinfunction "GPIO14_55") (pintype "bidirectional"))
    )
    (net (code "76") (name "CM4_USB_OTG") (class "Default")
      (node (ref "U1002") (pin "1") (pinfunction "PA28_1") (pintype "bidirectional"))
      (node (ref "U102") (pin "101") (pinfunction "USB_OTG_ID_101") (pintype "bidirectional"))
    )
    (net (code "77") (name "CM4_WAKE") (class "Default")
      (node (ref "Q102") (pin "1") (pinfunction "G_1") (pintype "passive"))
      (node (ref "U201") (pin "A13") (pinfunction "IO_L10P/T1_A13") (pintype "bidirectional"))
    )
    (net (code "78") (name "CODEC_DMIC_CLK") (class "Default")
      (node (ref "CON701") (pin "2") (pinfunction "S_2") (pintype "passive"))
      (node (ref "M701") (pin "4") (pinfunction "CLK_4") (pintype "passive"))
      (node (ref "M702") (pin "4") (pinfunction "CLK_4") (pintype "passive"))
      (node (ref "U701") (pin "35") (pinfunction "ADC_SDATA1/CLKOUT/MP6_35") (pintype "bidirectional"))
    )
    (net (code "79") (name "CODEC_DMIC_DATA") (class "Default")
      (node (ref "M701") (pin "1") (pinfunction "DAT_1") (pintype "passive"))
      (node (ref "M702") (pin "1") (pinfunction "DAT_1") (pintype "passive"))
      (node (ref "U701") (pin "37") (pinfunction "DMIC0_1/MP4_37") (pintype "bidirectional"))
    )
    (net (code "80") (name "CODEC_DVDD") (class "Default")
      (node (ref "C705") (pin "1") (pinfunction "C1_1") (pintype "passive"))
      (node (ref "C706") (pin "1") (pinfunction "C1_1") (pintype "passive"))
      (node (ref "U701") (pin "28") (pinfunction "REG_OUT_28") (pintype "bidirectional"))
      (node (ref "U701") (pin "29") (pinfunction "DVDD_29") (pintype "bidirectional"))
    )
    (net (code "81") (name "CODEC_EXT_DMIC_DATA") (class "Default")
      (node (ref "CON701") (pin "3") (pinfunction "S_3") (pintype "passive"))
      (node (ref "U701") (pin "36") (pinfunction "DMIC2_3/MP5_36") (pintype "bidirectional"))
    )
    (net (code "82") (name "CODEC_I2S_LRCLK") (class "Default")
      (node (ref "U201") (pin "W17") (pinfunction "IO_L16N/T2/A15/D31_W17") (pintype "bidirectional"))
      (node (ref "U701") (pin "31") (pinfunction "LRCLK_31") (pintype "bidirectional"))
    )
    (net (code "83") (name "CODEC_I2S_MCLK") (class "Default")
      (node (ref "U201") (pin "AB13") (pinfunction "IO_L3N/T0_DQS_AB13") (pintype "bidirectional"))
      (node (ref "U701") (pin "39") (pinfunction "XTALI/MCLKIN_39") (pintype "bidirectional"))
    )
    (net (code "84") (name "CODEC_I2S_SCLK") (class "Default")
      (node (ref "U201") (pin "V17") (pinfunction "IO_L16P/T2/~{CSI}_V17") (pintype "bidirectional"))
      (node (ref "U701") (pin "32") (pinfunction "BCLK_32") (pintype "bidirectional"))
    )
    (net (code "85") (name "CODEC_I2S_SDIN") (class "Default")
      (node (ref "U201") (pin "W16") (pinfunction "IO_L16N/T2_W16") (pintype "bidirectional"))
      (node (ref "U701") (pin "33") (pinfunction "DAC_SDATA/MP0_33") (pintype "bidirectional"))
    )
    (net (code "86") (name "CODEC_I2S_SDOUT") (class "Default")
      (node (ref "U201") (pin "AA15") (pinfunction "IO_L4P/T0_AA15") (pintype "bidirectional"))
      (node (ref "U701") (pin "34") (pinfunction "ADC_SDATA0/MP1_34") (pintype "bidirectional"))
    )
    (net (code "87") (name "CODEC_LINE_IN_L") (class "Default")
      (node (ref "C719") (pin "1") (pinfunction "C1_1") (pintype "passive"))
      (node (ref "U701") (pin "18") (pinfunction "AIN3_18") (pintype "bidirectional"))
    )
    (net (code "88") (name "CODEC_LINE_IN_R") (class "Default")
      (node (ref "C720") (pin "1") (pinfunction "C1_1") (pintype "passive"))
      (node (ref "U701") (pin "16") (pinfunction "AIN2_16") (pintype "bidirectional"))
    )
    (net (code "89") (name "CODEC_MICBIAS0") (class "Default")
      (node (ref "C723") (pin "1") (pinfunction "C1_1") (pintype "passive"))
      (node (ref "R704") (pin "2") (pinfunction "2_2") (pintype "passive"))
      (node (ref "R708") (pin "2") (pinfunction "2_2") (pintype "passive"))
      (node (ref "U701") (pin "6") (pinfunction "MICBIAS0_6") (pintype "bidirectional"))
    )
    (net (code "90") (name "CODEC_MICBIAS1") (class "Default")
      (node (ref "C724") (pin "1") (pinfunction "C1_1") (pintype "passive"))
      (node (ref "R706") (pin "2") (pinfunction "2_2") (pintype "passive"))
      (node (ref "R710") (pin "2") (pinfunction "2_2") (pintype "passive"))
      (node (ref "U701") (pin "7") (pinfunction "MICBIAS1_7") (pintype "bidirectional"))
    )
    (net (code "91") (name "CODEC_MIC_IN_L") (class "Default")
      (node (ref "C717") (pin "1") (pinfunction "C1_1") (pintype "passive"))
      (node (ref "U701") (pin "14") (pinfunction "AIN1_14") (pintype "bidirectional"))
    )
    (net (code "92") (name "CODEC_MIC_IN_R") (class "Default")
      (node (ref "C718") (pin "1") (pinfunction "C1_1") (pintype "passive"))
      (node (ref "U701") (pin "9") (pinfunction "AIN0_9") (pintype "bidirectional"))
    )
    (net (code "93") (name "CODEC_OUT_L") (class "Default")
      (node (ref "C712") (pin "1") (pinfunction "C1_1") (pintype "passive"))
      (node (ref "C713") (pin "1") (pinfunction "C1_1") (pintype "passive"))
      (node (ref "U701") (pin "22") (pinfunction "HPOUTLP/LOUTLP_22") (pintype "bidirectional"))
    )
    (net (code "94") (name "CODEC_OUT_R") (class "Default")
      (node (ref "C714") (pin "1") (pinfunction "C1_1") (pintype "passive"))
      (node (ref "C715") (pin "1") (pinfunction "C1_1") (pintype "passive"))
      (node (ref "U701") (pin "26") (pinfunction "HPOUTRP/LOUTRP_26") (pintype "bidirectional"))
    )
    (net (code "95") (name "DDR3_A0") (class "Default")
      (node (ref "R303") (pin "2") (pinfunction "2_2") (pintype "passive"))
      (node (ref "U201") (pin "W6") (pinfunction "IO_L15P/T2_DQS_W6") (pintype "bidirectional"))
      (node (ref "U301") (pin "N3") (pinfunction "A0_N3") (pintype "bidirectional"))
    )
    (net (code "96") (name "DDR3_A1") (class "Default")
      (node (ref "R312") (pin "2") (pinfunction "2_2") (pintype "passive"))
      (node (ref "U201") (pin "U5") (pinfunction "IO_L14N/T2/SRCC_U5") (pintype "bidirectional"))
      (node (ref "U301") (pin "P7") (pinfunction "A1_P7") (pintype "bidirectional"))
    )
    (net (code "97") (name "DDR3_A2") (class "Default")
      (node (ref "R304") (pin "2") (pinfunction "2_2") (pintype "passive"))
      (node (ref "U201") (pin "T5") (pinfunction "IO_L14P/T2/SRCC_T5") (pintype "bidirectional"))
      (node (ref "U301") (pin "P3") (pinfunction "A2_P3") (pintype "bidirectional"))
    )
    (net (code "98") (name "DDR3_A3") (class "Default")
      (node (ref "R313") (pin "2") (pinfunction "2_2") (pintype "passive"))
      (node (ref "U201") (pin "W4") (pinfunction "IO_L12N/T1/MRCC_W4") (pintype "bidirectional"))
      (node (ref "U301") (pin "N2") (pinfunction "A3_N2") (pintype "bidirectional"))
    )
    (net (code "99") (name "DDR3_A4") (class "Default")
      (node (ref "R305") (pin "2") (pinfunction "2_2") (pintype "passive"))
      (node (ref "U201") (pin "V4") (pinfunction "IO_L12P/T1/MRCC_V4") (pintype "bidirectional"))
      (node (ref "U301") (pin "P8") (pinfunction "A4_P8") (pintype "bidirectional"))
    )
    (net (code "100") (name "DDR3_A5") (class "Default")
      (node (ref "R314") (pin "2") (pinfunction "2_2") (pintype "passive"))
      (node (ref "U201") (pin "AA4") (pinfunction "IO_L11N/T1/SRCC_AA4") (pintype "bidirectional"))
      (node (ref "U301") (pin "P2") (pinfunction "A5_P2") (pintype "bidirectional"))
    )
    (net (code "101") (name "DDR3_A6") (class "Default")
      (node (ref "R306") (pin "2") (pinfunction "2_2") (pintype "passive"))
      (node (ref "U201") (pin "Y4") (pinfunction "IO_L11P/T1/SRCC_Y4") (pintype "bidirectional"))
      (node (ref "U301") (pin "R8") (pinfunction "A6_R8") (pintype "bidirectional"))
    )
    (net (code "102") (name "DDR3_A7") (class "Default")
      (node (ref "R315") (pin "2") (pinfunction "2_2") (pintype "passive"))
      (node (ref "U201") (pin "AB5") (pinfunction "IO_L10N/T1_AB5") (pintype "bidirectional"))
      (node (ref "U301") (pin "R2") (pinfunction "A7_R2") (pintype "bidirectional"))
    )
    (net (code "103") (name "DDR3_A8") (class "Default")
      (node (ref "R307") (pin "2") (pinfunction "2_2") (pintype "passive"))
      (node (ref "U201") (pin "AA5") (pinfunction "IO_L10P/T1_AA5") (pintype "bidirectional"))
      (node (ref "U301") (pin "T8") (pinfunction "A8_T8") (pintype "bidirectional"))
    )
    (net (code "104") (name "DDR3_A9") (class "Default")
      (node (ref "R316") (pin "2") (pinfunction "2_2") (pintype "passive"))
      (node (ref "U201") (pin "AA3") (pinfunction "IO_L9N/T1_DQS_AA3") (pintype "bidirectional"))
      (node (ref "U301") (pin "R3") (pinfunction "A9_R3") (pintype "bidirectional"))
    )
    (net (code "105") (name "DDR3_A10") (class "Default")
      (node (ref "R308") (pin "2") (pinfunction "2_2") (pintype "passive"))
      (node (ref "U201") (pin "Y3") (pinfunction "IO_L9P/T1_DQS_Y3") (pintype "bidirectional"))
      (node (ref "U301") (pin "L7") (pinfunction "A10/AP_L7") (pintype "bidirectional"))
    )
    (net (code "106") (name "DDR3_A11") (class "Default")
      (node (ref "R317") (pin "2") (pinfunction "2_2") (pintype "passive"))
      (node (ref "U201") (pin "AB2") (pinfunction "IO_L8N/T1_AB2") (pintype "bidirectional"))
      (node (ref "U301") (pin "R7") (pinfunction "A11_R7") (pintype "bidirectional"))
    )
    (net (code "107") (name "DDR3_A12") (class "Default")
      (node (ref "R309") (pin "2") (pinfunction "2_2") (pintype "passive"))
      (node (ref "U201") (pin "AB3") (pinfunction "IO_L8P/T1_AB3") (pintype "bidirectional"))
      (node (ref "U301") (pin "N7") (pinfunction "A12/~{BC}_N7") (pintype "bidirectional"))
    )
    (net (code "108") (name "DDR3_A13") (class "Default")
      (node (ref "R318") (pin "2") (pinfunction "2_2") (pintype "passive"))
      (node (ref "U201") (pin "AB1") (pinfunction "IO_L7N/T1_AB1") (pintype "bidirectional"))
      (node (ref "U301") (pin "T3") (pinfunction "A13_T3") (pintype "bidirectional"))
    )
    (net (code "109") (name "DDR3_A14") (class "Default")
      (node (ref "R310") (pin "2") (pinfunction "2_2") (pintype "passive"))
      (node (ref "U201") (pin "AA1") (pinfunction "IO_L7P/T1_AA1") (pintype "bidirectional"))
      (node (ref "U301") (pin "T7") (pinfunction "A14_T7") (pintype "bidirectional"))
    )
    (net (code "110") (name "DDR3_BA0") (class "Default")
      (node (ref "R321") (pin "1") (pinfunction "1_1") (pintype "passive"))
      (node (ref "U201") (pin "V5") (pinfunction "IO_L16N/T2_V5") (pintype "bidirectional"))
      (node (ref "U301") (pin "M2") (pinfunction "BA0_M2") (pintype "bidirectional"))
    )
    (net (code "111") (name "DDR3_BA1") (class "Default")
      (node (ref "R325") (pin "1") (pinfunction "1_1") (pintype "passive"))
      (node (ref "U201") (pin "U6") (pinfunction "IO_L16P/T2_U6") (pintype "bidirectional"))
      (node (ref "U301") (pin "N8") (pinfunction "BA1_N8") (pintype "bidirectional"))
    )
    (net (code "112") (name "DDR3_BA2") (class "Default")
      (node (ref "R320") (pin "1") (pinfunction "1_1") (pintype "passive"))
      (node (ref "U201") (pin "W5") (pinfunction "IO_L15N/T2_DQS_W5") (pintype "bidirectional"))
      (node (ref "U301") (pin "M3") (pinfunction "BA2_M3") (pintype "bidirectional"))
    )
    (net (code "113") (name "DDR3_CLK_EN") (class "Default")
      (node (ref "R328") (pin "1") (pinfunction "1_1") (pintype "passive"))
      (node (ref "U201") (pin "AA6") (pinfunction "IO_L18N/T2_AA6") (pintype "bidirectional"))
      (node (ref "U301") (pin "K9") (pinfunction "CKE_K9") (pintype "bidirectional"))
    )
    (net (code "114") (name "DDR3_CLK_N") (class "Default")
      (node (ref "R319") (pin "1") (pinfunction "1_1") (pintype "passive"))
      (node (ref "U201") (pin "V8") (pinfunction "IO_L21N/T3_DQS_V8") (pintype "bidirectional"))
      (node (ref "U301") (pin "K7") (pinfunction "~{CK}_K7") (pintype "bidirectional"))
    )
    (net (code "115") (name "DDR3_CLK_P") (class "Default")
      (node (ref "R311") (pin "2") (pinfunction "2_2") (pintype "passive"))
      (node (ref "U201") (pin "V9") (pinfunction "IO_L21P/T3_DQS_V9") (pintype "bidirectional"))
      (node (ref "U301") (pin "J7") (pinfunction "CK_J7") (pintype "bidirectional"))
    )
    (net (code "116") (name "DDR3_DM0") (class "Default")
      (node (ref "U201") (pin "N4") (pinfunction "IO_L19P/T3_N4") (pintype "bidirectional"))
      (node (ref "U301") (pin "E7") (pinfunction "LDM_E7") (pintype "bidirectional"))
    )
    (net (code "117") (name "DDR3_DM1") (class "Default")
      (node (ref "U201") (pin "T1") (pinfunction "IO_L1P/T0_T1") (pintype "bidirectional"))
      (node (ref "U301") (pin "D3") (pinfunction "UDM_D3") (pintype "bidirectional"))
    )
    (net (code "118") (name "DDR3_DQ0") (class "Default")
      (node (ref "U201") (pin "R1") (pinfunction "IO_L20P/T3_R1") (pintype "bidirectional"))
      (node (ref "U301") (pin "E3") (pinfunction "DQ0_E3") (pintype "bidirectional"))
    )
    (net (code "119") (name "DDR3_DQ1") (class "Default")
      (node (ref "U201") (pin "P1") (pinfunction "IO_L20N/T3_P1") (pintype "bidirectional"))
      (node (ref "U301") (pin "F7") (pinfunction "DQ1_F7") (pintype "bidirectional"))
    )
    (net (code "120") (name "DDR3_DQ2") (class "Default")
      (node (ref "U201") (pin "P2") (pinfunction "IO_L22P/T3_P2") (pintype "bidirectional"))
      (node (ref "U301") (pin "F2") (pinfunction "DQ2_F2") (pintype "bidirectional"))
    )
    (net (code "121") (name "DDR3_DQ3") (class "Default")
      (node (ref "U201") (pin "N2") (pinfunction "IO_L22N/T3_N2") (pintype "bidirectional"))
      (node (ref "U301") (pin "F8") (pinfunction "DQ3_F8") (pintype "bidirectional"))
    )
    (net (code "122") (name "DDR3_DQ4") (class "Default")
      (node (ref "U201") (pin "M6") (pinfunction "IO_L23P/T3_M6") (pintype "bidirectional"))
      (node (ref "U301") (pin "H3") (pinfunction "DQ4_H3") (pintype "bidirectional"))
    )
    (net (code "123") (name "DDR3_DQ5") (class "Default")
      (node (ref "U201") (pin "M5") (pinfunction "IO_L23N/T3_M5") (pintype "bidirectional"))
      (node (ref "U301") (pin "H8") (pinfunction "DQ5_H8") (pintype "bidirectional"))
    )
    (net (code "124") (name "DDR3_DQ6") (class "Default")
      (node (ref "U201") (pin "P6") (pinfunction "IO_L24P/T3_P6") (pintype "bidirectional"))
      (node (ref "U301") (pin "G2") (pinfunction "DQ6_G2") (pintype "bidirectional"))
    )
    (net (code "125") (name "DDR3_DQ7") (class "Default")
      (node (ref "U201") (pin "N5") (pinfunction "IO_L24N/T3_N5") (pintype "bidirectional"))
      (node (ref "U301") (pin "H7") (pinfunction "DQ7_H7") (pintype "bidirectional"))
    )
    (net (code "126") (name "DDR3_DQ8") (class "Default")
      (node (ref "U201") (pin "U1") (pinfunction "IO_L1N/T0_U1") (pintype "bidirectional"))
      (node (ref "U301") (pin "D7") (pinfunction "DQ8_D7") (pintype "bidirectional"))
    )
    (net (code "127") (name "DDR3_DQ9") (class "Default")
      (node (ref "U201") (pin "U2") (pinfunction "IO_L2P/T0_U2") (pintype "bidirectional"))
      (node (ref "U301") (pin "C3") (pinfunction "DQ9_C3") (pintype "bidirectional"))
    )
    (net (code "128") (name "DDR3_DQ10") (class "Default")
      (node (ref "U201") (pin "V2") (pinfunction "IO_L2N/T0_V2") (pintype "bidirectional"))
      (node (ref "U301") (pin "C8") (pinfunction "DQ10_C8") (pintype "bidirectional"))
    )
    (net (code "129") (name "DDR3_DQ11") (class "Default")
      (node (ref "U201") (pin "W2") (pinfunction "IO_L4P/T0_W2") (pintype "bidirectional"))
      (node (ref "U301") (pin "C2") (pinfunction "DQ11_C2") (pintype "bidirectional"))
    )
    (net (code "130") (name "DDR3_DQ12") (class "Default")
      (node (ref "U201") (pin "Y2") (pinfunction "IO_L4N/T0_Y2") (pintype "bidirectional"))
      (node (ref "U301") (pin "A7") (pinfunction "DQ12_A7") (pintype "bidirectional"))
    )
    (net (code "131") (name "DDR3_DQ13") (class "Default")
      (node (ref "U201") (pin "W1") (pinfunction "IO_L5P/T0_W1") (pintype "bidirectional"))
      (node (ref "U301") (pin "A2") (pinfunction "DQ13_A2") (pintype "bidirectional"))
    )
    (net (code "132") (name "DDR3_DQ14") (class "Default")
      (node (ref "U201") (pin "Y1") (pinfunction "IO_L5N/T0_Y1") (pintype "bidirectional"))
      (node (ref "U301") (pin "B8") (pinfunction "DQ14_B8") (pintype "bidirectional"))
    )
    (net (code "133") (name "DDR3_DQ15") (class "Default")
      (node (ref "U201") (pin "U3") (pinfunction "IO_L6P/T0_U3") (pintype "bidirectional"))
      (node (ref "U301") (pin "A3") (pinfunction "DQ15_A3") (pintype "bidirectional"))
    )
    (net (code "134") (name "DDR3_DQS0_N") (class "Default")
      (node (ref "U201") (pin "P4") (pinfunction "IO_L21N/T3_DQS_P4") (pintype "bidirectional"))
      (node (ref "U301") (pin "G3") (pinfunction "~{LDQS}_G3") (pintype "bidirectional"))
    )
    (net (code "135") (name "DDR3_DQS0_P") (class "Default")
      (node (ref "U201") (pin "P5") (pinfunction "IO_L21P/T3_DQS_P5") (pintype "bidirectional"))
      (node (ref "U301") (pin "F3") (pinfunction "LDQS_F3") (pintype "bidirectional"))
    )
    (net (code "136") (name "DDR3_DQS1_N") (class "Default")
      (node (ref "U201") (pin "R2") (pinfunction "IO_L3N/T0_DQS_R2") (pintype "bidirectional"))
      (node (ref "U301") (pin "B7") (pinfunction "~{UDQS}_B7") (pintype "bidirectional"))
    )
    (net (code "137") (name "DDR3_DQS1_P") (class "Default")
      (node (ref "U201") (pin "R3") (pinfunction "IO_L3P/T0_DQS_R3") (pintype "bidirectional"))
      (node (ref "U301") (pin "C7") (pinfunction "UDQS_C7") (pintype "bidirectional"))
    )
    (net (code "138") (name "DDR3_ODT") (class "Default")
      (node (ref "R326") (pin "1") (pinfunction "1_1") (pintype "passive"))
      (node (ref "U201") (pin "V7") (pinfunction "IO_L19P/T3_V7") (pintype "bidirectional"))
      (node (ref "U301") (pin "K1") (pinfunction "ODT_K1") (pintype "bidirectional"))
    )
    (net (code "139") (name "ETH_ACT_LED") (class "Default")
      (node (ref "J101") (pin "12") (pinfunction "C_12") (pintype "passive"))
      (node (ref "U102") (pin "17") (pinfunction "~{ETH_LED2}_17") (pintype "bidirectional"))
    )
    (net (code "140") (name "ETH_LINK_LED") (class "Default")
      (node (ref "J101") (pin "14") (pinfunction "C_14") (pintype "passive"))
      (node (ref "U102") (pin "15") (pinfunction "~{ETH_LED3}_15") (pintype "bidirectional"))
    )
    (net (code "141") (name "ETH_P0_N") (class "Default")
      (node (ref "J101") (pin "3") (pinfunction "P0-_3") (pintype "bidirectional"))
      (node (ref "U102") (pin "10") (pinfunction "ETH_P0N_10") (pintype "bidirectional"))
    )
    (net (code "142") (name "ETH_P0_P") (class "Default")
      (node (ref "J101") (pin "2") (pinfunction "P0+_2") (pintype "bidirectional"))
      (node (ref "U102") (pin "12") (pinfunction "ETH_P0P_12") (pintype "bidirectional"))
    )
    (net (code "143") (name "ETH_P1_N") (class "Default")
      (node (ref "J101") (pin "7") (pinfunction "P1-_7") (pintype "bidirectional"))
      (node (ref "U102") (pin "6") (pinfunction "ETH_P1N_6") (pintype "bidirectional"))
    )
    (net (code "144") (name "ETH_P1_P") (class "Default")
      (node (ref "J101") (pin "4") (pinfunction "P1+_4") (pintype "bidirectional"))
      (node (ref "U102") (pin "4") (pinfunction "ETH_P1P_4") (pintype "bidirectional"))
    )
    (net (code "145") (name "ETH_P2_N") (class "Default")
      (node (ref "J101") (pin "6") (pinfunction "P2-_6") (pintype "bidirectional"))
      (node (ref "U102") (pin "9") (pinfunction "ETH_P2N_9") (pintype "bidirectional"))
    )
    (net (code "146") (name "ETH_P2_P") (class "Default")
      (node (ref "J101") (pin "5") (pinfunction "P2+_5") (pintype "bidirectional"))
      (node (ref "U102") (pin "11") (pinfunction "ETH_P2P_11") (pintype "bidirectional"))
    )
    (net (code "147") (name "ETH_P3_N") (class "Default")
      (node (ref "J101") (pin "9") (pinfunction "P3-_9") (pintype "bidirectional"))
      (node (ref "U102") (pin "5") (pinfunction "ETH_P3N_5") (pintype "bidirectional"))
    )
    (net (code "148") (name "ETH_P3_P") (class "Default")
      (node (ref "J101") (pin "8") (pinfunction "P3+_8") (pintype "bidirectional"))
      (node (ref "U102") (pin "3") (pinfunction "ETH_P3P_3") (pintype "bidirectional"))
    )
    (net (code "149") (name "EXT_CLK_2_3") (class "Default")
      (node (ref "JP201") (pin "3") (pinfunction "S_3") (pintype "passive"))
      (node (ref "R909") (pin "1") (pinfunction "1_1") (pintype "passive"))
    )
    (net (code "150") (name "EXT_CLK_OUT") (class "Default")
      (node (ref "R913") (pin "1") (pinfunction "1_1") (pintype "passive"))
      (node (ref "RFCON902") (pin "P$3") (pinfunction "SIGNAL_P$3") (pintype "bidirectional"))
    )
    (net (code "151") (name "EXT_IO_1_1") (class "Default")
      (node (ref "R211") (pin "2") (pinfunction "2_2") (pintype "passive"))
      (node (ref "U201") (pin "AA9") (pinfunction "IO_L8P/T1_AA9") (pintype "bidirectional"))
    )
    (net (code "152") (name "EXT_IO_1_2") (class "Default")
      (node (ref "R208") (pin "2") (pinfunction "2_2") (pintype "passive"))
      (node (ref "U201") (pin "AA11") (pinfunction "IO_L9N/T1_DQS_AA11") (pintype "bidirectional"))
    )
    (net (code "153") (name "EXT_IO_1_3") (class "Default")
      (node (ref "R212") (pin "2") (pinfunction "2_2") (pintype "passive"))
      (node (ref "U201") (pin "AB10") (pinfunction "IO_L8N/T1_AB10") (pintype "bidirectional"))
    )
    (net (code "154") (name "EXT_IO_1_4") (class "Default")
      (node (ref "R209") (pin "2") (pinfunction "2_2") (pintype "passive"))
      (node (ref "U201") (pin "AB11") (pinfunction "IO_L7P/T1_AB11") (pintype "bidirectional"))
    )
    (net (code "155") (name "EXT_IO_1_5") (class "Default")
      (node (ref "R213") (pin "2") (pinfunction "2_2") (pintype "passive"))
      (node (ref "U201") (pin "AA10") (pinfunction "IO_L9P/T1_DQS_AA10") (pintype "bidirectional"))
    )
    (net (code "156") (name "EXT_IO_2_2") (class "Default")
      (node (ref "R203") (pin "2") (pinfunction "2_2") (pintype "passive"))
      (node (ref "U201") (pin "A16") (pinfunction "IO_L9N/T1_DQS_A16") (pintype "bidirectional"))
    )
    (net (code "157") (name "EXT_IO_2_4") (class "Default")
      (node (ref "R204") (pin "2") (pinfunction "2_2") (pintype "passive"))
      (node (ref "U201") (pin "A15") (pinfunction "IO_L9P/T1_DQS_A15") (pintype "bidirectional"))
    )
    (net (code "158") (name "EXT_IO_2_6") (class "Default")
      (node (ref "R206") (pin "2") (pinfunction "2_2") (pintype "passive"))
      (node (ref "U201") (pin "A14") (pinfunction "IO_L10N/T1_A14") (pintype "bidirectional"))
    )
    (net (code "159") (name "FPGA_CLK0") (class "Default")
      (node (ref "R907") (pin "1") (pinfunction "1_1") (pintype "passive"))
      (node (ref "U201") (pin "W11") (pinfunction "IO_L12P/T1/MRCC_W11") (pintype "bidirectional"))
    )
    (net (code "160") (name "FPGA_CLK1") (class "Default")
      (node (ref "R911") (pin "1") (pinfunction "1_1") (pintype "passive"))
      (node (ref "U201") (pin "V13") (pinfunction "IO_L13P/T2/MRCC_V13") (pintype "bidirectional"))
    )
    (net (code "161") (name "FPGA_CLK2") (class "Default")
      (node (ref "R906") (pin "1") (pinfunction "1_1") (pintype "passive"))
      (node (ref "U201") (pin "W19") (pinfunction "IO_L12P/T1/MRCC_W19") (pintype "bidirectional"))
    )
    (net (code "162") (name "FPGA_CLK3") (class "Default")
      (node (ref "R910") (pin "1") (pinfunction "1_1") (pintype "passive"))
      (node (ref "U201") (pin "Y18") (pinfunction "IO_L13P/T2/MRCC_Y18") (pintype "bidirectional"))
    )
    (net (code "163") (name "FPGA_DONE") (class "Default")
      (node (ref "D202") (pin "A") (pinfunction "A_A") (pintype "passive"))
      (node (ref "R222") (pin "1") (pinfunction "1_1") (pintype "passive"))
      (node (ref "U201") (pin "G11") (pinfunction "DONE_G11") (pintype "bidirectional"))
    )
    (net (code "164") (name "FPGA_FLASH_IO0") (class "Default")
      (node (ref "U201") (pin "P22") (pinfunction "IO_L1P/T0/D0/MOSI_P22") (pintype "bidirectional"))
      (node (ref "U202") (pin "5") (pinfunction "MOSI/IO0_5") (pintype "input"))
    )
    (net (code "165") (name "FPGA_FLASH_IO1") (class "Default")
      (node (ref "U201") (pin "R22") (pinfunction "IO_L1N/T0/D1/DIN_R22") (pintype "bidirectional"))
      (node (ref "U202") (pin "2") (pinfunction "MISO/IO1_2") (pintype "output"))
    )
    (net (code "166") (name "FPGA_FLASH_IO2") (class "Default")
      (node (ref "R217") (pin "1") (pinfunction "1_1") (pintype "passive"))
      (node (ref "U201") (pin "P21") (pinfunction "IO_L2P/T0/D2_P21") (pintype "bidirectional"))
      (node (ref "U202") (pin "3") (pinfunction "~{WP}/IO2_3") (pintype "input"))
    )
    (net (code "167") (name "FPGA_FLASH_IO3") (class "Default")
      (node (ref "R218") (pin "1") (pinfunction "1_1") (pintype "passive"))
      (node (ref "U201") (pin "R21") (pinfunction "IO_L2N/T0/D3_R21") (pintype "bidirectional"))
      (node (ref "U202") (pin "7") (pinfunction "~{HOLD}/IO3_7") (pintype "input"))
    )
    (net (code "168") (name "FPGA_FLASH_SCK") (class "Default")
      (node (ref "U201") (pin "L12") (pinfunction "CCLK_L12") (pintype "bidirectional"))
      (node (ref "U201") (pin "N13") (pinfunction "IO_L23P/T3/A3/D19_N13") (pintype "bidirectional"))
      (node (ref "U202") (pin "6") (pinfunction "SCK_6") (pintype "input"))
    )
    (net (code "169") (name "FPGA_JTAG_EN") (class "Default")
      (node (ref "R216") (pin "2") (pinfunction "2_2") (pintype "passive"))
      (node (ref "TC201") (pin "10") (pinfunction "S_10") (pintype "passive"))
      (node (ref "U201") (pin "U9") (pinfunction "M2_U9") (pintype "bidirectional"))
    )
    (net (code "170") (name "FPGA_TCK") (class "Default")
      (node (ref "TC201") (pin "4") (pinfunction "S_4") (pintype "passive"))
      (node (ref "U201") (pin "V12") (pinfunction "TCK_V12") (pintype "bidirectional"))
    )
    (net (code "171") (name "FPGA_TDI") (class "Default")
      (node (ref "R220") (pin "1") (pinfunction "1_1") (pintype "passive"))
      (node (ref "TC201") (pin "8") (pinfunction "S_8") (pintype "passive"))
      (node (ref "U201") (pin "R13") (pinfunction "TDI_R13") (pintype "bidirectional"))
    )
    (net (code "172") (name "FPGA_TDO") (class "Default")
      (node (ref "TC201") (pin "6") (pinfunction "S_6") (pintype "passive"))
      (node (ref "U201") (pin "U13") (pinfunction "TDO_U13") (pintype "bidirectional"))
    )
    (net (code "173") (name "FPGA_TMS") (class "Default")
      (node (ref "R221") (pin "1") (pinfunction "1_1") (pintype "passive"))
      (node (ref "TC201") (pin "2") (pinfunction "S_2") (pintype "passive"))
      (node (ref "U201") (pin "T13") (pinfunction "TMS_T13") (pintype "bidirectional"))
    )
    (net (code "174") (name "GND") (class "Default")
      (node (ref "C1001") (pin "2") (pinfunction "C2_2") (pintype "passive"))
      (node (ref "C1002") (pin "2") (pinfunction "C2_2") (pintype "passive"))
      (node (ref "C1003") (pin "2") (pinfunction "C2_2") (pintype "passive"))
      (node (ref "C1004") (pin "2") (pinfunction "C2_2") (pintype "passive"))
      (node (ref "C1005") (pin "2") (pinfunction "C2_2") (pintype "passive"))
      (node (ref "C1006") (pin "2") (pinfunction "C2_2") (pintype "passive"))
      (node (ref "C1007") (pin "2") (pinfunction "C2_2") (pintype "passive"))
      (node (ref "C1008") (pin "2") (pinfunction "C2_2") (pintype "passive"))
      (node (ref "C1009") (pin "2") (pinfunction "C2_2") (pintype "passive"))
      (node (ref "C101") (pin "2") (pinfunction "C2_2") (pintype "passive"))
      (node (ref "C1010") (pin "2") (pinfunction "C2_2") (pintype "passive"))
      (node (ref "C1011") (pin "2") (pinfunction "C2_2") (pintype "passive"))
      (node (ref "C1012") (pin "2") (pinfunction "C2_2") (pintype "passive"))
      (node (ref "C1013") (pin "2") (pinfunction "C2_2") (pintype "passive"))
      (node (ref "C1014") (pin "2") (pinfunction "C2_2") (pintype "passive"))
      (node (ref "C102") (pin "2") (pinfunction "C2_2") (pintype "passive"))
      (node (ref "C103") (pin "2") (pinfunction "C2_2") (pintype "passive"))
      (node (ref "C104") (pin "2") (pinfunction "C2_2") (pintype "passive"))
      (node (ref "C105") (pin "2") (pinfunction "C2_2") (pintype "passive"))
      (node (ref "C106") (pin "2") (pinfunction "C2_2") (pintype "passive"))
      (node (ref "C107") (pin "2") (pinfunction "C2_2") (pintype "passive"))
      (node (ref "C108") (pin "2") (pinfunction "C2_2") (pintype "passive"))
      (node (ref "C1101") (pin "2") (pinfunction "C2_2") (pintype "passive"))
      (node (ref "C1102") (pin "2") (pinfunction "C2_2") (pintype "passive"))
      (node (ref "C1103") (pin "2") (pinfunction "C2_2") (pintype "passive"))
      (node (ref "C1104") (pin "2") (pinfunction "C2_2") (pintype "passive"))
      (node (ref "C1105") (pin "2") (pinfunction "C2_2") (pintype "passive"))
      (node (ref "C1106") (pin "2") (pinfunction "C2_2") (pintype "passive"))
      (node (ref "C1107") (pin "2") (pinfunction "C2_2") (pintype "passive"))
      (node (ref "C1108") (pin "2") (pinfunction "C2_2") (pintype "passive"))
      (node (ref "C1109") (pin "2") (pinfunction "C2_2") (pintype "passive"))
      (node (ref "C1110") (pin "2") (pinfunction "C2_2") (pintype "passive"))
      (node (ref "C1111") (pin "2") (pinfunction "C2_2") (pintype "passive"))
      (node (ref "C1112") (pin "2") (pinfunction "C2_2") (pintype "passive"))
      (node (ref "C1113") (pin "2") (pinfunction "C2_2") (pintype "passive"))
      (node (ref "C1114") (pin "2") (pinfunction "C2_2") (pintype "passive"))
      (node (ref "C1115") (pin "2") (pinfunction "C2_2") (pintype "passive"))
      (node (ref "C1116") (pin "2") (pinfunction "C2_2") (pintype "passive"))
      (node (ref "C1117") (pin "2") (pinfunction "C2_2") (pintype "passive"))
      (node (ref "C1118") (pin "2") (pinfunction "C2_2") (pintype "passive"))
      (node (ref "C1119") (pin "2") (pinfunction "C2_2") (pintype "passive"))
      (node (ref "C1122") (pin "2") (pinfunction "C2_2") (pintype "passive"))
      (node (ref "C1123") (pin "2") (pinfunction "C2_2") (pintype "passive"))
      (node (ref "C1124") (pin "2") (pinfunction "C2_2") (pintype "passive"))
      (node (ref "C1125") (pin "2") (pinfunction "C2_2") (pintype "passive"))
      (node (ref "C1126") (pin "2") (pinfunction "C2_2") (pintype "passive"))
      (node (ref "C1127") (pin "2") (pinfunction "C2_2") (pintype "passive"))
      (node (ref "C1128") (pin "2") (pinfunction "C2_2") (pintype "passive"))
      (node (ref "C1129") (pin "2") (pinfunction "C2_2") (pintype "passive"))
      (node (ref "C1130") (pin "2") (pinfunction "C2_2") (pintype "passive"))
      (node (ref "C1201") (pin "2") (pinfunction "C2_2") (pintype "passive"))
      (node (ref "C1202") (pin "2") (pinfunction "C2_2") (pintype "passive"))
      (node (ref "C1203") (pin "2") (pinfunction "C2_2") (pintype "passive"))
      (node (ref "C1204") (pin "2") (pinfunction "C2_2") (pintype "passive"))
      (node (ref "C1205") (pin "2") (pinfunction "C2_2") (pintype "passive"))
      (node (ref "C1206") (pin "2") (pinfunction "C2_2") (pintype "passive"))
      (node (ref "C1207") (pin "2") (pinfunction "C2_2") (pintype "passive"))
      (node (ref "C1208") (pin "2") (pinfunction "C2_2") (pintype "passive"))
      (node (ref "C1209") (pin "2") (pinfunction "C2_2") (pintype "passive"))
      (node (ref "C1210") (pin "2") (pinfunction "C2_2") (pintype "passive"))
      (node (ref "C1211") (pin "2") (pinfunction "C2_2") (pintype "passive"))
      (node (ref "C1212") (pin "2") (pinfunction "C2_2") (pintype "passive"))
      (node (ref "C1213") (pin "2") (pinfunction "C2_2") (pintype "passive"))
      (node (ref "C1214") (pin "2") (pinfunction "C2_2") (pintype "passive"))
      (node (ref "C1215") (pin "2") (pinfunction "C2_2") (pintype "passive"))
      (node (ref "C1216") (pin "2") (pinfunction "C2_2") (pintype "passive"))
      (node (ref "C1217") (pin "2") (pinfunction "C2_2") (pintype "passive"))
      (node (ref "C1218") (pin "2") (pinfunction "C2_2") (pintype "passive"))
      (node (ref "C1219") (pin "2") (pinfunction "C2_2") (pintype "passive"))
      (node (ref "C1220") (pin "2") (pinfunction "C2_2") (pintype "passive"))
      (node (ref "C1221") (pin "2") (pinfunction "C2_2") (pintype "passive"))
      (node (ref "C1222") (pin "2") (pinfunction "C2_2") (pintype "passive"))
      (node (ref "C1223") (pin "2") (pinfunction "C2_2") (pintype "passive"))
      (node (ref "C1224") (pin "2") (pinfunction "C2_2") (pintype "passive"))
      (node (ref "C1225") (pin "2") (pinfunction "C2_2") (pintype "passive"))
      (node (ref "C1226") (pin "2") (pinfunction "C2_2") (pintype "passive"))
      (node (ref "C1227") (pin "2") (pinfunction "C2_2") (pintype "passive"))
      (node (ref "C1228") (pin "2") (pinfunction "C2_2") (pintype "passive"))
      (node (ref "C1229") (pin "2") (pinfunction "C2_2") (pintype "passive"))
      (node (ref "C1230") (pin "2") (pinfunction "C2_2") (pintype "passive"))
      (node (ref "C1231") (pin "2") (pinfunction "C2_2") (pintype "passive"))
      (node (ref "C1232") (pin "2") (pinfunction "C2_2") (pintype "passive"))
      (node (ref "C1233") (pin "2") (pinfunction "C2_2") (pintype "passive"))
      (node (ref "C1234") (pin "2") (pinfunction "C2_2") (pintype "passive"))
      (node (ref "C1235") (pin "2") (pinfunction "C2_2") (pintype "passive"))
      (node (ref "C1236") (pin "2") (pinfunction "C2_2") (pintype "passive"))
      (node (ref "C1237") (pin "2") (pinfunction "C2_2") (pintype "passive"))
      (node (ref "C1238") (pin "2") (pinfunction "C2_2") (pintype "passive"))
      (node (ref "C1239") (pin "2") (pinfunction "C2_2") (pintype "passive"))
      (node (ref "C1240") (pin "2") (pinfunction "C2_2") (pintype "passive"))
      (node (ref "C1241") (pin "2") (pinfunction "C2_2") (pintype "passive"))
      (node (ref "C1242") (pin "2") (pinfunction "C2_2") (pintype "passive"))
      (node (ref "C1243") (pin "2") (pinfunction "C2_2") (pintype "passive"))
      (node (ref "C1244") (pin "2") (pinfunction "C2_2") (pintype "passive"))
      (node (ref "C1245") (pin "2") (pinfunction "C2_2") (pintype "passive"))
      (node (ref "C1246") (pin "2") (pinfunction "C2_2") (pintype "passive"))
      (node (ref "C1247") (pin "2") (pinfunction "C2_2") (pintype "passive"))
      (node (ref "C1248") (pin "2") (pinfunction "C2_2") (pintype "passive"))
      (node (ref "C1249") (pin "2") (pinfunction "C2_2") (pintype "passive"))
      (node (ref "C1250") (pin "2") (pinfunction "C2_2") (pintype "passive"))
      (node (ref "C1251") (pin "2") (pinfunction "C2_2") (pintype "passive"))
      (node (ref "C1252") (pin "2") (pinfunction "C2_2") (pintype "passive"))
      (node (ref "C1253") (pin "2") (pinfunction "C2_2") (pintype "passive"))
      (node (ref "C1254") (pin "2") (pinfunction "C2_2") (pintype "passive"))
      (node (ref "C1255") (pin "2") (pinfunction "C2_2") (pintype "passive"))
      (node (ref "C1256") (pin "2") (pinfunction "C2_2") (pintype "passive"))
      (node (ref "C1257") (pin "2") (pinfunction "C2_2") (pintype "passive"))
      (node (ref "C1258") (pin "2") (pinfunction "C2_2") (pintype "passive"))
      (node (ref "C1259") (pin "2") (pinfunction "C2_2") (pintype "passive"))
      (node (ref "C201") (pin "2") (pinfunction "C2_2") (pintype "passive"))
      (node (ref "C202") (pin "2") (pinfunction "C2_2") (pintype "passive"))
      (node (ref "C203") (pin "2") (pinfunction "C2_2") (pintype "passive"))
      (node (ref "C204") (pin "2") (pinfunction "C2_2") (pintype "passive"))
      (node (ref "C205") (pin "2") (pinfunction "C2_2") (pintype "passive"))
      (node (ref "C206") (pin "2") (pinfunction "C2_2") (pintype "passive"))
      (node (ref "C207") (pin "2") (pinfunction "C2_2") (pintype "passive"))
      (node (ref "C208") (pin "2") (pinfunction "C2_2") (pintype "passive"))
      (node (ref "C209") (pin "2") (pinfunction "C2_2") (pintype "passive"))
      (node (ref "C210") (pin "2") (pinfunction "C2_2") (pintype "passive"))
      (node (ref "C211") (pin "2") (pinfunction "C2_2") (pintype "passive"))
      (node (ref "C212") (pin "2") (pinfunction "C2_2") (pintype "passive"))
      (node (ref "C213") (pin "2") (pinfunction "C2_2") (pintype "passive"))
      (node (ref "C214") (pin "2") (pinfunction "C2_2") (pintype "passive"))
      (node (ref "C215") (pin "2") (pinfunction "C2_2") (pintype "passive"))
      (node (ref "C216") (pin "2") (pinfunction "C2_2") (pintype "passive"))
      (node (ref "C217") (pin "2") (pinfunction "C2_2") (pintype "passive"))
      (node (ref "C218") (pin "2") (pinfunction "C2_2") (pintype "passive"))
      (node (ref "C219") (pin "2") (pinfunction "C2_2") (pintype "passive"))
      (node (ref "C220") (pin "2") (pinfunction "C2_2") (pintype "passive"))
      (node (ref "C221") (pin "2") (pinfunction "C2_2") (pintype "passive"))
      (node (ref "C222") (pin "2") (pinfunction "C2_2") (pintype "passive"))
      (node (ref "C223") (pin "2") (pinfunction "C2_2") (pintype "passive"))
      (node (ref "C224") (pin "2") (pinfunction "C2_2") (pintype "passive"))
      (node (ref "C225") (pin "2") (pinfunction "C2_2") (pintype "passive"))
      (node (ref "C226") (pin "2") (pinfunction "C2_2") (pintype "passive"))
      (node (ref "C227") (pin "2") (pinfunction "C2_2") (pintype "passive"))
      (node (ref "C228") (pin "2") (pinfunction "C2_2") (pintype "passive"))
      (node (ref "C229") (pin "2") (pinfunction "C2_2") (pintype "passive"))
      (node (ref "C230") (pin "2") (pinfunction "C2_2") (pintype "passive"))
      (node (ref "C231") (pin "2") (pinfunction "C2_2") (pintype "passive"))
      (node (ref "C232") (pin "2") (pinfunction "C2_2") (pintype "passive"))
      (node (ref "C233") (pin "2") (pinfunction "C2_2") (pintype "passive"))
      (node (ref "C234") (pin "2") (pinfunction "C2_2") (pintype "passive"))
      (node (ref "C235") (pin "2") (pinfunction "C2_2") (pintype "passive"))
      (node (ref "C236") (pin "2") (pinfunction "C2_2") (pintype "passive"))
      (node (ref "C237") (pin "2") (pinfunction "C2_2") (pintype "passive"))
      (node (ref "C238") (pin "2") (pinfunction "C2_2") (pintype "passive"))
      (node (ref "C239") (pin "2") (pinfunction "C2_2") (pintype "passive"))
      (node (ref "C240") (pin "2") (pinfunction "C2_2") (pintype "passive"))
      (node (ref "C241") (pin "2") (pinfunction "C2_2") (pintype "passive"))
      (node (ref "C242") (pin "2") (pinfunction "C2_2") (pintype "passive"))
      (node (ref "C243") (pin "2") (pinfunction "C2_2") (pintype "passive"))
      (node (ref "C244") (pin "2") (pinfunction "C2_2") (pintype "passive"))
      (node (ref "C245") (pin "2") (pinfunction "C2_2") (pintype "passive"))
      (node (ref "C246") (pin "2") (pinfunction "C2_2") (pintype "passive"))
      (node (ref "C247") (pin "2") (pinfunction "C2_2") (pintype "passive"))
      (node (ref "C248") (pin "2") (pinfunction "C2_2") (pintype "passive"))
      (node (ref "C249") (pin "2") (pinfunction "C2_2") (pintype "passive"))
      (node (ref "C250") (pin "2") (pinfunction "C2_2") (pintype "passive"))
      (node (ref "C251") (pin "2") (pinfunction "C2_2") (pintype "passive"))
      (node (ref "C252") (pin "2") (pinfunction "C2_2") (pintype "passive"))
      (node (ref "C253") (pin "2") (pinfunction "C2_2") (pintype "passive"))
      (node (ref "C254") (pin "2") (pinfunction "C2_2") (pintype "passive"))
      (node (ref "C255") (pin "2") (pinfunction "C2_2") (pintype "passive"))
      (node (ref "C256") (pin "2") (pinfunction "C2_2") (pintype "passive"))
      (node (ref "C257") (pin "2") (pinfunction "C2_2") (pintype "passive"))
      (node (ref "C258") (pin "2") (pinfunction "C2_2") (pintype "passive"))
      (node (ref "C259") (pin "2") (pinfunction "C2_2") (pintype "passive"))
      (node (ref "C260") (pin "2") (pinfunction "C2_2") (pintype "passive"))
      (node (ref "C261") (pin "2") (pinfunction "C2_2") (pintype "passive"))
      (node (ref "C262") (pin "2") (pinfunction "C2_2") (pintype "passive"))
      (node (ref "C263") (pin "2") (pinfunction "C2_2") (pintype "passive"))
      (node (ref "C264") (pin "2") (pinfunction "C2_2") (pintype "passive"))
      (node (ref "C301") (pin "2") (pinfunction "C2_2") (pintype "passive"))
      (node (ref "C302") (pin "2") (pinfunction "C2_2") (pintype "passive"))
      (node (ref "C303") (pin "2") (pinfunction "C2_2") (pintype "passive"))
      (node (ref "C304") (pin "2") (pinfunction "C2_2") (pintype "passive"))
      (node (ref "C305") (pin "2") (pinfunction "C2_2") (pintype "passive"))
      (node (ref "C306") (pin "2") (pinfunction "C2_2") (pintype "passive"))
      (node (ref "C307") (pin "2") (pinfunction "C2_2") (pintype "passive"))
      (node (ref "C308") (pin "2") (pinfunction "C2_2") (pintype "passive"))
      (node (ref "C309") (pin "2") (pinfunction "C2_2") (pintype "passive"))
      (node (ref "C310") (pin "2") (pinfunction "C2_2") (pintype "passive"))
      (node (ref "C311") (pin "2") (pinfunction "C2_2") (pintype "passive"))
      (node (ref "C312") (pin "2") (pinfunction "C2_2") (pintype "passive"))
      (node (ref "C313") (pin "2") (pinfunction "C2_2") (pintype "passive"))
      (node (ref "C314") (pin "2") (pinfunction "C2_2") (pintype "passive"))
      (node (ref "C315") (pin "2") (pinfunction "C2_2") (pintype "passive"))
      (node (ref "C316") (pin "2") (pinfunction "C2_2") (pintype "passive"))
      (node (ref "C317") (pin "2") (pinfunction "C2_2") (pintype "passive"))
      (node (ref "C318") (pin "2") (pinfunction "C2_2") (pintype "passive"))
      (node (ref "C319") (pin "2") (pinfunction "C2_2") (pintype "passive"))
      (node (ref "C320") (pin "2") (pinfunction "C2_2") (pintype "passive"))
      (node (ref "C321") (pin "2") (pinfunction "C2_2") (pintype "passive"))
      (node (ref "C322") (pin "2") (pinfunction "C2_2") (pintype "passive"))
      (node (ref "C324") (pin "2") (pinfunction "C2_2") (pintype "passive"))
      (node (ref "C325") (pin "2") (pinfunction "C2_2") (pintype "passive"))
      (node (ref "C326") (pin "2") (pinfunction "C2_2") (pintype "passive"))
      (node (ref "C327") (pin "2") (pinfunction "C2_2") (pintype "passive"))
      (node (ref "C328") (pin "2") (pinfunction "C2_2") (pintype "passive"))
      (node (ref "C329") (pin "2") (pinfunction "C2_2") (pintype "passive"))
      (node (ref "C330") (pin "2") (pinfunction "C2_2") (pintype "passive"))
      (node (ref "C331") (pin "2") (pinfunction "C2_2") (pintype "passive"))
      (node (ref "C401") (pin "2") (pinfunction "C2_2") (pintype "passive"))
      (node (ref "C402") (pin "2") (pinfunction "C2_2") (pintype "passive"))
      (node (ref "C404") (pin "2") (pinfunction "C2_2") (pintype "passive"))
      (node (ref "C405") (pin "2") (pinfunction "C2_2") (pintype "passive"))
      (node (ref "C406") (pin "2") (pinfunction "C2_2") (pintype "passive"))
      (node (ref "C407") (pin "2") (pinfunction "C2_2") (pintype "passive"))
      (node (ref "C408") (pin "2") (pinfunction "C2_2") (pintype "passive"))
      (node (ref "C409") (pin "2") (pinfunction "C2_2") (pintype "passive"))
      (node (ref "C410") (pin "2") (pinfunction "C2_2") (pintype "passive"))
      (node (ref "C411") (pin "2") (pinfunction "C2_2") (pintype "passive"))
      (node (ref "C412") (pin "2") (pinfunction "C2_2") (pintype "passive"))
      (node (ref "C413") (pin "2") (pinfunction "C2_2") (pintype "passive"))
      (node (ref "C414") (pin "2") (pinfunction "C2_2") (pintype "passive"))
      (node (ref "C415") (pin "2") (pinfunction "C2_2") (pintype "passive"))
      (node (ref "C416") (pin "2") (pinfunction "C2_2") (pintype "passive"))
      (node (ref "C417") (pin "2") (pinfunction "C2_2") (pintype "passive"))
      (node (ref "C418") (pin "2") (pinfunction "C2_2") (pintype "passive"))
      (node (ref "C419") (pin "2") (pinfunction "C2_2") (pintype "passive"))
      (node (ref "C420") (pin "2") (pinfunction "C2_2") (pintype "passive"))
      (node (ref "C422") (pin "2") (pinfunction "C2_2") (pintype "passive"))
      (node (ref "C424") (pin "2") (pinfunction "C2_2") (pintype "passive"))
      (node (ref "C503") (pin "2") (pinfunction "C2_2") (pintype "passive"))
      (node (ref "C504") (pin "2") (pinfunction "C2_2") (pintype "passive"))
      (node (ref "C505") (pin "2") (pinfunction "C2_2") (pintype "passive"))
      (node (ref "C506") (pin "2") (pinfunction "C2_2") (pintype "passive"))
      (node (ref "C507") (pin "2") (pinfunction "C2_2") (pintype "passive"))
      (node (ref "C508") (pin "2") (pinfunction "C2_2") (pintype "passive"))
      (node (ref "C517") (pin "2") (pinfunction "C2_2") (pintype "passive"))
      (node (ref "C518") (pin "2") (pinfunction "C2_2") (pintype "passive"))
      (node (ref "C519") (pin "2") (pinfunction "C2_2") (pintype "passive"))
      (node (ref "C520") (pin "2") (pinfunction "C2_2") (pintype "passive"))
      (node (ref "C521") (pin "2") (pinfunction "C2_2") (pintype "passive"))
      (node (ref "C522") (pin "2") (pinfunction "C2_2") (pintype "passive"))
      (node (ref "C523") (pin "2") (pinfunction "C2_2") (pintype "passive"))
      (node (ref "C524") (pin "2") (pinfunction "C2_2") (pintype "passive"))
      (node (ref "C525") (pin "2") (pinfunction "C2_2") (pintype "passive"))
      (node (ref "C526") (pin "2") (pinfunction "C2_2") (pintype "passive"))
      (node (ref "C527") (pin "2") (pinfunction "C2_2") (pintype "passive"))
      (node (ref "C528") (pin "2") (pinfunction "C2_2") (pintype "passive"))
      (node (ref "C534") (pin "2") (pinfunction "C2_2") (pintype "passive"))
      (node (ref "C535") (pin "2") (pinfunction "C2_2") (pintype "passive"))
      (node (ref "C536") (pin "2") (pinfunction "C2_2") (pintype "passive"))
      (node (ref "C537") (pin "2") (pinfunction "C2_2") (pintype "passive"))
      (node (ref "C540") (pin "2") (pinfunction "C2_2") (pintype "passive"))
      (node (ref "C541") (pin "2") (pinfunction "C2_2") (pintype "passive"))
      (node (ref "C542") (pin "2") (pinfunction "C2_2") (pintype "passive"))
      (node (ref "C543") (pin "2") (pinfunction "C2_2") (pintype "passive"))
      (node (ref "C548") (pin "2") (pinfunction "C2_2") (pintype "passive"))
      (node (ref "C549") (pin "2") (pinfunction "C2_2") (pintype "passive"))
      (node (ref "C551") (pin "2") (pinfunction "C2_2") (pintype "passive"))
      (node (ref "C552") (pin "2") (pinfunction "C2_2") (pintype "passive"))
      (node (ref "C602") (pin "2") (pinfunction "C2_2") (pintype "passive"))
      (node (ref "C603") (pin "2") (pinfunction "C2_2") (pintype "passive"))
      (node (ref "C604") (pin "2") (pinfunction "C2_2") (pintype "passive"))
      (node (ref "C605") (pin "2") (pinfunction "C2_2") (pintype "passive"))
      (node (ref "C606") (pin "2") (pinfunction "C2_2") (pintype "passive"))
      (node (ref "C607") (pin "2") (pinfunction "C2_2") (pintype "passive"))
      (node (ref "C608") (pin "2") (pinfunction "C2_2") (pintype "passive"))
      (node (ref "C609") (pin "2") (pinfunction "C2_2") (pintype "passive"))
      (node (ref "C610") (pin "2") (pinfunction "C2_2") (pintype "passive"))
      (node (ref "C611") (pin "2") (pinfunction "C2_2") (pintype "passive"))
      (node (ref "C612") (pin "2") (pinfunction "C2_2") (pintype "passive"))
      (node (ref "C613") (pin "2") (pinfunction "C2_2") (pintype "passive"))
      (node (ref "C614") (pin "2") (pinfunction "C2_2") (pintype "passive"))
      (node (ref "C615") (pin "2") (pinfunction "C2_2") (pintype "passive"))
      (node (ref "C616") (pin "2") (pinfunction "C2_2") (pintype "passive"))
      (node (ref "C617") (pin "2") (pinfunction "C2_2") (pintype "passive"))
      (node (ref "C618") (pin "2") (pinfunction "C2_2") (pintype "passive"))
      (node (ref "C619") (pin "2") (pinfunction "C2_2") (pintype "passive"))
      (node (ref "C620") (pin "2") (pinfunction "C2_2") (pintype "passive"))
      (node (ref "C621") (pin "2") (pinfunction "C2_2") (pintype "passive"))
      (node (ref "C622") (pin "2") (pinfunction "C2_2") (pintype "passive"))
      (node (ref "C701") (pin "2") (pinfunction "C2_2") (pintype "passive"))
      (node (ref "C702") (pin "2") (pinfunction "C2_2") (pintype "passive"))
      (node (ref "C703") (pin "2") (pinfunction "C2_2") (pintype "passive"))
      (node (ref "C704") (pin "2") (pinfunction "C2_2") (pintype "passive"))
      (node (ref "C705") (pin "2") (pinfunction "C2_2") (pintype "passive"))
      (node (ref "C706") (pin "2") (pinfunction "C2_2") (pintype "passive"))
      (node (ref "C707") (pin "2") (pinfunction "C2_2") (pintype "passive"))
      (node (ref "C708") (pin "2") (pinfunction "C2_2") (pintype "passive"))
      (node (ref "C709") (pin "2") (pinfunction "C2_2") (pintype "passive"))
      (node (ref "C710") (pin "2") (pinfunction "C2_2") (pintype "passive"))
      (node (ref "C711") (pin "2") (pinfunction "C2_2") (pintype "passive"))
      (node (ref "C716") (pin "2") (pinfunction "C2_2") (pintype "passive"))
      (node (ref "C721") (pin "2") (pinfunction "C2_2") (pintype "passive"))
      (node (ref "C722") (pin "2") (pinfunction "C2_2") (pintype "passive"))
      (node (ref "C723") (pin "2") (pinfunction "C2_2") (pintype "passive"))
      (node (ref "C724") (pin "2") (pinfunction "C2_2") (pintype "passive"))
      (node (ref "C813") (pin "2") (pinfunction "C2_2") (pintype "passive"))
      (node (ref "C901") (pin "2") (pinfunction "C2_2") (pintype "passive"))
      (node (ref "C902") (pin "2") (pinfunction "C2_2") (pintype "passive"))
      (node (ref "C903") (pin "2") (pinfunction "C2_2") (pintype "passive"))
      (node (ref "C904") (pin "2") (pinfunction "C2_2") (pintype "passive"))
      (node (ref "C905") (pin "2") (pinfunction "C2_2") (pintype "passive"))
      (node (ref "C906") (pin "2") (pinfunction "C2_2") (pintype "passive"))
      (node (ref "C908") (pin "2") (pinfunction "C2_2") (pintype "passive"))
      (node (ref "C909") (pin "2") (pinfunction "C2_2") (pintype "passive"))
      (node (ref "CON101") (pin "10") (pinfunction "S_10") (pintype "passive"))
      (node (ref "CON101") (pin "13") (pinfunction "S_13") (pintype "passive"))
      (node (ref "CON101") (pin "16") (pinfunction "S_16") (pintype "passive"))
      (node (ref "CON101") (pin "19") (pinfunction "S_19") (pintype "passive"))
      (node (ref "CON101") (pin "22") (pinfunction "S_22") (pintype "passive"))
      (node (ref "CON101") (pin "4") (pinfunction "S_4") (pintype "passive"))
      (node (ref "CON101") (pin "7") (pinfunction "S_7") (pintype "passive"))
      (node (ref "CON102") (pin "10") (pinfunction "S_10") (pintype "passive"))
      (node (ref "CON102") (pin "13") (pinfunction "S_13") (pintype "passive"))
      (node (ref "CON102") (pin "16") (pinfunction "S_16") (pintype "passive"))
      (node (ref "CON102") (pin "19") (pinfunction "S_19") (pintype "passive"))
      (node (ref "CON102") (pin "22") (pinfunction "S_22") (pintype "passive"))
      (node (ref "CON102") (pin "4") (pinfunction "S_4") (pintype "passive"))
      (node (ref "CON102") (pin "7") (pinfunction "S_7") (pintype "passive"))
      (node (ref "CON1101") (pin "P$1") (pinfunction "S_P$1") (pintype "passive"))
      (node (ref "CON701") (pin "4") (pinfunction "S_4") (pintype "passive"))
      (node (ref "CON801") (pin "A12") (pinfunction "S_A12") (pintype "passive"))
      (node (ref "CON801") (pin "A15") (pinfunction "S_A15") (pintype "passive"))
      (node (ref "CON801") (pin "A18") (pinfunction "S_A18") (pintype "passive"))
      (node (ref "CON801") (pin "A20") (pinfunction "S_A20") (pintype "passive"))
      (node (ref "CON801") (pin "A23") (pinfunction "S_A23") (pintype "passive"))
      (node (ref "CON801") (pin "A24") (pinfunction "S_A24") (pintype "passive"))
      (node (ref "CON801") (pin "A27") (pinfunction "S_A27") (pintype "passive"))
      (node (ref "CON801") (pin "A28") (pinfunction "S_A28") (pintype "passive"))
      (node (ref "CON801") (pin "A31") (pinfunction "S_A31") (pintype "passive"))
      (node (ref "CON801") (pin "A4") (pinfunction "S_A4") (pintype "passive"))
      (node (ref "CON801") (pin "B13") (pinfunction "S_B13") (pintype "passive"))
      (node (ref "CON801") (pin "B16") (pinfunction "S_B16") (pintype "passive"))
      (node (ref "CON801") (pin "B18") (pinfunction "S_B18") (pintype "passive"))
      (node (ref "CON801") (pin "B21") (pinfunction "S_B21") (pintype "passive"))
      (node (ref "CON801") (pin "B22") (pinfunction "S_B22") (pintype "passive"))
      (node (ref "CON801") (pin "B25") (pinfunction "S_B25") (pintype "passive"))
      (node (ref "CON801") (pin "B26") (pinfunction "S_B26") (pintype "passive"))
      (node (ref "CON801") (pin "B29") (pinfunction "S_B29") (pintype "passive"))
      (node (ref "CON801") (pin "B32") (pinfunction "S_B32") (pintype "passive"))
      (node (ref "CON801") (pin "B4") (pinfunction "S_B4") (pintype "passive"))
      (node (ref "CON801") (pin "B7") (pinfunction "S_B7") (pintype "passive"))
      (node (ref "D1001") (pin "3") (pinfunction "A_3") (pintype "bidirectional"))
      (node (ref "D1002") (pin "A") (pinfunction "A_A") (pintype "passive"))
      (node (ref "D1004") (pin "C") (pinfunction "C_C") (pintype "passive"))
      (node (ref "D102") (pin "C") (pinfunction "C_C") (pintype "passive"))
      (node (ref "D1104") (pin "C") (pinfunction "C_C") (pintype "passive"))
      (node (ref "D1105") (pin "A") (pinfunction "A_A") (pintype "passive"))
      (node (ref "D201") (pin "C") (pinfunction "C_C") (pintype "passive"))
      (node (ref "D202") (pin "C") (pinfunction "C_C") (pintype "passive"))
      (node (ref "D501") (pin "2") (pinfunction "2_2") (pintype "passive"))
      (node (ref "D502") (pin "2") (pinfunction "2_2") (pintype "passive"))
      (node (ref "D503") (pin "2") (pinfunction "2_2") (pintype "passive"))
      (node (ref "D504") (pin "2") (pinfunction "2_2") (pintype "passive"))
      (node (ref "D505") (pin "C") (pinfunction "C_C") (pintype "passive"))
      (node (ref "D506") (pin "C") (pinfunction "C_C") (pintype "passive"))
      (node (ref "D507") (pin "C") (pinfunction "C_C") (pintype "passive"))
      (node (ref "D508") (pin "C") (pinfunction "C_C") (pintype "passive"))
      (node (ref "D509") (pin "2") (pinfunction "2_2") (pintype "passive"))
      (node (ref "D510") (pin "2") (pinfunction "2_2") (pintype "passive"))
      (node (ref "D511") (pin "2") (pinfunction "2_2") (pintype "passive"))
      (node (ref "D512") (pin "2") (pinfunction "2_2") (pintype "passive"))
      (node (ref "D601") (pin "2") (pinfunction "2_2") (pintype "passive"))
      (node (ref "D602") (pin "2") (pinfunction "2_2") (pintype "passive"))
      (node (ref "J101") (pin "10") (pinfunction "CHS_GND_10") (pintype "bidirectional"))
      (node (ref "J101") (pin "SHIELD@0") (pinfunction "CHS_GND_SHIELD@0") (pintype "bidirectional"))
      (node (ref "J101") (pin "SHIELD@1") (pinfunction "CHS_GND_SHIELD@1") (pintype "bidirectional"))
      (node (ref "J701") (pin "1") (pinfunction "S_1") (pintype "bidirectional"))
      (node (ref "J702") (pin "1") (pinfunction "S_1") (pintype "bidirectional"))
      (node (ref "J703") (pin "1") (pinfunction "S_1") (pintype "bidirectional"))
      (node (ref "JP101") (pin "3") (pinfunction "S_3") (pintype "passive"))
      (node (ref "JP1101") (pin "3") (pinfunction "S_3") (pintype "passive"))
      (node (ref "JP1101") (pin "4") (pinfunction "S_4") (pintype "passive"))
      (node (ref "JP201") (pin "1") (pinfunction "S_1") (pintype "passive"))
      (node (ref "JP201") (pin "5") (pinfunction "S_5") (pintype "passive"))
      (node (ref "JP202") (pin "6") (pinfunction "S_6") (pintype "passive"))
      (node (ref "M701") (pin "3") (pinfunction "GND_3") (pintype "passive"))
      (node (ref "M702") (pin "2") (pinfunction "SEL_2") (pintype "passive"))
      (node (ref "M702") (pin "3") (pinfunction "GND_3") (pintype "passive"))
      (node (ref "Q101") (pin "2") (pinfunction "S_2") (pintype "passive"))
      (node (ref "Q102") (pin "2") (pinfunction "S_2") (pintype "passive"))
      (node (ref "Q1101") (pin "2") (pinfunction "S_2") (pintype "passive"))
      (node (ref "Q1103") (pin "2") (pinfunction "S_2") (pintype "passive"))
      (node (ref "Q1106") (pin "2") (pinfunction "S_2") (pintype "passive"))
      (node (ref "R1001") (pin "1") (pinfunction "1_1") (pintype "passive"))
      (node (ref "R1003") (pin "1") (pinfunction "1_1") (pintype "passive"))
      (node (ref "R1006") (pin "1") (pinfunction "1_1") (pintype "passive"))
      (node (ref "R1009") (pin "1") (pinfunction "1_1") (pintype "passive"))
      (node (ref "R1010") (pin "1") (pinfunction "1_1") (pintype "passive"))
      (node (ref "R1012") (pin "1") (pinfunction "1_1") (pintype "passive"))
      (node (ref "R102") (pin "1") (pinfunction "1_1") (pintype "passive"))
      (node (ref "R104") (pin "1") (pinfunction "1_1") (pintype "passive"))
      (node (ref "R105") (pin "1") (pinfunction "1_1") (pintype "passive"))
      (node (ref "R107") (pin "1") (pinfunction "1_1") (pintype "passive"))
      (node (ref "R109") (pin "1") (pinfunction "1_1") (pintype "passive"))
      (node (ref "R110") (pin "1") (pinfunction "1_1") (pintype "passive"))
      (node (ref "R1102") (pin "1") (pinfunction "1_1") (pintype "passive"))
      (node (ref "R1104") (pin "1") (pinfunction "1_1") (pintype "passive"))
      (node (ref "R1105") (pin "1") (pinfunction "1_1") (pintype "passive"))
      (node (ref "R1109") (pin "1") (pinfunction "1_1") (pintype "passive"))
      (node (ref "R1111") (pin "1") (pinfunction "1_1") (pintype "passive"))
      (node (ref "R1112") (pin "1") (pinfunction "1_1") (pintype "passive"))
      (node (ref "R1115") (pin "1") (pinfunction "1_1") (pintype "passive"))
      (node (ref "R112") (pin "1") (pinfunction "1_1") (pintype "passive"))
      (node (ref "R1125") (pin "1") (pinfunction "1_1") (pintype "passive"))
      (node (ref "R1126") (pin "1") (pinfunction "1_1") (pintype "passive"))
      (node (ref "R1127") (pin "1") (pinfunction "1_1") (pintype "passive"))
      (node (ref "R1128") (pin "1") (pinfunction "1_1") (pintype "passive"))
      (node (ref "R1203") (pin "1") (pinfunction "1_1") (pintype "passive"))
      (node (ref "R1206") (pin "1") (pinfunction "1_1") (pintype "passive"))
      (node (ref "R1209") (pin "1") (pinfunction "1_1") (pintype "passive"))
      (node (ref "R1213") (pin "1") (pinfunction "1_1") (pintype "passive"))
      (node (ref "R1215") (pin "1") (pinfunction "1_1") (pintype "passive"))
      (node (ref "R216") (pin "1") (pinfunction "1_1") (pintype "passive"))
      (node (ref "R301") (pin "1") (pinfunction "1_1") (pintype "passive"))
      (node (ref "R302") (pin "1") (pinfunction "1_1") (pintype "passive"))
      (node (ref "R402") (pin "1") (pinfunction "1_1") (pintype "passive"))
      (node (ref "R403") (pin "1") (pinfunction "1_1") (pintype "passive"))
      (node (ref "R404") (pin "1") (pinfunction "1_1") (pintype "passive"))
      (node (ref "R405") (pin "1") (pinfunction "1_1") (pintype "passive"))
      (node (ref "R501") (pin "1") (pinfunction "1_1") (pintype "passive"))
      (node (ref "R502") (pin "1") (pinfunction "1_1") (pintype "passive"))
      (node (ref "R507") (pin "1") (pinfunction "1_1") (pintype "passive"))
      (node (ref "R508") (pin "1") (pinfunction "1_1") (pintype "passive"))
      (node (ref "R513") (pin "1") (pinfunction "1_1") (pintype "passive"))
      (node (ref "R515") (pin "1") (pinfunction "1_1") (pintype "passive"))
      (node (ref "R601") (pin "1") (pinfunction "1_1") (pintype "passive"))
      (node (ref "R602") (pin "1") (pinfunction "1_1") (pintype "passive"))
      (node (ref "R603") (pin "1") (pinfunction "1_1") (pintype "passive"))
      (node (ref "R605") (pin "1") (pinfunction "1_1") (pintype "passive"))
      (node (ref "R607") (pin "1") (pinfunction "1_1") (pintype "passive"))
      (node (ref "R614") (pin "1") (pinfunction "1_1") (pintype "passive"))
      (node (ref "R615") (pin "1") (pinfunction "1_1") (pintype "passive"))
      (node (ref "R701") (pin "1") (pinfunction "1_1") (pintype "passive"))
      (node (ref "R702") (pin "1") (pinfunction "1_1") (pintype "passive"))
      (node (ref "R703") (pin "1") (pinfunction "1_1") (pintype "passive"))
      (node (ref "R705") (pin "1") (pinfunction "1_1") (pintype "passive"))
      (node (ref "R707") (pin "1") (pinfunction "1_1") (pintype "passive"))
      (node (ref "R709") (pin "1") (pinfunction "1_1") (pintype "passive"))
      (node (ref "R711") (pin "1") (pinfunction "1_1") (pintype "passive"))
      (node (ref "R901") (pin "1") (pinfunction "1_1") (pintype "passive"))
      (node (ref "R903") (pin "1") (pinfunction "1_1") (pintype "passive"))
      (node (ref "RFCON101") (pin "P$1") (pinfunction "GND_P$1") (pintype "bidirectional"))
      (node (ref "RFCON101") (pin "P$2") (pinfunction "GND_P$2") (pintype "bidirectional"))
      (node (ref "RFCON501") (pin "GND@0") (pinfunction "GND_GND@0") (pintype "bidirectional"))
      (node (ref "RFCON501") (pin "GND@1") (pinfunction "GND_GND@1") (pintype "bidirectional"))
      (node (ref "RFCON501") (pin "GND@2") (pinfunction "GND_GND@2") (pintype "bidirectional"))
      (node (ref "RFCON501") (pin "GND@3") (pinfunction "GND_GND@3") (pintype "bidirectional"))
      (node (ref "RFCON502") (pin "GND@0") (pinfunction "GND_GND@0") (pintype "bidirectional"))
      (node (ref "RFCON502") (pin "GND@1") (pinfunction "GND_GND@1") (pintype "bidirectional"))
      (node (ref "RFCON502") (pin "GND@2") (pinfunction "GND_GND@2") (pintype "bidirectional"))
      (node (ref "RFCON502") (pin "GND@3") (pinfunction "GND_GND@3") (pintype "bidirectional"))
      (node (ref "RFCON503") (pin "GND@0") (pinfunction "GND_GND@0") (pintype "bidirectional"))
      (node (ref "RFCON503") (pin "GND@1") (pinfunction "GND_GND@1") (pintype "bidirectional"))
      (node (ref "RFCON503") (pin "GND@2") (pinfunction "GND_GND@2") (pintype "bidirectional"))
      (node (ref "RFCON503") (pin "GND@3") (pinfunction "GND_GND@3") (pintype "bidirectional"))
      (node (ref "RFCON504") (pin "GND@0") (pinfunction "GND_GND@0") (pintype "bidirectional"))
      (node (ref "RFCON504") (pin "GND@1") (pinfunction "GND_GND@1") (pintype "bidirectional"))
      (node (ref "RFCON504") (pin "GND@2") (pinfunction "GND_GND@2") (pintype "bidirectional"))
      (node (ref "RFCON504") (pin "GND@3") (pinfunction "GND_GND@3") (pintype "bidirectional"))
      (node (ref "RFCON505") (pin "P$1") (pinfunction "GND_P$1") (pintype "bidirectional"))
      (node (ref "RFCON505") (pin "P$2") (pinfunction "GND_P$2") (pintype "bidirectional"))
      (node (ref "RFCON506") (pin "P$1") (pinfunction "GND_P$1") (pintype "bidirectional"))
      (node (ref "RFCON506") (pin "P$2") (pinfunction "GND_P$2") (pintype "bidirectional"))
      (node (ref "RFCON507") (pin "GND@0") (pinfunction "GND_GND@0") (pintype "bidirectional"))
      (node (ref "RFCON507") (pin "GND@1") (pinfunction "GND_GND@1") (pintype "bidirectional"))
      (node (ref "RFCON507") (pin "GND@2") (pinfunction "GND_GND@2") (pintype "bidirectional"))
      (node (ref "RFCON507") (pin "GND@3") (pinfunction "GND_GND@3") (pintype "bidirectional"))
      (node (ref "RFCON508") (pin "GND@0") (pinfunction "GND_GND@0") (pintype "bidirectional"))
      (node (ref "RFCON508") (pin "GND@1") (pinfunction "GND_GND@1") (pintype "bidirectional"))
      (node (ref "RFCON508") (pin "GND@2") (pinfunction "GND_GND@2") (pintype "bidirectional"))
      (node (ref "RFCON508") (pin "GND@3") (pinfunction "GND_GND@3") (pintype "bidirectional"))
      (node (ref "RFCON509") (pin "GND@0") (pinfunction "GND_GND@0") (pintype "bidirectional"))
      (node (ref "RFCON509") (pin "GND@1") (pinfunction "GND_GND@1") (pintype "bidirectional"))
      (node (ref "RFCON509") (pin "GND@2") (pinfunction "GND_GND@2") (pintype "bidirectional"))
      (node (ref "RFCON509") (pin "GND@3") (pinfunction "GND_GND@3") (pintype "bidirectional"))
      (node (ref "RFCON510") (pin "GND@0") (pinfunction "GND_GND@0") (pintype "bidirectional"))
      (node (ref "RFCON510") (pin "GND@1") (pinfunction "GND_GND@1") (pintype "bidirectional"))
      (node (ref "RFCON510") (pin "GND@2") (pinfunction "GND_GND@2") (pintype "bidirectional"))
      (node (ref "RFCON510") (pin "GND@3") (pinfunction "GND_GND@3") (pintype "bidirectional"))
      (node (ref "RFCON601") (pin "GND@0") (pinfunction "GND_GND@0") (pintype "bidirectional"))
      (node (ref "RFCON601") (pin "GND@1") (pinfunction "GND_GND@1") (pintype "bidirectional"))
      (node (ref "RFCON601") (pin "GND@2") (pinfunction "GND_GND@2") (pintype "bidirectional"))
      (node (ref "RFCON601") (pin "GND@3") (pinfunction "GND_GND@3") (pintype "bidirectional"))
      (node (ref "RFCON602") (pin "GND@0") (pinfunction "GND_GND@0") (pintype "bidirectional"))
      (node (ref "RFCON602") (pin "GND@1") (pinfunction "GND_GND@1") (pintype "bidirectional"))
      (node (ref "RFCON602") (pin "GND@2") (pinfunction "GND_GND@2") (pintype "bidirectional"))
      (node (ref "RFCON602") (pin "GND@3") (pinfunction "GND_GND@3") (pintype "bidirectional"))
      (node (ref "RFCON901") (pin "P$1") (pinfunction "GND_P$1") (pintype "bidirectional"))
      (node (ref "RFCON901") (pin "P$2") (pinfunction "GND_P$2") (pintype "bidirectional"))
      (node (ref "RFCON902") (pin "P$1") (pinfunction "GND_P$1") (pintype "bidirectional"))
      (node (ref "RFCON902") (pin "P$2") (pinfunction "GND_P$2") (pintype "bidirectional"))
      (node (ref "S1001") (pin "1") (pinfunction "1_1") (pintype "passive"))
      (node (ref "S1001") (pin "2") (pinfunction "2_2") (pintype "passive"))
      (node (ref "SD101") (pin "11") (pinfunction "GND_11") (pintype "power_in"))
      (node (ref "SD101") (pin "12") (pinfunction "GND_12") (pintype "power_in"))
      (node (ref "SD101") (pin "13") (pinfunction "GND_13") (pintype "power_in"))
      (node (ref "SD101") (pin "14") (pinfunction "GND_14") (pintype "power_in"))
      (node (ref "SD101") (pin "15") (pinfunction "GND_15") (pintype "power_in"))
      (node (ref "SD101") (pin "16") (pinfunction "GND_16") (pintype "power_in"))
      (node (ref "SD101") (pin "6") (pinfunction "VSS_6") (pintype "power_in"))
      (node (ref "SHIELD401") (pin "1") (pinfunction "GND_1") (pintype "bidirectional"))
      (node (ref "SHIELD401") (pin "10") (pinfunction "GND_10") (pintype "bidirectional"))
      (node (ref "SHIELD401") (pin "11") (pinfunction "GND_11") (pintype "bidirectional"))
      (node (ref "SHIELD401") (pin "12") (pinfunction "GND_12") (pintype "bidirectional"))
      (node (ref "SHIELD401") (pin "13") (pinfunction "GND_13") (pintype "bidirectional"))
      (node (ref "SHIELD401") (pin "14") (pinfunction "GND_14") (pintype "bidirectional"))
      (node (ref "SHIELD401") (pin "15") (pinfunction "GND_15") (pintype "bidirectional"))
      (node (ref "SHIELD401") (pin "16") (pinfunction "GND_16") (pintype "bidirectional"))
      (node (ref "SHIELD401") (pin "17") (pinfunction "GND_17") (pintype "bidirectional"))
      (node (ref "SHIELD401") (pin "18") (pinfunction "GND_18") (pintype "bidirectional"))
      (node (ref "SHIELD401") (pin "19") (pinfunction "GND_19") (pintype "bidirectional"))
      (node (ref "SHIELD401") (pin "2") (pinfunction "GND_2") (pintype "bidirectional"))
      (node (ref "SHIELD401") (pin "20") (pinfunction "GND_20") (pintype "bidirectional"))
      (node (ref "SHIELD401") (pin "21") (pinfunction "GND_21") (pintype "bidirectional"))
      (node (ref "SHIELD401") (pin "22") (pinfunction "GND_22") (pintype "bidirectional"))
      (node (ref "SHIELD401") (pin "23") (pinfunction "GND_23") (pintype "bidirectional"))
      (node (ref "SHIELD401") (pin "24") (pinfunction "GND_24") (pintype "bidirectional"))
      (node (ref "SHIELD401") (pin "25") (pinfunction "GND_25") (pintype "bidirectional"))
      (node (ref "SHIELD401") (pin "26") (pinfunction "GND_26") (pintype "bidirectional"))
      (node (ref "SHIELD401") (pin "27") (pinfunction "GND_27") (pintype "bidirectional"))
      (node (ref "SHIELD401") (pin "28") (pinfunction "GND_28") (pintype "bidirectional"))
      (node (ref "SHIELD401") (pin "29") (pinfunction "GND_29") (pintype "bidirectional"))
      (node (ref "SHIELD401") (pin "3") (pinfunction "GND_3") (pintype "bidirectional"))
      (node (ref "SHIELD401") (pin "30") (pinfunction "GND_30") (pintype "bidirectional"))
      (node (ref "SHIELD401") (pin "31") (pinfunction "GND_31") (pintype "bidirectional"))
      (node (ref "SHIELD401") (pin "32") (pinfunction "GND_32") (pintype "bidirectional"))
      (node (ref "SHIELD401") (pin "4") (pinfunction "GND_4") (pintype "bidirectional"))
      (node (ref "SHIELD401") (pin "5") (pinfunction "GND_5") (pintype "bidirectional"))
      (node (ref "SHIELD401") (pin "6") (pinfunction "GND_6") (pintype "bidirectional"))
      (node (ref "SHIELD401") (pin "7") (pinfunction "GND_7") (pintype "bidirectional"))
      (node (ref "SHIELD401") (pin "8") (pinfunction "GND_8") (pintype "bidirectional"))
      (node (ref "SHIELD401") (pin "9") (pinfunction "GND_9") (pintype "bidirectional"))
      (node (ref "SHIELD601") (pin "1") (pinfunction "GND_1") (pintype "bidirectional"))
      (node (ref "SHIELD601") (pin "10") (pinfunction "GND_10") (pintype "bidirectional"))
      (node (ref "SHIELD601") (pin "11") (pinfunction "GND_11") (pintype "bidirectional"))
      (node (ref "SHIELD601") (pin "12") (pinfunction "GND_12") (pintype "bidirectional"))
      (node (ref "SHIELD601") (pin "13") (pinfunction "GND_13") (pintype "bidirectional"))
      (node (ref "SHIELD601") (pin "14") (pinfunction "GND_14") (pintype "bidirectional"))
      (node (ref "SHIELD601") (pin "15") (pinfunction "GND_15") (pintype "bidirectional"))
      (node (ref "SHIELD601") (pin "16") (pinfunction "GND_16") (pintype "bidirectional"))
      (node (ref "SHIELD601") (pin "2") (pinfunction "GND_2") (pintype "bidirectional"))
      (node (ref "SHIELD601") (pin "3") (pinfunction "GND_3") (pintype "bidirectional"))
      (node (ref "SHIELD601") (pin "4") (pinfunction "GND_4") (pintype "bidirectional"))
      (node (ref "SHIELD601") (pin "5") (pinfunction "GND_5") (pintype "bidirectional"))
      (node (ref "SHIELD601") (pin "6") (pinfunction "GND_6") (pintype "bidirectional"))
      (node (ref "SHIELD601") (pin "7") (pinfunction "GND_7") (pintype "bidirectional"))
      (node (ref "SHIELD601") (pin "8") (pinfunction "GND_8") (pintype "bidirectional"))
      (node (ref "SHIELD601") (pin "9") (pinfunction "GND_9") (pintype "bidirectional"))
      (node (ref "T501") (pin "2") (pinfunction "PRI2_2") (pintype "passive"))
      (node (ref "T502") (pin "2") (pinfunction "PRI2_2") (pintype "passive"))
      (node (ref "T503") (pin "2") (pinfunction "PRI2_2") (pintype "passive"))
      (node (ref "T504") (pin "2") (pinfunction "PRI2_2") (pintype "passive"))
      (node (ref "T505") (pin "2") (pinfunction "PRI2_2") (pintype "passive"))
      (node (ref "T506") (pin "2") (pinfunction "PRI2_2") (pintype "passive"))
      (node (ref "T507") (pin "2") (pinfunction "PRI2_2") (pintype "passive"))
      (node (ref "T508") (pin "2") (pinfunction "PRI2_2") (pintype "passive"))
      (node (ref "TC1001") (pin "3") (pinfunction "S_3") (pintype "passive"))
      (node (ref "TC201") (pin "3") (pinfunction "S_3") (pintype "passive"))
      (node (ref "U1001") (pin "4") (pinfunction "GND_4") (pintype "bidirectional"))
      (node (ref "U1001") (pin "9") (pinfunction "GND_9") (pintype "bidirectional"))
      (node (ref "U1002") (pin "41") (pinfunction "GND_41") (pintype "bidirectional"))
      (node (ref "U1003") (pin "2") (pinfunction "GND_2") (pintype "bidirectional"))
      (node (ref "U101") (pin "2") (pinfunction "GND_2") (pintype "bidirectional"))
      (node (ref "U102") (pin "1") (pinfunction "GND_1") (pintype "bidirectional"))
      (node (ref "U102") (pin "107") (pinfunction "GND_107") (pintype "bidirectional"))
      (node (ref "U102") (pin "108") (pinfunction "GND_108") (pintype "bidirectional"))
      (node (ref "U102") (pin "113") (pinfunction "GND_113") (pintype "bidirectional"))
      (node (ref "U102") (pin "114") (pinfunction "GND_114") (pintype "bidirectional"))
      (node (ref "U102") (pin "119") (pinfunction "GND_119") (pintype "bidirectional"))
      (node (ref "U102") (pin "120") (pinfunction "GND_120") (pintype "bidirectional"))
      (node (ref "U102") (pin "125") (pinfunction "GND_125") (pintype "bidirectional"))
      (node (ref "U102") (pin "126") (pinfunction "GND_126") (pintype "bidirectional"))
      (node (ref "U102") (pin "13") (pinfunction "GND_13") (pintype "bidirectional"))
      (node (ref "U102") (pin "131") (pinfunction "GND_131") (pintype "bidirectional"))
      (node (ref "U102") (pin "132") (pinfunction "GND_132") (pintype "bidirectional"))
      (node (ref "U102") (pin "137") (pinfunction "GND_137") (pintype "bidirectional"))
      (node (ref "U102") (pin "138") (pinfunction "GND_138") (pintype "bidirectional"))
      (node (ref "U102") (pin "14") (pinfunction "GND_14") (pintype "bidirectional"))
      (node (ref "U102") (pin "144") (pinfunction "GND_144") (pintype "bidirectional"))
      (node (ref "U102") (pin "150") (pinfunction "GND_150") (pintype "bidirectional"))
      (node (ref "U102") (pin "155") (pinfunction "GND_155") (pintype "bidirectional"))
      (node (ref "U102") (pin "156") (pinfunction "GND_156") (pintype "bidirectional"))
      (node (ref "U102") (pin "161") (pinfunction "GND_161") (pintype "bidirectional"))
      (node (ref "U102") (pin "162") (pinfunction "GND_162") (pintype "bidirectional"))
      (node (ref "U102") (pin "167") (pinfunction "GND_167") (pintype "bidirectional"))
      (node (ref "U102") (pin "168") (pinfunction "GND_168") (pintype "bidirectional"))
      (node (ref "U102") (pin "173") (pinfunction "GND_173") (pintype "bidirectional"))
      (node (ref "U102") (pin "174") (pinfunction "GND_174") (pintype "bidirectional"))
      (node (ref "U102") (pin "179") (pinfunction "GND_179") (pintype "bidirectional"))
      (node (ref "U102") (pin "180") (pinfunction "GND_180") (pintype "bidirectional"))
      (node (ref "U102") (pin "185") (pinfunction "GND_185") (pintype "bidirectional"))
      (node (ref "U102") (pin "186") (pinfunction "GND_186") (pintype "bidirectional"))
      (node (ref "U102") (pin "191") (pinfunction "GND_191") (pintype "bidirectional"))
      (node (ref "U102") (pin "192") (pinfunction "GND_192") (pintype "bidirectional"))
      (node (ref "U102") (pin "197") (pinfunction "GND_197") (pintype "bidirectional"))
      (node (ref "U102") (pin "198") (pinfunction "GND_198") (pintype "bidirectional"))
      (node (ref "U102") (pin "2") (pinfunction "GND_2") (pintype "bidirectional"))
      (node (ref "U102") (pin "22") (pinfunction "GND_22") (pintype "bidirectional"))
      (node (ref "U102") (pin "23") (pinfunction "GND_23") (pintype "bidirectional"))
      (node (ref "U102") (pin "32") (pinfunction "GND_32") (pintype "bidirectional"))
      (node (ref "U102") (pin "33") (pinfunction "GND_33") (pintype "bidirectional"))
      (node (ref "U102") (pin "42") (pinfunction "GND_42") (pintype "bidirectional"))
      (node (ref "U102") (pin "43") (pinfunction "GND_43") (pintype "bidirectional"))
      (node (ref "U102") (pin "52") (pinfunction "GND_52") (pintype "bidirectional"))
      (node (ref "U102") (pin "53") (pinfunction "GND_53") (pintype "bidirectional"))
      (node (ref "U102") (pin "59") (pinfunction "GND_59") (pintype "bidirectional"))
      (node (ref "U102") (pin "60") (pinfunction "GND_60") (pintype "bidirectional"))
      (node (ref "U102") (pin "65") (pinfunction "GND_65") (pintype "bidirectional"))
      (node (ref "U102") (pin "66") (pinfunction "GND_66") (pintype "bidirectional"))
      (node (ref "U102") (pin "7") (pinfunction "GND_7") (pintype "bidirectional"))
      (node (ref "U102") (pin "71") (pinfunction "GND_71") (pintype "bidirectional"))
      (node (ref "U102") (pin "74") (pinfunction "GND_74") (pintype "bidirectional"))
      (node (ref "U102") (pin "8") (pinfunction "GND_8") (pintype "bidirectional"))
      (node (ref "U102") (pin "98") (pinfunction "GND_98") (pintype "bidirectional"))
      (node (ref "U1101") (pin "2") (pinfunction "GND_2") (pintype "bidirectional"))
      (node (ref "U1102") (pin "1") (pinfunction "VSENSEN_1") (pintype "bidirectional"))
      (node (ref "U1102") (pin "12") (pinfunction "VSENSEN_12") (pintype "bidirectional"))
      (node (ref "U1102") (pin "14") (pinfunction "PGND_14") (pintype "bidirectional"))
      (node (ref "U1102") (pin "19") (pinfunction "PGND_19") (pintype "bidirectional"))
      (node (ref "U1102") (pin "3") (pinfunction "SGND_3") (pintype "bidirectional"))
      (node (ref "U1102") (pin "34") (pinfunction "PGND_34") (pintype "bidirectional"))
      (node (ref "U1102") (pin "39") (pinfunction "PGND_39") (pintype "bidirectional"))
      (node (ref "U1102") (pin "42") (pinfunction "PGND_42") (pintype "bidirectional"))
      (node (ref "U1102") (pin "43") (pinfunction "PGND_43") (pintype "bidirectional"))
      (node (ref "U1102") (pin "45") (pinfunction "PGND_45") (pintype "bidirectional"))
      (node (ref "U1102") (pin "46") (pinfunction "PGND_46") (pintype "bidirectional"))
      (node (ref "U1102") (pin "47") (pinfunction "PGND_47") (pintype "bidirectional"))
      (node (ref "U1102") (pin "48") (pinfunction "PGND_48") (pintype "bidirectional"))
      (node (ref "U1201") (pin "6") (pinfunction "GND_6") (pintype "bidirectional"))
      (node (ref "U1201") (pin "9") (pinfunction "GND_9") (pintype "bidirectional"))
      (node (ref "U1202") (pin "6") (pinfunction "GND_6") (pintype "bidirectional"))
      (node (ref "U1202") (pin "9") (pinfunction "GND_9") (pintype "bidirectional"))
      (node (ref "U1203") (pin "6") (pinfunction "GND_6") (pintype "bidirectional"))
      (node (ref "U1203") (pin "9") (pinfunction "GND_9") (pintype "bidirectional"))
      (node (ref "U1204") (pin "19") (pinfunction "AGND_19") (pintype "bidirectional"))
      (node (ref "U1204") (pin "2") (pinfunction "PGND_2") (pintype "bidirectional"))
      (node (ref "U1204") (pin "21") (pinfunction "PGND_21") (pintype "bidirectional"))
      (node (ref "U1204") (pin "5") (pinfunction "PGND_5") (pintype "bidirectional"))
      (node (ref "U1204") (pin "8") (pinfunction "AGND_8") (pintype "bidirectional"))
      (node (ref "U1205") (pin "11") (pinfunction "AGND_11") (pintype "bidirectional"))
      (node (ref "U1205") (pin "3") (pinfunction "AGND_3") (pintype "bidirectional"))
      (node (ref "U1205") (pin "8") (pinfunction "PGND_8") (pintype "bidirectional"))
      (node (ref "U1206") (pin "6") (pinfunction "GND_6") (pintype "bidirectional"))
      (node (ref "U1206") (pin "9") (pinfunction "GND_9") (pintype "bidirectional"))
      (node (ref "U1207") (pin "6") (pinfunction "GND_6") (pintype "bidirectional"))
      (node (ref "U1207") (pin "9") (pinfunction "GND_9") (pintype "bidirectional"))
      (node (ref "U1208") (pin "19") (pinfunction "AGND_19") (pintype "bidirectional"))
      (node (ref "U1208") (pin "2") (pinfunction "PGND_2") (pintype "bidirectional"))
      (node (ref "U1208") (pin "21") (pinfunction "PGND_21") (pintype "bidirectional"))
      (node (ref "U1208") (pin "5") (pinfunction "PGND_5") (pintype "bidirectional"))
      (node (ref "U1208") (pin "8") (pinfunction "AGND_8") (pintype "bidirectional"))
      (node (ref "U1209") (pin "10") (pinfunction "PGND_10") (pintype "bidirectional"))
      (node (ref "U1209") (pin "11") (pinfunction "PGND_11") (pintype "bidirectional"))
      (node (ref "U1209") (pin "7") (pinfunction "AGND_7") (pintype "bidirectional"))
      (node (ref "U1210") (pin "2") (pinfunction "GND_2") (pintype "bidirectional"))
      (node (ref "U201") (pin "A11") (pinfunction "GND_A11") (pintype "bidirectional"))
      (node (ref "U201") (pin "A12") (pinfunction "GND_A12") (pintype "bidirectional"))
      (node (ref "U201") (pin "A2") (pinfunction "GND_A2") (pintype "bidirectional"))
      (node (ref "U201") (pin "A22") (pinfunction "GND_A22") (pintype "bidirectional"))
      (node (ref "U201") (pin "A3") (pinfunction "GND_A3") (pintype "bidirectional"))
      (node (ref "U201") (pin "A5") (pinfunction "GND_A5") (pintype "bidirectional"))
      (node (ref "U201") (pin "A7") (pinfunction "GND_A7") (pintype "bidirectional"))
      (node (ref "U201") (pin "A9") (pinfunction "GND_A9") (pintype "bidirectional"))
      (node (ref "U201") (pin "AA12") (pinfunction "GND_AA12") (pintype "bidirectional"))
      (node (ref "U201") (pin "AA2") (pinfunction "GND_AA2") (pintype "bidirectional"))
      (node (ref "U201") (pin "AA22") (pinfunction "GND_AA22") (pintype "bidirectional"))
      (node (ref "U201") (pin "AB19") (pinfunction "GND_AB19") (pintype "bidirectional"))
      (node (ref "U201") (pin "AB9") (pinfunction "GND_AB9") (pintype "bidirectional"))
      (node (ref "U201") (pin "B12") (pinfunction "GND_B12") (pintype "bidirectional"))
      (node (ref "U201") (pin "B19") (pinfunction "GND_B19") (pintype "bidirectional"))
      (node (ref "U201") (pin "B3") (pinfunction "GND_B3") (pintype "bidirectional"))
      (node (ref "U201") (pin "C10") (pinfunction "GND_C10") (pintype "bidirectional"))
      (node (ref "U201") (pin "C11") (pinfunction "MGTPRXN1_C11") (pintype "bidirectional"))
      (node (ref "U201") (pin "C12") (pinfunction "GND_C12") (pintype "bidirectional"))
      (node (ref "U201") (pin "C16") (pinfunction "GND_C16") (pintype "bidirectional"))
      (node (ref "U201") (pin "C3") (pinfunction "GND_C3") (pintype "bidirectional"))
      (node (ref "U201") (pin "C6") (pinfunction "GND_C6") (pintype "bidirectional"))
      (node (ref "U201") (pin "D11") (pinfunction "MGTPRXP1_D11") (pintype "bidirectional"))
      (node (ref "U201") (pin "D12") (pinfunction "GND_D12") (pintype "bidirectional"))
      (node (ref "U201") (pin "D13") (pinfunction "GND_D13") (pintype "bidirectional"))
      (node (ref "U201") (pin "D3") (pinfunction "GND_D3") (pintype "bidirectional"))
      (node (ref "U201") (pin "D4") (pinfunction "GND_D4") (pintype "bidirectional"))
      (node (ref "U201") (pin "D8") (pinfunction "GND_D8") (pintype "bidirectional"))
      (node (ref "U201") (pin "E11") (pinfunction "GND_E11") (pintype "bidirectional"))
      (node (ref "U201") (pin "E20") (pinfunction "GND_E20") (pintype "bidirectional"))
      (node (ref "U201") (pin "E4") (pinfunction "GND_E4") (pintype "bidirectional"))
      (node (ref "U201") (pin "E5") (pinfunction "GND_E5") (pintype "bidirectional"))
      (node (ref "U201") (pin "E7") (pinfunction "GND_E7") (pintype "bidirectional"))
      (node (ref "U201") (pin "E9") (pinfunction "GND_E9") (pintype "bidirectional"))
      (node (ref "U201") (pin "F11") (pinfunction "GND_F11") (pintype "bidirectional"))
      (node (ref "U201") (pin "F17") (pinfunction "GND_F17") (pintype "bidirectional"))
      (node (ref "U201") (pin "F5") (pinfunction "GND_F5") (pintype "bidirectional"))
      (node (ref "U201") (pin "G10") (pinfunction "GND_G10") (pintype "bidirectional"))
      (node (ref "U201") (pin "G12") (pinfunction "GND_G12") (pintype "bidirectional"))
      (node (ref "U201") (pin "G14") (pinfunction "GND_G14") (pintype "bidirectional"))
      (node (ref "U201") (pin "G5") (pinfunction "GND_G5") (pintype "bidirectional"))
      (node (ref "U201") (pin "G6") (pinfunction "GND_G6") (pintype "bidirectional"))
      (node (ref "U201") (pin "G7") (pinfunction "GND_G7") (pintype "bidirectional"))
      (node (ref "U201") (pin "G8") (pinfunction "GND_G8") (pintype "bidirectional"))
      (node (ref "U201") (pin "G9") (pinfunction "GND_G9") (pintype "bidirectional"))
      (node (ref "U201") (pin "H1") (pinfunction "GND_H1") (pintype "bidirectional"))
      (node (ref "U201") (pin "H11") (pinfunction "GND_H11") (pintype "bidirectional"))
      (node (ref "U201") (pin "H19") (pinfunction "IO_L12N/T1/MRCC_H19") (pintype "bidirectional"))
      (node (ref "U201") (pin "H20") (pinfunction "IO_L8P/T1/AD10P_H20") (pintype "bidirectional"))
      (node (ref "U201") (pin "H21") (pinfunction "GND_H21") (pintype "bidirectional"))
      (node (ref "U201") (pin "H22") (pinfunction "IO_L7N/T1/AD2N_H22") (pintype "bidirectional"))
      (node (ref "U201") (pin "H7") (pinfunction "GND_H7") (pintype "bidirectional"))
      (node (ref "U201") (pin "H9") (pinfunction "GND_H9") (pintype "bidirectional"))
      (node (ref "U201") (pin "J10") (pinfunction "GND_J10") (pintype "bidirectional"))
      (node (ref "U201") (pin "J12") (pinfunction "GND_J12") (pintype "bidirectional"))
      (node (ref "U201") (pin "J18") (pinfunction "GND_J18") (pintype "bidirectional"))
      (node (ref "U201") (pin "J8") (pinfunction "GND_J8") (pintype "bidirectional"))
      (node (ref "U201") (pin "K11") (pinfunction "GND_K11") (pintype "bidirectional"))
      (node (ref "U201") (pin "K15") (pinfunction "GND_K15") (pintype "bidirectional"))
      (node (ref "U201") (pin "K5") (pinfunction "GND_K5") (pintype "bidirectional"))
      (node (ref "U201") (pin "K7") (pinfunction "GND_K7") (pintype "bidirectional"))
      (node (ref "U201") (pin "K9") (pinfunction "GNDADC_K9") (pintype "bidirectional"))
      (node (ref "U201") (pin "L10") (pinfunction "VP_L10") (pintype "bidirectional"))
      (node (ref "U201") (pin "L2") (pinfunction "GND_L2") (pintype "bidirectional"))
      (node (ref "U201") (pin "L22") (pinfunction "GND_L22") (pintype "bidirectional"))
      (node (ref "U201") (pin "L8") (pinfunction "GND_L8") (pintype "bidirectional"))
      (node (ref "U201") (pin "L9") (pinfunction "VREFN_L9") (pintype "bidirectional"))
      (node (ref "U201") (pin "M10") (pinfunction "VREFP_M10") (pintype "bidirectional"))
      (node (ref "U201") (pin "M11") (pinfunction "GND_M11") (pintype "bidirectional"))
      (node (ref "U201") (pin "M19") (pinfunction "GND_M19") (pintype "bidirectional"))
      (node (ref "U201") (pin "M20") (pinfunction "IO_L18N/T2/A23_M20") (pintype "bidirectional"))
      (node (ref "U201") (pin "M21") (pinfunction "IO_L10P/T1/AD11P_M21") (pintype "bidirectional"))
      (node (ref "U201") (pin "M7") (pinfunction "GND_M7") (pintype "bidirectional"))
      (node (ref "U201") (pin "M9") (pinfunction "VN_M9") (pintype "bidirectional"))
      (node (ref "U201") (pin "N10") (pinfunction "DXP_N10") (pintype "bidirectional"))
      (node (ref "U201") (pin "N16") (pinfunction "GND_N16") (pintype "bidirectional"))
      (node (ref "U201") (pin "N6") (pinfunction "GND_N6") (pintype "bidirectional"))
      (node (ref "U201") (pin "N8") (pinfunction "GND_N8") (pintype "bidirectional"))
      (node (ref "U201") (pin "N9") (pinfunction "DXN_N9") (pintype "bidirectional"))
      (node (ref "U201") (pin "P11") (pinfunction "GND_P11") (pintype "bidirectional"))
      (node (ref "U201") (pin "P13") (pinfunction "GND_P13") (pintype "bidirectional"))
      (node (ref "U201") (pin "P3") (pinfunction "GND_P3") (pintype "bidirectional"))
      (node (ref "U201") (pin "P7") (pinfunction "GND_P7") (pintype "bidirectional"))
      (node (ref "U201") (pin "P9") (pinfunction "GND_P9") (pintype "bidirectional"))
      (node (ref "U201") (pin "R10") (pinfunction "GND_R10") (pintype "bidirectional"))
      (node (ref "U201") (pin "R12") (pinfunction "GND_R12") (pintype "bidirectional"))
      (node (ref "U201") (pin "R20") (pinfunction "GND_R20") (pintype "bidirectional"))
      (node (ref "U201") (pin "R8") (pinfunction "GND_R8") (pintype "bidirectional"))
      (node (ref "U201") (pin "T11") (pinfunction "GND_T11") (pintype "bidirectional"))
      (node (ref "U201") (pin "T17") (pinfunction "GND_T17") (pintype "bidirectional"))
      (node (ref "U201") (pin "T7") (pinfunction "GND_T7") (pintype "bidirectional"))
      (node (ref "U201") (pin "T9") (pinfunction "GND_T9") (pintype "bidirectional"))
      (node (ref "U201") (pin "U10") (pinfunction "M1_U10") (pintype "bidirectional"))
      (node (ref "U201") (pin "U14") (pinfunction "GND_U14") (pintype "bidirectional"))
      (node (ref "U201") (pin "U22") (pinfunction "IO_L3P/T0_DQS/~{PUDC}_U22") (pintype "bidirectional"))
      (node (ref "U201") (pin "U4") (pinfunction "GND_U4") (pintype "bidirectional"))
      (node (ref "U201") (pin "V1") (pinfunction "GND_V1") (pintype "bidirectional"))
      (node (ref "U201") (pin "V11") (pinfunction "GND_V11") (pintype "bidirectional"))
      (node (ref "U201") (pin "V21") (pinfunction "GND_V21") (pintype "bidirectional"))
      (node (ref "U201") (pin "W18") (pinfunction "GND_W18") (pintype "bidirectional"))
      (node (ref "U201") (pin "W8") (pinfunction "GND_W8") (pintype "bidirectional"))
      (node (ref "U201") (pin "Y15") (pinfunction "GND_Y15") (pintype "bidirectional"))
      (node (ref "U201") (pin "Y5") (pinfunction "GND_Y5") (pintype "bidirectional"))
      (node (ref "U202") (pin "4") (pinfunction "GND_4") (pintype "power_in"))
      (node (ref "U301") (pin "A9") (pinfunction "VSS_A9") (pintype "bidirectional"))
      (node (ref "U301") (pin "B1") (pinfunction "VSSQ_B1") (pintype "bidirectional"))
      (node (ref "U301") (pin "B3") (pinfunction "VSS_B3") (pintype "bidirectional"))
      (node (ref "U301") (pin "B9") (pinfunction "VSSQ_B9") (pintype "bidirectional"))
      (node (ref "U301") (pin "D1") (pinfunction "VSSQ_D1") (pintype "bidirectional"))
      (node (ref "U301") (pin "D8") (pinfunction "VSSQ_D8") (pintype "bidirectional"))
      (node (ref "U301") (pin "E1") (pinfunction "VSS_E1") (pintype "bidirectional"))
      (node (ref "U301") (pin "E2") (pinfunction "VSSQ_E2") (pintype "bidirectional"))
      (node (ref "U301") (pin "E8") (pinfunction "VSSQ_E8") (pintype "bidirectional"))
      (node (ref "U301") (pin "F9") (pinfunction "VSSQ_F9") (pintype "bidirectional"))
      (node (ref "U301") (pin "G1") (pinfunction "VSSQ_G1") (pintype "bidirectional"))
      (node (ref "U301") (pin "G8") (pinfunction "VSS_G8") (pintype "bidirectional"))
      (node (ref "U301") (pin "G9") (pinfunction "VSSQ_G9") (pintype "bidirectional"))
      (node (ref "U301") (pin "J2") (pinfunction "VSS_J2") (pintype "bidirectional"))
      (node (ref "U301") (pin "J8") (pinfunction "VSS_J8") (pintype "bidirectional"))
      (node (ref "U301") (pin "L2") (pinfunction "~{CS}_L2") (pintype "bidirectional"))
      (node (ref "U301") (pin "M1") (pinfunction "VSS_M1") (pintype "bidirectional"))
      (node (ref "U301") (pin "M9") (pinfunction "VSS_M9") (pintype "bidirectional"))
      (node (ref "U301") (pin "P1") (pinfunction "VSS_P1") (pintype "bidirectional"))
      (node (ref "U301") (pin "P9") (pinfunction "VSS_P9") (pintype "bidirectional"))
      (node (ref "U301") (pin "T1") (pinfunction "VSS_T1") (pintype "bidirectional"))
      (node (ref "U301") (pin "T9") (pinfunction "VSS_T9") (pintype "bidirectional"))
      (node (ref "U401") (pin "A12") (pinfunction "TX_EXT_LO_IN_A12") (pintype "bidirectional"))
      (node (ref "U401") (pin "A4") (pinfunction "VSSA_A4") (pintype "bidirectional"))
      (node (ref "U401") (pin "A6") (pinfunction "VSSA_A6") (pintype "bidirectional"))
      (node (ref "U401") (pin "B1") (pinfunction "VSSA_B1") (pintype "bidirectional"))
      (node (ref "U401") (pin "B12") (pinfunction "VSSA_B12") (pintype "bidirectional"))
      (node (ref "U401") (pin "B2") (pinfunction "VSSA_B2") (pintype "bidirectional"))
      (node (ref "U401") (pin "C10") (pinfunction "VSSA_C10") (pintype "bidirectional"))
      (node (ref "U401") (pin "C11") (pinfunction "VSSA_C11") (pintype "bidirectional"))
      (node (ref "U401") (pin "C12") (pinfunction "VSSA_C12") (pintype "bidirectional"))
      (node (ref "U401") (pin "C2") (pinfunction "VSSA_C2") (pintype "bidirectional"))
      (node (ref "U401") (pin "C4") (pinfunction "TEST/~{ENABLE}_C4") (pintype "bidirectional"))
      (node (ref "U401") (pin "C7") (pinfunction "VSSA_C7") (pintype "bidirectional"))
      (node (ref "U401") (pin "C8") (pinfunction "VSSA_C8") (pintype "bidirectional"))
      (node (ref "U401") (pin "C9") (pinfunction "VSSA_C9") (pintype "bidirectional"))
      (node (ref "U401") (pin "D12") (pinfunction "VSSD_D12") (pintype "bidirectional"))
      (node (ref "U401") (pin "E1") (pinfunction "RX2B_P_E1") (pintype "bidirectional"))
      (node (ref "U401") (pin "F1") (pinfunction "RX2B_N_F1") (pintype "bidirectional"))
      (node (ref "U401") (pin "F11") (pinfunction "VSSD_F11") (pintype "bidirectional"))
      (node (ref "U401") (pin "F3") (pinfunction "VSSA_F3") (pintype "bidirectional"))
      (node (ref "U401") (pin "F7") (pinfunction "VSSD_F7") (pintype "bidirectional"))
      (node (ref "U401") (pin "F9") (pinfunction "VSSD_F9") (pintype "bidirectional"))
      (node (ref "U401") (pin "G1") (pinfunction "RX_EXT_LO_IN_G1") (pintype "bidirectional"))
      (node (ref "U401") (pin "G10") (pinfunction "FB_CLK_N_G10") (pintype "bidirectional"))
      (node (ref "U401") (pin "G12") (pinfunction "VSSD_G12") (pintype "bidirectional"))
      (node (ref "U401") (pin "H1") (pinfunction "RX1B_P_H1") (pintype "bidirectional"))
      (node (ref "U401") (pin "H10") (pinfunction "VSSD_H10") (pintype "bidirectional"))
      (node (ref "U401") (pin "H2") (pinfunction "VSSA_H2") (pintype "bidirectional"))
      (node (ref "U401") (pin "H3") (pinfunction "VSSA_H3") (pintype "bidirectional"))
      (node (ref "U401") (pin "H6") (pinfunction "VSSA_H6") (pintype "bidirectional"))
      (node (ref "U401") (pin "H7") (pinfunction "VSSD_H7") (pintype "bidirectional"))
      (node (ref "U401") (pin "H9") (pinfunction "TX_FRAME_N_H9") (pintype "bidirectional"))
      (node (ref "U401") (pin "J1") (pinfunction "RX1B_N_J1") (pintype "bidirectional"))
      (node (ref "U401") (pin "J2") (pinfunction "VSSA_J2") (pintype "bidirectional"))
      (node (ref "U401") (pin "K12") (pinfunction "VSSD_K12") (pintype "bidirectional"))
      (node (ref "U401") (pin "K2") (pinfunction "VSSA_K2") (pintype "bidirectional"))
      (node (ref "U401") (pin "L10") (pinfunction "VSSA_L10") (pintype "bidirectional"))
      (node (ref "U401") (pin "L11") (pinfunction "VSSA_L11") (pintype "bidirectional"))
      (node (ref "U401") (pin "L12") (pinfunction "VSSA_L12") (pintype "bidirectional"))
      (node (ref "U401") (pin "L2") (pinfunction "VSSA_L2") (pintype "bidirectional"))
      (node (ref "U401") (pin "L3") (pinfunction "VSSA_L3") (pintype "bidirectional"))
      (node (ref "U401") (pin "L5") (pinfunction "AUXADC_L5") (pintype "bidirectional"))
      (node (ref "U401") (pin "L7") (pinfunction "VSSA_L7") (pintype "bidirectional"))
      (node (ref "U401") (pin "L8") (pinfunction "VSSA_L8") (pintype "bidirectional"))
      (node (ref "U401") (pin "L9") (pinfunction "VSSA_L9") (pintype "bidirectional"))
      (node (ref "U401") (pin "M4") (pinfunction "VSSA_M4") (pintype "bidirectional"))
      (node (ref "U401") (pin "M6") (pinfunction "VSSA_M6") (pintype "bidirectional"))
      (node (ref "U501") (pin "2") (pinfunction "GND_2") (pintype "bidirectional"))
      (node (ref "U502") (pin "2") (pinfunction "GND_2") (pintype "bidirectional"))
      (node (ref "U503") (pin "2") (pinfunction "GND_2") (pintype "bidirectional"))
      (node (ref "U504") (pin "2") (pinfunction "GND_2") (pintype "bidirectional"))
      (node (ref "U505") (pin "2") (pinfunction "GND_2") (pintype "bidirectional"))
      (node (ref "U505") (pin "4") (pinfunction "GND_4") (pintype "bidirectional"))
      (node (ref "U506") (pin "2") (pinfunction "GND_2") (pintype "bidirectional"))
      (node (ref "U506") (pin "4") (pinfunction "GND_4") (pintype "bidirectional"))
      (node (ref "U601") (pin "14") (pinfunction "VSSPDCP_14") (pintype "bidirectional"))
      (node (ref "U601") (pin "17") (pinfunction "VSSFB_17") (pintype "bidirectional"))
      (node (ref "U601") (pin "19") (pinfunction "VSSDIG_19") (pintype "bidirectional"))
      (node (ref "U601") (pin "20") (pinfunction "VSSIN_20") (pintype "bidirectional"))
      (node (ref "U601") (pin "38") (pinfunction "VSSOUTA_38") (pintype "bidirectional"))
      (node (ref "U601") (pin "41") (pinfunction "VSSOUTA_41") (pintype "bidirectional"))
      (node (ref "U601") (pin "44") (pinfunction "VSSOUTB_44") (pintype "bidirectional"))
      (node (ref "U601") (pin "47") (pinfunction "VSSOUTB_47") (pintype "bidirectional"))
      (node (ref "U601") (pin "49") (pinfunction "VSS_49") (pintype "bidirectional"))
      (node (ref "U701") (pin "11") (pinfunction "AGND_11") (pintype "bidirectional"))
      (node (ref "U701") (pin "20") (pinfunction "AGND_20") (pintype "bidirectional"))
      (node (ref "U701") (pin "23") (pinfunction "AGND_23") (pintype "bidirectional"))
      (node (ref "U701") (pin "3") (pinfunction "ADDR1/MOSI_3") (pintype "bidirectional"))
      (node (ref "U701") (pin "30") (pinfunction "DGND_30") (pintype "bidirectional"))
      (node (ref "U701") (pin "4") (pinfunction "ADDR0/~{SS}_4") (pintype "bidirectional"))
      (node (ref "U701") (pin "41") (pinfunction "DGND_41") (pintype "bidirectional"))
      (node (ref "U701") (pin "5") (pinfunction "DGND_5") (pintype "bidirectional"))
      (node (ref "U901") (pin "1") (pinfunction "GND_1") (pintype "power_in"))
      (node (ref "U901") (pin "2") (pinfunction "GND_2") (pintype "power_in"))
      (node (ref "U902") (pin "21") (pinfunction "GND_21") (pintype "bidirectional"))
      (node (ref "USB1001") (pin "A1/B12") (pinfunction "GND_A1/B12") (pintype "bidirectional"))
      (node (ref "USB1001") (pin "B1/A12") (pinfunction "GND_B1/A12") (pintype "bidirectional"))
    )
    (net (code "175") (name "Net-(C105-C1)") (class "Default")
      (node (ref "C105") (pin "1") (pinfunction "C1_1") (pintype "passive"))
      (node (ref "SD101") (pin "4") (pinfunction "VDD_4") (pintype "power_in"))
      (node (ref "U101") (pin "6") (pinfunction "VOUT_6") (pintype "bidirectional"))
    )
    (net (code "176") (name "Net-(C107-C1)") (class "Default")
      (node (ref "C107") (pin "1") (pinfunction "C1_1") (pintype "passive"))
      (node (ref "J101") (pin "1") (pinfunction "CT_1") (pintype "bidirectional"))
    )
    (net (code "177") (name "Net-(C323-C1)") (class "Default")
      (node (ref "C323") (pin "1") (pinfunction "C1_1") (pintype "passive"))
      (node (ref "R311") (pin "1") (pinfunction "1_1") (pintype "passive"))
      (node (ref "R319") (pin "2") (pinfunction "2_2") (pintype "passive"))
    )
    (net (code "178") (name "Net-(C402-C1)") (class "Default")
      (node (ref "C402") (pin "1") (pinfunction "C1_1") (pintype "passive"))
      (node (ref "C403") (pin "1") (pinfunction "C1_1") (pintype "passive"))
      (node (ref "R401") (pin "1") (pinfunction "1_1") (pintype "passive"))
      (node (ref "R402") (pin "2") (pinfunction "2_2") (pintype "passive"))
    )
    (net (code "179") (name "Net-(C403-C2)") (class "Default")
      (node (ref "C403") (pin "2") (pinfunction "C2_2") (pintype "passive"))
      (node (ref "U401") (pin "M12") (pinfunction "XTALN_M12") (pintype "bidirectional"))
    )
    (net (code "180") (name "Net-(C406-C1)") (class "Default")
      (node (ref "C406") (pin "1") (pinfunction "C1_1") (pintype "passive"))
      (node (ref "C409") (pin "1") (pinfunction "C1_1") (pintype "passive"))
      (node (ref "C412") (pin "1") (pinfunction "C1_1") (pintype "passive"))
      (node (ref "C415") (pin "1") (pinfunction "C1_1") (pintype "passive"))
      (node (ref "C418") (pin "1") (pinfunction "C1_1") (pintype "passive"))
      (node (ref "FB401") (pin "2") (pinfunction "2_2") (pintype "passive"))
      (node (ref "U401") (pin "B8") (pinfunction "VDD_GPO_B8") (pintype "bidirectional"))
      (node (ref "U401") (pin "H12") (pinfunction "VDD_INTERFACE_H12") (pintype "bidirectional"))
    )
    (net (code "181") (name "Net-(C421-C1)") (class "Default")
      (node (ref "C421") (pin "1") (pinfunction "C1_1") (pintype "passive"))
      (node (ref "C422") (pin "1") (pinfunction "C1_1") (pintype "passive"))
      (node (ref "U401") (pin "A11") (pinfunction "VDDA1P1_TX_VCO_A11") (pintype "bidirectional"))
      (node (ref "U401") (pin "B11") (pinfunction "TX_VCO_LDO_OUT_B11") (pintype "bidirectional"))
    )
    (net (code "182") (name "Net-(C421-C2)") (class "Default")
      (node (ref "C421") (pin "2") (pinfunction "C2_2") (pintype "passive"))
      (node (ref "R404") (pin "2") (pinfunction "2_2") (pintype "passive"))
    )
    (net (code "183") (name "Net-(C423-C1)") (class "Default")
      (node (ref "C423") (pin "1") (pinfunction "C1_1") (pintype "passive"))
      (node (ref "C424") (pin "1") (pinfunction "C1_1") (pintype "passive"))
      (node (ref "U401") (pin "G2") (pinfunction "RX_VCO_LDO_OUT_G2") (pintype "bidirectional"))
      (node (ref "U401") (pin "G3") (pinfunction "VDDA1P1_RX_VCO_G3") (pintype "bidirectional"))
    )
    (net (code "184") (name "Net-(C423-C2)") (class "Default")
      (node (ref "C423") (pin "2") (pinfunction "C2_2") (pintype "passive"))
      (node (ref "R405") (pin "2") (pinfunction "2_2") (pintype "passive"))
    )
    (net (code "185") (name "Net-(C501-C1)") (class "Default")
      (node (ref "C501") (pin "1") (pinfunction "C1_1") (pintype "passive"))
      (node (ref "D503") (pin "1") (pinfunction "1_1") (pintype "passive"))
      (node (ref "L501") (pin "2") (pinfunction "2_2") (pintype "passive"))
      (node (ref "RFCON503") (pin "SIGNAL") (pinfunction "SIGNAL_SIGNAL") (pintype "bidirectional"))
    )
    (net (code "186") (name "Net-(C501-C2)") (class "Default")
      (node (ref "C501") (pin "2") (pinfunction "C2_2") (pintype "passive"))
      (node (ref "T503") (pin "3") (pinfunction "PRI1_3") (pintype "passive"))
    )
    (net (code "187") (name "Net-(C502-C1)") (class "Default")
      (node (ref "C502") (pin "1") (pinfunction "C1_1") (pintype "passive"))
      (node (ref "D504") (pin "1") (pinfunction "1_1") (pintype "passive"))
      (node (ref "L502") (pin "2") (pinfunction "2_2") (pintype "passive"))
      (node (ref "RFCON504") (pin "SIGNAL") (pinfunction "SIGNAL_SIGNAL") (pintype "bidirectional"))
    )
    (net (code "188") (name "Net-(C502-C2)") (class "Default")
      (node (ref "C502") (pin "2") (pinfunction "C2_2") (pintype "passive"))
      (node (ref "T504") (pin "3") (pinfunction "PRI1_3") (pintype "passive"))
    )
    (net (code "189") (name "Net-(C509-C1)") (class "Default")
      (node (ref "C509") (pin "1") (pinfunction "C1_1") (pintype "passive"))
      (node (ref "T501") (pin "5") (pinfunction "SEC1_5") (pintype "passive"))
    )
    (net (code "190") (name "Net-(C510-C1)") (class "Default")
      (node (ref "C510") (pin "1") (pinfunction "C1_1") (pintype "passive"))
      (node (ref "T501") (pin "4") (pinfunction "SEC2_4") (pintype "passive"))
    )
    (net (code "191") (name "Net-(C511-C1)") (class "Default")
      (node (ref "C511") (pin "1") (pinfunction "C1_1") (pintype "passive"))
      (node (ref "T502") (pin "5") (pinfunction "SEC1_5") (pintype "passive"))
    )
    (net (code "192") (name "Net-(C512-C1)") (class "Default")
      (node (ref "C512") (pin "1") (pinfunction "C1_1") (pintype "passive"))
      (node (ref "T502") (pin "4") (pinfunction "SEC2_4") (pintype "passive"))
    )
    (net (code "193") (name "Net-(C513-C1)") (class "Default")
      (node (ref "C513") (pin "1") (pinfunction "C1_1") (pintype "passive"))
      (node (ref "T503") (pin "5") (pinfunction "SEC1_5") (pintype "passive"))
    )
    (net (code "194") (name "Net-(C514-C1)") (class "Default")
      (node (ref "C514") (pin "1") (pinfunction "C1_1") (pintype "passive"))
      (node (ref "T503") (pin "4") (pinfunction "SEC2_4") (pintype "passive"))
    )
    (net (code "195") (name "Net-(C515-C1)") (class "Default")
      (node (ref "C515") (pin "1") (pinfunction "C1_1") (pintype "passive"))
      (node (ref "T504") (pin "5") (pinfunction "SEC1_5") (pintype "passive"))
    )
    (net (code "196") (name "Net-(C516-C1)") (class "Default")
      (node (ref "C516") (pin "1") (pinfunction "C1_1") (pintype "passive"))
      (node (ref "T504") (pin "4") (pinfunction "SEC2_4") (pintype "passive"))
    )
    (net (code "197") (name "Net-(C529-C1)") (class "Default")
      (node (ref "C529") (pin "1") (pinfunction "C1_1") (pintype "passive"))
      (node (ref "R514") (pin "1") (pinfunction "1_1") (pintype "passive"))
    )
    (net (code "198") (name "Net-(C530-C2)") (class "Default")
      (node (ref "C530") (pin "2") (pinfunction "C2_2") (pintype "passive"))
      (node (ref "T505") (pin "5") (pinfunction "SEC1_5") (pintype "passive"))
    )
    (net (code "199") (name "Net-(C531-C2)") (class "Default")
      (node (ref "C531") (pin "2") (pinfunction "C2_2") (pintype "passive"))
      (node (ref "T505") (pin "4") (pinfunction "SEC2_4") (pintype "passive"))
    )
    (net (code "200") (name "Net-(C532-C2)") (class "Default")
      (node (ref "C532") (pin "2") (pinfunction "C2_2") (pintype "passive"))
      (node (ref "T506") (pin "5") (pinfunction "SEC1_5") (pintype "passive"))
    )
    (net (code "201") (name "Net-(C533-C2)") (class "Default")
      (node (ref "C533") (pin "2") (pinfunction "C2_2") (pintype "passive"))
      (node (ref "T506") (pin "4") (pinfunction "SEC2_4") (pintype "passive"))
    )
    (net (code "202") (name "Net-(C538-C1)") (class "Default")
      (node (ref "C538") (pin "1") (pinfunction "C1_1") (pintype "passive"))
      (node (ref "T505") (pin "3") (pinfunction "PRI1_3") (pintype "passive"))
    )
    (net (code "203") (name "Net-(C538-C2)") (class "Default")
      (node (ref "C538") (pin "2") (pinfunction "C2_2") (pintype "passive"))
      (node (ref "U505") (pin "1") (pinfunction "RFIN_1") (pintype "bidirectional"))
    )
    (net (code "204") (name "Net-(C539-C1)") (class "Default")
      (node (ref "C539") (pin "1") (pinfunction "C1_1") (pintype "passive"))
      (node (ref "T506") (pin "3") (pinfunction "PRI1_3") (pintype "passive"))
    )
    (net (code "205") (name "Net-(C539-C2)") (class "Default")
      (node (ref "C539") (pin "2") (pinfunction "C2_2") (pintype "passive"))
      (node (ref "U506") (pin "1") (pinfunction "RFIN_1") (pintype "bidirectional"))
    )
    (net (code "206") (name "Net-(C544-C2)") (class "Default")
      (node (ref "C544") (pin "2") (pinfunction "C2_2") (pintype "passive"))
      (node (ref "T507") (pin "5") (pinfunction "SEC1_5") (pintype "passive"))
    )
    (net (code "207") (name "Net-(C545-C2)") (class "Default")
      (node (ref "C545") (pin "2") (pinfunction "C2_2") (pintype "passive"))
      (node (ref "T507") (pin "4") (pinfunction "SEC2_4") (pintype "passive"))
    )
    (net (code "208") (name "Net-(C546-C2)") (class "Default")
      (node (ref "C546") (pin "2") (pinfunction "C2_2") (pintype "passive"))
      (node (ref "T508") (pin "5") (pinfunction "SEC1_5") (pintype "passive"))
    )
    (net (code "209") (name "Net-(C547-C2)") (class "Default")
      (node (ref "C547") (pin "2") (pinfunction "C2_2") (pintype "passive"))
      (node (ref "T508") (pin "4") (pinfunction "SEC2_4") (pintype "passive"))
    )
    (net (code "210") (name "Net-(C550-C1)") (class "Default")
      (node (ref "C550") (pin "1") (pinfunction "C1_1") (pintype "passive"))
      (node (ref "R516") (pin "1") (pinfunction "1_1") (pintype "passive"))
    )
    (net (code "211") (name "Net-(C553-C1)") (class "Default")
      (node (ref "C553") (pin "1") (pinfunction "C1_1") (pintype "passive"))
      (node (ref "L511") (pin "2") (pinfunction "2_2") (pintype "passive"))
      (node (ref "U505") (pin "3") (pinfunction "RFOUT_3") (pintype "bidirectional"))
    )
    (net (code "212") (name "Net-(C553-C2)") (class "Default")
      (node (ref "C553") (pin "2") (pinfunction "C2_2") (pintype "passive"))
      (node (ref "D511") (pin "1") (pinfunction "1_1") (pintype "passive"))
      (node (ref "RFCON509") (pin "SIGNAL") (pinfunction "SIGNAL_SIGNAL") (pintype "bidirectional"))
    )
    (net (code "213") (name "Net-(C554-C1)") (class "Default")
      (node (ref "C554") (pin "1") (pinfunction "C1_1") (pintype "passive"))
      (node (ref "L512") (pin "2") (pinfunction "2_2") (pintype "passive"))
      (node (ref "U506") (pin "3") (pinfunction "RFOUT_3") (pintype "bidirectional"))
    )
    (net (code "214") (name "Net-(C554-C2)") (class "Default")
      (node (ref "C554") (pin "2") (pinfunction "C2_2") (pintype "passive"))
      (node (ref "D512") (pin "1") (pinfunction "1_1") (pintype "passive"))
      (node (ref "RFCON510") (pin "SIGNAL") (pinfunction "SIGNAL_SIGNAL") (pintype "bidirectional"))
    )
    (net (code "215") (name "Net-(C601-C2)") (class "Default")
      (node (ref "C601") (pin "2") (pinfunction "C2_2") (pintype "passive"))
      (node (ref "R604") (pin "1") (pinfunction "1_1") (pintype "passive"))
      (node (ref "R605") (pin "2") (pinfunction "2_2") (pintype "passive"))
      (node (ref "U601") (pin "22") (pinfunction "REF_IN_22") (pintype "bidirectional"))
    )
    (net (code "216") (name "Net-(C603-C1)") (class "Default")
      (node (ref "C603") (pin "1") (pinfunction "C1_1") (pintype "passive"))
      (node (ref "R606") (pin "1") (pinfunction "1_1") (pintype "passive"))
      (node (ref "R607") (pin "2") (pinfunction "2_2") (pintype "passive"))
      (node (ref "U601") (pin "23") (pinfunction "~{REF_IN}_23") (pintype "bidirectional"))
    )
    (net (code "217") (name "Net-(C606-C1)") (class "Default")
      (node (ref "C606") (pin "1") (pinfunction "C1_1") (pintype "passive"))
      (node (ref "U601") (pin "32") (pinfunction "VREGVCO1_32") (pintype "bidirectional"))
    )
    (net (code "218") (name "Net-(C609-C1)") (class "Default")
      (node (ref "C609") (pin "1") (pinfunction "C1_1") (pintype "passive"))
      (node (ref "U601") (pin "4") (pinfunction "VREGVCO2_4") (pintype "bidirectional"))
    )
    (net (code "219") (name "Net-(C612-C1)") (class "Default")
      (node (ref "C612") (pin "1") (pinfunction "C1_1") (pintype "passive"))
      (node (ref "U601") (pin "35") (pinfunction "VREFVCO1_35") (pintype "bidirectional"))
    )
    (net (code "220") (name "Net-(C613-C1)") (class "Default")
      (node (ref "C613") (pin "1") (pinfunction "C1_1") (pintype "passive"))
      (node (ref "U601") (pin "1") (pinfunction "VREFVCO2_1") (pintype "bidirectional"))
    )
    (net (code "221") (name "Net-(C614-C1)") (class "Default")
      (node (ref "C614") (pin "1") (pinfunction "C1_1") (pintype "passive"))
      (node (ref "U601") (pin "11") (pinfunction "CPBIAS_11") (pintype "bidirectional"))
    )
    (net (code "222") (name "Net-(C615-C1)") (class "Default")
      (node (ref "C615") (pin "1") (pinfunction "C1_1") (pintype "passive"))
      (node (ref "FB601") (pin "2") (pinfunction "2_2") (pintype "passive"))
      (node (ref "U601") (pin "18") (pinfunction "VDDDIG_18") (pintype "bidirectional"))
    )
    (net (code "223") (name "Net-(C616-C1)") (class "Default")
      (node (ref "C616") (pin "1") (pinfunction "C1_1") (pintype "passive"))
      (node (ref "R608") (pin "1") (pinfunction "1_1") (pintype "passive"))
    )
    (net (code "224") (name "Net-(C617-C1)") (class "Default")
      (node (ref "C617") (pin "1") (pinfunction "C1_1") (pintype "passive"))
      (node (ref "R608") (pin "2") (pinfunction "2_2") (pintype "passive"))
      (node (ref "R609") (pin "2") (pinfunction "2_2") (pintype "passive"))
      (node (ref "U601") (pin "10") (pinfunction "CPOUT_10") (pintype "bidirectional"))
    )
    (net (code "225") (name "Net-(C618-C1)") (class "Default")
      (node (ref "C618") (pin "1") (pinfunction "C1_1") (pintype "passive"))
      (node (ref "R609") (pin "1") (pinfunction "1_1") (pintype "passive"))
      (node (ref "U601") (pin "5") (pinfunction "VTUNE_5") (pintype "bidirectional"))
    )
    (net (code "226") (name "Net-(C619-C1)") (class "Default")
      (node (ref "C619") (pin "1") (pinfunction "C1_1") (pintype "passive"))
      (node (ref "C621") (pin "1") (pinfunction "C1_1") (pintype "passive"))
      (node (ref "L601") (pin "2") (pinfunction "2_2") (pintype "passive"))
      (node (ref "R610") (pin "2") (pinfunction "2_2") (pintype "passive"))
      (node (ref "R612") (pin "2") (pinfunction "2_2") (pintype "passive"))
    )
    (net (code "227") (name "Net-(C620-C1)") (class "Default")
      (node (ref "C620") (pin "1") (pinfunction "C1_1") (pintype "passive"))
      (node (ref "C622") (pin "1") (pinfunction "C1_1") (pintype "passive"))
      (node (ref "L602") (pin "2") (pinfunction "2_2") (pintype "passive"))
      (node (ref "R611") (pin "2") (pinfunction "2_2") (pintype "passive"))
      (node (ref "R613") (pin "2") (pinfunction "2_2") (pintype "passive"))
    )
    (net (code "228") (name "Net-(C623-C1)") (class "Default")
      (node (ref "C623") (pin "1") (pinfunction "C1_1") (pintype "passive"))
      (node (ref "R612") (pin "1") (pinfunction "1_1") (pintype "passive"))
      (node (ref "U601") (pin "39") (pinfunction "~{RF_OUTA}_39") (pintype "bidirectional"))
    )
    (net (code "229") (name "Net-(C623-C2)") (class "Default")
      (node (ref "C623") (pin "2") (pinfunction "C2_2") (pintype "passive"))
      (node (ref "R614") (pin "2") (pinfunction "2_2") (pintype "passive"))
    )
    (net (code "230") (name "Net-(C624-C1)") (class "Default")
      (node (ref "C624") (pin "1") (pinfunction "C1_1") (pintype "passive"))
      (node (ref "R613") (pin "1") (pinfunction "1_1") (pintype "passive"))
      (node (ref "U601") (pin "46") (pinfunction "~{RF_OUTB}_46") (pintype "bidirectional"))
    )
    (net (code "231") (name "Net-(C624-C2)") (class "Default")
      (node (ref "C624") (pin "2") (pinfunction "C2_2") (pintype "passive"))
      (node (ref "R615") (pin "2") (pinfunction "2_2") (pintype "passive"))
    )
    (net (code "232") (name "Net-(C625-C1)") (class "Default")
      (node (ref "C625") (pin "1") (pinfunction "C1_1") (pintype "passive"))
      (node (ref "R610") (pin "1") (pinfunction "1_1") (pintype "passive"))
      (node (ref "U601") (pin "40") (pinfunction "RF_OUTA_40") (pintype "bidirectional"))
    )
    (net (code "233") (name "Net-(C625-C2)") (class "Default")
      (node (ref "C625") (pin "2") (pinfunction "C2_2") (pintype "passive"))
      (node (ref "D601") (pin "1") (pinfunction "1_1") (pintype "passive"))
      (node (ref "RFCON601") (pin "SIGNAL") (pinfunction "SIGNAL_SIGNAL") (pintype "bidirectional"))
    )
    (net (code "234") (name "Net-(C626-C1)") (class "Default")
      (node (ref "C626") (pin "1") (pinfunction "C1_1") (pintype "passive"))
      (node (ref "R611") (pin "1") (pinfunction "1_1") (pintype "passive"))
      (node (ref "U601") (pin "45") (pinfunction "RF_OUTB_45") (pintype "bidirectional"))
    )
    (net (code "235") (name "Net-(C626-C2)") (class "Default")
      (node (ref "C626") (pin "2") (pinfunction "C2_2") (pintype "passive"))
      (node (ref "D602") (pin "1") (pinfunction "1_1") (pintype "passive"))
      (node (ref "RFCON602") (pin "SIGNAL") (pinfunction "SIGNAL_SIGNAL") (pintype "bidirectional"))
    )
    (net (code "236") (name "Net-(C707-C1)") (class "Default")
      (node (ref "C707") (pin "1") (pinfunction "C1_1") (pintype "passive"))
      (node (ref "FB701") (pin "1") (pinfunction "1_1") (pintype "passive"))
      (node (ref "U701") (pin "40") (pinfunction "IOVDD_40") (pintype "bidirectional"))
    )
    (net (code "237") (name "Net-(C709-C1)") (class "Default")
      (node (ref "C709") (pin "1") (pinfunction "C1_1") (pintype "passive"))
      (node (ref "C710") (pin "1") (pinfunction "C1_1") (pintype "passive"))
      (node (ref "U701") (pin "12") (pinfunction "CM_12") (pintype "bidirectional"))
      (node (ref "U701") (pin "13") (pinfunction "AIN1REF_13") (pintype "bidirectional"))
      (node (ref "U701") (pin "15") (pinfunction "AIN2REF_15") (pintype "bidirectional"))
      (node (ref "U701") (pin "17") (pinfunction "AIN3REF_17") (pintype "bidirectional"))
      (node (ref "U701") (pin "8") (pinfunction "AIN0REF_8") (pintype "bidirectional"))
    )
    (net (code "238") (name "Net-(C712-C2)") (class "Default")
      (node (ref "C712") (pin "2") (pinfunction "C2_2") (pintype "passive"))
      (node (ref "C713") (pin "2") (pinfunction "C2_2") (pintype "passive"))
      (node (ref "L701") (pin "1") (pinfunction "1_1") (pintype "passive"))
      (node (ref "R703") (pin "2") (pinfunction "2_2") (pintype "passive"))
    )
    (net (code "239") (name "Net-(C714-C2)") (class "Default")
      (node (ref "C714") (pin "2") (pinfunction "C2_2") (pintype "passive"))
      (node (ref "C715") (pin "2") (pinfunction "C2_2") (pintype "passive"))
      (node (ref "L702") (pin "1") (pinfunction "1_1") (pintype "passive"))
      (node (ref "R702") (pin "2") (pinfunction "2_2") (pintype "passive"))
    )
    (net (code "240") (name "Net-(C717-C2)") (class "Default")
      (node (ref "C717") (pin "2") (pinfunction "C2_2") (pintype "passive"))
      (node (ref "J701") (pin "2") (pinfunction "T_2") (pintype "bidirectional"))
      (node (ref "R708") (pin "1") (pinfunction "1_1") (pintype "passive"))
      (node (ref "R709") (pin "2") (pinfunction "2_2") (pintype "passive"))
    )
    (net (code "241") (name "Net-(C718-C2)") (class "Default")
      (node (ref "C718") (pin "2") (pinfunction "C2_2") (pintype "passive"))
      (node (ref "J701") (pin "3") (pinfunction "R_3") (pintype "bidirectional"))
      (node (ref "R704") (pin "1") (pinfunction "1_1") (pintype "passive"))
      (node (ref "R705") (pin "2") (pinfunction "2_2") (pintype "passive"))
    )
    (net (code "242") (name "Net-(C719-C2)") (class "Default")
      (node (ref "C719") (pin "2") (pinfunction "C2_2") (pintype "passive"))
      (node (ref "J702") (pin "2") (pinfunction "T_2") (pintype "bidirectional"))
      (node (ref "R710") (pin "1") (pinfunction "1_1") (pintype "passive"))
      (node (ref "R711") (pin "2") (pinfunction "2_2") (pintype "passive"))
    )
    (net (code "243") (name "Net-(C720-C2)") (class "Default")
      (node (ref "C720") (pin "2") (pinfunction "C2_2") (pintype "passive"))
      (node (ref "J702") (pin "3") (pinfunction "R_3") (pintype "bidirectional"))
      (node (ref "R706") (pin "1") (pinfunction "1_1") (pintype "passive"))
      (node (ref "R707") (pin "2") (pinfunction "2_2") (pintype "passive"))
    )
    (net (code "244") (name "Net-(C721-C1)") (class "Default")
      (node (ref "C721") (pin "1") (pinfunction "C1_1") (pintype "passive"))
      (node (ref "J703") (pin "3") (pinfunction "R_3") (pintype "bidirectional"))
      (node (ref "L702") (pin "2") (pinfunction "2_2") (pintype "passive"))
    )
    (net (code "245") (name "Net-(C722-C1)") (class "Default")
      (node (ref "C722") (pin "1") (pinfunction "C1_1") (pintype "passive"))
      (node (ref "J703") (pin "2") (pinfunction "T_2") (pintype "bidirectional"))
      (node (ref "L701") (pin "2") (pinfunction "2_2") (pintype "passive"))
    )
    (net (code "246") (name "Net-(C801-C2)") (class "Default")
      (node (ref "C801") (pin "2") (pinfunction "C2_2") (pintype "passive"))
      (node (ref "U201") (pin "B8") (pinfunction "MGTPRXP0_B8") (pintype "bidirectional"))
    )
    (net (code "247") (name "Net-(C802-C2)") (class "Default")
      (node (ref "C802") (pin "2") (pinfunction "C2_2") (pintype "passive"))
      (node (ref "U201") (pin "A8") (pinfunction "MGTPRXN0_A8") (pintype "bidirectional"))
    )
    (net (code "248") (name "Net-(C803-C2)") (class "Default")
      (node (ref "C803") (pin "2") (pinfunction "C2_2") (pintype "passive"))
      (node (ref "U201") (pin "B10") (pinfunction "MGTPRXP2_B10") (pintype "bidirectional"))
    )
    (net (code "249") (name "Net-(C804-C2)") (class "Default")
      (node (ref "C804") (pin "2") (pinfunction "C2_2") (pintype "passive"))
      (node (ref "U201") (pin "A10") (pinfunction "MGTPRXN2_A10") (pintype "bidirectional"))
    )
    (net (code "250") (name "Net-(C805-C2)") (class "Default")
      (node (ref "C805") (pin "2") (pinfunction "C2_2") (pintype "passive"))
      (node (ref "U201") (pin "D9") (pinfunction "MGTPRXP3_D9") (pintype "bidirectional"))
    )
    (net (code "251") (name "Net-(C806-C2)") (class "Default")
      (node (ref "C806") (pin "2") (pinfunction "C2_2") (pintype "passive"))
      (node (ref "U201") (pin "C9") (pinfunction "MGTPRXN3_C9") (pintype "bidirectional"))
    )
    (net (code "252") (name "Net-(C807-C1)") (class "Default")
      (node (ref "C807") (pin "1") (pinfunction "C1_1") (pintype "passive"))
      (node (ref "U201") (pin "B4") (pinfunction "MGTPTXP0_B4") (pintype "bidirectional"))
    )
    (net (code "253") (name "Net-(C808-C1)") (class "Default")
      (node (ref "C808") (pin "1") (pinfunction "C1_1") (pintype "passive"))
      (node (ref "U201") (pin "A4") (pinfunction "MGTPTXN0_A4") (pintype "bidirectional"))
    )
    (net (code "254") (name "Net-(C809-C1)") (class "Default")
      (node (ref "C809") (pin "1") (pinfunction "C1_1") (pintype "passive"))
      (node (ref "U201") (pin "B6") (pinfunction "MGTPTXP2_B6") (pintype "bidirectional"))
    )
    (net (code "255") (name "Net-(C810-C1)") (class "Default")
      (node (ref "C810") (pin "1") (pinfunction "C1_1") (pintype "passive"))
      (node (ref "U201") (pin "A6") (pinfunction "MGTPTXN2_A6") (pintype "bidirectional"))
    )
    (net (code "256") (name "Net-(C811-C1)") (class "Default")
      (node (ref "C811") (pin "1") (pinfunction "C1_1") (pintype "passive"))
      (node (ref "U201") (pin "D7") (pinfunction "MGTPTXP3_D7") (pintype "bidirectional"))
    )
    (net (code "257") (name "Net-(C812-C1)") (class "Default")
      (node (ref "C812") (pin "1") (pinfunction "C1_1") (pintype "passive"))
      (node (ref "U201") (pin "C7") (pinfunction "MGTPTXN3_C7") (pintype "bidirectional"))
    )
    (net (code "258") (name "Net-(C906-C1)") (class "Default")
      (node (ref "C906") (pin "1") (pinfunction "C1_1") (pintype "passive"))
      (node (ref "C907") (pin "1") (pinfunction "C1_1") (pintype "passive"))
      (node (ref "R903") (pin "2") (pinfunction "2_2") (pintype "passive"))
      (node (ref "U901") (pin "3") (pinfunction "CLK_3") (pintype "output"))
    )
    (net (code "259") (name "Net-(C907-C2)") (class "Default")
      (node (ref "C907") (pin "2") (pinfunction "C2_2") (pintype "passive"))
      (node (ref "U902") (pin "1") (pinfunction "XA_1") (pintype "bidirectional"))
    )
    (net (code "260") (name "Net-(C1001-C1)") (class "Default")
      (node (ref "C1001") (pin "1") (pinfunction "C1_1") (pintype "passive"))
      (node (ref "R1001") (pin "2") (pinfunction "2_2") (pintype "passive"))
      (node (ref "USB1001") (pin "SHIELD@0") (pinfunction "SHIELD_SHIELD@0") (pintype "bidirectional"))
      (node (ref "USB1001") (pin "SHIELD@1") (pinfunction "SHIELD_SHIELD@1") (pintype "bidirectional"))
      (node (ref "USB1001") (pin "SHIELD@2") (pinfunction "SHIELD_SHIELD@2") (pintype "bidirectional"))
      (node (ref "USB1001") (pin "SHIELD@3") (pinfunction "SHIELD_SHIELD@3") (pintype "bidirectional"))
    )
    (net (code "261") (name "Net-(C1009-C1)") (class "Default")
      (node (ref "C1009") (pin "1") (pinfunction "C1_1") (pintype "passive"))
      (node (ref "U1002") (pin "15") (pinfunction "VDD18_CORE_OUT_15") (pintype "bidirectional"))
      (node (ref "U1002") (pin "28") (pinfunction "VPP18_28") (pintype "bidirectional"))
    )
    (net (code "262") (name "Net-(C1011-C1)") (class "Default")
      (node (ref "C1011") (pin "1") (pinfunction "C1_1") (pintype "passive"))
      (node (ref "U1002") (pin "5") (pinfunction "VDD12_CORE_OUT_5") (pintype "bidirectional"))
    )
    (net (code "263") (name "Net-(C1014-C1)") (class "Default")
      (node (ref "C1014") (pin "1") (pinfunction "C1_1") (pintype "passive"))
      (node (ref "D1003") (pin "A") (pinfunction "A_A") (pintype "passive"))
      (node (ref "U1003") (pin "6") (pinfunction "VOUT_6") (pintype "bidirectional"))
    )
    (net (code "264") (name "Net-(C1104-C1)") (class "Default")
      (node (ref "C1104") (pin "1") (pinfunction "C1_1") (pintype "passive"))
      (node (ref "D1101") (pin "C") (pinfunction "C_C") (pintype "passive"))
      (node (ref "D1102") (pin "C") (pinfunction "C_C") (pintype "passive"))
      (node (ref "D1103") (pin "C") (pinfunction "C_C") (pintype "passive"))
      (node (ref "U1101") (pin "1") (pinfunction "VIN_1") (pintype "bidirectional"))
      (node (ref "U1101") (pin "4") (pinfunction "~{SHDN}_4") (pintype "bidirectional"))
    )
    (net (code "265") (name "Net-(C1115-C1)") (class "Default")
      (node (ref "C1115") (pin "1") (pinfunction "C1_1") (pintype "passive"))
      (node (ref "U1102") (pin "7") (pinfunction "VDD18_7") (pintype "bidirectional"))
    )
    (net (code "266") (name "Net-(C1120-C1)") (class "Default")
      (node (ref "C1120") (pin "1") (pinfunction "C1_1") (pintype "passive"))
      (node (ref "L1101") (pin "1") (pinfunction "1_1") (pintype "passive"))
      (node (ref "U1102") (pin "36") (pinfunction "SW_36") (pintype "bidirectional"))
      (node (ref "U1102") (pin "37") (pinfunction "SW_37") (pintype "bidirectional"))
      (node (ref "U1102") (pin "41") (pinfunction "SW_41") (pintype "bidirectional"))
    )
    (net (code "267") (name "Net-(C1120-C2)") (class "Default")
      (node (ref "C1120") (pin "2") (pinfunction "C2_2") (pintype "passive"))
      (node (ref "U1102") (pin "40") (pinfunction "BOOST_40") (pintype "bidirectional"))
    )
    (net (code "268") (name "Net-(C1121-C1)") (class "Default")
      (node (ref "C1121") (pin "1") (pinfunction "C1_1") (pintype "passive"))
      (node (ref "L1102") (pin "1") (pinfunction "1_1") (pintype "passive"))
      (node (ref "U1102") (pin "16") (pinfunction "SW_16") (pintype "bidirectional"))
      (node (ref "U1102") (pin "17") (pinfunction "SW_17") (pintype "bidirectional"))
      (node (ref "U1102") (pin "44") (pinfunction "SW_44") (pintype "bidirectional"))
    )
    (net (code "269") (name "Net-(C1121-C2)") (class "Default")
      (node (ref "C1121") (pin "2") (pinfunction "C2_2") (pintype "passive"))
      (node (ref "U1102") (pin "13") (pinfunction "BOOST_13") (pintype "bidirectional"))
    )
    (net (code "270") (name "Net-(C1206-C1)") (class "Default")
      (node (ref "C1206") (pin "1") (pinfunction "C1_1") (pintype "passive"))
      (node (ref "U1201") (pin "4") (pinfunction "SS_4") (pintype "bidirectional"))
    )
    (net (code "271") (name "Net-(C1207-C1)") (class "Default")
      (node (ref "C1207") (pin "1") (pinfunction "C1_1") (pintype "passive"))
      (node (ref "U1202") (pin "4") (pinfunction "SS_4") (pintype "bidirectional"))
    )
    (net (code "272") (name "Net-(C1208-C1)") (class "Default")
      (node (ref "C1208") (pin "1") (pinfunction "C1_1") (pintype "passive"))
      (node (ref "U1203") (pin "4") (pinfunction "SS_4") (pintype "bidirectional"))
    )
    (net (code "273") (name "Net-(C1211-C1)") (class "Default")
      (node (ref "C1211") (pin "1") (pinfunction "C1_1") (pintype "passive"))
      (node (ref "U1204") (pin "14") (pinfunction "SS_14") (pintype "bidirectional"))
    )
    (net (code "274") (name "Net-(C1221-C1)") (class "Default")
      (node (ref "C1221") (pin "1") (pinfunction "C1_1") (pintype "passive"))
      (node (ref "U1204") (pin "13") (pinfunction "SS_13") (pintype "bidirectional"))
    )
    (net (code "275") (name "Net-(C1231-C1)") (class "Default")
      (node (ref "C1231") (pin "1") (pinfunction "C1_1") (pintype "passive"))
      (node (ref "U1206") (pin "4") (pinfunction "SS_4") (pintype "bidirectional"))
    )
    (net (code "276") (name "Net-(C1233-C1)") (class "Default")
      (node (ref "C1233") (pin "1") (pinfunction "C1_1") (pintype "passive"))
      (node (ref "U1207") (pin "4") (pinfunction "SS_4") (pintype "bidirectional"))
    )
    (net (code "277") (name "Net-(C1249-C1)") (class "Default")
      (node (ref "C1249") (pin "1") (pinfunction "C1_1") (pintype "passive"))
      (node (ref "U1208") (pin "14") (pinfunction "SS_14") (pintype "bidirectional"))
    )
    (net (code "278") (name "Net-(C1251-C1)") (class "Default")
      (node (ref "C1251") (pin "1") (pinfunction "C1_1") (pintype "passive"))
      (node (ref "U1209") (pin "6") (pinfunction "SS_6") (pintype "bidirectional"))
    )
    (net (code "279") (name "Net-(C1252-C1)") (class "Default")
      (node (ref "C1252") (pin "1") (pinfunction "C1_1") (pintype "passive"))
      (node (ref "U1208") (pin "13") (pinfunction "SS_13") (pintype "bidirectional"))
    )
    (net (code "280") (name "Net-(CON801A-S)") (class "Default")
      (node (ref "CON801") (pin "A1") (pinfunction "S_A1") (pintype "passive"))
      (node (ref "CON801") (pin "B31") (pinfunction "S_B31") (pintype "passive"))
    )
    (net (code "281") (name "Net-(CON1101B-S)") (class "Default")
      (node (ref "CON1101") (pin "P$2") (pinfunction "S_P$2") (pintype "passive"))
      (node (ref "F1101") (pin "2") (pinfunction "2_2") (pintype "passive"))
    )
    (net (code "282") (name "Net-(D101-PadA)") (class "Default")
      (node (ref "D101") (pin "A") (pinfunction "A_A") (pintype "passive"))
      (node (ref "R101") (pin "1") (pinfunction "1_1") (pintype "passive"))
    )
    (net (code "283") (name "Net-(D505-PadA)") (class "Default")
      (node (ref "D505") (pin "A") (pinfunction "A_A") (pintype "passive"))
      (node (ref "R505") (pin "1") (pinfunction "1_1") (pintype "passive"))
    )
    (net (code "284") (name "Net-(D506-PadA)") (class "Default")
      (node (ref "D506") (pin "A") (pinfunction "A_A") (pintype "passive"))
      (node (ref "R506") (pin "1") (pinfunction "1_1") (pintype "passive"))
    )
    (net (code "285") (name "Net-(D507-PadA)") (class "Default")
      (node (ref "D507") (pin "A") (pinfunction "A_A") (pintype "passive"))
      (node (ref "R511") (pin "1") (pinfunction "1_1") (pintype "passive"))
    )
    (net (code "286") (name "Net-(D508-PadA)") (class "Default")
      (node (ref "D508") (pin "A") (pinfunction "A_A") (pintype "passive"))
      (node (ref "R512") (pin "1") (pinfunction "1_1") (pintype "passive"))
    )
    (net (code "287") (name "Net-(D1001-C1)") (class "Default")
      (node (ref "D1001") (pin "1") (pinfunction "C1_1") (pintype "bidirectional"))
      (node (ref "L1001") (pin "1") (pinfunction "1_1") (pintype "passive"))
      (node (ref "USB1001") (pin "A7") (pinfunction "D-_A7") (pintype "bidirectional"))
      (node (ref "USB1001") (pin "B7") (pinfunction "D-_B7") (pintype "bidirectional"))
    )
    (net (code "288") (name "Net-(D1001-C2)") (class "Default")
      (node (ref "D1001") (pin "2") (pinfunction "C2_2") (pintype "bidirectional"))
      (node (ref "L1001") (pin "4") (pinfunction "4_4") (pintype "passive"))
      (node (ref "USB1001") (pin "A6") (pinfunction "D+_A6") (pintype "bidirectional"))
      (node (ref "USB1001") (pin "B6") (pinfunction "D+_B6") (pintype "bidirectional"))
    )
    (net (code "289") (name "Net-(D1004-PadA)") (class "Default")
      (node (ref "D1004") (pin "A") (pinfunction "A_A") (pintype "passive"))
      (node (ref "R1013") (pin "1") (pinfunction "1_1") (pintype "passive"))
    )
    (net (code "290") (name "Net-(D1104-PadA)") (class "Default")
      (node (ref "D1104") (pin "A") (pinfunction "A_A") (pintype "passive"))
      (node (ref "R1119") (pin "1") (pinfunction "1_1") (pintype "passive"))
    )
    (net (code "291") (name "Net-(F1001-Pad2)") (class "Default")
      (node (ref "F1001") (pin "2") (pinfunction "2_2") (pintype "passive"))
      (node (ref "USB1001") (pin "A4/B9") (pinfunction "VBUS_A4/B9") (pintype "bidirectional"))
      (node (ref "USB1001") (pin "B4/A9") (pinfunction "VBUS_B4/A9") (pintype "bidirectional"))
    )
    (net (code "292") (name "Net-(J101A-A)") (class "Default")
      (node (ref "J101") (pin "11") (pinfunction "A_11") (pintype "passive"))
      (node (ref "R119") (pin "1") (pinfunction "1_1") (pintype "passive"))
    )
    (net (code "293") (name "Net-(J101C-A)") (class "Default")
      (node (ref "J101") (pin "13") (pinfunction "A_13") (pintype "passive"))
      (node (ref "R118") (pin "1") (pinfunction "1_1") (pintype "passive"))
    )
    (net (code "294") (name "Net-(JP101A-S)") (class "Default")
      (node (ref "JP101") (pin "1") (pinfunction "S_1") (pintype "passive"))
      (node (ref "R114") (pin "1") (pinfunction "1_1") (pintype "passive"))
    )
    (net (code "295") (name "Net-(JP101B-S)") (class "Default")
      (node (ref "JP101") (pin "2") (pinfunction "S_2") (pintype "passive"))
      (node (ref "R115") (pin "1") (pinfunction "1_1") (pintype "passive"))
    )
    (net (code "296") (name "Net-(JP201B-S)") (class "Default")
      (node (ref "JP201") (pin "2") (pinfunction "S_2") (pintype "passive"))
      (node (ref "R203") (pin "1") (pinfunction "1_1") (pintype "passive"))
    )
    (net (code "297") (name "Net-(JP201D-S)") (class "Default")
      (node (ref "JP201") (pin "4") (pinfunction "S_4") (pintype "passive"))
      (node (ref "R204") (pin "1") (pinfunction "1_1") (pintype "passive"))
    )
    (net (code "298") (name "Net-(JP201F-S)") (class "Default")
      (node (ref "JP201") (pin "6") (pinfunction "S_6") (pintype "passive"))
      (node (ref "R206") (pin "1") (pinfunction "1_1") (pintype "passive"))
    )
    (net (code "299") (name "Net-(JP202A-S)") (class "Default")
      (node (ref "JP202") (pin "1") (pinfunction "S_1") (pintype "passive"))
      (node (ref "R211") (pin "1") (pinfunction "1_1") (pintype "passive"))
    )
    (net (code "300") (name "Net-(JP202B-S)") (class "Default")
      (node (ref "JP202") (pin "2") (pinfunction "S_2") (pintype "passive"))
      (node (ref "R208") (pin "1") (pinfunction "1_1") (pintype "passive"))
    )
    (net (code "301") (name "Net-(JP202C-S)") (class "Default")
      (node (ref "JP202") (pin "3") (pinfunction "S_3") (pintype "passive"))
      (node (ref "R212") (pin "1") (pinfunction "1_1") (pintype "passive"))
    )
    (net (code "302") (name "Net-(JP202D-S)") (class "Default")
      (node (ref "JP202") (pin "4") (pinfunction "S_4") (pintype "passive"))
      (node (ref "R209") (pin "1") (pinfunction "1_1") (pintype "passive"))
    )
    (net (code "303") (name "Net-(JP202E-S)") (class "Default")
      (node (ref "JP202") (pin "5") (pinfunction "S_5") (pintype "passive"))
      (node (ref "R213") (pin "1") (pinfunction "1_1") (pintype "passive"))
    )
    (net (code "304") (name "Net-(L1201-Pad2)") (class "Default")
      (node (ref "L1201") (pin "2") (pinfunction "2_2") (pintype "passive"))
      (node (ref "U1204") (pin "3") (pinfunction "SW_3") (pintype "bidirectional"))
    )
    (net (code "305") (name "Net-(L1202-Pad1)") (class "Default")
      (node (ref "L1202") (pin "1") (pinfunction "1_1") (pintype "passive"))
      (node (ref "U1204") (pin "4") (pinfunction "SW_4") (pintype "bidirectional"))
    )
    (net (code "306") (name "Net-(L1203-Pad2)") (class "Default")
      (node (ref "L1203") (pin "2") (pinfunction "2_2") (pintype "passive"))
      (node (ref "U1208") (pin "3") (pinfunction "SW_3") (pintype "bidirectional"))
    )
    (net (code "307") (name "Net-(L1204-Pad1)") (class "Default")
      (node (ref "L1204") (pin "1") (pinfunction "1_1") (pintype "passive"))
      (node (ref "U1208") (pin "4") (pinfunction "SW_4") (pintype "bidirectional"))
    )
    (net (code "308") (name "Net-(Q101-D)") (class "Default")
      (node (ref "D102") (pin "A") (pinfunction "A_A") (pintype "passive"))
      (node (ref "Q101") (pin "3") (pinfunction "D_3") (pintype "passive"))
      (node (ref "R106") (pin "1") (pinfunction "1_1") (pintype "passive"))
    )
    (net (code "309") (name "Net-(Q102-D)") (class "Default")
      (node (ref "Q102") (pin "3") (pinfunction "D_3") (pintype "passive"))
      (node (ref "R108") (pin "1") (pinfunction "1_1") (pintype "passive"))
      (node (ref "U102") (pin "56") (pinfunction "GPIO3_56") (pintype "bidirectional"))
    )
    (net (code "310") (name "Net-(Q1101-D)") (class "Default")
      (node (ref "Q1101") (pin "3") (pinfunction "D_3") (pintype "passive"))
      (node (ref "R1107") (pin "1") (pinfunction "1_1") (pintype "passive"))
    )
    (net (code "311") (name "Net-(Q1102A-G)") (class "Default")
      (node (ref "Q1102") (pin "2") (pinfunction "G_2") (pintype "passive"))
      (node (ref "Q1102") (pin "4") (pinfunction "G_4") (pintype "passive"))
      (node (ref "R1106") (pin "1") (pinfunction "1_1") (pintype "passive"))
      (node (ref "R1107") (pin "2") (pinfunction "2_2") (pintype "passive"))
    )
    (net (code "312") (name "Net-(Q1102A-S)") (class "Default")
      (node (ref "Q1102") (pin "1") (pinfunction "S_1") (pintype "passive"))
      (node (ref "Q1102") (pin "3") (pinfunction "S_3") (pintype "passive"))
      (node (ref "R1106") (pin "2") (pinfunction "2_2") (pintype "passive"))
    )
    (net (code "313") (name "Net-(Q1103-D)") (class "Default")
      (node (ref "Q1103") (pin "3") (pinfunction "D_3") (pintype "passive"))
      (node (ref "R1114") (pin "1") (pinfunction "1_1") (pintype "passive"))
    )
    (net (code "314") (name "Net-(Q1104A-G)") (class "Default")
      (node (ref "Q1104") (pin "2") (pinfunction "G_2") (pintype "passive"))
      (node (ref "Q1104") (pin "4") (pinfunction "G_4") (pintype "passive"))
      (node (ref "R1113") (pin "1") (pinfunction "1_1") (pintype "passive"))
      (node (ref "R1114") (pin "2") (pinfunction "2_2") (pintype "passive"))
    )
    (net (code "315") (name "Net-(Q1104A-S)") (class "Default")
      (node (ref "Q1104") (pin "1") (pinfunction "S_1") (pintype "passive"))
      (node (ref "Q1104") (pin "3") (pinfunction "S_3") (pintype "passive"))
      (node (ref "R1113") (pin "2") (pinfunction "2_2") (pintype "passive"))
    )
    (net (code "316") (name "Net-(Q1105A-G)") (class "Default")
      (node (ref "Q1105") (pin "2") (pinfunction "G_2") (pintype "passive"))
      (node (ref "Q1105") (pin "4") (pinfunction "G_4") (pintype "passive"))
      (node (ref "R1116") (pin "1") (pinfunction "1_1") (pintype "passive"))
      (node (ref "R1117") (pin "2") (pinfunction "2_2") (pintype "passive"))
    )
    (net (code "317") (name "Net-(Q1105A-S)") (class "Default")
      (node (ref "Q1105") (pin "1") (pinfunction "S_1") (pintype "passive"))
      (node (ref "Q1105") (pin "3") (pinfunction "S_3") (pintype "passive"))
      (node (ref "R1116") (pin "2") (pinfunction "2_2") (pintype "passive"))
    )
    (net (code "318") (name "Net-(Q1106-D)") (class "Default")
      (node (ref "Q1106") (pin "3") (pinfunction "D_3") (pintype "passive"))
      (node (ref "R1117") (pin "1") (pinfunction "1_1") (pintype "passive"))
    )
    (net (code "319") (name "Net-(R1202-Pad1)") (class "Default")
      (node (ref "R1202") (pin "1") (pinfunction "1_1") (pintype "passive"))
      (node (ref "R1203") (pin "2") (pinfunction "2_2") (pintype "passive"))
      (node (ref "U1204") (pin "16") (pinfunction "FB_16") (pintype "bidirectional"))
    )
    (net (code "320") (name "Net-(R1205-Pad1)") (class "Default")
      (node (ref "R1205") (pin "1") (pinfunction "1_1") (pintype "passive"))
      (node (ref "R1206") (pin "2") (pinfunction "2_2") (pintype "passive"))
      (node (ref "U1204") (pin "11") (pinfunction "FB_11") (pintype "bidirectional"))
    )
    (net (code "321") (name "Net-(R1208-Pad1)") (class "Default")
      (node (ref "R1208") (pin "1") (pinfunction "1_1") (pintype "passive"))
      (node (ref "R1209") (pin "2") (pinfunction "2_2") (pintype "passive"))
      (node (ref "U1208") (pin "16") (pinfunction "FB_16") (pintype "bidirectional"))
    )
    (net (code "322") (name "Net-(R1212-Pad1)") (class "Default")
      (node (ref "R1212") (pin "1") (pinfunction "1_1") (pintype "passive"))
      (node (ref "R1213") (pin "2") (pinfunction "2_2") (pintype "passive"))
      (node (ref "U1208") (pin "11") (pinfunction "FB_11") (pintype "bidirectional"))
    )
    (net (code "323") (name "Net-(RFCON101-SIGNAL)") (class "Default")
      (node (ref "RFCON101") (pin "P$3") (pinfunction "SIGNAL_P$3") (pintype "bidirectional"))
      (node (ref "U102") (pin "111") (pinfunction "VDAC_COMP_111") (pintype "bidirectional"))
    )
    (net (code "324") (name "Net-(RFCON505-SIGNAL)") (class "Default")
      (node (ref "R513") (pin "2") (pinfunction "2_2") (pintype "passive"))
      (node (ref "R514") (pin "2") (pinfunction "2_2") (pintype "passive"))
      (node (ref "RFCON505") (pin "P$3") (pinfunction "SIGNAL_P$3") (pintype "bidirectional"))
    )
    (net (code "325") (name "Net-(RFCON506-SIGNAL)") (class "Default")
      (node (ref "R515") (pin "2") (pinfunction "2_2") (pintype "passive"))
      (node (ref "R516") (pin "2") (pinfunction "2_2") (pintype "passive"))
      (node (ref "RFCON506") (pin "P$3") (pinfunction "SIGNAL_P$3") (pintype "bidirectional"))
    )
    (net (code "326") (name "Net-(RFCON901-SIGNAL)") (class "Default")
      (node (ref "R901") (pin "2") (pinfunction "2_2") (pintype "passive"))
      (node (ref "R902") (pin "2") (pinfunction "2_2") (pintype "passive"))
      (node (ref "RFCON901") (pin "P$3") (pinfunction "SIGNAL_P$3") (pintype "bidirectional"))
    )
    (net (code "327") (name "Net-(T501-PRI1)") (class "Default")
      (node (ref "D501") (pin "1") (pinfunction "1_1") (pintype "passive"))
      (node (ref "RFCON501") (pin "SIGNAL") (pinfunction "SIGNAL_SIGNAL") (pintype "bidirectional"))
      (node (ref "T501") (pin "3") (pinfunction "PRI1_3") (pintype "passive"))
    )
    (net (code "328") (name "Net-(T502-PRI1)") (class "Default")
      (node (ref "D502") (pin "1") (pinfunction "1_1") (pintype "passive"))
      (node (ref "RFCON502") (pin "SIGNAL") (pinfunction "SIGNAL_SIGNAL") (pintype "bidirectional"))
      (node (ref "T502") (pin "3") (pinfunction "PRI1_3") (pintype "passive"))
    )
    (net (code "329") (name "Net-(T507-PRI1)") (class "Default")
      (node (ref "D509") (pin "1") (pinfunction "1_1") (pintype "passive"))
      (node (ref "RFCON507") (pin "SIGNAL") (pinfunction "SIGNAL_SIGNAL") (pintype "bidirectional"))
      (node (ref "T507") (pin "3") (pinfunction "PRI1_3") (pintype "passive"))
    )
    (net (code "330") (name "Net-(T508-PRI1)") (class "Default")
      (node (ref "D510") (pin "1") (pinfunction "1_1") (pintype "passive"))
      (node (ref "RFCON508") (pin "SIGNAL") (pinfunction "SIGNAL_SIGNAL") (pintype "bidirectional"))
      (node (ref "T508") (pin "3") (pinfunction "PRI1_3") (pintype "passive"))
    )
    (net (code "331") (name "Net-(U101-ILIMIT)") (class "Default")
      (node (ref "R104") (pin "2") (pinfunction "2_2") (pintype "passive"))
      (node (ref "U101") (pin "5") (pinfunction "ILIMIT_5") (pintype "bidirectional"))
    )
    (net (code "332") (name "Net-(U102E-ETH_SYNC_IN)") (class "Default")
      (node (ref "R111") (pin "1") (pinfunction "1_1") (pintype "passive"))
      (node (ref "U102") (pin "16") (pinfunction "ETH_SYNC_IN_16") (pintype "bidirectional"))
    )
    (net (code "333") (name "Net-(U102E-ETH_SYNC_OUT)") (class "Default")
      (node (ref "R113") (pin "1") (pinfunction "1_1") (pintype "passive"))
      (node (ref "U102") (pin "18") (pinfunction "ETH_SYNC_OUT_18") (pintype "bidirectional"))
    )
    (net (code "334") (name "Net-(U102J-~{BT_DISABLE})") (class "Default")
      (node (ref "R107") (pin "2") (pinfunction "2_2") (pintype "passive"))
      (node (ref "U102") (pin "91") (pinfunction "~{BT_DISABLE}_91") (pintype "bidirectional"))
    )
    (net (code "335") (name "Net-(U102J-~{EEPROM_WP})") (class "Default")
      (node (ref "R109") (pin "2") (pinfunction "2_2") (pintype "passive"))
      (node (ref "U102") (pin "20") (pinfunction "~{EEPROM_WP}_20") (pintype "bidirectional"))
    )
    (net (code "336") (name "Net-(U102J-~{WL_DISABLE})") (class "Default")
      (node (ref "R105") (pin "2") (pinfunction "2_2") (pintype "passive"))
      (node (ref "U102") (pin "89") (pinfunction "~{WL_DISABLE}_89") (pintype "bidirectional"))
    )
    (net (code "337") (name "Net-(U201J-MGTRREF)") (class "Default")
      (node (ref "R210") (pin "1") (pinfunction "1_1") (pintype "passive"))
      (node (ref "U201") (pin "F8") (pinfunction "MGTRREF_F8") (pintype "bidirectional"))
    )
    (net (code "338") (name "Net-(U301-ZQ)") (class "Default")
      (node (ref "R301") (pin "2") (pinfunction "2_2") (pintype "passive"))
      (node (ref "U301") (pin "L8") (pinfunction "ZQ_L8") (pintype "bidirectional"))
    )
    (net (code "339") (name "Net-(U401B-RBIAS)") (class "Default")
      (node (ref "R403") (pin "2") (pinfunction "2_2") (pintype "passive"))
      (node (ref "U401") (pin "L4") (pinfunction "RBIAS_L4") (pintype "bidirectional"))
    )
    (net (code "340") (name "Net-(U501-ILIMIT)") (class "Default")
      (node (ref "R501") (pin "2") (pinfunction "2_2") (pintype "passive"))
      (node (ref "U501") (pin "5") (pinfunction "ILIMIT_5") (pintype "bidirectional"))
    )
    (net (code "341") (name "Net-(U502-ILIMIT)") (class "Default")
      (node (ref "R502") (pin "2") (pinfunction "2_2") (pintype "passive"))
      (node (ref "U502") (pin "5") (pinfunction "ILIMIT_5") (pintype "bidirectional"))
    )
    (net (code "342") (name "Net-(U503-ILIMIT)") (class "Default")
      (node (ref "R507") (pin "2") (pinfunction "2_2") (pintype "passive"))
      (node (ref "U503") (pin "5") (pinfunction "ILIMIT_5") (pintype "bidirectional"))
    )
    (net (code "343") (name "Net-(U504-ILIMIT)") (class "Default")
      (node (ref "R508") (pin "2") (pinfunction "2_2") (pintype "passive"))
      (node (ref "U504") (pin "5") (pinfunction "ILIMIT_5") (pintype "bidirectional"))
    )
    (net (code "344") (name "Net-(U902-CLK0)") (class "Default")
      (node (ref "R906") (pin "2") (pinfunction "2_2") (pintype "passive"))
      (node (ref "U902") (pin "13") (pinfunction "CLK0_13") (pintype "bidirectional"))
    )
    (net (code "345") (name "Net-(U902-CLK1)") (class "Default")
      (node (ref "R910") (pin "2") (pinfunction "2_2") (pintype "passive"))
      (node (ref "U902") (pin "12") (pinfunction "CLK1_12") (pintype "bidirectional"))
    )
    (net (code "346") (name "Net-(U902-CLK2)") (class "Default")
      (node (ref "R907") (pin "2") (pinfunction "2_2") (pintype "passive"))
      (node (ref "U902") (pin "9") (pinfunction "CLK2_9") (pintype "bidirectional"))
    )
    (net (code "347") (name "Net-(U902-CLK3)") (class "Default")
      (node (ref "R911") (pin "2") (pinfunction "2_2") (pintype "passive"))
      (node (ref "U902") (pin "8") (pinfunction "CLK3_8") (pintype "bidirectional"))
    )
    (net (code "348") (name "Net-(U902-CLK4)") (class "Default")
      (node (ref "R908") (pin "2") (pinfunction "2_2") (pintype "passive"))
      (node (ref "U902") (pin "19") (pinfunction "CLK4_19") (pintype "bidirectional"))
    )
    (net (code "349") (name "Net-(U902-CLK5)") (class "Default")
      (node (ref "R912") (pin "2") (pinfunction "2_2") (pintype "passive"))
      (node (ref "U902") (pin "17") (pinfunction "CLK5_17") (pintype "bidirectional"))
    )
    (net (code "350") (name "Net-(U902-CLK6)") (class "Default")
      (node (ref "R909") (pin "2") (pinfunction "2_2") (pintype "passive"))
      (node (ref "U902") (pin "16") (pinfunction "CLK6_16") (pintype "bidirectional"))
    )
    (net (code "351") (name "Net-(U902-CLK7)") (class "Default")
      (node (ref "R913") (pin "2") (pinfunction "2_2") (pintype "passive"))
      (node (ref "U902") (pin "15") (pinfunction "CLK7_15") (pintype "bidirectional"))
    )
    (net (code "352") (name "Net-(U902-CLKIN)") (class "Default")
      (node (ref "R902") (pin "1") (pinfunction "1_1") (pintype "passive"))
      (node (ref "U902") (pin "6") (pinfunction "CLKIN_6") (pintype "bidirectional"))
    )
    (net (code "353") (name "Net-(U1002-PA07{slash}SPI_MOSI_SI)") (class "Default")
      (node (ref "R1008") (pin "2") (pinfunction "2_2") (pintype "passive"))
      (node (ref "U1002") (pin "20") (pinfunction "PA07/SPI_MOSI_SI_20") (pintype "bidirectional"))
    )
    (net (code "354") (name "Net-(U1002-PA08{slash}SPI_MISO)") (class "Default")
      (node (ref "TP9") (pin "TP") (pinfunction "TP_TP") (pintype "input"))
      (node (ref "U1002") (pin "22") (pinfunction "PA08/SPI_MISO_22") (pintype "bidirectional"))
    )
    (net (code "355") (name "Net-(U1002-PA09{slash}SPI_CLK)") (class "Default")
      (node (ref "TP10") (pin "TP") (pinfunction "TP_TP") (pintype "input"))
      (node (ref "U1002") (pin "23") (pinfunction "PA09/SPI_CLK_23") (pintype "bidirectional"))
    )
    (net (code "356") (name "Net-(U1002-PA10{slash}~{SPI_SS0})") (class "Default")
      (node (ref "TP8") (pin "TP") (pinfunction "TP_TP") (pintype "input"))
      (node (ref "U1002") (pin "24") (pinfunction "PA10/~{SPI_SS0}_24") (pintype "bidirectional"))
    )
    (net (code "357") (name "Net-(U1002-PA11{slash}SPI_MOSI)") (class "Default")
      (node (ref "R1008") (pin "1") (pinfunction "1_1") (pintype "passive"))
      (node (ref "U1002") (pin "25") (pinfunction "PA11/SPI_MOSI_25") (pintype "bidirectional"))
    )
    (net (code "358") (name "Net-(U1002-PA14{slash}~{IRQ})") (class "Default")
      (node (ref "TP12") (pin "TP") (pinfunction "TP_TP") (pintype "input"))
      (node (ref "U1002") (pin "29") (pinfunction "PA14/~{IRQ}_29") (pintype "bidirectional"))
    )
    (net (code "359") (name "Net-(U1003-ILIMIT)") (class "Default")
      (node (ref "R1010") (pin "2") (pinfunction "2_2") (pintype "passive"))
      (node (ref "U1003") (pin "5") (pinfunction "ILIMIT_5") (pintype "bidirectional"))
    )
    (net (code "360") (name "Net-(U1102A-RUN)") (class "Default")
      (node (ref "R1123") (pin "1") (pinfunction "1_1") (pintype "passive"))
      (node (ref "U1102") (pin "24") (pinfunction "RUN_24") (pintype "bidirectional"))
    )
    (net (code "361") (name "Net-(U1102C-ASEL)") (class "Default")
      (node (ref "R1128") (pin "2") (pinfunction "2_2") (pintype "passive"))
      (node (ref "U1102") (pin "10") (pinfunction "ASEL_10") (pintype "bidirectional"))
    )
    (net (code "362") (name "Net-(U1102C-SYNC{slash}PWM_CFG)") (class "Default")
      (node (ref "R1127") (pin "2") (pinfunction "2_2") (pintype "passive"))
      (node (ref "U1102") (pin "22") (pinfunction "SYNC/PWM_CFG_22") (pintype "bidirectional"))
    )
    (net (code "363") (name "Net-(U1102C-VOUT0_CFG)") (class "Default")
      (node (ref "R1126") (pin "2") (pinfunction "2_2") (pintype "passive"))
      (node (ref "U1102") (pin "8") (pinfunction "VOUT0_CFG_8") (pintype "bidirectional"))
    )
    (net (code "364") (name "Net-(U1102C-VOUT1_CFG{slash}POLYPHASE_CFG)") (class "Default")
      (node (ref "R1125") (pin "2") (pinfunction "2_2") (pintype "passive"))
      (node (ref "U1102") (pin "9") (pinfunction "VOUT1_CFG/POLYPHASE_CFG_9") (pintype "bidirectional"))
    )
    (net (code "365") (name "Net-(U1102C-WP)") (class "Default")
      (node (ref "R1120") (pin "1") (pinfunction "1_1") (pintype "passive"))
      (node (ref "U1102") (pin "26") (pinfunction "WP_26") (pintype "bidirectional"))
    )
    (net (code "366") (name "Net-(U1209-FB)") (class "Default")
      (node (ref "R1214") (pin "1") (pinfunction "1_1") (pintype "passive"))
      (node (ref "R1215") (pin "2") (pinfunction "2_2") (pintype "passive"))
      (node (ref "U1209") (pin "4") (pinfunction "FB_4") (pintype "bidirectional"))
    )
    (net (code "367") (name "Net-(U1209-SW)") (class "Default")
      (node (ref "L1205") (pin "1") (pinfunction "1_1") (pintype "passive"))
      (node (ref "U1209") (pin "1") (pinfunction "SW_1") (pintype "bidirectional"))
    )
    (net (code "368") (name "PCIE_CM4_REFCLK_N") (class "Default")
      (node (ref "U102") (pin "112") (pinfunction "PCIE_CLK_N_112") (pintype "bidirectional"))
      (node (ref "U201") (pin "E6") (pinfunction "MGTREFCLK0N_E6") (pintype "bidirectional"))
    )
    (net (code "369") (name "PCIE_CM4_REFCLK_P") (class "Default")
      (node (ref "U102") (pin "110") (pinfunction "PCIE_CLK_P_110") (pintype "bidirectional"))
      (node (ref "U201") (pin "F6") (pinfunction "MGTREFCLK0P_F6") (pintype "bidirectional"))
    )
    (net (code "370") (name "PCIE_CM4_RX_N") (class "Default")
      (node (ref "C808") (pin "2") (pinfunction "C2_2") (pintype "passive"))
      (node (ref "U102") (pin "118") (pinfunction "PCIE_RX_N_118") (pintype "bidirectional"))
    )
    (net (code "371") (name "PCIE_CM4_RX_P") (class "Default")
      (node (ref "C807") (pin "2") (pinfunction "C2_2") (pintype "passive"))
      (node (ref "U102") (pin "116") (pinfunction "PCIE_RX_P_116") (pintype "bidirectional"))
    )
    (net (code "372") (name "PCIE_CM4_TX_N") (class "Default")
      (node (ref "C802") (pin "1") (pinfunction "C1_1") (pintype "passive"))
      (node (ref "U102") (pin "124") (pinfunction "PCIE_TX_N_124") (pintype "bidirectional"))
    )
    (net (code "373") (name "PCIE_CM4_TX_P") (class "Default")
      (node (ref "C801") (pin "1") (pinfunction "C1_1") (pintype "passive"))
      (node (ref "U102") (pin "122") (pinfunction "PCIE_TX_P_122") (pintype "bidirectional"))
    )
    (net (code "374") (name "PCIE_SLOT_REFCLK_N") (class "Default")
      (node (ref "CON801") (pin "A14") (pinfunction "S_A14") (pintype "passive"))
      (node (ref "U201") (pin "E10") (pinfunction "MGTREFCLK1N_E10") (pintype "bidirectional"))
    )
    (net (code "375") (name "PCIE_SLOT_REFCLK_P") (class "Default")
      (node (ref "CON801") (pin "A13") (pinfunction "S_A13") (pintype "passive"))
      (node (ref "U201") (pin "F10") (pinfunction "MGTREFCLK1P_F10") (pintype "bidirectional"))
    )
    (net (code "376") (name "PCIE_SLOT_RX0_N") (class "Default")
      (node (ref "C810") (pin "2") (pinfunction "C2_2") (pintype "passive"))
      (node (ref "CON801") (pin "A17") (pinfunction "S_A17") (pintype "passive"))
    )
    (net (code "377") (name "PCIE_SLOT_RX0_P") (class "Default")
      (node (ref "C809") (pin "2") (pinfunction "C2_2") (pintype "passive"))
      (node (ref "CON801") (pin "A16") (pinfunction "S_A16") (pintype "passive"))
    )
    (net (code "378") (name "PCIE_SLOT_RX1_N") (class "Default")
      (node (ref "C812") (pin "2") (pinfunction "C2_2") (pintype "passive"))
      (node (ref "CON801") (pin "A22") (pinfunction "S_A22") (pintype "passive"))
    )
    (net (code "379") (name "PCIE_SLOT_RX1_P") (class "Default")
      (node (ref "C811") (pin "2") (pinfunction "C2_2") (pintype "passive"))
      (node (ref "CON801") (pin "A21") (pinfunction "S_A21") (pintype "passive"))
    )
    (net (code "380") (name "PCIE_SLOT_TX0_N") (class "Default")
      (node (ref "C804") (pin "1") (pinfunction "C1_1") (pintype "passive"))
      (node (ref "CON801") (pin "B15") (pinfunction "S_B15") (pintype "passive"))
    )
    (net (code "381") (name "PCIE_SLOT_TX0_P") (class "Default")
      (node (ref "C803") (pin "1") (pinfunction "C1_1") (pintype "passive"))
      (node (ref "CON801") (pin "B14") (pinfunction "S_B14") (pintype "passive"))
    )
    (net (code "382") (name "PCIE_SLOT_TX1_N") (class "Default")
      (node (ref "C806") (pin "1") (pinfunction "C1_1") (pintype "passive"))
      (node (ref "CON801") (pin "B20") (pinfunction "S_B20") (pintype "passive"))
    )
    (net (code "383") (name "PCIE_SLOT_TX1_P") (class "Default")
      (node (ref "C805") (pin "1") (pinfunction "C1_1") (pintype "passive"))
      (node (ref "CON801") (pin "B19") (pinfunction "S_B19") (pintype "passive"))
    )
    (net (code "384") (name "PMC_LED") (class "Default")
      (node (ref "R1013") (pin "2") (pinfunction "2_2") (pintype "passive"))
      (node (ref "U1002") (pin "10") (pinfunction "PA00_10") (pintype "bidirectional"))
    )
    (net (code "385") (name "PMC_SWCLK") (class "Default")
      (node (ref "TC1001") (pin "4") (pinfunction "S_4") (pintype "passive"))
      (node (ref "U1002") (pin "7") (pinfunction "PA30_7") (pintype "bidirectional"))
    )
    (net (code "386") (name "PMC_SWDIO") (class "Default")
      (node (ref "TC1001") (pin "2") (pinfunction "S_2") (pintype "passive"))
      (node (ref "U1002") (pin "8") (pinfunction "PA31_8") (pintype "bidirectional"))
    )
    (net (code "387") (name "PMC_SWO") (class "Default")
      (node (ref "R1012") (pin "2") (pinfunction "2_2") (pintype "passive"))
      (node (ref "TC1001") (pin "6") (pinfunction "S_6") (pintype "passive"))
      (node (ref "U1002") (pin "34") (pinfunction "PA18/GPO4_34") (pintype "bidirectional"))
    )
    (net (code "388") (name "PM_I2C_EN") (class "Default")
      (node (ref "R1003") (pin "2") (pinfunction "2_2") (pintype "passive"))
      (node (ref "U1001") (pin "1") (pinfunction "ENABLE_1") (pintype "bidirectional"))
      (node (ref "U201") (pin "AA18") (pinfunction "IO_L17P/T2/A14/D30_AA18") (pintype "bidirectional"))
    )
    (net (code "389") (name "PM_I2C_SCL") (class "Default")
      (node (ref "R1004") (pin "1") (pinfunction "1_1") (pintype "passive"))
      (node (ref "U1001") (pin "2") (pinfunction "SCLOUT_2") (pintype "bidirectional"))
      (node (ref "U1002") (pin "32") (pinfunction "PA17_32") (pintype "bidirectional"))
      (node (ref "U1102") (pin "30") (pinfunction "SCL_30") (pintype "bidirectional"))
    )
    (net (code "390") (name "PM_I2C_SDA") (class "Default")
      (node (ref "R1007") (pin "1") (pinfunction "1_1") (pintype "passive"))
      (node (ref "U1001") (pin "7") (pinfunction "SDAOUT_7") (pintype "bidirectional"))
      (node (ref "U1002") (pin "31") (pinfunction "PA16_31") (pintype "bidirectional"))
      (node (ref "U1102") (pin "31") (pinfunction "SDA_31") (pintype "bidirectional"))
    )
    (net (code "391") (name "SYNTH_CE") (class "Default")
      (node (ref "R603") (pin "2") (pinfunction "2_2") (pintype "passive"))
      (node (ref "U201") (pin "Y17") (pinfunction "IO_0_Y17") (pintype "bidirectional"))
      (node (ref "U601") (pin "29") (pinfunction "CE_29") (pintype "bidirectional"))
    )
    (net (code "392") (name "SYNTH_LD") (class "Default")
      (node (ref "U201") (pin "AB20") (pinfunction "IO_L15N/T2_DQS/~{CSO}/DOUT_AB20") (pintype "bidirectional"))
      (node (ref "U601") (pin "8") (pinfunction "LD_8") (pintype "bidirectional"))
    )
    (net (code "393") (name "SYNTH_MUTE") (class "Default")
      (node (ref "U201") (pin "AB21") (pinfunction "IO_L10P/T1/D14_AB21") (pintype "bidirectional"))
      (node (ref "U601") (pin "7") (pinfunction "MUTE_7") (pintype "bidirectional"))
    )
    (net (code "394") (name "SYNTH_REF_CLK") (class "Default")
      (node (ref "C601") (pin "1") (pinfunction "C1_1") (pintype "passive"))
      (node (ref "R602") (pin "2") (pinfunction "2_2") (pintype "passive"))
      (node (ref "R912") (pin "1") (pinfunction "1_1") (pintype "passive"))
    )
    (net (code "395") (name "SYNTH_SPI_MISO") (class "Default")
      (node (ref "U201") (pin "AB18") (pinfunction "IO_L17N/T2/A13/D29_AB18") (pintype "bidirectional"))
      (node (ref "U601") (pin "27") (pinfunction "SDO_27") (pintype "bidirectional"))
    )
    (net (code "396") (name "SYNTH_SPI_MOSI") (class "Default")
      (node (ref "U201") (pin "AB17") (pinfunction "IO_L2N/T0_AB17") (pintype "bidirectional"))
      (node (ref "U601") (pin "28") (pinfunction "SDIO_28") (pintype "bidirectional"))
    )
    (net (code "397") (name "SYNTH_SPI_SCK") (class "Default")
      (node (ref "U201") (pin "AA19") (pinfunction "IO_L15P/T2_DQS/RD/~{WR}_AA19") (pintype "bidirectional"))
      (node (ref "U601") (pin "26") (pinfunction "SCLK_26") (pintype "bidirectional"))
    )
    (net (code "398") (name "SYNTH_SYNC") (class "Default")
      (node (ref "U201") (pin "AB16") (pinfunction "IO_L2P/T0_AB16") (pintype "bidirectional"))
      (node (ref "U601") (pin "30") (pinfunction "SYNC_30") (pintype "bidirectional"))
    )
    (net (code "399") (name "SYS_I2C_SCL") (class "Default")
      (node (ref "R202") (pin "1") (pinfunction "1_1") (pintype "passive"))
      (node (ref "U1001") (pin "3") (pinfunction "SCLIN_3") (pintype "bidirectional"))
      (node (ref "U201") (pin "Y22") (pinfunction "IO_L9N/T1_DQS/D13_Y22") (pintype "bidirectional"))
      (node (ref "U902") (pin "4") (pinfunction "SCL_4") (pintype "bidirectional"))
    )
    (net (code "400") (name "SYS_I2C_SDA") (class "Default")
      (node (ref "R201") (pin "1") (pinfunction "1_1") (pintype "passive"))
      (node (ref "U1001") (pin "6") (pinfunction "SDAIN_6") (pintype "bidirectional"))
      (node (ref "U201") (pin "AB22") (pinfunction "IO_L10N/T1/D15_AB22") (pintype "bidirectional"))
      (node (ref "U902") (pin "5") (pinfunction "SDA_5") (pintype "bidirectional"))
    )
    (net (code "401") (name "TRX_CLK_OUT") (class "Default")
      (node (ref "U201") (pin "J20") (pinfunction "IO_L11P/T1/SRCC_J20") (pintype "bidirectional"))
      (node (ref "U401") (pin "J6") (pinfunction "CLK_OUT_J6") (pintype "bidirectional"))
    )
    (net (code "402") (name "TRX_CTRL_IN0") (class "Default")
      (node (ref "U201") (pin "M15") (pinfunction "IO_L24P/T3/RS1_M15") (pintype "bidirectional"))
      (node (ref "U401") (pin "C5") (pinfunction "CTRL_IN0_C5") (pintype "bidirectional"))
    )
    (net (code "403") (name "TRX_CTRL_IN1") (class "Default")
      (node (ref "U201") (pin "N18") (pinfunction "IO_L17P/T2/A26_N18") (pintype "bidirectional"))
      (node (ref "U401") (pin "C6") (pinfunction "CTRL_IN1_C6") (pintype "bidirectional"))
    )
    (net (code "404") (name "TRX_CTRL_IN2") (class "Default")
      (node (ref "U201") (pin "N20") (pinfunction "IO_L18P/T2/A24_N20") (pintype "bidirectional"))
      (node (ref "U401") (pin "D6") (pinfunction "CTRL_IN2_D6") (pintype "bidirectional"))
    )
    (net (code "405") (name "TRX_CTRL_IN3") (class "Default")
      (node (ref "U201") (pin "N19") (pinfunction "IO_L17N/T2/A25_N19") (pintype "bidirectional"))
      (node (ref "U401") (pin "D5") (pinfunction "CTRL_IN3_D5") (pintype "bidirectional"))
    )
    (net (code "406") (name "TRX_CTRL_OUT0") (class "Default")
      (node (ref "U201") (pin "N22") (pinfunction "IO_L15P/T2_DQS_N22") (pintype "bidirectional"))
      (node (ref "U401") (pin "D4") (pinfunction "CTRL_OUT0_D4") (pintype "bidirectional"))
    )
    (net (code "407") (name "TRX_CTRL_OUT1") (class "Default")
      (node (ref "U201") (pin "D22") (pinfunction "IO_L22N/T3_D22") (pintype "bidirectional"))
      (node (ref "U401") (pin "E4") (pinfunction "CTRL_OUT1_E4") (pintype "bidirectional"))
    )
    (net (code "408") (name "TRX_CTRL_OUT2") (class "Default")
      (node (ref "U201") (pin "D21") (pinfunction "IO_L23N/T3_D21") (pintype "bidirectional"))
      (node (ref "U401") (pin "E5") (pinfunction "CTRL_OUT2_E5") (pintype "bidirectional"))
    )
    (net (code "409") (name "TRX_CTRL_OUT3") (class "Default")
      (node (ref "U201") (pin "D17") (pinfunction "IO_L12P/T1/MRCC_D17") (pintype "bidirectional"))
      (node (ref "U401") (pin "E6") (pinfunction "CTRL_OUT3_E6") (pintype "bidirectional"))
    )
    (net (code "410") (name "TRX_CTRL_OUT4") (class "Default")
      (node (ref "U201") (pin "G22") (pinfunction "IO_L24N/T3_G22") (pintype "bidirectional"))
      (node (ref "U401") (pin "F6") (pinfunction "CTRL_OUT4_F6") (pintype "bidirectional"))
    )
    (net (code "411") (name "TRX_CTRL_OUT5") (class "Default")
      (node (ref "U201") (pin "E21") (pinfunction "IO_L23P/T3_E21") (pintype "bidirectional"))
      (node (ref "U401") (pin "F5") (pinfunction "CTRL_OUT5_F5") (pintype "bidirectional"))
    )
    (net (code "412") (name "TRX_CTRL_OUT6") (class "Default")
      (node (ref "U201") (pin "D19") (pinfunction "IO_L14N/T2/SRCC_D19") (pintype "bidirectional"))
      (node (ref "U401") (pin "F4") (pinfunction "CTRL_OUT6_F4") (pintype "bidirectional"))
    )
    (net (code "413") (name "TRX_CTRL_OUT7") (class "Default")
      (node (ref "U201") (pin "E19") (pinfunction "IO_L14P/T2/SRCC_E19") (pintype "bidirectional"))
      (node (ref "U401") (pin "G4") (pinfunction "CTRL_OUT7_G4") (pintype "bidirectional"))
    )
    (net (code "414") (name "TRX_DATA_CLK") (class "Default")
      (node (ref "U201") (pin "K18") (pinfunction "IO_L13P/T2/MRCC_K18") (pintype "bidirectional"))
      (node (ref "U401") (pin "G11") (pinfunction "DATA_CLK_P_G11") (pintype "bidirectional"))
    )
    (net (code "415") (name "TRX_ENABLE") (class "Default")
      (node (ref "U201") (pin "F16") (pinfunction "IO_L2P/T0_F16") (pintype "bidirectional"))
      (node (ref "U401") (pin "G6") (pinfunction "ENABLE_G6") (pintype "bidirectional"))
    )
    (net (code "416") (name "TRX_EN_AGC") (class "Default")
      (node (ref "U201") (pin "F15") (pinfunction "IO_0_F15") (pintype "bidirectional"))
      (node (ref "U401") (pin "G5") (pinfunction "EN_AGC_G5") (pintype "bidirectional"))
    )
    (net (code "417") (name "TRX_FB_CLK") (class "Default")
      (node (ref "U201") (pin "J19") (pinfunction "IO_L12P/T1/MRCC_J19") (pintype "bidirectional"))
      (node (ref "U401") (pin "F10") (pinfunction "FB_CLK_P_F10") (pintype "bidirectional"))
    )
    (net (code "418") (name "TRX_P0_D0") (class "Default")
      (node (ref "U201") (pin "L16") (pinfunction "IO_L23P/T3/~{FOE}_L16") (pintype "bidirectional"))
      (node (ref "U401") (pin "E12") (pinfunction "P0_D0/TX_D0_N_E12") (pintype "bidirectional"))
    )
    (net (code "419") (name "TRX_P0_D1") (class "Default")
      (node (ref "U201") (pin "L13") (pinfunction "IO_L20N/T3/A19_L13") (pintype "bidirectional"))
      (node (ref "U401") (pin "D11") (pinfunction "P0_D1/TX_D0_P_D11") (pintype "bidirectional"))
    )
    (net (code "420") (name "TRX_P0_D2") (class "Default")
      (node (ref "U201") (pin "L15") (pinfunction "IO_L22N/T3/A16_L15") (pintype "bidirectional"))
      (node (ref "U401") (pin "E11") (pinfunction "P0_D2/TX_D1_N_E11") (pintype "bidirectional"))
    )
    (net (code "421") (name "TRX_P0_D3") (class "Default")
      (node (ref "U201") (pin "M13") (pinfunction "IO_L20P/T3/A20_M13") (pintype "bidirectional"))
      (node (ref "U401") (pin "D10") (pinfunction "P0_D3/TX_D1_P_D10") (pintype "bidirectional"))
    )
    (net (code "422") (name "TRX_P0_D4") (class "Default")
      (node (ref "U201") (pin "L14") (pinfunction "IO_L22P/T3/A17_L14") (pintype "bidirectional"))
      (node (ref "U401") (pin "E10") (pinfunction "P0_D4/TX_D2_N_E10") (pintype "bidirectional"))
    )
    (net (code "423") (name "TRX_P0_D5") (class "Default")
      (node (ref "U201") (pin "M18") (pinfunction "IO_L16P/T2/A28_M18") (pintype "bidirectional"))
      (node (ref "U401") (pin "D9") (pinfunction "P0_D5/TX_D2_P_D9") (pintype "bidirectional"))
    )
    (net (code "424") (name "TRX_P0_D6") (class "Default")
      (node (ref "U201") (pin "L18") (pinfunction "IO_L16N/T2/A27_L18") (pintype "bidirectional"))
      (node (ref "U401") (pin "E9") (pinfunction "P0_D6/TX_D3_N_E9") (pintype "bidirectional"))
    )
    (net (code "425") (name "TRX_P0_D7") (class "Default")
      (node (ref "U201") (pin "M17") (pinfunction "IO_25_M17") (pintype "bidirectional"))
      (node (ref "U401") (pin "D8") (pinfunction "P0_D7/TX_D3_P_D8") (pintype "bidirectional"))
    )
    (net (code "426") (name "TRX_P0_D8") (class "Default")
      (node (ref "U201") (pin "L19") (pinfunction "IO_L14P/T2/SRCC_L19") (pintype "bidirectional"))
      (node (ref "U401") (pin "E8") (pinfunction "P0_D8/TX_D4_N_E8") (pintype "bidirectional"))
    )
    (net (code "427") (name "TRX_P0_D9") (class "Default")
      (node (ref "U201") (pin "M16") (pinfunction "IO_L24N/T3/RS0_M16") (pintype "bidirectional"))
      (node (ref "U401") (pin "D7") (pinfunction "P0_D9/TX_D4_P_D7") (pintype "bidirectional"))
    )
    (net (code "428") (name "TRX_P0_D10") (class "Default")
      (node (ref "U201") (pin "L21") (pinfunction "IO_L10N/T1/AD11N_L21") (pintype "bidirectional"))
      (node (ref "U401") (pin "F8") (pinfunction "P0_D10/TX_D5_N_F8") (pintype "bidirectional"))
    )
    (net (code "429") (name "TRX_P0_D11") (class "Default")
      (node (ref "U201") (pin "L20") (pinfunction "IO_L14N/T2/SRCC_L20") (pintype "bidirectional"))
      (node (ref "U401") (pin "E7") (pinfunction "P0_D11/TX_D5_P_E7") (pintype "bidirectional"))
    )
    (net (code "430") (name "TRX_P1_D0") (class "Default")
      (node (ref "U201") (pin "H14") (pinfunction "IO_L3N/T0_DQS/AD1N_H14") (pintype "bidirectional"))
      (node (ref "U401") (pin "K11") (pinfunction "P1_D0/RX_D0_N_K11") (pintype "bidirectional"))
    )
    (net (code "431") (name "TRX_P1_D1") (class "Default")
      (node (ref "U201") (pin "K14") (pinfunction "IO_L19N/T3/VREF/A21_K14") (pintype "bidirectional"))
      (node (ref "U401") (pin "J12") (pinfunction "P1_D1/RX_D0_P_J12") (pintype "bidirectional"))
    )
    (net (code "432") (name "TRX_P1_D2") (class "Default")
      (node (ref "U201") (pin "H15") (pinfunction "IO_L5N/T0/AD9N_H15") (pintype "bidirectional"))
      (node (ref "U401") (pin "K10") (pinfunction "P1_D2/RX_D1_N_K10") (pintype "bidirectional"))
    )
    (net (code "433") (name "TRX_P1_D3") (class "Default")
      (node (ref "U201") (pin "K13") (pinfunction "IO_L19P/T3/A22_K13") (pintype "bidirectional"))
      (node (ref "U401") (pin "J11") (pinfunction "P1_D3/RX_D1_P_J11") (pintype "bidirectional"))
    )
    (net (code "434") (name "TRX_P1_D4") (class "Default")
      (node (ref "U201") (pin "H17") (pinfunction "IO_L6P/T0_H17") (pintype "bidirectional"))
      (node (ref "U401") (pin "K9") (pinfunction "P1_D4/RX_D2_N_K9") (pintype "bidirectional"))
    )
    (net (code "435") (name "TRX_P1_D5") (class "Default")
      (node (ref "U201") (pin "H13") (pinfunction "IO_L1P/T0/AD0P_H13") (pintype "bidirectional"))
      (node (ref "U401") (pin "J10") (pinfunction "P1_D5/RX_D2_P_J10") (pintype "bidirectional"))
    )
    (net (code "436") (name "TRX_P1_D6") (class "Default")
      (node (ref "U201") (pin "H18") (pinfunction "IO_L6N/T0/VREF_H18") (pintype "bidirectional"))
      (node (ref "U401") (pin "K8") (pinfunction "P1_D6/RX_D3_N_K8") (pintype "bidirectional"))
    )
    (net (code "437") (name "TRX_P1_D7") (class "Default")
      (node (ref "U201") (pin "K16") (pinfunction "IO_L23N/T3/~{FWE}_K16") (pintype "bidirectional"))
      (node (ref "U401") (pin "J9") (pinfunction "P1_D7/RX_D3_P_J9") (pintype "bidirectional"))
    )
    (net (code "438") (name "TRX_P1_D8") (class "Default")
      (node (ref "U201") (pin "G21") (pinfunction "IO_L24P/T3_G21") (pintype "bidirectional"))
      (node (ref "U401") (pin "K7") (pinfunction "P1_D8/RX_D4_N_K7") (pintype "bidirectional"))
    )
    (net (code "439") (name "TRX_P1_D9") (class "Default")
      (node (ref "U201") (pin "K17") (pinfunction "IO_L21P/T3_DQS_K17") (pintype "bidirectional"))
      (node (ref "U401") (pin "J8") (pinfunction "P1_D9/RX_D4_P_J8") (pintype "bidirectional"))
    )
    (net (code "440") (name "TRX_P1_D10") (class "Default")
      (node (ref "U201") (pin "J22") (pinfunction "IO_L7P/T1/AD2P_J22") (pintype "bidirectional"))
      (node (ref "U401") (pin "J7") (pinfunction "P1_D10/RX_D5_N_J7") (pintype "bidirectional"))
    )
    (net (code "441") (name "TRX_P1_D11") (class "Default")
      (node (ref "U201") (pin "J21") (pinfunction "IO_L11N/T1/SRCC_J21") (pintype "bidirectional"))
      (node (ref "U401") (pin "H8") (pinfunction "P1_D11/RX_D5_P_H8") (pintype "bidirectional"))
    )
    (net (code "442") (name "TRX_REF_CLK") (class "Default")
      (node (ref "R401") (pin "2") (pinfunction "2_2") (pintype "passive"))
      (node (ref "R908") (pin "1") (pinfunction "1_1") (pintype "passive"))
    )
    (net (code "443") (name "TRX_RX1A_N") (class "Default")
      (node (ref "C509") (pin "2") (pinfunction "C2_2") (pintype "passive"))
      (node (ref "U401") (pin "M2") (pinfunction "RX1A_N_M2") (pintype "bidirectional"))
    )
    (net (code "444") (name "TRX_RX1A_P") (class "Default")
      (node (ref "C510") (pin "2") (pinfunction "C2_2") (pintype "passive"))
      (node (ref "U401") (pin "M1") (pinfunction "RX1A_P_M1") (pintype "bidirectional"))
    )
    (net (code "445") (name "TRX_RX1C_N") (class "Default")
      (node (ref "C513") (pin "2") (pinfunction "C2_2") (pintype "passive"))
      (node (ref "U401") (pin "L1") (pinfunction "RX1C_N_L1") (pintype "bidirectional"))
    )
    (net (code "446") (name "TRX_RX1C_P") (class "Default")
      (node (ref "C514") (pin "2") (pinfunction "C2_2") (pintype "passive"))
      (node (ref "U401") (pin "K1") (pinfunction "RX1C_P_K1") (pintype "bidirectional"))
    )
    (net (code "447") (name "TRX_RX2A_N") (class "Default")
      (node (ref "C511") (pin "2") (pinfunction "C2_2") (pintype "passive"))
      (node (ref "U401") (pin "A1") (pinfunction "RX2A_N_A1") (pintype "bidirectional"))
    )
    (net (code "448") (name "TRX_RX2A_P") (class "Default")
      (node (ref "C512") (pin "2") (pinfunction "C2_2") (pintype "passive"))
      (node (ref "U401") (pin "A2") (pinfunction "RX2A_P_A2") (pintype "bidirectional"))
    )
    (net (code "449") (name "TRX_RX2C_N") (class "Default")
      (node (ref "C515") (pin "2") (pinfunction "C2_2") (pintype "passive"))
      (node (ref "U401") (pin "D1") (pinfunction "RX2C_N_D1") (pintype "bidirectional"))
    )
    (net (code "450") (name "TRX_RX2C_P") (class "Default")
      (node (ref "C516") (pin "2") (pinfunction "C2_2") (pintype "passive"))
      (node (ref "U401") (pin "C1") (pinfunction "RX2C_P_C1") (pintype "bidirectional"))
    )
    (net (code "451") (name "TRX_RX_FRAME") (class "Default")
      (node (ref "U201") (pin "K22") (pinfunction "IO_L9N/T1_DQS/AD3N_K22") (pintype "bidirectional"))
      (node (ref "U401") (pin "G8") (pinfunction "RX_FRAME_P_G8") (pintype "bidirectional"))
    )
    (net (code "452") (name "TRX_SPI_MISO") (class "Default")
      (node (ref "U201") (pin "G18") (pinfunction "IO_L4N/T0_G18") (pintype "bidirectional"))
      (node (ref "U401") (pin "L6") (pinfunction "SPI_DO_L6") (pintype "bidirectional"))
    )
    (net (code "453") (name "TRX_SPI_MOSI") (class "Default")
      (node (ref "U201") (pin "G17") (pinfunction "IO_L4P/T0_G17") (pintype "bidirectional"))
      (node (ref "U401") (pin "J4") (pinfunction "SPI_DI_J4") (pintype "bidirectional"))
    )
    (net (code "454") (name "TRX_SPI_SCK") (class "Default")
      (node (ref "U201") (pin "G15") (pinfunction "IO_L2P/T0/AD8P_G15") (pintype "bidirectional"))
      (node (ref "U401") (pin "J5") (pinfunction "SPI_CLK_J5") (pintype "bidirectional"))
    )
    (net (code "455") (name "TRX_SYNC_IN") (class "Default")
      (node (ref "U201") (pin "F18") (pinfunction "IO_L15P/T2_DQS_F18") (pintype "bidirectional"))
      (node (ref "U401") (pin "H5") (pinfunction "SYNC_IN_H5") (pintype "bidirectional"))
    )
    (net (code "456") (name "TRX_TX1A_N") (class "Default")
      (node (ref "C544") (pin "1") (pinfunction "C1_1") (pintype "passive"))
      (node (ref "L509") (pin "2") (pinfunction "2_2") (pintype "passive"))
      (node (ref "U401") (pin "M8") (pinfunction "TX1A_N_M8") (pintype "bidirectional"))
    )
    (net (code "457") (name "TRX_TX1A_P") (class "Default")
      (node (ref "C545") (pin "1") (pinfunction "C1_1") (pintype "passive"))
      (node (ref "L507") (pin "2") (pinfunction "2_2") (pintype "passive"))
      (node (ref "U401") (pin "M7") (pinfunction "TX1A_P_M7") (pintype "bidirectional"))
    )
    (net (code "458") (name "TRX_TX1B_N") (class "Default")
      (node (ref "C530") (pin "1") (pinfunction "C1_1") (pintype "passive"))
      (node (ref "L505") (pin "2") (pinfunction "2_2") (pintype "passive"))
      (node (ref "U401") (pin "M10") (pinfunction "TX1B_N_M10") (pintype "bidirectional"))
    )
    (net (code "459") (name "TRX_TX1B_P") (class "Default")
      (node (ref "C531") (pin "1") (pinfunction "C1_1") (pintype "passive"))
      (node (ref "L503") (pin "2") (pinfunction "2_2") (pintype "passive"))
      (node (ref "U401") (pin "M9") (pinfunction "TX1B_P_M9") (pintype "bidirectional"))
    )
    (net (code "460") (name "TRX_TX2A_N") (class "Default")
      (node (ref "C546") (pin "1") (pinfunction "C1_1") (pintype "passive"))
      (node (ref "L510") (pin "2") (pinfunction "2_2") (pintype "passive"))
      (node (ref "U401") (pin "A7") (pinfunction "TX2A_N_A7") (pintype "bidirectional"))
    )
    (net (code "461") (name "TRX_TX2A_P") (class "Default")
      (node (ref "C547") (pin "1") (pinfunction "C1_1") (pintype "passive"))
      (node (ref "L508") (pin "2") (pinfunction "2_2") (pintype "passive"))
      (node (ref "U401") (pin "A8") (pinfunction "TX2A_P_A8") (pintype "bidirectional"))
    )
    (net (code "462") (name "TRX_TX2B_N") (class "Default")
      (node (ref "C532") (pin "1") (pinfunction "C1_1") (pintype "passive"))
      (node (ref "L506") (pin "2") (pinfunction "2_2") (pintype "passive"))
      (node (ref "U401") (pin "A9") (pinfunction "TX2B_N_A9") (pintype "bidirectional"))
    )
    (net (code "463") (name "TRX_TX2B_P") (class "Default")
      (node (ref "C533") (pin "1") (pinfunction "C1_1") (pintype "passive"))
      (node (ref "L504") (pin "2") (pinfunction "2_2") (pintype "passive"))
      (node (ref "U401") (pin "A10") (pinfunction "TX2B_P_A10") (pintype "bidirectional"))
    )
    (net (code "464") (name "TRX_TXMON1") (class "Default")
      (node (ref "C529") (pin "2") (pinfunction "C2_2") (pintype "passive"))
      (node (ref "U401") (pin "M5") (pinfunction "TX_MON1_M5") (pintype "bidirectional"))
    )
    (net (code "465") (name "TRX_TXMON2") (class "Default")
      (node (ref "C550") (pin "2") (pinfunction "C2_2") (pintype "passive"))
      (node (ref "U401") (pin "A5") (pinfunction "TX_MON2_A5") (pintype "bidirectional"))
    )
    (net (code "466") (name "TRX_TX_FRAME") (class "Default")
      (node (ref "U201") (pin "K21") (pinfunction "IO_L9P/T1_DQS/AD3P_K21") (pintype "bidirectional"))
      (node (ref "U401") (pin "G9") (pinfunction "TX_FRAME_P_G9") (pintype "bidirectional"))
    )
    (net (code "467") (name "TRX_TX{slash}~{RX}") (class "Default")
      (node (ref "U201") (pin "F14") (pinfunction "IO_L1N/T0_F14") (pintype "bidirectional"))
      (node (ref "U401") (pin "H4") (pinfunction "TX/~{RX}_H4") (pintype "bidirectional"))
    )
    (net (code "468") (name "USB_CC1") (class "Default")
      (node (ref "C1002") (pin "1") (pinfunction "C1_1") (pintype "passive"))
      (node (ref "U1002") (pin "4") (pinfunction "CC1_4") (pintype "bidirectional"))
      (node (ref "USB1001") (pin "A5") (pinfunction "CC1_A5") (pintype "bidirectional"))
    )
    (net (code "469") (name "USB_CC2") (class "Default")
      (node (ref "C1004") (pin "1") (pinfunction "C1_1") (pintype "passive"))
      (node (ref "U1002") (pin "2") (pinfunction "CC2_2") (pintype "bidirectional"))
      (node (ref "USB1001") (pin "B5") (pinfunction "CC2_B5") (pintype "bidirectional"))
    )
    (net (code "470") (name "USB_D_N") (class "Default")
      (node (ref "L1001") (pin "2") (pinfunction "2_2") (pintype "passive"))
      (node (ref "U102") (pin "103") (pinfunction "USB_DN_103") (pintype "bidirectional"))
    )
    (net (code "471") (name "USB_D_P") (class "Default")
      (node (ref "L1001") (pin "3") (pinfunction "3_3") (pintype "passive"))
      (node (ref "U102") (pin "105") (pinfunction "USB_DP_105") (pintype "bidirectional"))
    )
    (net (code "472") (name "USB_VBUS_DET") (class "Default")
      (node (ref "C1006") (pin "1") (pinfunction "C1_1") (pintype "passive"))
      (node (ref "R1005") (pin "1") (pinfunction "1_1") (pintype "passive"))
      (node (ref "R1006") (pin "2") (pinfunction "2_2") (pintype "passive"))
      (node (ref "U1002") (pin "9") (pinfunction "VBUS_DET_IN_9") (pintype "bidirectional"))
    )
    (net (code "473") (name "VBUS") (class "Default")
      (node (ref "C1103") (pin "1") (pinfunction "C1_1") (pintype "passive"))
      (node (ref "D1002") (pin "C") (pinfunction "C_C") (pintype "passive"))
      (node (ref "D1003") (pin "C") (pinfunction "C_C") (pintype "passive"))
      (node (ref "D1101") (pin "A") (pinfunction "A_A") (pintype "passive"))
      (node (ref "F1001") (pin "1") (pinfunction "1_1") (pintype "passive"))
      (node (ref "Q1102") (pin "5") (pinfunction "D_5") (pintype "passive"))
      (node (ref "Q1102") (pin "6") (pinfunction "D_6") (pintype "passive"))
      (node (ref "R1005") (pin "2") (pinfunction "2_2") (pintype "passive"))
      (node (ref "R1110") (pin "2") (pinfunction "2_2") (pintype "passive"))
    )
    (net (code "474") (name "VBUS_SNK_EN") (class "Default")
      (node (ref "Q1101") (pin "1") (pinfunction "G_1") (pintype "passive"))
      (node (ref "R1105") (pin "2") (pinfunction "2_2") (pintype "passive"))
      (node (ref "U1002") (pin "39") (pinfunction "PA27/GPIO9_39") (pintype "bidirectional"))
    )
    (net (code "475") (name "VBUS_SRC_EN") (class "Default")
      (node (ref "R1009") (pin "2") (pinfunction "2_2") (pintype "passive"))
      (node (ref "U1002") (pin "26") (pinfunction "GPIO2_26") (pintype "bidirectional"))
      (node (ref "U1003") (pin "3") (pinfunction "EN_3") (pintype "bidirectional"))
    )
    (net (code "476") (name "VBUS_VSENSE") (class "Default")
      (node (ref "C1107") (pin "1") (pinfunction "C1_1") (pintype "passive"))
      (node (ref "R1110") (pin "1") (pinfunction "1_1") (pintype "passive"))
      (node (ref "R1111") (pin "2") (pinfunction "2_2") (pintype "passive"))
      (node (ref "U1002") (pin "12") (pinfunction "PA02_12") (pintype "bidirectional"))
    )
    (net (code "477") (name "VEXT") (class "Default")
      (node (ref "C1110") (pin "1") (pinfunction "C1_1") (pintype "passive"))
      (node (ref "D1103") (pin "A") (pinfunction "A_A") (pintype "passive"))
      (node (ref "D1105") (pin "C") (pinfunction "C_C") (pintype "passive"))
      (node (ref "F1101") (pin "1") (pinfunction "1_1") (pintype "passive"))
      (node (ref "Q1105") (pin "7") (pinfunction "D_7") (pintype "passive"))
      (node (ref "Q1105") (pin "8") (pinfunction "D_8") (pintype "passive"))
      (node (ref "R1103") (pin "2") (pinfunction "2_2") (pintype "passive"))
    )
    (net (code "478") (name "VEXT_EN") (class "Default")
      (node (ref "Q1106") (pin "1") (pinfunction "G_1") (pintype "passive"))
      (node (ref "R1115") (pin "2") (pinfunction "2_2") (pintype "passive"))
      (node (ref "U1002") (pin "19") (pinfunction "PA06_19") (pintype "bidirectional"))
    )
    (net (code "479") (name "VEXT_VSENSE") (class "Default")
      (node (ref "C1102") (pin "1") (pinfunction "C1_1") (pintype "passive"))
      (node (ref "R1103") (pin "1") (pinfunction "1_1") (pintype "passive"))
      (node (ref "R1104") (pin "2") (pinfunction "2_2") (pintype "passive"))
      (node (ref "U1002") (pin "18") (pinfunction "PA05_18") (pintype "bidirectional"))
    )
    (net (code "480") (name "VIN") (class "Default")
      (node (ref "C1111") (pin "1") (pinfunction "C1_1") (pintype "passive"))
      (node (ref "C1112") (pin "1") (pinfunction "C1_1") (pintype "passive"))
      (node (ref "C1116") (pin "1") (pinfunction "C1_1") (pintype "passive"))
      (node (ref "C1117") (pin "1") (pinfunction "C1_1") (pintype "passive"))
      (node (ref "C1118") (pin "1") (pinfunction "C1_1") (pintype "passive"))
      (node (ref "C1119") (pin "1") (pinfunction "C1_1") (pintype "passive"))
      (node (ref "Q1102") (pin "7") (pinfunction "D_7") (pintype "passive"))
      (node (ref "Q1102") (pin "8") (pinfunction "D_8") (pintype "passive"))
      (node (ref "Q1104") (pin "7") (pinfunction "D_7") (pintype "passive"))
      (node (ref "Q1104") (pin "8") (pinfunction "D_8") (pintype "passive"))
      (node (ref "Q1105") (pin "5") (pinfunction "D_5") (pintype "passive"))
      (node (ref "Q1105") (pin "6") (pinfunction "D_6") (pintype "passive"))
      (node (ref "R1101") (pin "2") (pinfunction "2_2") (pintype "passive"))
      (node (ref "U1102") (pin "15") (pinfunction "PVIN_15") (pintype "bidirectional"))
      (node (ref "U1102") (pin "18") (pinfunction "PVIN_18") (pintype "bidirectional"))
      (node (ref "U1102") (pin "35") (pinfunction "PVIN_35") (pintype "bidirectional"))
      (node (ref "U1102") (pin "38") (pinfunction "PVIN_38") (pintype "bidirectional"))
    )
    (net (code "481") (name "VIN_REG_SHARE_CLK") (class "Default")
      (node (ref "R1124") (pin "1") (pinfunction "1_1") (pintype "passive"))
      (node (ref "U1102") (pin "25") (pinfunction "SHARE_CLK_25") (pintype "bidirectional"))
    )
    (net (code "482") (name "VIN_VSENSE") (class "Default")
      (node (ref "C1101") (pin "1") (pinfunction "C1_1") (pintype "passive"))
      (node (ref "R1101") (pin "1") (pinfunction "1_1") (pintype "passive"))
      (node (ref "R1102") (pin "2") (pinfunction "2_2") (pintype "passive"))
      (node (ref "U1002") (pin "13") (pinfunction "PA03_13") (pintype "bidirectional"))
    )
    (net (code "483") (name "unconnected-(J701-DT-Pad4)") (class "Default")
      (node (ref "J701") (pin "4") (pinfunction "DT_4") (pintype "bidirectional"))
    )
    (net (code "484") (name "unconnected-(J702-DT-Pad4)") (class "Default")
      (node (ref "J702") (pin "4") (pinfunction "DT_4") (pintype "bidirectional"))
    )
    (net (code "485") (name "unconnected-(J703-DT-Pad4)") (class "Default")
      (node (ref "J703") (pin "4") (pinfunction "DT_4") (pintype "bidirectional"))
    )
    (net (code "486") (name "unconnected-(SD101-SWA-Pad9)") (class "Default")
      (node (ref "SD101") (pin "9") (pinfunction "SWA_9") (pintype "passive"))
    )
    (net (code "487") (name "unconnected-(SD101-SWB-Pad10)") (class "Default")
      (node (ref "SD101") (pin "10") (pinfunction "SWB_10") (pintype "passive"))
    )
    (net (code "488") (name "unconnected-(TC201F-S-Pad5)") (class "Default")
      (node (ref "TC201") (pin "5") (pinfunction "S_5") (pintype "passive"))
    )
    (net (code "489") (name "unconnected-(TC1001F-S-Pad5)") (class "Default")
      (node (ref "TC1001") (pin "5") (pinfunction "S_5") (pintype "passive"))
    )
    (net (code "490") (name "unconnected-(U101-~{FAULT}-Pad4)") (class "Default")
      (node (ref "U101") (pin "4") (pinfunction "~{FAULT}_4") (pintype "bidirectional"))
    )
    (net (code "491") (name "unconnected-(U102E-~{ETH_LED1}-Pad19)") (class "Default")
      (node (ref "U102") (pin "19") (pinfunction "~{ETH_LED1}_19") (pintype "bidirectional"))
    )
    (net (code "492") (name "unconnected-(U102F-GPIO2-Pad58)") (class "Default")
      (node (ref "U102") (pin "58") (pinfunction "GPIO2_58") (pintype "bidirectional"))
    )
    (net (code "493") (name "unconnected-(U102F-GPIO4-Pad54)") (class "Default")
      (node (ref "U102") (pin "54") (pinfunction "GPIO4_54") (pintype "bidirectional"))
    )
    (net (code "494") (name "unconnected-(U102F-GPIO5-Pad34)") (class "Default")
      (node (ref "U102") (pin "34") (pinfunction "GPIO5_34") (pintype "bidirectional"))
    )
    (net (code "495") (name "unconnected-(U102F-GPIO6-Pad30)") (class "Default")
      (node (ref "U102") (pin "30") (pinfunction "GPIO6_30") (pintype "bidirectional"))
    )
    (net (code "496") (name "unconnected-(U102F-GPIO7-Pad37)") (class "Default")
      (node (ref "U102") (pin "37") (pinfunction "GPIO7_37") (pintype "bidirectional"))
    )
    (net (code "497") (name "unconnected-(U102F-GPIO8-Pad39)") (class "Default")
      (node (ref "U102") (pin "39") (pinfunction "GPIO8_39") (pintype "bidirectional"))
    )
    (net (code "498") (name "unconnected-(U102F-GPIO9-Pad40)") (class "Default")
      (node (ref "U102") (pin "40") (pinfunction "GPIO9_40") (pintype "bidirectional"))
    )
    (net (code "499") (name "unconnected-(U102F-GPIO10-Pad44)") (class "Default")
      (node (ref "U102") (pin "44") (pinfunction "GPIO10_44") (pintype "bidirectional"))
    )
    (net (code "500") (name "unconnected-(U102F-GPIO11-Pad38)") (class "Default")
      (node (ref "U102") (pin "38") (pinfunction "GPIO11_38") (pintype "bidirectional"))
    )
    (net (code "501") (name "unconnected-(U102F-GPIO12-Pad31)") (class "Default")
      (node (ref "U102") (pin "31") (pinfunction "GPIO12_31") (pintype "bidirectional"))
    )
    (net (code "502") (name "unconnected-(U102F-GPIO13-Pad28)") (class "Default")
      (node (ref "U102") (pin "28") (pinfunction "GPIO13_28") (pintype "bidirectional"))
    )
    (net (code "503") (name "unconnected-(U102F-GPIO16-Pad29)") (class "Default")
      (node (ref "U102") (pin "29") (pinfunction "GPIO16_29") (pintype "bidirectional"))
    )
    (net (code "504") (name "unconnected-(U102F-GPIO17-Pad50)") (class "Default")
      (node (ref "U102") (pin "50") (pinfunction "GPIO17_50") (pintype "bidirectional"))
    )
    (net (code "505") (name "unconnected-(U102F-GPIO18-Pad49)") (class "Default")
      (node (ref "U102") (pin "49") (pinfunction "GPIO18_49") (pintype "bidirectional"))
    )
    (net (code "506") (name "unconnected-(U102F-GPIO19-Pad26)") (class "Default")
      (node (ref "U102") (pin "26") (pinfunction "GPIO19_26") (pintype "bidirectional"))
    )
    (net (code "507") (name "unconnected-(U102F-GPIO20-Pad27)") (class "Default")
      (node (ref "U102") (pin "27") (pinfunction "GPIO20_27") (pintype "bidirectional"))
    )
    (net (code "508") (name "unconnected-(U102F-GPIO21-Pad25)") (class "Default")
      (node (ref "U102") (pin "25") (pinfunction "GPIO21_25") (pintype "bidirectional"))
    )
    (net (code "509") (name "unconnected-(U102F-GPIO22-Pad46)") (class "Default")
      (node (ref "U102") (pin "46") (pinfunction "GPIO22_46") (pintype "bidirectional"))
    )
    (net (code "510") (name "unconnected-(U102F-GPIO23-Pad47)") (class "Default")
      (node (ref "U102") (pin "47") (pinfunction "GPIO23_47") (pintype "bidirectional"))
    )
    (net (code "511") (name "unconnected-(U102F-GPIO24-Pad45)") (class "Default")
      (node (ref "U102") (pin "45") (pinfunction "GPIO24_45") (pintype "bidirectional"))
    )
    (net (code "512") (name "unconnected-(U102F-GPIO25-Pad41)") (class "Default")
      (node (ref "U102") (pin "41") (pinfunction "GPIO25_41") (pintype "bidirectional"))
    )
    (net (code "513") (name "unconnected-(U102F-GPIO26-Pad24)") (class "Default")
      (node (ref "U102") (pin "24") (pinfunction "GPIO26_24") (pintype "bidirectional"))
    )
    (net (code "514") (name "unconnected-(U102F-GPIO27-Pad48)") (class "Default")
      (node (ref "U102") (pin "48") (pinfunction "GPIO27_48") (pintype "bidirectional"))
    )
    (net (code "515") (name "unconnected-(U102J-AIP0-Pad96)") (class "Default")
      (node (ref "U102") (pin "96") (pinfunction "AIP0_96") (pintype "bidirectional"))
    )
    (net (code "516") (name "unconnected-(U102J-AIP1-Pad94)") (class "Default")
      (node (ref "U102") (pin "94") (pinfunction "AIP1_94") (pintype "bidirectional"))
    )
    (net (code "517") (name "unconnected-(U102J-~{EXTRST}-Pad100)") (class "Default")
      (node (ref "U102") (pin "100") (pinfunction "~{EXTRST}_100") (pintype "bidirectional"))
    )
    (net (code "518") (name "unconnected-(U102K-SD_DAT4-Pad68)") (class "Default")
      (node (ref "U102") (pin "68") (pinfunction "SD_DAT4_68") (pintype "bidirectional"))
    )
    (net (code "519") (name "unconnected-(U102K-SD_DAT5-Pad64)") (class "Default")
      (node (ref "U102") (pin "64") (pinfunction "SD_DAT5_64") (pintype "bidirectional"))
    )
    (net (code "520") (name "unconnected-(U102K-SD_DAT6-Pad72)") (class "Default")
      (node (ref "U102") (pin "72") (pinfunction "SD_DAT6_72") (pintype "bidirectional"))
    )
    (net (code "521") (name "unconnected-(U102K-SD_DAT7-Pad70)") (class "Default")
      (node (ref "U102") (pin "70") (pinfunction "SD_DAT7_70") (pintype "bidirectional"))
    )
    (net (code "522") (name "unconnected-(U102K-SD_VDD_OVR-Pad73)") (class "Default")
      (node (ref "U102") (pin "73") (pinfunction "SD_VDD_OVR_73") (pintype "bidirectional"))
    )
    (net (code "523") (name "unconnected-(U201C-IO_L1P{slash}T0-PadY16)") (class "Default")
      (node (ref "U201") (pin "Y16") (pinfunction "IO_L1P/T0_Y16") (pintype "bidirectional"))
    )
    (net (code "524") (name "unconnected-(U201C-IO_L4N{slash}T0-PadAB15)") (class "Default")
      (node (ref "U201") (pin "AB15") (pinfunction "IO_L4N/T0_AB15") (pintype "bidirectional"))
    )
    (net (code "525") (name "unconnected-(U201C-IO_L5P{slash}T0-PadY13)") (class "Default")
      (node (ref "U201") (pin "Y13") (pinfunction "IO_L5P/T0_Y13") (pintype "bidirectional"))
    )
    (net (code "526") (name "unconnected-(U201C-IO_L6N{slash}T0{slash}VREF-PadY14)") (class "Default")
      (node (ref "U201") (pin "Y14") (pinfunction "IO_L6N/T0/VREF_Y14") (pintype "bidirectional"))
    )
    (net (code "527") (name "unconnected-(U201C-IO_L6P{slash}T0-PadW14)") (class "Default")
      (node (ref "U201") (pin "W14") (pinfunction "IO_L6P/T0_W14") (pintype "bidirectional"))
    )
    (net (code "528") (name "unconnected-(U201C-IO_L7N{slash}T1-PadAB12)") (class "Default")
      (node (ref "U201") (pin "AB12") (pinfunction "IO_L7N/T1_AB12") (pintype "bidirectional"))
    )
    (net (code "529") (name "unconnected-(U201C-IO_L10N{slash}T1-PadW10)") (class "Default")
      (node (ref "U201") (pin "W10") (pinfunction "IO_L10N/T1_W10") (pintype "bidirectional"))
    )
    (net (code "530") (name "unconnected-(U201C-IO_L10P{slash}T1-PadV10)") (class "Default")
      (node (ref "U201") (pin "V10") (pinfunction "IO_L10P/T1_V10") (pintype "bidirectional"))
    )
    (net (code "531") (name "unconnected-(U201C-IO_L11N{slash}T1{slash}SRCC-PadY12)") (class "Default")
      (node (ref "U201") (pin "Y12") (pinfunction "IO_L11N/T1/SRCC_Y12") (pintype "bidirectional"))
    )
    (net (code "532") (name "unconnected-(U201C-IO_L11P{slash}T1{slash}SRCC-PadY11)") (class "Default")
      (node (ref "U201") (pin "Y11") (pinfunction "IO_L11P/T1/SRCC_Y11") (pintype "bidirectional"))
    )
    (net (code "533") (name "unconnected-(U201C-IO_L12N{slash}T1{slash}MRCC-PadW12)") (class "Default")
      (node (ref "U201") (pin "W12") (pinfunction "IO_L12N/T1/MRCC_W12") (pintype "bidirectional"))
    )
    (net (code "534") (name "unconnected-(U201C-IO_L13N{slash}T2{slash}MRCC-PadV14)") (class "Default")
      (node (ref "U201") (pin "V14") (pinfunction "IO_L13N/T2/MRCC_V14") (pintype "bidirectional"))
    )
    (net (code "535") (name "unconnected-(U201C-IO_L14N{slash}T2{slash}SRCC-PadV15)") (class "Default")
      (node (ref "U201") (pin "V15") (pinfunction "IO_L14N/T2/SRCC_V15") (pintype "bidirectional"))
    )
    (net (code "536") (name "unconnected-(U201C-IO_L14P{slash}T2{slash}SRCC-PadU15)") (class "Default")
      (node (ref "U201") (pin "U15") (pinfunction "IO_L14P/T2/SRCC_U15") (pintype "bidirectional"))
    )
    (net (code "537") (name "unconnected-(U201C-IO_L15N{slash}T2_DQS-PadT15)") (class "Default")
      (node (ref "U201") (pin "T15") (pinfunction "IO_L15N/T2_DQS_T15") (pintype "bidirectional"))
    )
    (net (code "538") (name "unconnected-(U201C-IO_L15P{slash}T2_DQS-PadT14)") (class "Default")
      (node (ref "U201") (pin "T14") (pinfunction "IO_L15P/T2_DQS_T14") (pintype "bidirectional"))
    )
    (net (code "539") (name "unconnected-(U201C-IO_L17N{slash}T2-PadU16)") (class "Default")
      (node (ref "U201") (pin "U16") (pinfunction "IO_L17N/T2_U16") (pintype "bidirectional"))
    )
    (net (code "540") (name "unconnected-(U201C-IO_L17P{slash}T2-PadT16)") (class "Default")
      (node (ref "U201") (pin "T16") (pinfunction "IO_L17P/T2_T16") (pintype "bidirectional"))
    )
    (net (code "541") (name "unconnected-(U201D-IO_0-PadP20)") (class "Default")
      (node (ref "U201") (pin "P20") (pinfunction "IO_0_P20") (pintype "bidirectional"))
    )
    (net (code "542") (name "unconnected-(U201D-IO_25-PadN15)") (class "Default")
      (node (ref "U201") (pin "N15") (pinfunction "IO_25_N15") (pintype "bidirectional"))
    )
    (net (code "543") (name "unconnected-(U201D-IO_L4P{slash}T0{slash}D4-PadT21)") (class "Default")
      (node (ref "U201") (pin "T21") (pinfunction "IO_L4P/T0/D4_T21") (pintype "bidirectional"))
    )
    (net (code "544") (name "unconnected-(U201D-IO_L5N{slash}T0{slash}D7-PadR19)") (class "Default")
      (node (ref "U201") (pin "R19") (pinfunction "IO_L5N/T0/D7_R19") (pintype "bidirectional"))
    )
    (net (code "545") (name "unconnected-(U201D-IO_L5P{slash}T0{slash}D6-PadP19)") (class "Default")
      (node (ref "U201") (pin "P19") (pinfunction "IO_L5P/T0/D6_P19") (pintype "bidirectional"))
    )
    (net (code "546") (name "unconnected-(U201D-IO_L8N{slash}T1{slash}D12-PadAA21)") (class "Default")
      (node (ref "U201") (pin "AA21") (pinfunction "IO_L8N/T1/D12_AA21") (pintype "bidirectional"))
    )
    (net (code "547") (name "unconnected-(U201D-IO_L9P{slash}T1_DQS-PadY21)") (class "Default")
      (node (ref "U201") (pin "Y21") (pinfunction "IO_L9P/T1_DQS_Y21") (pintype "bidirectional"))
    )
    (net (code "548") (name "unconnected-(U201D-IO_L11P{slash}T1{slash}SRCC-PadU20)") (class "Default")
      (node (ref "U201") (pin "U20") (pinfunction "IO_L11P/T1/SRCC_U20") (pintype "bidirectional"))
    )
    (net (code "549") (name "unconnected-(U201D-IO_L14N{slash}T2{slash}SRCC-PadV19)") (class "Default")
      (node (ref "U201") (pin "V19") (pinfunction "IO_L14N/T2/SRCC_V19") (pintype "bidirectional"))
    )
    (net (code "550") (name "unconnected-(U201D-IO_L14P{slash}T2{slash}SRCC-PadV18)") (class "Default")
      (node (ref "U201") (pin "V18") (pinfunction "IO_L14P/T2/SRCC_V18") (pintype "bidirectional"))
    )
    (net (code "551") (name "unconnected-(U201D-IO_L18N{slash}T2{slash}A11{slash}D27-PadU18)") (class "Default")
      (node (ref "U201") (pin "U18") (pinfunction "IO_L18N/T2/A11/D27_U18") (pintype "bidirectional"))
    )
    (net (code "552") (name "unconnected-(U201D-IO_L18P{slash}T2{slash}A12{slash}D28-PadU17)") (class "Default")
      (node (ref "U201") (pin "U17") (pinfunction "IO_L18P/T2/A12/D28_U17") (pintype "bidirectional"))
    )
    (net (code "553") (name "unconnected-(U201D-IO_L19N{slash}T3{slash}VREF{slash}A9{slash}D25-PadR14)") (class "Default")
      (node (ref "U201") (pin "R14") (pinfunction "IO_L19N/T3/VREF/A9/D25_R14") (pintype "bidirectional"))
    )
    (net (code "554") (name "unconnected-(U201D-IO_L19P{slash}T3{slash}A10{slash}D26-PadP14)") (class "Default")
      (node (ref "U201") (pin "P14") (pinfunction "IO_L19P/T3/A10/D26_P14") (pintype "bidirectional"))
    )
    (net (code "555") (name "unconnected-(U201D-IO_L20N{slash}T3{slash}A7{slash}D23-PadT18)") (class "Default")
      (node (ref "U201") (pin "T18") (pinfunction "IO_L20N/T3/A7/D23_T18") (pintype "bidirectional"))
    )
    (net (code "556") (name "unconnected-(U201D-IO_L20P{slash}T3{slash}A8{slash}D24-PadR18)") (class "Default")
      (node (ref "U201") (pin "R18") (pinfunction "IO_L20P/T3/A8/D24_R18") (pintype "bidirectional"))
    )
    (net (code "557") (name "unconnected-(U201D-IO_L21N{slash}T3_DQS{slash}A6{slash}D22-PadP17)") (class "Default")
      (node (ref "U201") (pin "P17") (pinfunction "IO_L21N/T3_DQS/A6/D22_P17") (pintype "bidirectional"))
    )
    (net (code "558") (name "unconnected-(U201D-IO_L21P{slash}T3_DQS-PadN17)") (class "Default")
      (node (ref "U201") (pin "N17") (pinfunction "IO_L21P/T3_DQS_N17") (pintype "bidirectional"))
    )
    (net (code "559") (name "unconnected-(U201D-IO_L22N{slash}T3{slash}A4{slash}D20-PadR16)") (class "Default")
      (node (ref "U201") (pin "R16") (pinfunction "IO_L22N/T3/A4/D20_R16") (pintype "bidirectional"))
    )
    (net (code "560") (name "unconnected-(U201D-IO_L22P{slash}T3{slash}A5{slash}D21-PadP15)") (class "Default")
      (node (ref "U201") (pin "P15") (pinfunction "IO_L22P/T3/A5/D21_P15") (pintype "bidirectional"))
    )
    (net (code "561") (name "unconnected-(U201D-IO_L23N{slash}T3{slash}A2{slash}D18-PadN14)") (class "Default")
      (node (ref "U201") (pin "N14") (pinfunction "IO_L23N/T3/A2/D18_N14") (pintype "bidirectional"))
    )
    (net (code "562") (name "unconnected-(U201D-IO_L24N{slash}T3{slash}A0{slash}D16-PadR17)") (class "Default")
      (node (ref "U201") (pin "R17") (pinfunction "IO_L24N/T3/A0/D16_R17") (pintype "bidirectional"))
    )
    (net (code "563") (name "unconnected-(U201D-IO_L24P{slash}T3{slash}A1{slash}D17-PadP16)") (class "Default")
      (node (ref "U201") (pin "P16") (pinfunction "IO_L24P/T3/A1/D17_P16") (pintype "bidirectional"))
    )
    (net (code "564") (name "unconnected-(U201E-IO_0-PadJ16)") (class "Default")
      (node (ref "U201") (pin "J16") (pinfunction "IO_0_J16") (pintype "bidirectional"))
    )
    (net (code "565") (name "unconnected-(U201E-IO_L3P{slash}T0_DQS{slash}AD1P-PadJ14)") (class "Default")
      (node (ref "U201") (pin "J14") (pinfunction "IO_L3P/T0_DQS/AD1P_J14") (pintype "bidirectional"))
    )
    (net (code "566") (name "unconnected-(U201E-IO_L5P{slash}T0{slash}AD9P-PadJ15)") (class "Default")
      (node (ref "U201") (pin "J15") (pinfunction "IO_L5P/T0/AD9P_J15") (pintype "bidirectional"))
    )
    (net (code "567") (name "unconnected-(U201E-IO_L8N{slash}T1{slash}AD10N-PadG20)") (class "Default")
      (node (ref "U201") (pin "G20") (pinfunction "IO_L8N/T1/AD10N_G20") (pintype "bidirectional"))
    )
    (net (code "568") (name "unconnected-(U201E-IO_L13N{slash}T2{slash}MRCC-PadK19)") (class "Default")
      (node (ref "U201") (pin "K19") (pinfunction "IO_L13N/T2/MRCC_K19") (pintype "bidirectional"))
    )
    (net (code "569") (name "unconnected-(U201E-IO_L15N{slash}T2_DQS{slash}~{ADV}-PadM22)") (class "Default")
      (node (ref "U201") (pin "M22") (pinfunction "IO_L15N/T2_DQS/~{ADV}_M22") (pintype "bidirectional"))
    )
    (net (code "570") (name "unconnected-(U201E-IO_L21N{slash}T3_DQS{slash}A18-PadJ17)") (class "Default")
      (node (ref "U201") (pin "J17") (pinfunction "IO_L21N/T3_DQS/A18_J17") (pintype "bidirectional"))
    )
    (net (code "571") (name "unconnected-(U201F-IO_L1P{slash}T0-PadF13)") (class "Default")
      (node (ref "U201") (pin "F13") (pinfunction "IO_L1P/T0_F13") (pintype "bidirectional"))
    )
    (net (code "572") (name "unconnected-(U201F-IO_L2N{slash}T0-PadE17)") (class "Default")
      (node (ref "U201") (pin "E17") (pinfunction "IO_L2N/T0_E17") (pintype "bidirectional"))
    )
    (net (code "573") (name "unconnected-(U201F-IO_L3N{slash}T0_DQS-PadC15)") (class "Default")
      (node (ref "U201") (pin "C15") (pinfunction "IO_L3N/T0_DQS_C15") (pintype "bidirectional"))
    )
    (net (code "574") (name "unconnected-(U201F-IO_L3P{slash}T0_DQS-PadC14)") (class "Default")
      (node (ref "U201") (pin "C14") (pinfunction "IO_L3P/T0_DQS_C14") (pintype "bidirectional"))
    )
    (net (code "575") (name "unconnected-(U201F-IO_L4N{slash}T0-PadE14)") (class "Default")
      (node (ref "U201") (pin "E14") (pinfunction "IO_L4N/T0_E14") (pintype "bidirectional"))
    )
    (net (code "576") (name "unconnected-(U201F-IO_L4P{slash}T0-PadE13)") (class "Default")
      (node (ref "U201") (pin "E13") (pinfunction "IO_L4P/T0_E13") (pintype "bidirectional"))
    )
    (net (code "577") (name "unconnected-(U201F-IO_L5N{slash}T0-PadD16)") (class "Default")
      (node (ref "U201") (pin "D16") (pinfunction "IO_L5N/T0_D16") (pintype "bidirectional"))
    )
    (net (code "578") (name "unconnected-(U201F-IO_L5P{slash}T0-PadE16)") (class "Default")
      (node (ref "U201") (pin "E16") (pinfunction "IO_L5P/T0_E16") (pintype "bidirectional"))
    )
    (net (code "579") (name "unconnected-(U201F-IO_L6N{slash}T0{slash}VREF-PadD15)") (class "Default")
      (node (ref "U201") (pin "D15") (pinfunction "IO_L6N/T0/VREF_D15") (pintype "bidirectional"))
    )
    (net (code "580") (name "unconnected-(U201F-IO_L6P{slash}T0-PadD14)") (class "Default")
      (node (ref "U201") (pin "D14") (pinfunction "IO_L6P/T0_D14") (pintype "bidirectional"))
    )
    (net (code "581") (name "unconnected-(U201F-IO_L7N{slash}T1-PadB16)") (class "Default")
      (node (ref "U201") (pin "B16") (pinfunction "IO_L7N/T1_B16") (pintype "bidirectional"))
    )
    (net (code "582") (name "unconnected-(U201F-IO_L7P{slash}T1-PadB15)") (class "Default")
      (node (ref "U201") (pin "B15") (pinfunction "IO_L7P/T1_B15") (pintype "bidirectional"))
    )
    (net (code "583") (name "unconnected-(U201F-IO_L8N{slash}T1-PadB13)") (class "Default")
      (node (ref "U201") (pin "B13") (pinfunction "IO_L8N/T1_B13") (pintype "bidirectional"))
    )
    (net (code "584") (name "unconnected-(U201F-IO_L8P{slash}T1-PadC13)") (class "Default")
      (node (ref "U201") (pin "C13") (pinfunction "IO_L8P/T1_C13") (pintype "bidirectional"))
    )
    (net (code "585") (name "unconnected-(U201F-IO_L11N{slash}T1{slash}SRCC-PadB18)") (class "Default")
      (node (ref "U201") (pin "B18") (pinfunction "IO_L11N/T1/SRCC_B18") (pintype "bidirectional"))
    )
    (net (code "586") (name "unconnected-(U201F-IO_L11P{slash}T1{slash}SRCC-PadB17)") (class "Default")
      (node (ref "U201") (pin "B17") (pinfunction "IO_L11P/T1/SRCC_B17") (pintype "bidirectional"))
    )
    (net (code "587") (name "unconnected-(U201F-IO_L12N{slash}T1{slash}MRCC-PadC17)") (class "Default")
      (node (ref "U201") (pin "C17") (pinfunction "IO_L12N/T1/MRCC_C17") (pintype "bidirectional"))
    )
    (net (code "588") (name "unconnected-(U201F-IO_L13N{slash}T2{slash}MRCC-PadC19)") (class "Default")
      (node (ref "U201") (pin "C19") (pinfunction "IO_L13N/T2/MRCC_C19") (pintype "bidirectional"))
    )
    (net (code "589") (name "unconnected-(U201F-IO_L13P{slash}T2{slash}MRCC-PadC18)") (class "Default")
      (node (ref "U201") (pin "C18") (pinfunction "IO_L13P/T2/MRCC_C18") (pintype "bidirectional"))
    )
    (net (code "590") (name "unconnected-(U201F-IO_L15N{slash}T2_DQS-PadE18)") (class "Default")
      (node (ref "U201") (pin "E18") (pinfunction "IO_L15N/T2_DQS_E18") (pintype "bidirectional"))
    )
    (net (code "591") (name "unconnected-(U201F-IO_L16P{slash}T2-PadB20)") (class "Default")
      (node (ref "U201") (pin "B20") (pinfunction "IO_L16P/T2_B20") (pintype "bidirectional"))
    )
    (net (code "592") (name "unconnected-(U201F-IO_L18P{slash}T2-PadF19)") (class "Default")
      (node (ref "U201") (pin "F19") (pinfunction "IO_L18P/T2_F19") (pintype "bidirectional"))
    )
    (net (code "593") (name "unconnected-(U201F-IO_L19N{slash}T3{slash}VREF-PadC20)") (class "Default")
      (node (ref "U201") (pin "C20") (pinfunction "IO_L19N/T3/VREF_C20") (pintype "bidirectional"))
    )
    (net (code "594") (name "unconnected-(U201F-IO_L19P{slash}T3-PadD20)") (class "Default")
      (node (ref "U201") (pin "D20") (pinfunction "IO_L19P/T3_D20") (pintype "bidirectional"))
    )
    (net (code "595") (name "unconnected-(U201F-IO_L20N{slash}T3-PadB22)") (class "Default")
      (node (ref "U201") (pin "B22") (pinfunction "IO_L20N/T3_B22") (pintype "bidirectional"))
    )
    (net (code "596") (name "unconnected-(U201F-IO_L20P{slash}T3-PadC22)") (class "Default")
      (node (ref "U201") (pin "C22") (pinfunction "IO_L20P/T3_C22") (pintype "bidirectional"))
    )
    (net (code "597") (name "unconnected-(U201F-IO_L21P{slash}T3_DQS-PadB21)") (class "Default")
      (node (ref "U201") (pin "B21") (pinfunction "IO_L21P/T3_DQS_B21") (pintype "bidirectional"))
    )
    (net (code "598") (name "unconnected-(U201F-IO_L22P{slash}T3-PadE22)") (class "Default")
      (node (ref "U201") (pin "E22") (pinfunction "IO_L22P/T3_E22") (pintype "bidirectional"))
    )
    (net (code "599") (name "unconnected-(U201G-MGTPTXN1-PadC5)") (class "Default")
      (node (ref "U201") (pin "C5") (pinfunction "MGTPTXN1_C5") (pintype "bidirectional"))
    )
    (net (code "600") (name "unconnected-(U201G-MGTPTXP1-PadD5)") (class "Default")
      (node (ref "U201") (pin "D5") (pinfunction "MGTPTXP1_D5") (pintype "bidirectional"))
    )
    (net (code "601") (name "unconnected-(U201H-IO_0-PadT3)") (class "Default")
      (node (ref "U201") (pin "T3") (pinfunction "IO_0_T3") (pintype "bidirectional"))
    )
    (net (code "602") (name "unconnected-(U201H-IO_25-PadU7)") (class "Default")
      (node (ref "U201") (pin "U7") (pinfunction "IO_25_U7") (pintype "bidirectional"))
    )
    (net (code "603") (name "unconnected-(U201H-IO_L13N{slash}T2{slash}MRCC-PadT4)") (class "Default")
      (node (ref "U201") (pin "T4") (pinfunction "IO_L13N/T2/MRCC_T4") (pintype "bidirectional"))
    )
    (net (code "604") (name "unconnected-(U201H-IO_L20N{slash}T3-PadAB6)") (class "Default")
      (node (ref "U201") (pin "AB6") (pinfunction "IO_L20N/T3_AB6") (pintype "bidirectional"))
    )
    (net (code "605") (name "unconnected-(U201H-IO_L20P{slash}T3-PadAB7)") (class "Default")
      (node (ref "U201") (pin "AB7") (pinfunction "IO_L20P/T3_AB7") (pintype "bidirectional"))
    )
    (net (code "606") (name "unconnected-(U201H-IO_L22N{slash}T3-PadAB8)") (class "Default")
      (node (ref "U201") (pin "AB8") (pinfunction "IO_L22N/T3_AB8") (pintype "bidirectional"))
    )
    (net (code "607") (name "unconnected-(U201H-IO_L22P{slash}T3-PadAA8)") (class "Default")
      (node (ref "U201") (pin "AA8") (pinfunction "IO_L22P/T3_AA8") (pintype "bidirectional"))
    )
    (net (code "608") (name "unconnected-(U201H-IO_L23N{slash}T3-PadY7)") (class "Default")
      (node (ref "U201") (pin "Y7") (pinfunction "IO_L23N/T3_Y7") (pintype "bidirectional"))
    )
    (net (code "609") (name "unconnected-(U201H-IO_L23P{slash}T3-PadY8)") (class "Default")
      (node (ref "U201") (pin "Y8") (pinfunction "IO_L23P/T3_Y8") (pintype "bidirectional"))
    )
    (net (code "610") (name "unconnected-(U201H-IO_L24N{slash}T3-PadY9)") (class "Default")
      (node (ref "U201") (pin "Y9") (pinfunction "IO_L24N/T3_Y9") (pintype "bidirectional"))
    )
    (net (code "611") (name "unconnected-(U201H-IO_L24P{slash}T3-PadW9)") (class "Default")
      (node (ref "U201") (pin "W9") (pinfunction "IO_L24P/T3_W9") (pintype "bidirectional"))
    )
    (net (code "612") (name "unconnected-(U201I-IO_0-PadF4)") (class "Default")
      (node (ref "U201") (pin "F4") (pinfunction "IO_0_F4") (pintype "bidirectional"))
    )
    (net (code "613") (name "unconnected-(U201I-IO_25-PadL6)") (class "Default")
      (node (ref "U201") (pin "L6") (pinfunction "IO_25_L6") (pintype "bidirectional"))
    )
    (net (code "614") (name "unconnected-(U201I-IO_L2N{slash}T0{slash}AD12N-PadB2)") (class "Default")
      (node (ref "U201") (pin "B2") (pinfunction "IO_L2N/T0/AD12N_B2") (pintype "bidirectional"))
    )
    (net (code "615") (name "unconnected-(U201I-IO_L2P{slash}T0{slash}AD12P-PadC2)") (class "Default")
      (node (ref "U201") (pin "C2") (pinfunction "IO_L2P/T0/AD12P_C2") (pintype "bidirectional"))
    )
    (net (code "616") (name "unconnected-(U201I-IO_L3N{slash}T0_DQS{slash}AD5N-PadD1)") (class "Default")
      (node (ref "U201") (pin "D1") (pinfunction "IO_L3N/T0_DQS/AD5N_D1") (pintype "bidirectional"))
    )
    (net (code "617") (name "unconnected-(U201I-IO_L3P{slash}T0_DQS{slash}AD5P-PadE1)") (class "Default")
      (node (ref "U201") (pin "E1") (pinfunction "IO_L3P/T0_DQS/AD5P_E1") (pintype "bidirectional"))
    )
    (net (code "618") (name "unconnected-(U201I-IO_L4N{slash}T0-PadD2)") (class "Default")
      (node (ref "U201") (pin "D2") (pinfunction "IO_L4N/T0_D2") (pintype "bidirectional"))
    )
    (net (code "619") (name "unconnected-(U201I-IO_L4P{slash}T0-PadE2)") (class "Default")
      (node (ref "U201") (pin "E2") (pinfunction "IO_L4P/T0_E2") (pintype "bidirectional"))
    )
    (net (code "620") (name "unconnected-(U201I-IO_L5N{slash}T0{slash}AD13N-PadF1)") (class "Default")
      (node (ref "U201") (pin "F1") (pinfunction "IO_L5N/T0/AD13N_F1") (pintype "bidirectional"))
    )
    (net (code "621") (name "unconnected-(U201I-IO_L5P{slash}T0{slash}AD13P-PadG1)") (class "Default")
      (node (ref "U201") (pin "G1") (pinfunction "IO_L5P/T0/AD13P_G1") (pintype "bidirectional"))
    )
    (net (code "622") (name "unconnected-(U201I-IO_L6P{slash}T0-PadF3)") (class "Default")
      (node (ref "U201") (pin "F3") (pinfunction "IO_L6P/T0_F3") (pintype "bidirectional"))
    )
    (net (code "623") (name "unconnected-(U201I-IO_L7N{slash}T1{slash}AD6N-PadJ1)") (class "Default")
      (node (ref "U201") (pin "J1") (pinfunction "IO_L7N/T1/AD6N_J1") (pintype "bidirectional"))
    )
    (net (code "624") (name "unconnected-(U201I-IO_L7P{slash}T1{slash}AD6P-PadK1)") (class "Default")
      (node (ref "U201") (pin "K1") (pinfunction "IO_L7P/T1/AD6P_K1") (pintype "bidirectional"))
    )
    (net (code "625") (name "unconnected-(U201I-IO_L8N{slash}T1{slash}AD14N-PadG2)") (class "Default")
      (node (ref "U201") (pin "G2") (pinfunction "IO_L8N/T1/AD14N_G2") (pintype "bidirectional"))
    )
    (net (code "626") (name "unconnected-(U201I-IO_L8P{slash}T1{slash}AD14P-PadH2)") (class "Default")
      (node (ref "U201") (pin "H2") (pinfunction "IO_L8P/T1/AD14P_H2") (pintype "bidirectional"))
    )
    (net (code "627") (name "unconnected-(U201I-IO_L9N{slash}T1_DQS{slash}AD7N-PadJ2)") (class "Default")
      (node (ref "U201") (pin "J2") (pinfunction "IO_L9N/T1_DQS/AD7N_J2") (pintype "bidirectional"))
    )
    (net (code "628") (name "unconnected-(U201I-IO_L9P{slash}T1_DQS{slash}AD7P-PadK2)") (class "Default")
      (node (ref "U201") (pin "K2") (pinfunction "IO_L9P/T1_DQS/AD7P_K2") (pintype "bidirectional"))
    )
    (net (code "629") (name "unconnected-(U201I-IO_L10N{slash}T1{slash}AD15N-PadH5)") (class "Default")
      (node (ref "U201") (pin "H5") (pinfunction "IO_L10N/T1/AD15N_H5") (pintype "bidirectional"))
    )
    (net (code "630") (name "unconnected-(U201I-IO_L10P{slash}T1{slash}AD15P-PadJ5)") (class "Default")
      (node (ref "U201") (pin "J5") (pinfunction "IO_L10P/T1/AD15P_J5") (pintype "bidirectional"))
    )
    (net (code "631") (name "unconnected-(U201I-IO_L11N{slash}T1{slash}SRCC-PadG3)") (class "Default")
      (node (ref "U201") (pin "G3") (pinfunction "IO_L11N/T1/SRCC_G3") (pintype "bidirectional"))
    )
    (net (code "632") (name "unconnected-(U201I-IO_L11P{slash}T1{slash}SRCC-PadH3)") (class "Default")
      (node (ref "U201") (pin "H3") (pinfunction "IO_L11P/T1/SRCC_H3") (pintype "bidirectional"))
    )
    (net (code "633") (name "unconnected-(U201I-IO_L12N{slash}T1{slash}MRCC-PadG4)") (class "Default")
      (node (ref "U201") (pin "G4") (pinfunction "IO_L12N/T1/MRCC_G4") (pintype "bidirectional"))
    )
    (net (code "634") (name "unconnected-(U201I-IO_L12P{slash}T1{slash}MRCC-PadH4)") (class "Default")
      (node (ref "U201") (pin "H4") (pinfunction "IO_L12P/T1/MRCC_H4") (pintype "bidirectional"))
    )
    (net (code "635") (name "unconnected-(U201I-IO_L13N{slash}T2{slash}MRCC-PadJ4)") (class "Default")
      (node (ref "U201") (pin "J4") (pinfunction "IO_L13N/T2/MRCC_J4") (pintype "bidirectional"))
    )
    (net (code "636") (name "unconnected-(U201I-IO_L13P{slash}T2{slash}MRCC-PadK4)") (class "Default")
      (node (ref "U201") (pin "K4") (pinfunction "IO_L13P/T2/MRCC_K4") (pintype "bidirectional"))
    )
    (net (code "637") (name "unconnected-(U201I-IO_L14N{slash}T2{slash}SRCC-PadK3)") (class "Default")
      (node (ref "U201") (pin "K3") (pinfunction "IO_L14N/T2/SRCC_K3") (pintype "bidirectional"))
    )
    (net (code "638") (name "unconnected-(U201I-IO_L14P{slash}T2{slash}SRCC-PadL3)") (class "Default")
      (node (ref "U201") (pin "L3") (pinfunction "IO_L14P/T2/SRCC_L3") (pintype "bidirectional"))
    )
    (net (code "639") (name "unconnected-(U201I-IO_L15N{slash}T2_DQS-PadL1)") (class "Default")
      (node (ref "U201") (pin "L1") (pinfunction "IO_L15N/T2_DQS_L1") (pintype "bidirectional"))
    )
    (net (code "640") (name "unconnected-(U201I-IO_L15P{slash}T2_DQS-PadM1)") (class "Default")
      (node (ref "U201") (pin "M1") (pinfunction "IO_L15P/T2_DQS_M1") (pintype "bidirectional"))
    )
    (net (code "641") (name "unconnected-(U201I-IO_L16N{slash}T2-PadM2)") (class "Default")
      (node (ref "U201") (pin "M2") (pinfunction "IO_L16N/T2_M2") (pintype "bidirectional"))
    )
    (net (code "642") (name "unconnected-(U201I-IO_L16P{slash}T2-PadM3)") (class "Default")
      (node (ref "U201") (pin "M3") (pinfunction "IO_L16P/T2_M3") (pintype "bidirectional"))
    )
    (net (code "643") (name "unconnected-(U201I-IO_L17N{slash}T2-PadJ6)") (class "Default")
      (node (ref "U201") (pin "J6") (pinfunction "IO_L17N/T2_J6") (pintype "bidirectional"))
    )
    (net (code "644") (name "unconnected-(U201I-IO_L17P{slash}T2-PadK6)") (class "Default")
      (node (ref "U201") (pin "K6") (pinfunction "IO_L17P/T2_K6") (pintype "bidirectional"))
    )
    (net (code "645") (name "unconnected-(U201I-IO_L18N{slash}T2-PadL4)") (class "Default")
      (node (ref "U201") (pin "L4") (pinfunction "IO_L18N/T2_L4") (pintype "bidirectional"))
    )
    (net (code "646") (name "unconnected-(U201I-IO_L18P{slash}T2-PadL5)") (class "Default")
      (node (ref "U201") (pin "L5") (pinfunction "IO_L18P/T2_L5") (pintype "bidirectional"))
    )
    (net (code "647") (name "unconnected-(U401A-DATA_CLK_N-PadH11)") (class "Default")
      (node (ref "U401") (pin "H11") (pinfunction "DATA_CLK_N_H11") (pintype "bidirectional"))
    )
    (net (code "648") (name "unconnected-(U401A-RX_FRAME_N-PadG7)") (class "Default")
      (node (ref "U401") (pin "G7") (pinfunction "RX_FRAME_N_G7") (pintype "bidirectional"))
    )
    (net (code "649") (name "unconnected-(U401A-XTALP-PadM11)") (class "Default")
      (node (ref "U401") (pin "M11") (pinfunction "XTALP_M11") (pintype "bidirectional"))
    )
    (net (code "650") (name "unconnected-(U401C-AUXDAC1-PadB3)") (class "Default")
      (node (ref "U401") (pin "B3") (pinfunction "AUXDAC1_B3") (pintype "bidirectional"))
    )
    (net (code "651") (name "unconnected-(U401C-AUXDAC2-PadC3)") (class "Default")
      (node (ref "U401") (pin "C3") (pinfunction "AUXDAC2_C3") (pintype "bidirectional"))
    )
    (net (code "652") (name "unconnected-(U701-HPOUTLN{slash}LOUTLN-Pad21)") (class "Default")
      (node (ref "U701") (pin "21") (pinfunction "HPOUTLN/LOUTLN_21") (pintype "bidirectional"))
    )
    (net (code "653") (name "unconnected-(U701-HPOUTRN{slash}LOUTRN-Pad25)") (class "Default")
      (node (ref "U701") (pin "25") (pinfunction "HPOUTRN/LOUTRN_25") (pintype "bidirectional"))
    )
    (net (code "654") (name "unconnected-(U701-XTALO-Pad38)") (class "Default")
      (node (ref "U701") (pin "38") (pinfunction "XTALO_38") (pintype "bidirectional"))
    )
    (net (code "655") (name "unconnected-(U902-XB-Pad2)") (class "Default")
      (node (ref "U902") (pin "2") (pinfunction "XB_2") (pintype "bidirectional"))
    )
    (net (code "656") (name "unconnected-(U1001-READY-Pad5)") (class "Default")
      (node (ref "U1001") (pin "5") (pinfunction "READY_5") (pintype "bidirectional"))
    )
    (net (code "657") (name "unconnected-(U1205-PG-Pad5)") (class "Default")
      (node (ref "U1205") (pin "5") (pinfunction "PG_5") (pintype "bidirectional"))
    )
    (net (code "658") (name "unconnected-(USB1001-SB1-PadA8)") (class "Default")
      (node (ref "USB1001") (pin "A8") (pinfunction "SB1_A8") (pintype "bidirectional"))
    )
    (net (code "659") (name "unconnected-(USB1001-SB2-PadB8)") (class "Default")
      (node (ref "USB1001") (pin "B8") (pinfunction "SB2_B8") (pintype "bidirectional"))
    )
    (net (code "660") (name "~{5V0_TRX_BIAS_T1_OC}") (class "Default")
      (node (ref "R503") (pin "1") (pinfunction "1_1") (pintype "passive"))
      (node (ref "U201") (pin "A20") (pinfunction "IO_L16N/T2_A20") (pintype "bidirectional"))
      (node (ref "U501") (pin "4") (pinfunction "~{FAULT}_4") (pintype "bidirectional"))
    )
    (net (code "661") (name "~{5V0_TRX_BIAS_T2_OC}") (class "Default")
      (node (ref "R504") (pin "1") (pinfunction "1_1") (pintype "passive"))
      (node (ref "U201") (pin "A18") (pinfunction "IO_L17P/T2_A18") (pintype "bidirectional"))
      (node (ref "U502") (pin "4") (pinfunction "~{FAULT}_4") (pintype "bidirectional"))
    )
    (net (code "662") (name "~{5V0_TRX_PA1_OC}") (class "Default")
      (node (ref "R509") (pin "1") (pinfunction "1_1") (pintype "passive"))
      (node (ref "U201") (pin "A19") (pinfunction "IO_L17N/T2_A19") (pintype "bidirectional"))
      (node (ref "U503") (pin "4") (pinfunction "~{FAULT}_4") (pintype "bidirectional"))
    )
    (net (code "663") (name "~{5V0_TRX_PA2_OC}") (class "Default")
      (node (ref "R510") (pin "1") (pinfunction "1_1") (pintype "passive"))
      (node (ref "U201") (pin "A21") (pinfunction "IO_L21N/T3_DQS_A21") (pintype "bidirectional"))
      (node (ref "U504") (pin "4") (pinfunction "~{FAULT}_4") (pintype "bidirectional"))
    )
    (net (code "664") (name "~{CLK_MNGR_IRQ}") (class "Default")
      (node (ref "R905") (pin "1") (pinfunction "1_1") (pintype "passive"))
      (node (ref "U201") (pin "U21") (pinfunction "IO_L4N/T0/D5_U21") (pintype "bidirectional"))
      (node (ref "U902") (pin "3") (pinfunction "~{INTR}_3") (pintype "bidirectional"))
    )
    (net (code "665") (name "~{CLK_MNGR_OE}") (class "Default")
      (node (ref "R904") (pin "1") (pinfunction "1_1") (pintype "passive"))
      (node (ref "U201") (pin "T20") (pinfunction "IO_L6N/T0/D8/VREF_T20") (pintype "bidirectional"))
      (node (ref "U902") (pin "7") (pinfunction "~{OE}_7") (pintype "bidirectional"))
    )
    (net (code "666") (name "~{CM4_ACT_LED}") (class "Default")
      (node (ref "D101") (pin "C") (pinfunction "C_C") (pintype "passive"))
      (node (ref "U102") (pin "21") (pinfunction "~{PI_LED_ACT}_21") (pintype "bidirectional"))
    )
    (net (code "667") (name "~{CM4_BTLDR}") (class "Default")
      (node (ref "U1002") (pin "36") (pinfunction "PA22/GPIO6_36") (pintype "bidirectional"))
      (node (ref "U102") (pin "93") (pinfunction "~{RPIBOOT}_93") (pintype "bidirectional"))
    )
    (net (code "668") (name "~{CM4_PWR_LED}") (class "Default")
      (node (ref "Q101") (pin "1") (pinfunction "G_1") (pintype "passive"))
      (node (ref "U102") (pin "95") (pinfunction "~{PI_LED_PWR}_95") (pintype "bidirectional"))
    )
    (net (code "669") (name "~{CODEC_RST}") (class "Default")
      (node (ref "R701") (pin "2") (pinfunction "2_2") (pintype "passive"))
      (node (ref "U201") (pin "Y19") (pinfunction "IO_L13N/T2/MRCC_Y19") (pintype "bidirectional"))
      (node (ref "U701") (pin "27") (pinfunction "~{PD}_27") (pintype "bidirectional"))
    )
    (net (code "670") (name "~{DDR3_CAS}") (class "Default")
      (node (ref "R327") (pin "1") (pinfunction "1_1") (pintype "passive"))
      (node (ref "U201") (pin "T6") (pinfunction "IO_L17N/T2_T6") (pintype "bidirectional"))
      (node (ref "U301") (pin "K3") (pinfunction "~{CAS}_K3") (pintype "bidirectional"))
    )
    (net (code "671") (name "~{DDR3_RAS}") (class "Default")
      (node (ref "R323") (pin "1") (pinfunction "1_1") (pintype "passive"))
      (node (ref "U201") (pin "R6") (pinfunction "IO_L17P/T2_R6") (pintype "bidirectional"))
      (node (ref "U301") (pin "J3") (pinfunction "~{RAS}_J3") (pintype "bidirectional"))
    )
    (net (code "672") (name "~{DDR3_RESET}") (class "Default")
      (node (ref "R302") (pin "2") (pinfunction "2_2") (pintype "passive"))
      (node (ref "R324") (pin "1") (pinfunction "1_1") (pintype "passive"))
      (node (ref "U201") (pin "R4") (pinfunction "IO_L13P/T2/MRCC_R4") (pintype "bidirectional"))
      (node (ref "U301") (pin "T2") (pinfunction "~{RESET}_T2") (pintype "bidirectional"))
    )
    (net (code "673") (name "~{DDR3_WE}") (class "Default")
      (node (ref "R322") (pin "1") (pinfunction "1_1") (pintype "passive"))
      (node (ref "U201") (pin "Y6") (pinfunction "IO_L18P/T2_Y6") (pintype "bidirectional"))
      (node (ref "U301") (pin "L3") (pinfunction "~{WE}_L3") (pintype "bidirectional"))
    )
    (net (code "674") (name "~{FPGA_FLASH_CS}") (class "Default")
      (node (ref "R215") (pin "1") (pinfunction "1_1") (pintype "passive"))
      (node (ref "U201") (pin "T19") (pinfunction "IO_L6P/T0/~{FCS}_T19") (pintype "bidirectional"))
      (node (ref "U202") (pin "1") (pinfunction "~{CS}_1") (pintype "input"))
    )
    (net (code "675") (name "~{FPGA_INIT}") (class "Default")
      (node (ref "D201") (pin "A") (pinfunction "A_A") (pintype "passive"))
      (node (ref "R219") (pin "1") (pinfunction "1_1") (pintype "passive"))
      (node (ref "U1002") (pin "11") (pinfunction "PA01_11") (pintype "bidirectional"))
      (node (ref "U201") (pin "U12") (pinfunction "~{INIT}_U12") (pintype "bidirectional"))
    )
    (net (code "676") (name "~{FPGA_PROGRAM}") (class "Default")
      (node (ref "R214") (pin "1") (pinfunction "1_1") (pintype "passive"))
      (node (ref "TC201") (pin "9") (pinfunction "S_9") (pintype "passive"))
      (node (ref "U201") (pin "N12") (pinfunction "~{PROGRAM}_N12") (pintype "bidirectional"))
    )
    (net (code "677") (name "~{PCIE_CM4_CLK_REQ}") (class "Default")
      (node (ref "R802") (pin "1") (pinfunction "1_1") (pintype "passive"))
      (node (ref "U102") (pin "102") (pinfunction "~{PCIE_CLK_REQ}_102") (pintype "bidirectional"))
      (node (ref "U201") (pin "V22") (pinfunction "IO_L3N/T0_DQS/EMCCLK_V22") (pintype "bidirectional"))
    )
    (net (code "678") (name "~{PCIE_CM4_RST}") (class "Default")
      (node (ref "R801") (pin "1") (pinfunction "1_1") (pintype "passive"))
      (node (ref "U102") (pin "109") (pinfunction "~{PCIE_RST}_109") (pintype "bidirectional"))
      (node (ref "U201") (pin "V20") (pinfunction "IO_L11N/T1/SRCC_V20") (pintype "bidirectional"))
    )
    (net (code "679") (name "~{PCIE_SLOT_CLK_REQ}") (class "Default")
      (node (ref "CON801") (pin "B12") (pinfunction "S_B12") (pintype "passive"))
      (node (ref "R803") (pin "1") (pinfunction "1_1") (pintype "passive"))
      (node (ref "U201") (pin "W20") (pinfunction "IO_L12N/T1/MRCC_W20") (pintype "bidirectional"))
    )
    (net (code "680") (name "~{PCIE_SLOT_RST}") (class "Default")
      (node (ref "C813") (pin "1") (pinfunction "C1_1") (pintype "passive"))
      (node (ref "CON801") (pin "A11") (pinfunction "S_A11") (pintype "passive"))
      (node (ref "R805") (pin "1") (pinfunction "1_1") (pintype "passive"))
      (node (ref "U201") (pin "W21") (pinfunction "IO_L7P/T1/D9_W21") (pintype "bidirectional"))
    )
    (net (code "681") (name "~{PCIE_SLOT_WAKE}") (class "Default")
      (node (ref "CON801") (pin "B11") (pinfunction "S_B11") (pintype "passive"))
      (node (ref "R804") (pin "1") (pinfunction "1_1") (pintype "passive"))
      (node (ref "U201") (pin "W22") (pinfunction "IO_L7N/T1/D10_W22") (pintype "bidirectional"))
    )
    (net (code "682") (name "~{PMC_BTN}") (class "Default")
      (node (ref "C1003") (pin "1") (pinfunction "C1_1") (pintype "passive"))
      (node (ref "R1002") (pin "1") (pinfunction "1_1") (pintype "passive"))
      (node (ref "S1001") (pin "3") (pinfunction "3_3") (pintype "passive"))
      (node (ref "S1001") (pin "4") (pinfunction "4_4") (pintype "passive"))
      (node (ref "U1002") (pin "38") (pinfunction "GPIO8_38") (pintype "bidirectional"))
    )
    (net (code "683") (name "~{PMC_RESET}") (class "Default")
      (node (ref "R1014") (pin "1") (pinfunction "1_1") (pintype "passive"))
      (node (ref "TC1001") (pin "10") (pinfunction "S_10") (pintype "passive"))
      (node (ref "U1002") (pin "33") (pinfunction "~{RESET_COM}_33") (pintype "bidirectional"))
      (node (ref "U1002") (pin "40") (pinfunction "~{RESET}_40") (pintype "bidirectional"))
    )
    (net (code "684") (name "~{SYNTH_RESET}") (class "Default")
      (node (ref "R601") (pin "2") (pinfunction "2_2") (pintype "passive"))
      (node (ref "U201") (pin "AA16") (pinfunction "IO_L1N/T0_AA16") (pintype "bidirectional"))
      (node (ref "U601") (pin "31") (pinfunction "~{RESET}_31") (pintype "bidirectional"))
    )
    (net (code "685") (name "~{SYNTH_SPI_CS}") (class "Default")
      (node (ref "U201") (pin "AA20") (pinfunction "IO_L8P/T1/D11_AA20") (pintype "bidirectional"))
      (node (ref "U601") (pin "25") (pinfunction "~{CS}_25") (pintype "bidirectional"))
    )
    (net (code "686") (name "~{TRX_RESET}") (class "Default")
      (node (ref "U201") (pin "G16") (pinfunction "IO_L2N/T0/AD8N_G16") (pintype "bidirectional"))
      (node (ref "U401") (pin "K5") (pinfunction "~{RESET}_K5") (pintype "bidirectional"))
    )
    (net (code "687") (name "~{TRX_SPI_CS}") (class "Default")
      (node (ref "U201") (pin "G13") (pinfunction "IO_L1N/T0/AD0N_G13") (pintype "bidirectional"))
      (node (ref "U401") (pin "K6") (pinfunction "~{SPI_EN}_K6") (pintype "bidirectional"))
    )
    (net (code "688") (name "~{VBUS_SRC_FAULT}") (class "Default")
      (node (ref "R1011") (pin "1") (pinfunction "1_1") (pintype "passive"))
      (node (ref "U1002") (pin "27") (pinfunction "GPIO3_27") (pintype "bidirectional"))
      (node (ref "U1003") (pin "4") (pinfunction "~{FAULT}_4") (pintype "bidirectional"))
    )
    (net (code "689") (name "~{VIN_REG_ALERT}") (class "Default")
      (node (ref "R1118") (pin "1") (pinfunction "1_1") (pintype "passive"))
      (node (ref "U1102") (pin "29") (pinfunction "~{ALERT}_29") (pintype "bidirectional"))
      (node (ref "U201") (pin "W15") (pinfunction "IO_L16P/T2_W15") (pintype "bidirectional"))
    )
  )
)
